# rtc.net
KiCad netlist of a schematic drawn in EAGLE
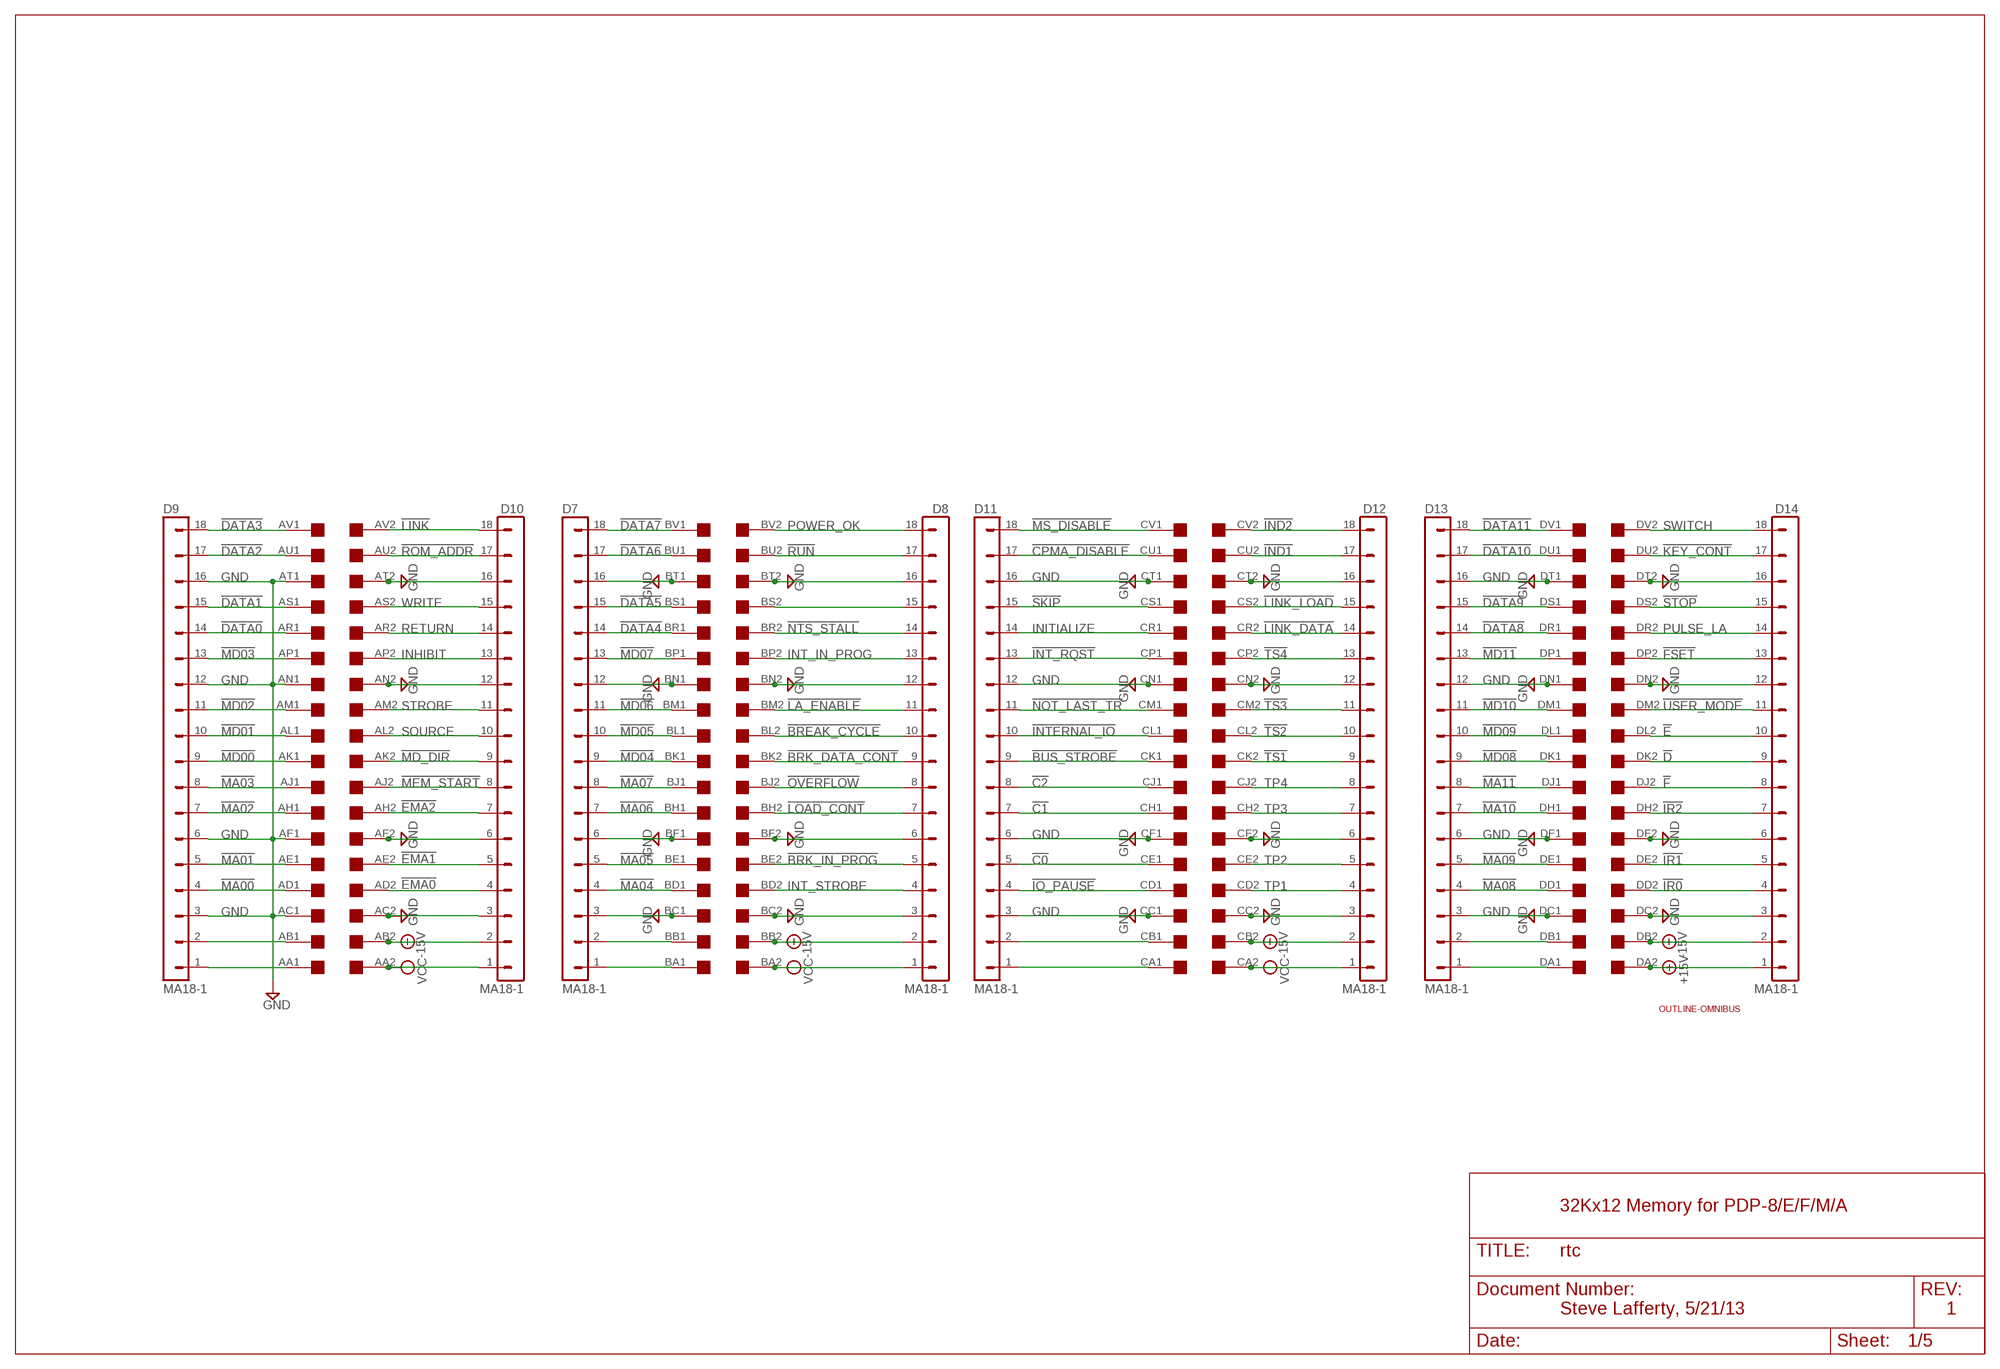
[diagram p0: schematic, sheet 1]
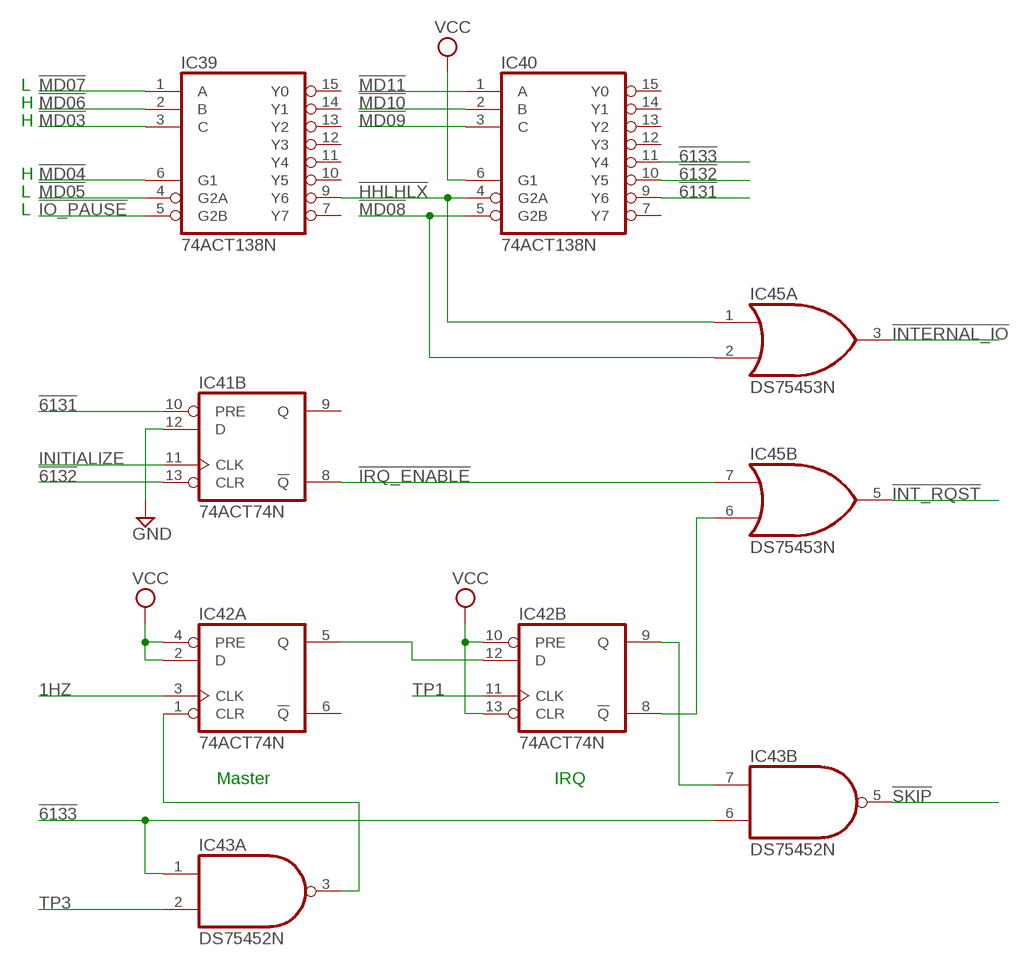
[diagram p1: schematic, sheet 2, part 1 of 2]
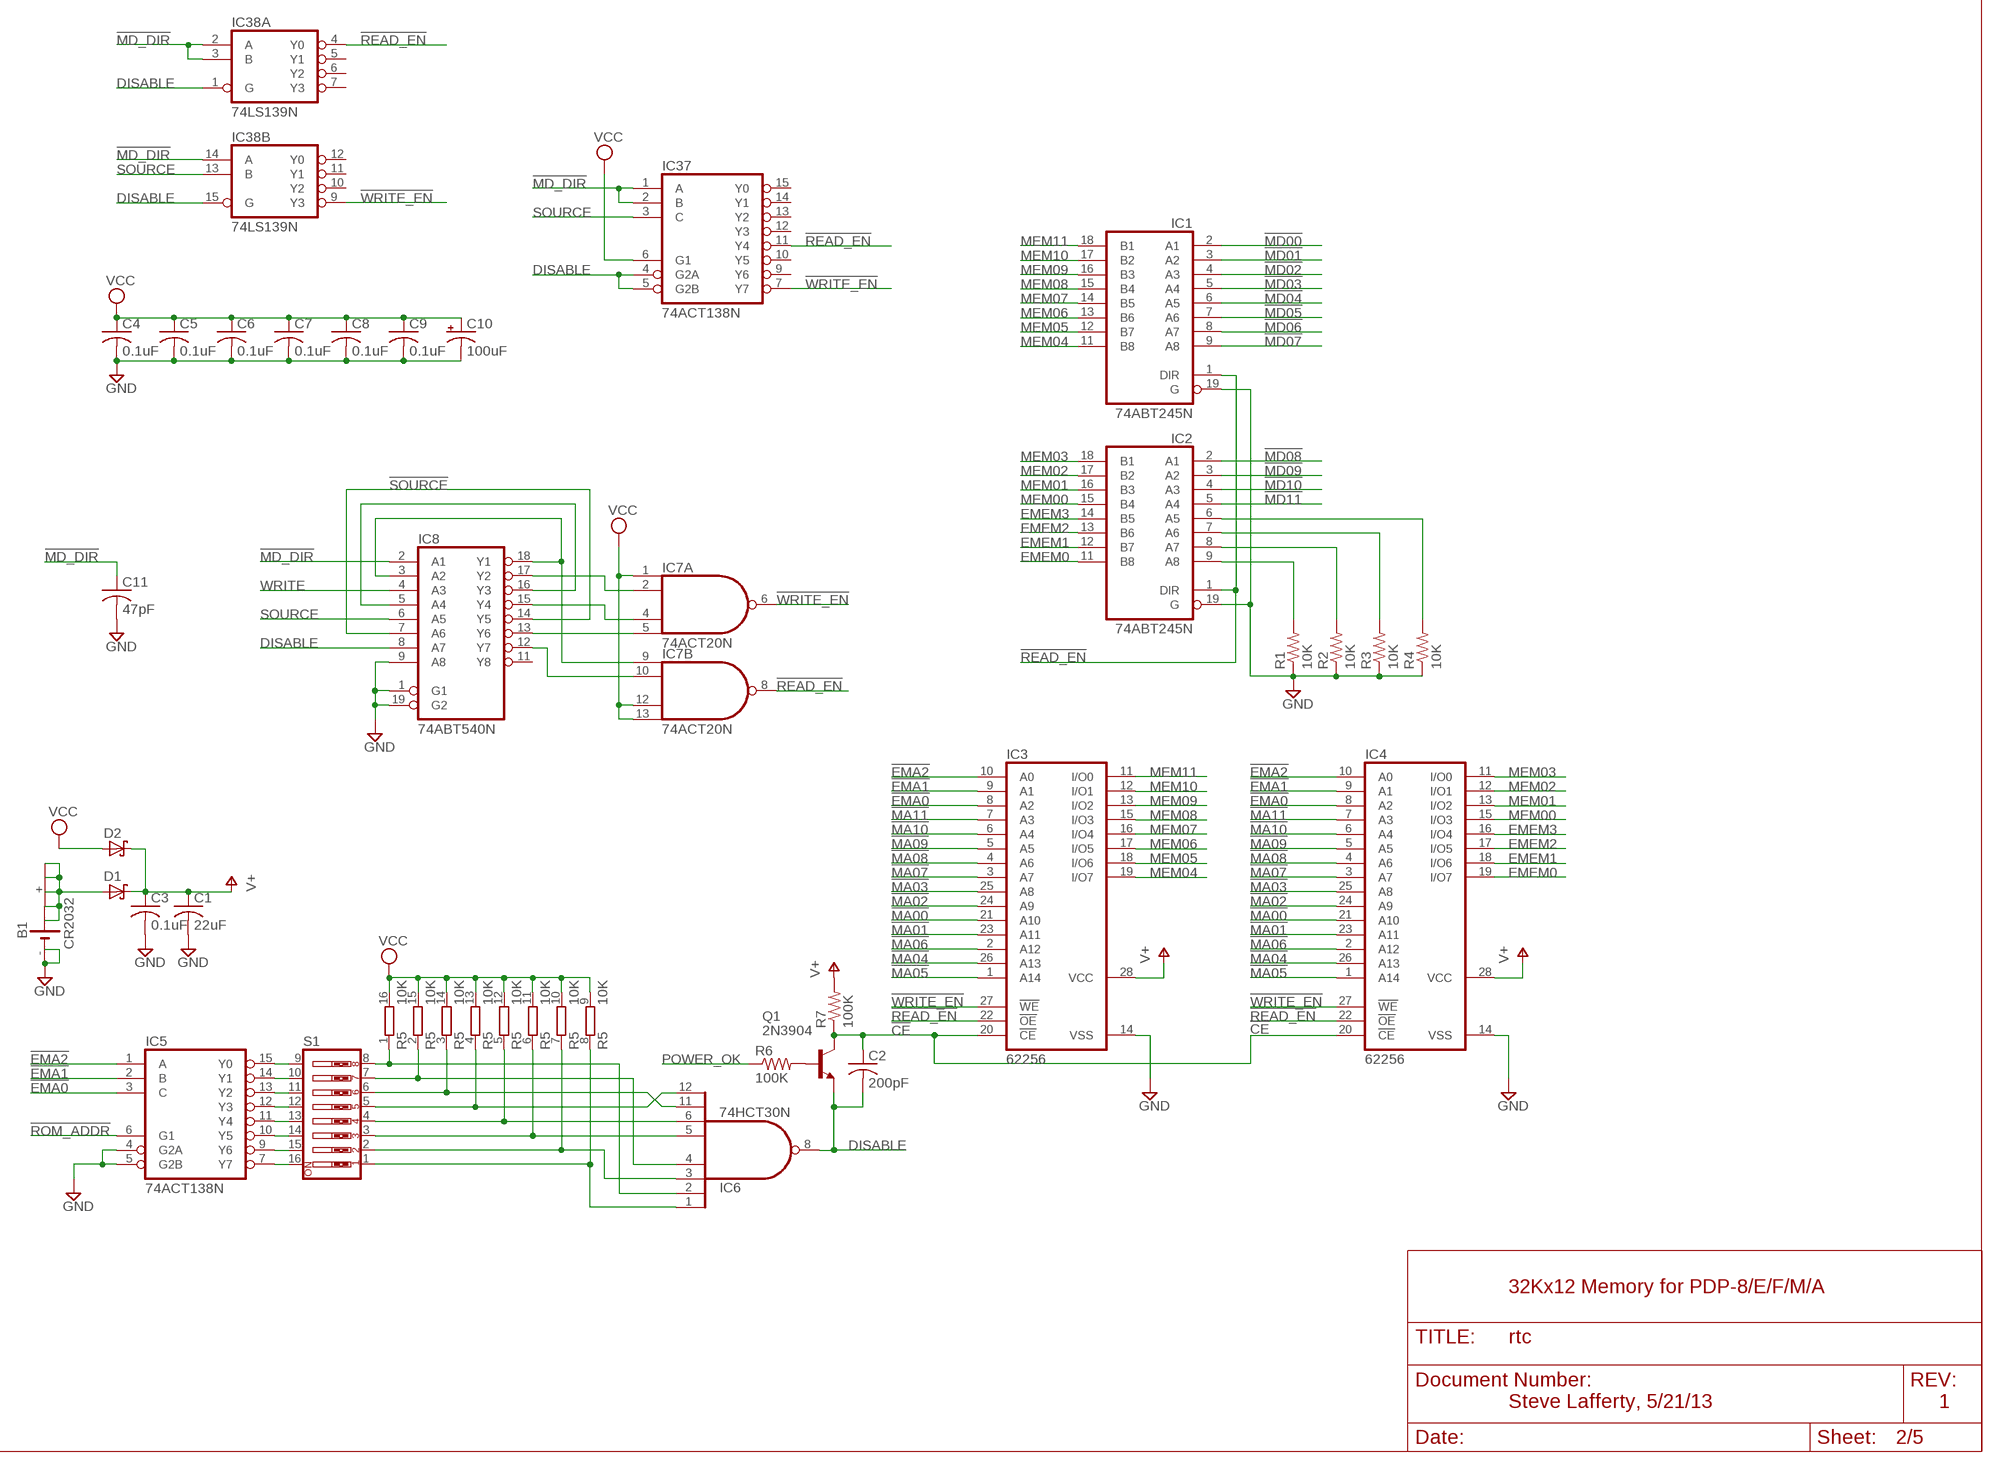
[diagram p2: schematic, sheet 2, part 2 of 2]
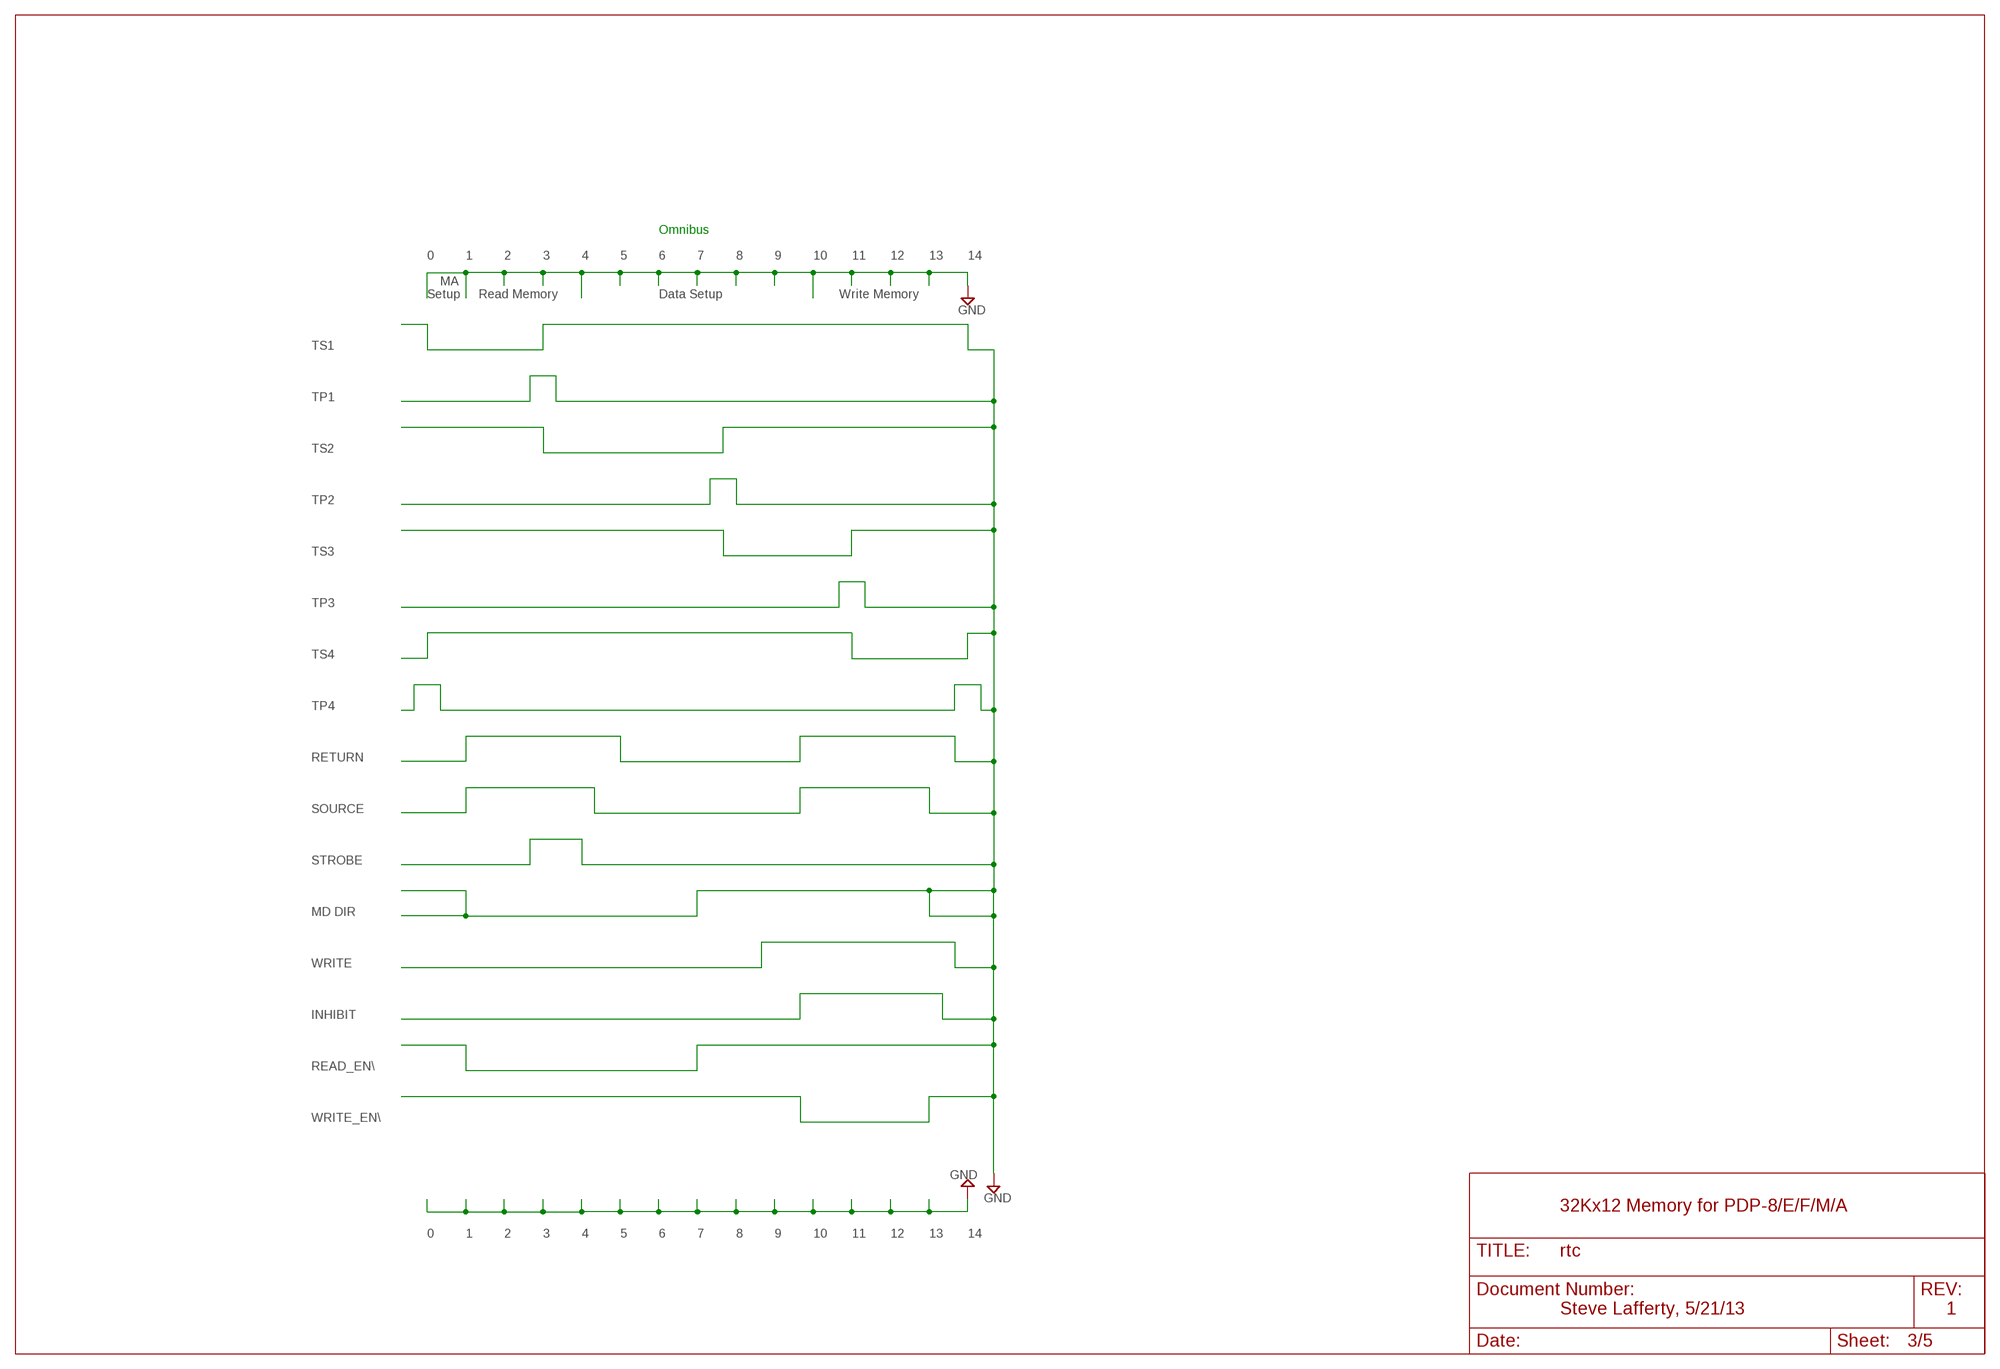
[diagram p3: schematic, sheet 3]
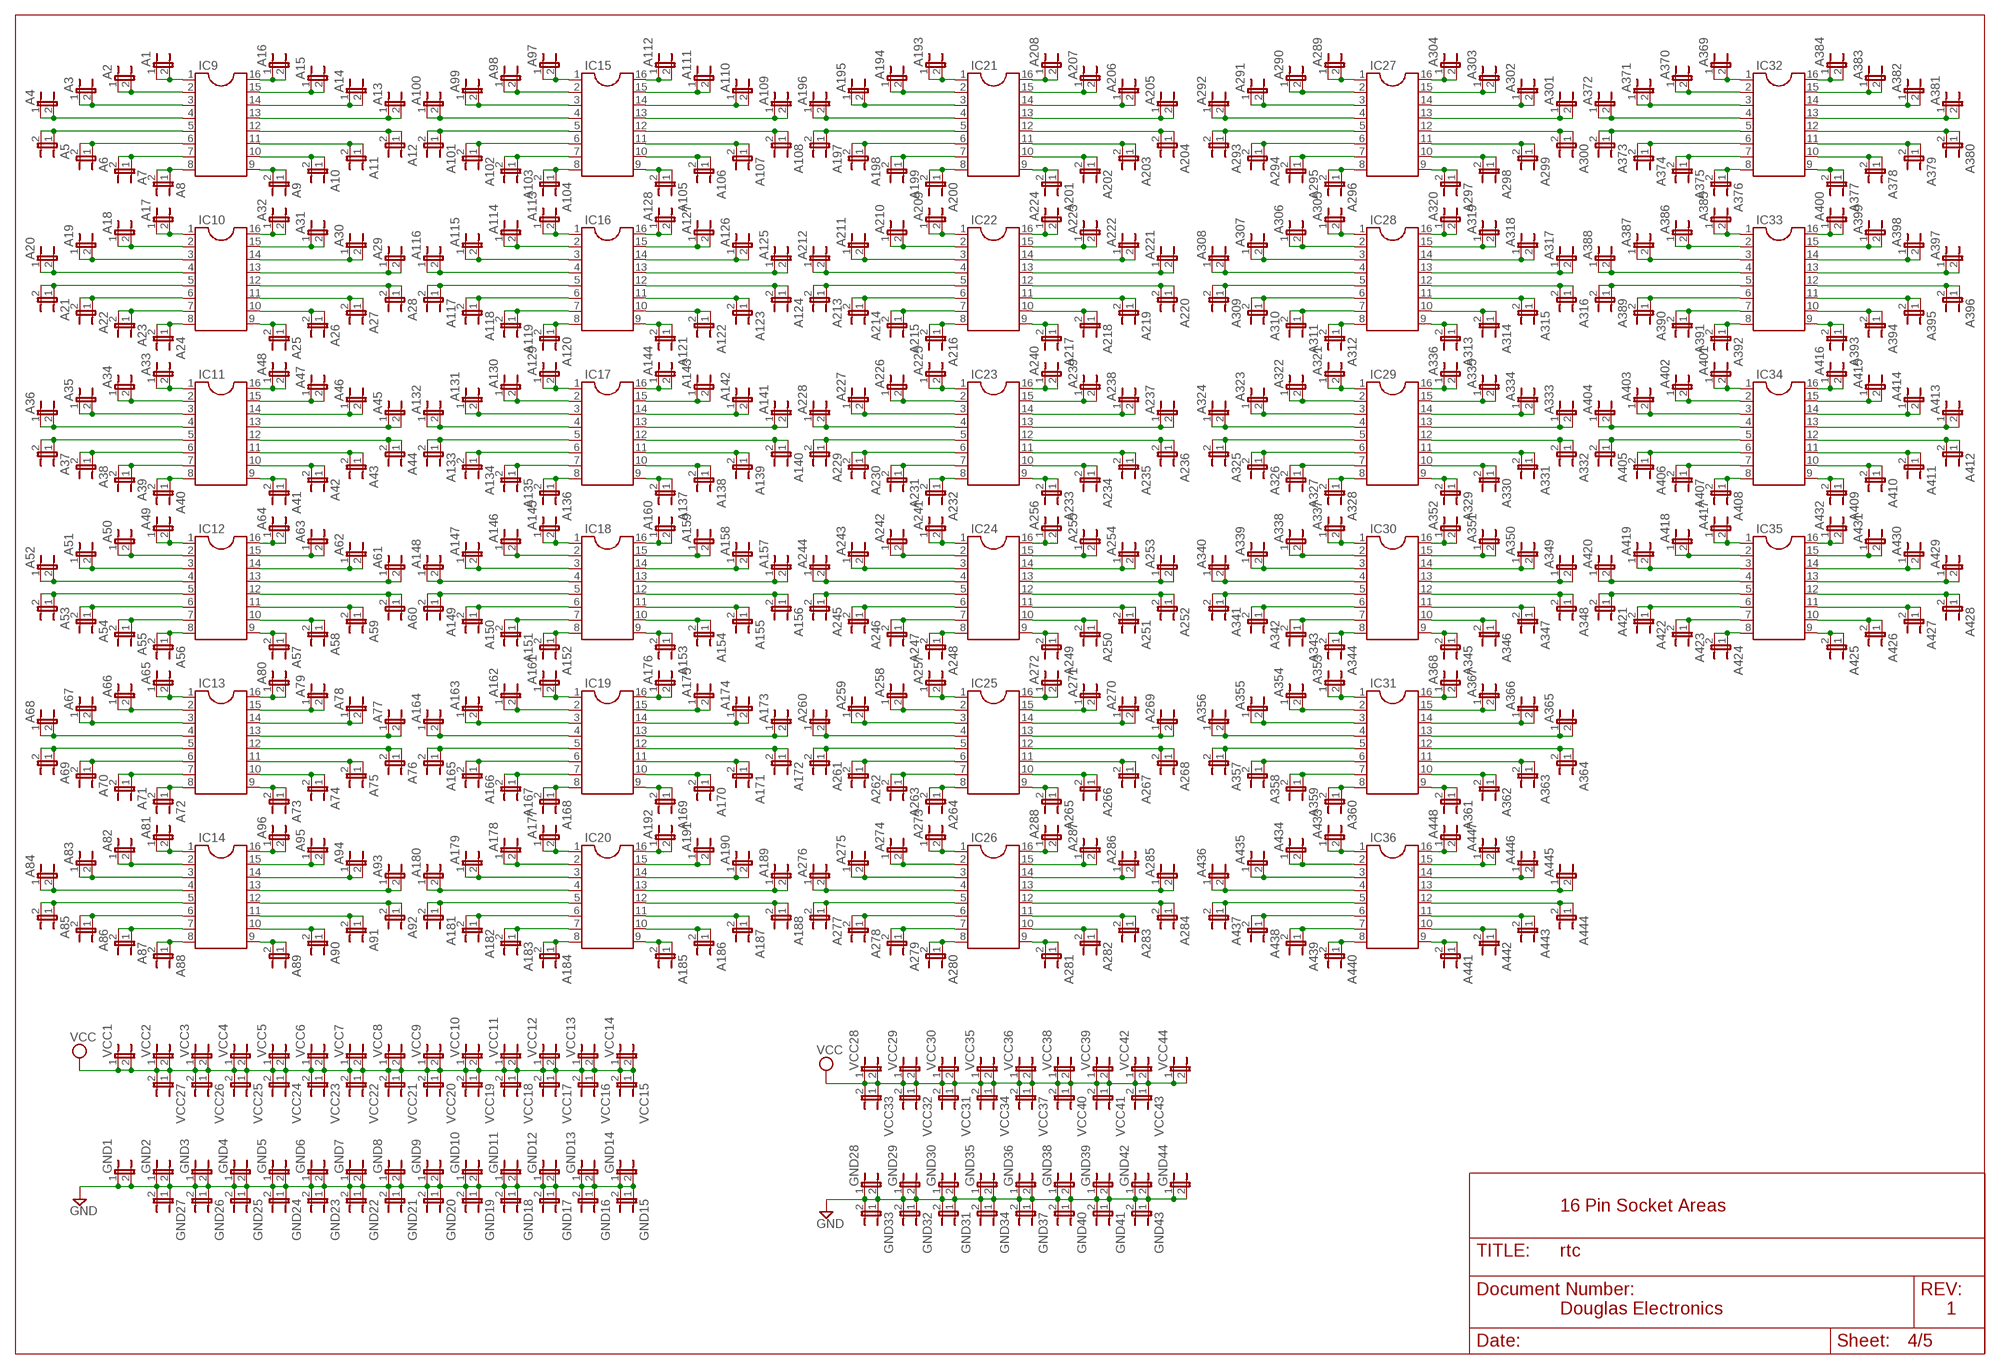
[diagram p4: schematic, sheet 4]
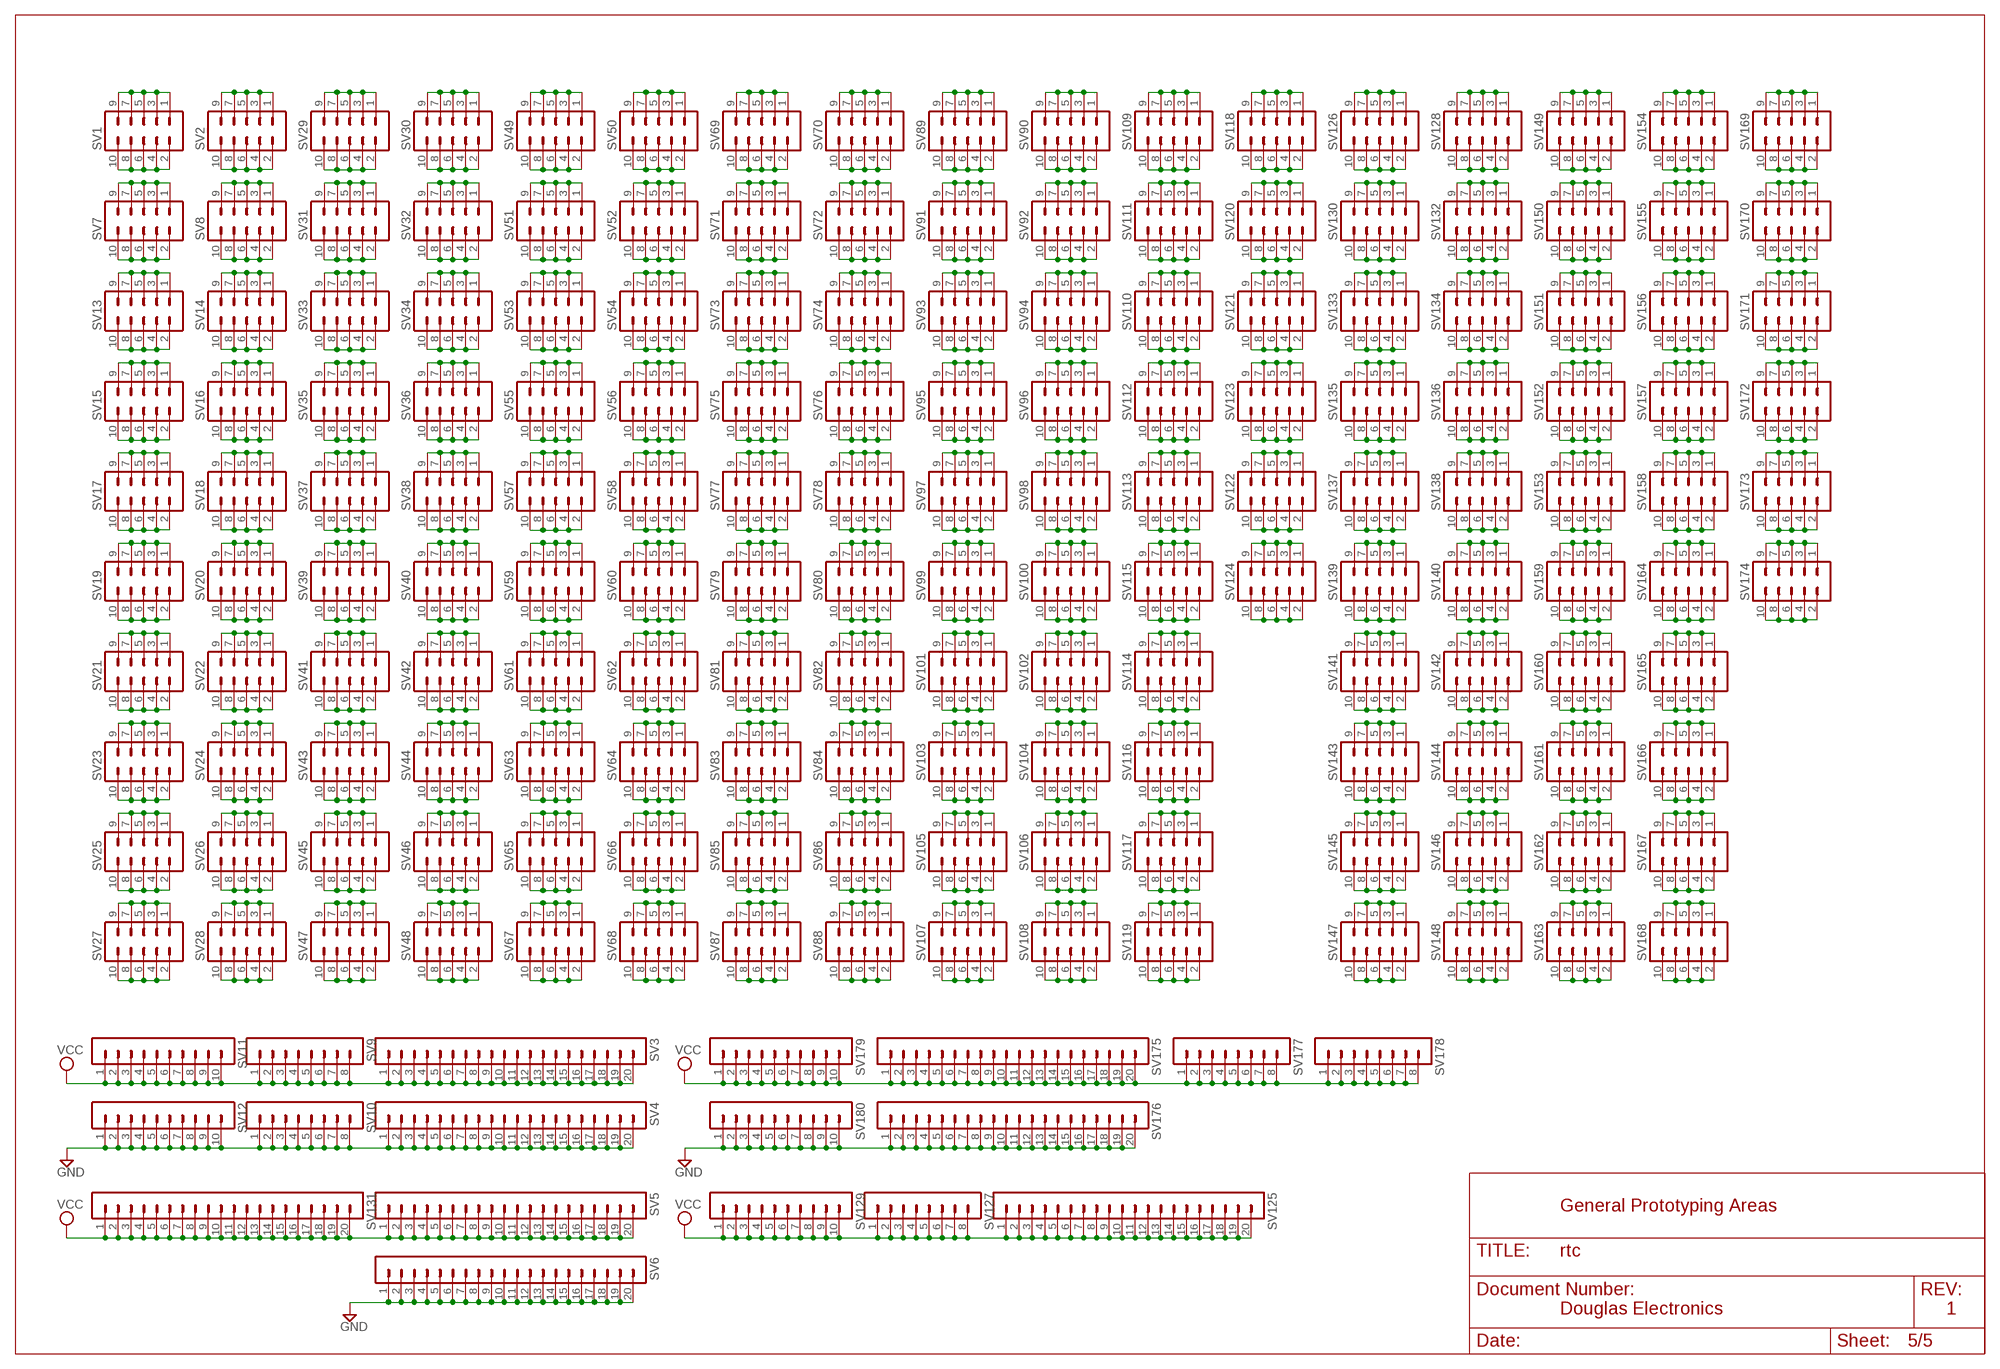
[diagram p5: schematic, sheet 5]

(export (version "E")
  (design (tool "Eeschema 10.0.6"))
  (components
    (comp (ref "D7")
      (value "MA18-1")
      (footprint "eagle-import:MA18-1")
      (libsource (lib "eagle-import") (part "MA18-1"))
    )
    (comp (ref "D8")
      (value "MA18-1")
      (footprint "eagle-import:MA18-1")
      (libsource (lib "eagle-import") (part "MA18-1"))
    )
    (comp (ref "D9")
      (value "MA18-1")
      (footprint "eagle-import:MA18-1")
      (libsource (lib "eagle-import") (part "MA18-1"))
    )
    (comp (ref "D10")
      (value "MA18-1")
      (footprint "eagle-import:MA18-1")
      (libsource (lib "eagle-import") (part "MA18-1"))
    )
    (comp (ref "D11")
      (value "MA18-1")
      (footprint "eagle-import:MA18-1")
      (libsource (lib "eagle-import") (part "MA18-1"))
    )
    (comp (ref "D12")
      (value "MA18-1")
      (footprint "eagle-import:MA18-1")
      (libsource (lib "eagle-import") (part "MA18-1"))
    )
    (comp (ref "D13")
      (value "MA18-1")
      (footprint "eagle-import:MA18-1")
      (libsource (lib "eagle-import") (part "MA18-1"))
    )
    (comp (ref "D14")
      (value "MA18-1")
      (footprint "eagle-import:MA18-1")
      (libsource (lib "eagle-import") (part "MA18-1"))
    )
    (comp (ref "U$1")
      (value "OUTLINE-OMNIBUS")
      (footprint "eagle-import:OMNIBUS")
      (libsource (lib "eagle-import") (part "OUTLINE-OMNIBUS"))
    )
    (comp (ref "U$2")
      (value "QUAD")
      (footprint "eagle-import:EDGE-CON8")
      (libsource (lib "eagle-import") (part "QUAD"))
    )
    (comp (ref "A1")
      (value "JP1E")
      (footprint "eagle-import:JP1")
      (libsource (lib "eagle-import") (part "JP1E"))
    )
    (comp (ref "A2")
      (value "JP1E")
      (footprint "eagle-import:JP1")
      (libsource (lib "eagle-import") (part "JP1E"))
    )
    (comp (ref "A3")
      (value "JP1E")
      (footprint "eagle-import:JP1")
      (libsource (lib "eagle-import") (part "JP1E"))
    )
    (comp (ref "A4")
      (value "JP1E")
      (footprint "eagle-import:JP1")
      (libsource (lib "eagle-import") (part "JP1E"))
    )
    (comp (ref "A5")
      (value "JP1E")
      (footprint "eagle-import:JP1")
      (libsource (lib "eagle-import") (part "JP1E"))
    )
    (comp (ref "A6")
      (value "JP1E")
      (footprint "eagle-import:JP1")
      (libsource (lib "eagle-import") (part "JP1E"))
    )
    (comp (ref "A7")
      (value "JP1E")
      (footprint "eagle-import:JP1")
      (libsource (lib "eagle-import") (part "JP1E"))
    )
    (comp (ref "A8")
      (value "JP1E")
      (footprint "eagle-import:JP1")
      (libsource (lib "eagle-import") (part "JP1E"))
    )
    (comp (ref "A9")
      (value "JP1E")
      (footprint "eagle-import:JP1")
      (libsource (lib "eagle-import") (part "JP1E"))
    )
    (comp (ref "A10")
      (value "JP1E")
      (footprint "eagle-import:JP1")
      (libsource (lib "eagle-import") (part "JP1E"))
    )
    (comp (ref "A11")
      (value "JP1E")
      (footprint "eagle-import:JP1")
      (libsource (lib "eagle-import") (part "JP1E"))
    )
    (comp (ref "A12")
      (value "JP1E")
      (footprint "eagle-import:JP1")
      (libsource (lib "eagle-import") (part "JP1E"))
    )
    (comp (ref "A13")
      (value "JP1E")
      (footprint "eagle-import:JP1")
      (libsource (lib "eagle-import") (part "JP1E"))
    )
    (comp (ref "A14")
      (value "JP1E")
      (footprint "eagle-import:JP1")
      (libsource (lib "eagle-import") (part "JP1E"))
    )
    (comp (ref "A15")
      (value "JP1E")
      (footprint "eagle-import:JP1")
      (libsource (lib "eagle-import") (part "JP1E"))
    )
    (comp (ref "A16")
      (value "JP1E")
      (footprint "eagle-import:JP1")
      (libsource (lib "eagle-import") (part "JP1E"))
    )
    (comp (ref "A17")
      (value "JP1E")
      (footprint "eagle-import:JP1")
      (libsource (lib "eagle-import") (part "JP1E"))
    )
    (comp (ref "A18")
      (value "JP1E")
      (footprint "eagle-import:JP1")
      (libsource (lib "eagle-import") (part "JP1E"))
    )
    (comp (ref "A19")
      (value "JP1E")
      (footprint "eagle-import:JP1")
      (libsource (lib "eagle-import") (part "JP1E"))
    )
    (comp (ref "A20")
      (value "JP1E")
      (footprint "eagle-import:JP1")
      (libsource (lib "eagle-import") (part "JP1E"))
    )
    (comp (ref "A21")
      (value "JP1E")
      (footprint "eagle-import:JP1")
      (libsource (lib "eagle-import") (part "JP1E"))
    )
    (comp (ref "A22")
      (value "JP1E")
      (footprint "eagle-import:JP1")
      (libsource (lib "eagle-import") (part "JP1E"))
    )
    (comp (ref "A23")
      (value "JP1E")
      (footprint "eagle-import:JP1")
      (libsource (lib "eagle-import") (part "JP1E"))
    )
    (comp (ref "A24")
      (value "JP1E")
      (footprint "eagle-import:JP1")
      (libsource (lib "eagle-import") (part "JP1E"))
    )
    (comp (ref "A25")
      (value "JP1E")
      (footprint "eagle-import:JP1")
      (libsource (lib "eagle-import") (part "JP1E"))
    )
    (comp (ref "A26")
      (value "JP1E")
      (footprint "eagle-import:JP1")
      (libsource (lib "eagle-import") (part "JP1E"))
    )
    (comp (ref "A27")
      (value "JP1E")
      (footprint "eagle-import:JP1")
      (libsource (lib "eagle-import") (part "JP1E"))
    )
    (comp (ref "A28")
      (value "JP1E")
      (footprint "eagle-import:JP1")
      (libsource (lib "eagle-import") (part "JP1E"))
    )
    (comp (ref "A29")
      (value "JP1E")
      (footprint "eagle-import:JP1")
      (libsource (lib "eagle-import") (part "JP1E"))
    )
    (comp (ref "A30")
      (value "JP1E")
      (footprint "eagle-import:JP1")
      (libsource (lib "eagle-import") (part "JP1E"))
    )
    (comp (ref "A31")
      (value "JP1E")
      (footprint "eagle-import:JP1")
      (libsource (lib "eagle-import") (part "JP1E"))
    )
    (comp (ref "A32")
      (value "JP1E")
      (footprint "eagle-import:JP1")
      (libsource (lib "eagle-import") (part "JP1E"))
    )
    (comp (ref "A33")
      (value "JP1E")
      (footprint "eagle-import:JP1")
      (libsource (lib "eagle-import") (part "JP1E"))
    )
    (comp (ref "A34")
      (value "JP1E")
      (footprint "eagle-import:JP1")
      (libsource (lib "eagle-import") (part "JP1E"))
    )
    (comp (ref "A35")
      (value "JP1E")
      (footprint "eagle-import:JP1")
      (libsource (lib "eagle-import") (part "JP1E"))
    )
    (comp (ref "A36")
      (value "JP1E")
      (footprint "eagle-import:JP1")
      (libsource (lib "eagle-import") (part "JP1E"))
    )
    (comp (ref "A37")
      (value "JP1E")
      (footprint "eagle-import:JP1")
      (libsource (lib "eagle-import") (part "JP1E"))
    )
    (comp (ref "A38")
      (value "JP1E")
      (footprint "eagle-import:JP1")
      (libsource (lib "eagle-import") (part "JP1E"))
    )
    (comp (ref "A39")
      (value "JP1E")
      (footprint "eagle-import:JP1")
      (libsource (lib "eagle-import") (part "JP1E"))
    )
    (comp (ref "A40")
      (value "JP1E")
      (footprint "eagle-import:JP1")
      (libsource (lib "eagle-import") (part "JP1E"))
    )
    (comp (ref "A41")
      (value "JP1E")
      (footprint "eagle-import:JP1")
      (libsource (lib "eagle-import") (part "JP1E"))
    )
    (comp (ref "A42")
      (value "JP1E")
      (footprint "eagle-import:JP1")
      (libsource (lib "eagle-import") (part "JP1E"))
    )
    (comp (ref "A43")
      (value "JP1E")
      (footprint "eagle-import:JP1")
      (libsource (lib "eagle-import") (part "JP1E"))
    )
    (comp (ref "A44")
      (value "JP1E")
      (footprint "eagle-import:JP1")
      (libsource (lib "eagle-import") (part "JP1E"))
    )
    (comp (ref "A45")
      (value "JP1E")
      (footprint "eagle-import:JP1")
      (libsource (lib "eagle-import") (part "JP1E"))
    )
    (comp (ref "A46")
      (value "JP1E")
      (footprint "eagle-import:JP1")
      (libsource (lib "eagle-import") (part "JP1E"))
    )
    (comp (ref "A47")
      (value "JP1E")
      (footprint "eagle-import:JP1")
      (libsource (lib "eagle-import") (part "JP1E"))
    )
    (comp (ref "A48")
      (value "JP1E")
      (footprint "eagle-import:JP1")
      (libsource (lib "eagle-import") (part "JP1E"))
    )
    (comp (ref "A49")
      (value "JP1E")
      (footprint "eagle-import:JP1")
      (libsource (lib "eagle-import") (part "JP1E"))
    )
    (comp (ref "A50")
      (value "JP1E")
      (footprint "eagle-import:JP1")
      (libsource (lib "eagle-import") (part "JP1E"))
    )
    (comp (ref "A51")
      (value "JP1E")
      (footprint "eagle-import:JP1")
      (libsource (lib "eagle-import") (part "JP1E"))
    )
    (comp (ref "A52")
      (value "JP1E")
      (footprint "eagle-import:JP1")
      (libsource (lib "eagle-import") (part "JP1E"))
    )
    (comp (ref "A53")
      (value "JP1E")
      (footprint "eagle-import:JP1")
      (libsource (lib "eagle-import") (part "JP1E"))
    )
    (comp (ref "A54")
      (value "JP1E")
      (footprint "eagle-import:JP1")
      (libsource (lib "eagle-import") (part "JP1E"))
    )
    (comp (ref "A55")
      (value "JP1E")
      (footprint "eagle-import:JP1")
      (libsource (lib "eagle-import") (part "JP1E"))
    )
    (comp (ref "A56")
      (value "JP1E")
      (footprint "eagle-import:JP1")
      (libsource (lib "eagle-import") (part "JP1E"))
    )
    (comp (ref "A57")
      (value "JP1E")
      (footprint "eagle-import:JP1")
      (libsource (lib "eagle-import") (part "JP1E"))
    )
    (comp (ref "A58")
      (value "JP1E")
      (footprint "eagle-import:JP1")
      (libsource (lib "eagle-import") (part "JP1E"))
    )
    (comp (ref "A59")
      (value "JP1E")
      (footprint "eagle-import:JP1")
      (libsource (lib "eagle-import") (part "JP1E"))
    )
    (comp (ref "A60")
      (value "JP1E")
      (footprint "eagle-import:JP1")
      (libsource (lib "eagle-import") (part "JP1E"))
    )
    (comp (ref "A61")
      (value "JP1E")
      (footprint "eagle-import:JP1")
      (libsource (lib "eagle-import") (part "JP1E"))
    )
    (comp (ref "A62")
      (value "JP1E")
      (footprint "eagle-import:JP1")
      (libsource (lib "eagle-import") (part "JP1E"))
    )
    (comp (ref "A63")
      (value "JP1E")
      (footprint "eagle-import:JP1")
      (libsource (lib "eagle-import") (part "JP1E"))
    )
    (comp (ref "A64")
      (value "JP1E")
      (footprint "eagle-import:JP1")
      (libsource (lib "eagle-import") (part "JP1E"))
    )
    (comp (ref "A65")
      (value "JP1E")
      (footprint "eagle-import:JP1")
      (libsource (lib "eagle-import") (part "JP1E"))
    )
    (comp (ref "A66")
      (value "JP1E")
      (footprint "eagle-import:JP1")
      (libsource (lib "eagle-import") (part "JP1E"))
    )
    (comp (ref "A67")
      (value "JP1E")
      (footprint "eagle-import:JP1")
      (libsource (lib "eagle-import") (part "JP1E"))
    )
    (comp (ref "A68")
      (value "JP1E")
      (footprint "eagle-import:JP1")
      (libsource (lib "eagle-import") (part "JP1E"))
    )
    (comp (ref "A69")
      (value "JP1E")
      (footprint "eagle-import:JP1")
      (libsource (lib "eagle-import") (part "JP1E"))
    )
    (comp (ref "A70")
      (value "JP1E")
      (footprint "eagle-import:JP1")
      (libsource (lib "eagle-import") (part "JP1E"))
    )
    (comp (ref "A71")
      (value "JP1E")
      (footprint "eagle-import:JP1")
      (libsource (lib "eagle-import") (part "JP1E"))
    )
    (comp (ref "A72")
      (value "JP1E")
      (footprint "eagle-import:JP1")
      (libsource (lib "eagle-import") (part "JP1E"))
    )
    (comp (ref "A73")
      (value "JP1E")
      (footprint "eagle-import:JP1")
      (libsource (lib "eagle-import") (part "JP1E"))
    )
    (comp (ref "A74")
      (value "JP1E")
      (footprint "eagle-import:JP1")
      (libsource (lib "eagle-import") (part "JP1E"))
    )
    (comp (ref "A75")
      (value "JP1E")
      (footprint "eagle-import:JP1")
      (libsource (lib "eagle-import") (part "JP1E"))
    )
    (comp (ref "A76")
      (value "JP1E")
      (footprint "eagle-import:JP1")
      (libsource (lib "eagle-import") (part "JP1E"))
    )
    (comp (ref "A77")
      (value "JP1E")
      (footprint "eagle-import:JP1")
      (libsource (lib "eagle-import") (part "JP1E"))
    )
    (comp (ref "A78")
      (value "JP1E")
      (footprint "eagle-import:JP1")
      (libsource (lib "eagle-import") (part "JP1E"))
    )
    (comp (ref "A79")
      (value "JP1E")
      (footprint "eagle-import:JP1")
      (libsource (lib "eagle-import") (part "JP1E"))
    )
    (comp (ref "A80")
      (value "JP1E")
      (footprint "eagle-import:JP1")
      (libsource (lib "eagle-import") (part "JP1E"))
    )
    (comp (ref "A81")
      (value "JP1E")
      (footprint "eagle-import:JP1")
      (libsource (lib "eagle-import") (part "JP1E"))
    )
    (comp (ref "A82")
      (value "JP1E")
      (footprint "eagle-import:JP1")
      (libsource (lib "eagle-import") (part "JP1E"))
    )
    (comp (ref "A83")
      (value "JP1E")
      (footprint "eagle-import:JP1")
      (libsource (lib "eagle-import") (part "JP1E"))
    )
    (comp (ref "A84")
      (value "JP1E")
      (footprint "eagle-import:JP1")
      (libsource (lib "eagle-import") (part "JP1E"))
    )
    (comp (ref "A85")
      (value "JP1E")
      (footprint "eagle-import:JP1")
      (libsource (lib "eagle-import") (part "JP1E"))
    )
    (comp (ref "A86")
      (value "JP1E")
      (footprint "eagle-import:JP1")
      (libsource (lib "eagle-import") (part "JP1E"))
    )
    (comp (ref "A87")
      (value "JP1E")
      (footprint "eagle-import:JP1")
      (libsource (lib "eagle-import") (part "JP1E"))
    )
    (comp (ref "A88")
      (value "JP1E")
      (footprint "eagle-import:JP1")
      (libsource (lib "eagle-import") (part "JP1E"))
    )
    (comp (ref "A89")
      (value "JP1E")
      (footprint "eagle-import:JP1")
      (libsource (lib "eagle-import") (part "JP1E"))
    )
    (comp (ref "A90")
      (value "JP1E")
      (footprint "eagle-import:JP1")
      (libsource (lib "eagle-import") (part "JP1E"))
    )
    (comp (ref "A91")
      (value "JP1E")
      (footprint "eagle-import:JP1")
      (libsource (lib "eagle-import") (part "JP1E"))
    )
    (comp (ref "A92")
      (value "JP1E")
      (footprint "eagle-import:JP1")
      (libsource (lib "eagle-import") (part "JP1E"))
    )
    (comp (ref "A93")
      (value "JP1E")
      (footprint "eagle-import:JP1")
      (libsource (lib "eagle-import") (part "JP1E"))
    )
    (comp (ref "A94")
      (value "JP1E")
      (footprint "eagle-import:JP1")
      (libsource (lib "eagle-import") (part "JP1E"))
    )
    (comp (ref "A95")
      (value "JP1E")
      (footprint "eagle-import:JP1")
      (libsource (lib "eagle-import") (part "JP1E"))
    )
    (comp (ref "A96")
      (value "JP1E")
      (footprint "eagle-import:JP1")
      (libsource (lib "eagle-import") (part "JP1E"))
    )
    (comp (ref "A97")
      (value "JP1E")
      (footprint "eagle-import:JP1")
      (libsource (lib "eagle-import") (part "JP1E"))
    )
    (comp (ref "A98")
      (value "JP1E")
      (footprint "eagle-import:JP1")
      (libsource (lib "eagle-import") (part "JP1E"))
    )
    (comp (ref "A99")
      (value "JP1E")
      (footprint "eagle-import:JP1")
      (libsource (lib "eagle-import") (part "JP1E"))
    )
    (comp (ref "A100")
      (value "JP1E")
      (footprint "eagle-import:JP1")
      (libsource (lib "eagle-import") (part "JP1E"))
    )
    (comp (ref "A101")
      (value "JP1E")
      (footprint "eagle-import:JP1")
      (libsource (lib "eagle-import") (part "JP1E"))
    )
    (comp (ref "A102")
      (value "JP1E")
      (footprint "eagle-import:JP1")
      (libsource (lib "eagle-import") (part "JP1E"))
    )
    (comp (ref "A103")
      (value "JP1E")
      (footprint "eagle-import:JP1")
      (libsource (lib "eagle-import") (part "JP1E"))
    )
    (comp (ref "A104")
      (value "JP1E")
      (footprint "eagle-import:JP1")
      (libsource (lib "eagle-import") (part "JP1E"))
    )
    (comp (ref "A105")
      (value "JP1E")
      (footprint "eagle-import:JP1")
      (libsource (lib "eagle-import") (part "JP1E"))
    )
    (comp (ref "A106")
      (value "JP1E")
      (footprint "eagle-import:JP1")
      (libsource (lib "eagle-import") (part "JP1E"))
    )
    (comp (ref "A107")
      (value "JP1E")
      (footprint "eagle-import:JP1")
      (libsource (lib "eagle-import") (part "JP1E"))
    )
    (comp (ref "A108")
      (value "JP1E")
      (footprint "eagle-import:JP1")
      (libsource (lib "eagle-import") (part "JP1E"))
    )
    (comp (ref "A109")
      (value "JP1E")
      (footprint "eagle-import:JP1")
      (libsource (lib "eagle-import") (part "JP1E"))
    )
    (comp (ref "A110")
      (value "JP1E")
      (footprint "eagle-import:JP1")
      (libsource (lib "eagle-import") (part "JP1E"))
    )
    (comp (ref "A111")
      (value "JP1E")
      (footprint "eagle-import:JP1")
      (libsource (lib "eagle-import") (part "JP1E"))
    )
    (comp (ref "A112")
      (value "JP1E")
      (footprint "eagle-import:JP1")
      (libsource (lib "eagle-import") (part "JP1E"))
    )
    (comp (ref "A113")
      (value "JP1E")
      (footprint "eagle-import:JP1")
      (libsource (lib "eagle-import") (part "JP1E"))
    )
    (comp (ref "A114")
      (value "JP1E")
      (footprint "eagle-import:JP1")
      (libsource (lib "eagle-import") (part "JP1E"))
    )
    (comp (ref "A115")
      (value "JP1E")
      (footprint "eagle-import:JP1")
      (libsource (lib "eagle-import") (part "JP1E"))
    )
    (comp (ref "A116")
      (value "JP1E")
      (footprint "eagle-import:JP1")
      (libsource (lib "eagle-import") (part "JP1E"))
    )
    (comp (ref "A117")
      (value "JP1E")
      (footprint "eagle-import:JP1")
      (libsource (lib "eagle-import") (part "JP1E"))
    )
    (comp (ref "A118")
      (value "JP1E")
      (footprint "eagle-import:JP1")
      (libsource (lib "eagle-import") (part "JP1E"))
    )
    (comp (ref "A119")
      (value "JP1E")
      (footprint "eagle-import:JP1")
      (libsource (lib "eagle-import") (part "JP1E"))
    )
    (comp (ref "A120")
      (value "JP1E")
      (footprint "eagle-import:JP1")
      (libsource (lib "eagle-import") (part "JP1E"))
    )
    (comp (ref "A121")
      (value "JP1E")
      (footprint "eagle-import:JP1")
      (libsource (lib "eagle-import") (part "JP1E"))
    )
    (comp (ref "A122")
      (value "JP1E")
      (footprint "eagle-import:JP1")
      (libsource (lib "eagle-import") (part "JP1E"))
    )
    (comp (ref "A123")
      (value "JP1E")
      (footprint "eagle-import:JP1")
      (libsource (lib "eagle-import") (part "JP1E"))
    )
    (comp (ref "A124")
      (value "JP1E")
      (footprint "eagle-import:JP1")
      (libsource (lib "eagle-import") (part "JP1E"))
    )
    (comp (ref "A125")
      (value "JP1E")
      (footprint "eagle-import:JP1")
      (libsource (lib "eagle-import") (part "JP1E"))
    )
    (comp (ref "A126")
      (value "JP1E")
      (footprint "eagle-import:JP1")
      (libsource (lib "eagle-import") (part "JP1E"))
    )
    (comp (ref "A127")
      (value "JP1E")
      (footprint "eagle-import:JP1")
      (libsource (lib "eagle-import") (part "JP1E"))
    )
    (comp (ref "A128")
      (value "JP1E")
      (footprint "eagle-import:JP1")
      (libsource (lib "eagle-import") (part "JP1E"))
    )
    (comp (ref "A129")
      (value "JP1E")
      (footprint "eagle-import:JP1")
      (libsource (lib "eagle-import") (part "JP1E"))
    )
    (comp (ref "A130")
      (value "JP1E")
      (footprint "eagle-import:JP1")
      (libsource (lib "eagle-import") (part "JP1E"))
    )
    (comp (ref "A131")
      (value "JP1E")
      (footprint "eagle-import:JP1")
      (libsource (lib "eagle-import") (part "JP1E"))
    )
    (comp (ref "A132")
      (value "JP1E")
      (footprint "eagle-import:JP1")
      (libsource (lib "eagle-import") (part "JP1E"))
    )
    (comp (ref "A133")
      (value "JP1E")
      (footprint "eagle-import:JP1")
      (libsource (lib "eagle-import") (part "JP1E"))
    )
    (comp (ref "A134")
      (value "JP1E")
      (footprint "eagle-import:JP1")
      (libsource (lib "eagle-import") (part "JP1E"))
    )
    (comp (ref "A135")
      (value "JP1E")
      (footprint "eagle-import:JP1")
      (libsource (lib "eagle-import") (part "JP1E"))
    )
    (comp (ref "A136")
      (value "JP1E")
      (footprint "eagle-import:JP1")
      (libsource (lib "eagle-import") (part "JP1E"))
    )
    (comp (ref "A137")
      (value "JP1E")
      (footprint "eagle-import:JP1")
      (libsource (lib "eagle-import") (part "JP1E"))
    )
    (comp (ref "A138")
      (value "JP1E")
      (footprint "eagle-import:JP1")
      (libsource (lib "eagle-import") (part "JP1E"))
    )
    (comp (ref "A139")
      (value "JP1E")
      (footprint "eagle-import:JP1")
      (libsource (lib "eagle-import") (part "JP1E"))
    )
    (comp (ref "A140")
      (value "JP1E")
      (footprint "eagle-import:JP1")
      (libsource (lib "eagle-import") (part "JP1E"))
    )
    (comp (ref "A141")
      (value "JP1E")
      (footprint "eagle-import:JP1")
      (libsource (lib "eagle-import") (part "JP1E"))
    )
    (comp (ref "A142")
      (value "JP1E")
      (footprint "eagle-import:JP1")
      (libsource (lib "eagle-import") (part "JP1E"))
    )
    (comp (ref "A143")
      (value "JP1E")
      (footprint "eagle-import:JP1")
      (libsource (lib "eagle-import") (part "JP1E"))
    )
    (comp (ref "A144")
      (value "JP1E")
      (footprint "eagle-import:JP1")
      (libsource (lib "eagle-import") (part "JP1E"))
    )
    (comp (ref "A145")
      (value "JP1E")
      (footprint "eagle-import:JP1")
      (libsource (lib "eagle-import") (part "JP1E"))
    )
    (comp (ref "A146")
      (value "JP1E")
      (footprint "eagle-import:JP1")
      (libsource (lib "eagle-import") (part "JP1E"))
    )
    (comp (ref "A147")
      (value "JP1E")
      (footprint "eagle-import:JP1")
      (libsource (lib "eagle-import") (part "JP1E"))
    )
    (comp (ref "A148")
      (value "JP1E")
      (footprint "eagle-import:JP1")
      (libsource (lib "eagle-import") (part "JP1E"))
    )
    (comp (ref "A149")
      (value "JP1E")
      (footprint "eagle-import:JP1")
      (libsource (lib "eagle-import") (part "JP1E"))
    )
    (comp (ref "A150")
      (value "JP1E")
      (footprint "eagle-import:JP1")
      (libsource (lib "eagle-import") (part "JP1E"))
    )
    (comp (ref "A151")
      (value "JP1E")
      (footprint "eagle-import:JP1")
      (libsource (lib "eagle-import") (part "JP1E"))
    )
    (comp (ref "A152")
      (value "JP1E")
      (footprint "eagle-import:JP1")
      (libsource (lib "eagle-import") (part "JP1E"))
    )
    (comp (ref "A153")
      (value "JP1E")
      (footprint "eagle-import:JP1")
      (libsource (lib "eagle-import") (part "JP1E"))
    )
    (comp (ref "A154")
      (value "JP1E")
      (footprint "eagle-import:JP1")
      (libsource (lib "eagle-import") (part "JP1E"))
    )
    (comp (ref "A155")
      (value "JP1E")
      (footprint "eagle-import:JP1")
      (libsource (lib "eagle-import") (part "JP1E"))
    )
    (comp (ref "A156")
      (value "JP1E")
      (footprint "eagle-import:JP1")
      (libsource (lib "eagle-import") (part "JP1E"))
    )
    (comp (ref "A157")
      (value "JP1E")
      (footprint "eagle-import:JP1")
      (libsource (lib "eagle-import") (part "JP1E"))
    )
    (comp (ref "A158")
      (value "JP1E")
      (footprint "eagle-import:JP1")
      (libsource (lib "eagle-import") (part "JP1E"))
    )
    (comp (ref "A159")
      (value "JP1E")
      (footprint "eagle-import:JP1")
      (libsource (lib "eagle-import") (part "JP1E"))
    )
    (comp (ref "A160")
      (value "JP1E")
      (footprint "eagle-import:JP1")
      (libsource (lib "eagle-import") (part "JP1E"))
    )
    (comp (ref "A161")
      (value "JP1E")
      (footprint "eagle-import:JP1")
      (libsource (lib "eagle-import") (part "JP1E"))
    )
    (comp (ref "A162")
      (value "JP1E")
      (footprint "eagle-import:JP1")
      (libsource (lib "eagle-import") (part "JP1E"))
    )
    (comp (ref "A163")
      (value "JP1E")
      (footprint "eagle-import:JP1")
      (libsource (lib "eagle-import") (part "JP1E"))
    )
    (comp (ref "A164")
      (value "JP1E")
      (footprint "eagle-import:JP1")
      (libsource (lib "eagle-import") (part "JP1E"))
    )
    (comp (ref "A165")
      (value "JP1E")
      (footprint "eagle-import:JP1")
      (libsource (lib "eagle-import") (part "JP1E"))
    )
    (comp (ref "A166")
      (value "JP1E")
      (footprint "eagle-import:JP1")
      (libsource (lib "eagle-import") (part "JP1E"))
    )
    (comp (ref "A167")
      (value "JP1E")
      (footprint "eagle-import:JP1")
      (libsource (lib "eagle-import") (part "JP1E"))
    )
    (comp (ref "A168")
      (value "JP1E")
      (footprint "eagle-import:JP1")
      (libsource (lib "eagle-import") (part "JP1E"))
    )
    (comp (ref "A169")
      (value "JP1E")
      (footprint "eagle-import:JP1")
      (libsource (lib "eagle-import") (part "JP1E"))
    )
    (comp (ref "A170")
      (value "JP1E")
      (footprint "eagle-import:JP1")
      (libsource (lib "eagle-import") (part "JP1E"))
    )
    (comp (ref "A171")
      (value "JP1E")
      (footprint "eagle-import:JP1")
      (libsource (lib "eagle-import") (part "JP1E"))
    )
    (comp (ref "A172")
      (value "JP1E")
      (footprint "eagle-import:JP1")
      (libsource (lib "eagle-import") (part "JP1E"))
    )
    (comp (ref "A173")
      (value "JP1E")
      (footprint "eagle-import:JP1")
      (libsource (lib "eagle-import") (part "JP1E"))
    )
    (comp (ref "A174")
      (value "JP1E")
      (footprint "eagle-import:JP1")
      (libsource (lib "eagle-import") (part "JP1E"))
    )
    (comp (ref "A175")
      (value "JP1E")
      (footprint "eagle-import:JP1")
      (libsource (lib "eagle-import") (part "JP1E"))
    )
    (comp (ref "A176")
      (value "JP1E")
      (footprint "eagle-import:JP1")
      (libsource (lib "eagle-import") (part "JP1E"))
    )
    (comp (ref "A177")
      (value "JP1E")
      (footprint "eagle-import:JP1")
      (libsource (lib "eagle-import") (part "JP1E"))
    )
    (comp (ref "A178")
      (value "JP1E")
      (footprint "eagle-import:JP1")
      (libsource (lib "eagle-import") (part "JP1E"))
    )
    (comp (ref "A179")
      (value "JP1E")
      (footprint "eagle-import:JP1")
      (libsource (lib "eagle-import") (part "JP1E"))
    )
    (comp (ref "A180")
      (value "JP1E")
      (footprint "eagle-import:JP1")
      (libsource (lib "eagle-import") (part "JP1E"))
    )
    (comp (ref "A181")
      (value "JP1E")
      (footprint "eagle-import:JP1")
      (libsource (lib "eagle-import") (part "JP1E"))
    )
    (comp (ref "A182")
      (value "JP1E")
      (footprint "eagle-import:JP1")
      (libsource (lib "eagle-import") (part "JP1E"))
    )
    (comp (ref "A183")
      (value "JP1E")
      (footprint "eagle-import:JP1")
      (libsource (lib "eagle-import") (part "JP1E"))
    )
    (comp (ref "A184")
      (value "JP1E")
      (footprint "eagle-import:JP1")
      (libsource (lib "eagle-import") (part "JP1E"))
    )
    (comp (ref "A185")
      (value "JP1E")
      (footprint "eagle-import:JP1")
      (libsource (lib "eagle-import") (part "JP1E"))
    )
    (comp (ref "A186")
      (value "JP1E")
      (footprint "eagle-import:JP1")
      (libsource (lib "eagle-import") (part "JP1E"))
    )
    (comp (ref "A187")
      (value "JP1E")
      (footprint "eagle-import:JP1")
      (libsource (lib "eagle-import") (part "JP1E"))
    )
    (comp (ref "A188")
      (value "JP1E")
      (footprint "eagle-import:JP1")
      (libsource (lib "eagle-import") (part "JP1E"))
    )
    (comp (ref "A189")
      (value "JP1E")
      (footprint "eagle-import:JP1")
      (libsource (lib "eagle-import") (part "JP1E"))
    )
    (comp (ref "A190")
      (value "JP1E")
      (footprint "eagle-import:JP1")
      (libsource (lib "eagle-import") (part "JP1E"))
    )
    (comp (ref "A191")
      (value "JP1E")
      (footprint "eagle-import:JP1")
      (libsource (lib "eagle-import") (part "JP1E"))
    )
    (comp (ref "A192")
      (value "JP1E")
      (footprint "eagle-import:JP1")
      (libsource (lib "eagle-import") (part "JP1E"))
    )
    (comp (ref "A193")
      (value "JP1E")
      (footprint "eagle-import:JP1")
      (libsource (lib "eagle-import") (part "JP1E"))
    )
    (comp (ref "A194")
      (value "JP1E")
      (footprint "eagle-import:JP1")
      (libsource (lib "eagle-import") (part "JP1E"))
    )
    (comp (ref "A195")
      (value "JP1E")
      (footprint "eagle-import:JP1")
      (libsource (lib "eagle-import") (part "JP1E"))
    )
    (comp (ref "A196")
      (value "JP1E")
      (footprint "eagle-import:JP1")
      (libsource (lib "eagle-import") (part "JP1E"))
    )
    (comp (ref "A197")
      (value "JP1E")
      (footprint "eagle-import:JP1")
      (libsource (lib "eagle-import") (part "JP1E"))
    )
    (comp (ref "A198")
      (value "JP1E")
      (footprint "eagle-import:JP1")
      (libsource (lib "eagle-import") (part "JP1E"))
    )
    (comp (ref "A199")
      (value "JP1E")
      (footprint "eagle-import:JP1")
      (libsource (lib "eagle-import") (part "JP1E"))
    )
    (comp (ref "A200")
      (value "JP1E")
      (footprint "eagle-import:JP1")
      (libsource (lib "eagle-import") (part "JP1E"))
    )
    (comp (ref "A201")
      (value "JP1E")
      (footprint "eagle-import:JP1")
      (libsource (lib "eagle-import") (part "JP1E"))
    )
    (comp (ref "A202")
      (value "JP1E")
      (footprint "eagle-import:JP1")
      (libsource (lib "eagle-import") (part "JP1E"))
    )
    (comp (ref "A203")
      (value "JP1E")
      (footprint "eagle-import:JP1")
      (libsource (lib "eagle-import") (part "JP1E"))
    )
    (comp (ref "A204")
      (value "JP1E")
      (footprint "eagle-import:JP1")
      (libsource (lib "eagle-import") (part "JP1E"))
    )
    (comp (ref "A205")
      (value "JP1E")
      (footprint "eagle-import:JP1")
      (libsource (lib "eagle-import") (part "JP1E"))
    )
    (comp (ref "A206")
      (value "JP1E")
      (footprint "eagle-import:JP1")
      (libsource (lib "eagle-import") (part "JP1E"))
    )
    (comp (ref "A207")
      (value "JP1E")
      (footprint "eagle-import:JP1")
      (libsource (lib "eagle-import") (part "JP1E"))
    )
    (comp (ref "A208")
      (value "JP1E")
      (footprint "eagle-import:JP1")
      (libsource (lib "eagle-import") (part "JP1E"))
    )
    (comp (ref "A209")
      (value "JP1E")
      (footprint "eagle-import:JP1")
      (libsource (lib "eagle-import") (part "JP1E"))
    )
    (comp (ref "A210")
      (value "JP1E")
      (footprint "eagle-import:JP1")
      (libsource (lib "eagle-import") (part "JP1E"))
    )
    (comp (ref "A211")
      (value "JP1E")
      (footprint "eagle-import:JP1")
      (libsource (lib "eagle-import") (part "JP1E"))
    )
    (comp (ref "A212")
      (value "JP1E")
      (footprint "eagle-import:JP1")
      (libsource (lib "eagle-import") (part "JP1E"))
    )
    (comp (ref "A213")
      (value "JP1E")
      (footprint "eagle-import:JP1")
      (libsource (lib "eagle-import") (part "JP1E"))
    )
    (comp (ref "A214")
      (value "JP1E")
      (footprint "eagle-import:JP1")
      (libsource (lib "eagle-import") (part "JP1E"))
    )
    (comp (ref "A215")
      (value "JP1E")
      (footprint "eagle-import:JP1")
      (libsource (lib "eagle-import") (part "JP1E"))
    )
    (comp (ref "A216")
      (value "JP1E")
      (footprint "eagle-import:JP1")
      (libsource (lib "eagle-import") (part "JP1E"))
    )
    (comp (ref "A217")
      (value "JP1E")
      (footprint "eagle-import:JP1")
      (libsource (lib "eagle-import") (part "JP1E"))
    )
    (comp (ref "A218")
      (value "JP1E")
      (footprint "eagle-import:JP1")
      (libsource (lib "eagle-import") (part "JP1E"))
    )
    (comp (ref "A219")
      (value "JP1E")
      (footprint "eagle-import:JP1")
      (libsource (lib "eagle-import") (part "JP1E"))
    )
    (comp (ref "A220")
      (value "JP1E")
      (footprint "eagle-import:JP1")
      (libsource (lib "eagle-import") (part "JP1E"))
    )
    (comp (ref "A221")
      (value "JP1E")
      (footprint "eagle-import:JP1")
      (libsource (lib "eagle-import") (part "JP1E"))
    )
    (comp (ref "A222")
      (value "JP1E")
      (footprint "eagle-import:JP1")
      (libsource (lib "eagle-import") (part "JP1E"))
    )
    (comp (ref "A223")
      (value "JP1E")
      (footprint "eagle-import:JP1")
      (libsource (lib "eagle-import") (part "JP1E"))
    )
    (comp (ref "A224")
      (value "JP1E")
      (footprint "eagle-import:JP1")
      (libsource (lib "eagle-import") (part "JP1E"))
    )
    (comp (ref "A225")
      (value "JP1E")
      (footprint "eagle-import:JP1")
      (libsource (lib "eagle-import") (part "JP1E"))
    )
    (comp (ref "A226")
      (value "JP1E")
      (footprint "eagle-import:JP1")
      (libsource (lib "eagle-import") (part "JP1E"))
    )
    (comp (ref "A227")
      (value "JP1E")
      (footprint "eagle-import:JP1")
      (libsource (lib "eagle-import") (part "JP1E"))
    )
    (comp (ref "A228")
      (value "JP1E")
      (footprint "eagle-import:JP1")
      (libsource (lib "eagle-import") (part "JP1E"))
    )
    (comp (ref "A229")
      (value "JP1E")
      (footprint "eagle-import:JP1")
      (libsource (lib "eagle-import") (part "JP1E"))
    )
    (comp (ref "A230")
      (value "JP1E")
      (footprint "eagle-import:JP1")
      (libsource (lib "eagle-import") (part "JP1E"))
    )
    (comp (ref "A231")
      (value "JP1E")
      (footprint "eagle-import:JP1")
      (libsource (lib "eagle-import") (part "JP1E"))
    )
    (comp (ref "A232")
      (value "JP1E")
      (footprint "eagle-import:JP1")
      (libsource (lib "eagle-import") (part "JP1E"))
    )
    (comp (ref "A233")
      (value "JP1E")
      (footprint "eagle-import:JP1")
      (libsource (lib "eagle-import") (part "JP1E"))
    )
    (comp (ref "A234")
      (value "JP1E")
      (footprint "eagle-import:JP1")
      (libsource (lib "eagle-import") (part "JP1E"))
    )
    (comp (ref "A235")
      (value "JP1E")
      (footprint "eagle-import:JP1")
      (libsource (lib "eagle-import") (part "JP1E"))
    )
    (comp (ref "A236")
      (value "JP1E")
      (footprint "eagle-import:JP1")
      (libsource (lib "eagle-import") (part "JP1E"))
    )
    (comp (ref "A237")
      (value "JP1E")
      (footprint "eagle-import:JP1")
      (libsource (lib "eagle-import") (part "JP1E"))
    )
    (comp (ref "A238")
      (value "JP1E")
      (footprint "eagle-import:JP1")
      (libsource (lib "eagle-import") (part "JP1E"))
    )
    (comp (ref "A239")
      (value "JP1E")
      (footprint "eagle-import:JP1")
      (libsource (lib "eagle-import") (part "JP1E"))
    )
    (comp (ref "A240")
      (value "JP1E")
      (footprint "eagle-import:JP1")
      (libsource (lib "eagle-import") (part "JP1E"))
    )
    (comp (ref "A241")
      (value "JP1E")
      (footprint "eagle-import:JP1")
      (libsource (lib "eagle-import") (part "JP1E"))
    )
    (comp (ref "A242")
      (value "JP1E")
      (footprint "eagle-import:JP1")
      (libsource (lib "eagle-import") (part "JP1E"))
    )
    (comp (ref "A243")
      (value "JP1E")
      (footprint "eagle-import:JP1")
      (libsource (lib "eagle-import") (part "JP1E"))
    )
    (comp (ref "A244")
      (value "JP1E")
      (footprint "eagle-import:JP1")
      (libsource (lib "eagle-import") (part "JP1E"))
    )
    (comp (ref "A245")
      (value "JP1E")
      (footprint "eagle-import:JP1")
      (libsource (lib "eagle-import") (part "JP1E"))
    )
    (comp (ref "A246")
      (value "JP1E")
      (footprint "eagle-import:JP1")
      (libsource (lib "eagle-import") (part "JP1E"))
    )
    (comp (ref "A247")
      (value "JP1E")
      (footprint "eagle-import:JP1")
      (libsource (lib "eagle-import") (part "JP1E"))
    )
    (comp (ref "A248")
      (value "JP1E")
      (footprint "eagle-import:JP1")
      (libsource (lib "eagle-import") (part "JP1E"))
    )
    (comp (ref "A249")
      (value "JP1E")
      (footprint "eagle-import:JP1")
      (libsource (lib "eagle-import") (part "JP1E"))
    )
    (comp (ref "A250")
      (value "JP1E")
      (footprint "eagle-import:JP1")
      (libsource (lib "eagle-import") (part "JP1E"))
    )
    (comp (ref "A251")
      (value "JP1E")
      (footprint "eagle-import:JP1")
      (libsource (lib "eagle-import") (part "JP1E"))
    )
    (comp (ref "A252")
      (value "JP1E")
      (footprint "eagle-import:JP1")
      (libsource (lib "eagle-import") (part "JP1E"))
    )
    (comp (ref "A253")
      (value "JP1E")
      (footprint "eagle-import:JP1")
      (libsource (lib "eagle-import") (part "JP1E"))
    )
    (comp (ref "A254")
      (value "JP1E")
      (footprint "eagle-import:JP1")
      (libsource (lib "eagle-import") (part "JP1E"))
    )
    (comp (ref "A255")
      (value "JP1E")
      (footprint "eagle-import:JP1")
      (libsource (lib "eagle-import") (part "JP1E"))
    )
    (comp (ref "A256")
      (value "JP1E")
      (footprint "eagle-import:JP1")
      (libsource (lib "eagle-import") (part "JP1E"))
    )
    (comp (ref "A257")
      (value "JP1E")
      (footprint "eagle-import:JP1")
      (libsource (lib "eagle-import") (part "JP1E"))
    )
    (comp (ref "A258")
      (value "JP1E")
      (footprint "eagle-import:JP1")
      (libsource (lib "eagle-import") (part "JP1E"))
    )
    (comp (ref "A259")
      (value "JP1E")
      (footprint "eagle-import:JP1")
      (libsource (lib "eagle-import") (part "JP1E"))
    )
    (comp (ref "A260")
      (value "JP1E")
      (footprint "eagle-import:JP1")
      (libsource (lib "eagle-import") (part "JP1E"))
    )
    (comp (ref "A261")
      (value "JP1E")
      (footprint "eagle-import:JP1")
      (libsource (lib "eagle-import") (part "JP1E"))
    )
    (comp (ref "A262")
      (value "JP1E")
      (footprint "eagle-import:JP1")
      (libsource (lib "eagle-import") (part "JP1E"))
    )
    (comp (ref "A263")
      (value "JP1E")
      (footprint "eagle-import:JP1")
      (libsource (lib "eagle-import") (part "JP1E"))
    )
    (comp (ref "A264")
      (value "JP1E")
      (footprint "eagle-import:JP1")
      (libsource (lib "eagle-import") (part "JP1E"))
    )
    (comp (ref "A265")
      (value "JP1E")
      (footprint "eagle-import:JP1")
      (libsource (lib "eagle-import") (part "JP1E"))
    )
    (comp (ref "A266")
      (value "JP1E")
      (footprint "eagle-import:JP1")
      (libsource (lib "eagle-import") (part "JP1E"))
    )
    (comp (ref "A267")
      (value "JP1E")
      (footprint "eagle-import:JP1")
      (libsource (lib "eagle-import") (part "JP1E"))
    )
    (comp (ref "A268")
      (value "JP1E")
      (footprint "eagle-import:JP1")
      (libsource (lib "eagle-import") (part "JP1E"))
    )
    (comp (ref "A269")
      (value "JP1E")
      (footprint "eagle-import:JP1")
      (libsource (lib "eagle-import") (part "JP1E"))
    )
    (comp (ref "A270")
      (value "JP1E")
      (footprint "eagle-import:JP1")
      (libsource (lib "eagle-import") (part "JP1E"))
    )
    (comp (ref "A271")
      (value "JP1E")
      (footprint "eagle-import:JP1")
      (libsource (lib "eagle-import") (part "JP1E"))
    )
    (comp (ref "A272")
      (value "JP1E")
      (footprint "eagle-import:JP1")
      (libsource (lib "eagle-import") (part "JP1E"))
    )
    (comp (ref "A273")
      (value "JP1E")
      (footprint "eagle-import:JP1")
      (libsource (lib "eagle-import") (part "JP1E"))
    )
    (comp (ref "A274")
      (value "JP1E")
      (footprint "eagle-import:JP1")
      (libsource (lib "eagle-import") (part "JP1E"))
    )
    (comp (ref "A275")
      (value "JP1E")
      (footprint "eagle-import:JP1")
      (libsource (lib "eagle-import") (part "JP1E"))
    )
    (comp (ref "A276")
      (value "JP1E")
      (footprint "eagle-import:JP1")
      (libsource (lib "eagle-import") (part "JP1E"))
    )
    (comp (ref "A277")
      (value "JP1E")
      (footprint "eagle-import:JP1")
      (libsource (lib "eagle-import") (part "JP1E"))
    )
    (comp (ref "A278")
      (value "JP1E")
      (footprint "eagle-import:JP1")
      (libsource (lib "eagle-import") (part "JP1E"))
    )
    (comp (ref "A279")
      (value "JP1E")
      (footprint "eagle-import:JP1")
      (libsource (lib "eagle-import") (part "JP1E"))
    )
    (comp (ref "A280")
      (value "JP1E")
      (footprint "eagle-import:JP1")
      (libsource (lib "eagle-import") (part "JP1E"))
    )
    (comp (ref "A281")
      (value "JP1E")
      (footprint "eagle-import:JP1")
      (libsource (lib "eagle-import") (part "JP1E"))
    )
    (comp (ref "A282")
      (value "JP1E")
      (footprint "eagle-import:JP1")
      (libsource (lib "eagle-import") (part "JP1E"))
    )
    (comp (ref "A283")
      (value "JP1E")
      (footprint "eagle-import:JP1")
      (libsource (lib "eagle-import") (part "JP1E"))
    )
    (comp (ref "A284")
      (value "JP1E")
      (footprint "eagle-import:JP1")
      (libsource (lib "eagle-import") (part "JP1E"))
    )
    (comp (ref "A285")
      (value "JP1E")
      (footprint "eagle-import:JP1")
      (libsource (lib "eagle-import") (part "JP1E"))
    )
    (comp (ref "A286")
      (value "JP1E")
      (footprint "eagle-import:JP1")
      (libsource (lib "eagle-import") (part "JP1E"))
    )
    (comp (ref "A287")
      (value "JP1E")
      (footprint "eagle-import:JP1")
      (libsource (lib "eagle-import") (part "JP1E"))
    )
    (comp (ref "A288")
      (value "JP1E")
      (footprint "eagle-import:JP1")
      (libsource (lib "eagle-import") (part "JP1E"))
    )
    (comp (ref "A289")
      (value "JP1E")
      (footprint "eagle-import:JP1")
      (libsource (lib "eagle-import") (part "JP1E"))
    )
    (comp (ref "A290")
      (value "JP1E")
      (footprint "eagle-import:JP1")
      (libsource (lib "eagle-import") (part "JP1E"))
    )
    (comp (ref "A291")
      (value "JP1E")
      (footprint "eagle-import:JP1")
      (libsource (lib "eagle-import") (part "JP1E"))
    )
    (comp (ref "A292")
      (value "JP1E")
      (footprint "eagle-import:JP1")
      (libsource (lib "eagle-import") (part "JP1E"))
    )
    (comp (ref "A293")
      (value "JP1E")
      (footprint "eagle-import:JP1")
      (libsource (lib "eagle-import") (part "JP1E"))
    )
    (comp (ref "A294")
      (value "JP1E")
      (footprint "eagle-import:JP1")
      (libsource (lib "eagle-import") (part "JP1E"))
    )
    (comp (ref "A295")
      (value "JP1E")
      (footprint "eagle-import:JP1")
      (libsource (lib "eagle-import") (part "JP1E"))
    )
    (comp (ref "A296")
      (value "JP1E")
      (footprint "eagle-import:JP1")
      (libsource (lib "eagle-import") (part "JP1E"))
    )
    (comp (ref "A297")
      (value "JP1E")
      (footprint "eagle-import:JP1")
      (libsource (lib "eagle-import") (part "JP1E"))
    )
    (comp (ref "A298")
      (value "JP1E")
      (footprint "eagle-import:JP1")
      (libsource (lib "eagle-import") (part "JP1E"))
    )
    (comp (ref "A299")
      (value "JP1E")
      (footprint "eagle-import:JP1")
      (libsource (lib "eagle-import") (part "JP1E"))
    )
    (comp (ref "A300")
      (value "JP1E")
      (footprint "eagle-import:JP1")
      (libsource (lib "eagle-import") (part "JP1E"))
    )
    (comp (ref "A301")
      (value "JP1E")
      (footprint "eagle-import:JP1")
      (libsource (lib "eagle-import") (part "JP1E"))
    )
    (comp (ref "A302")
      (value "JP1E")
      (footprint "eagle-import:JP1")
      (libsource (lib "eagle-import") (part "JP1E"))
    )
    (comp (ref "A303")
      (value "JP1E")
      (footprint "eagle-import:JP1")
      (libsource (lib "eagle-import") (part "JP1E"))
    )
    (comp (ref "A304")
      (value "JP1E")
      (footprint "eagle-import:JP1")
      (libsource (lib "eagle-import") (part "JP1E"))
    )
    (comp (ref "A305")
      (value "JP1E")
      (footprint "eagle-import:JP1")
      (libsource (lib "eagle-import") (part "JP1E"))
    )
    (comp (ref "A306")
      (value "JP1E")
      (footprint "eagle-import:JP1")
      (libsource (lib "eagle-import") (part "JP1E"))
    )
    (comp (ref "A307")
      (value "JP1E")
      (footprint "eagle-import:JP1")
      (libsource (lib "eagle-import") (part "JP1E"))
    )
    (comp (ref "A308")
      (value "JP1E")
      (footprint "eagle-import:JP1")
      (libsource (lib "eagle-import") (part "JP1E"))
    )
    (comp (ref "A309")
      (value "JP1E")
      (footprint "eagle-import:JP1")
      (libsource (lib "eagle-import") (part "JP1E"))
    )
    (comp (ref "A310")
      (value "JP1E")
      (footprint "eagle-import:JP1")
      (libsource (lib "eagle-import") (part "JP1E"))
    )
    (comp (ref "A311")
      (value "JP1E")
      (footprint "eagle-import:JP1")
      (libsource (lib "eagle-import") (part "JP1E"))
    )
    (comp (ref "A312")
      (value "JP1E")
      (footprint "eagle-import:JP1")
      (libsource (lib "eagle-import") (part "JP1E"))
    )
    (comp (ref "A313")
      (value "JP1E")
      (footprint "eagle-import:JP1")
      (libsource (lib "eagle-import") (part "JP1E"))
    )
    (comp (ref "A314")
      (value "JP1E")
      (footprint "eagle-import:JP1")
      (libsource (lib "eagle-import") (part "JP1E"))
    )
    (comp (ref "A315")
      (value "JP1E")
      (footprint "eagle-import:JP1")
      (libsource (lib "eagle-import") (part "JP1E"))
    )
    (comp (ref "A316")
      (value "JP1E")
      (footprint "eagle-import:JP1")
      (libsource (lib "eagle-import") (part "JP1E"))
    )
    (comp (ref "A317")
      (value "JP1E")
      (footprint "eagle-import:JP1")
      (libsource (lib "eagle-import") (part "JP1E"))
    )
    (comp (ref "A318")
      (value "JP1E")
      (footprint "eagle-import:JP1")
      (libsource (lib "eagle-import") (part "JP1E"))
    )
    (comp (ref "A319")
      (value "JP1E")
      (footprint "eagle-import:JP1")
      (libsource (lib "eagle-import") (part "JP1E"))
    )
    (comp (ref "A320")
      (value "JP1E")
      (footprint "eagle-import:JP1")
      (libsource (lib "eagle-import") (part "JP1E"))
    )
    (comp (ref "A321")
      (value "JP1E")
      (footprint "eagle-import:JP1")
      (libsource (lib "eagle-import") (part "JP1E"))
    )
    (comp (ref "A322")
      (value "JP1E")
      (footprint "eagle-import:JP1")
      (libsource (lib "eagle-import") (part "JP1E"))
    )
    (comp (ref "A323")
      (value "JP1E")
      (footprint "eagle-import:JP1")
      (libsource (lib "eagle-import") (part "JP1E"))
    )
    (comp (ref "A324")
      (value "JP1E")
      (footprint "eagle-import:JP1")
      (libsource (lib "eagle-import") (part "JP1E"))
    )
    (comp (ref "A325")
      (value "JP1E")
      (footprint "eagle-import:JP1")
      (libsource (lib "eagle-import") (part "JP1E"))
    )
    (comp (ref "A326")
      (value "JP1E")
      (footprint "eagle-import:JP1")
      (libsource (lib "eagle-import") (part "JP1E"))
    )
    (comp (ref "A327")
      (value "JP1E")
      (footprint "eagle-import:JP1")
      (libsource (lib "eagle-import") (part "JP1E"))
    )
    (comp (ref "A328")
      (value "JP1E")
      (footprint "eagle-import:JP1")
      (libsource (lib "eagle-import") (part "JP1E"))
    )
    (comp (ref "A329")
      (value "JP1E")
      (footprint "eagle-import:JP1")
      (libsource (lib "eagle-import") (part "JP1E"))
    )
    (comp (ref "A330")
      (value "JP1E")
      (footprint "eagle-import:JP1")
      (libsource (lib "eagle-import") (part "JP1E"))
    )
    (comp (ref "A331")
      (value "JP1E")
      (footprint "eagle-import:JP1")
      (libsource (lib "eagle-import") (part "JP1E"))
    )
    (comp (ref "A332")
      (value "JP1E")
      (footprint "eagle-import:JP1")
      (libsource (lib "eagle-import") (part "JP1E"))
    )
    (comp (ref "A333")
      (value "JP1E")
      (footprint "eagle-import:JP1")
      (libsource (lib "eagle-import") (part "JP1E"))
    )
    (comp (ref "A334")
      (value "JP1E")
      (footprint "eagle-import:JP1")
      (libsource (lib "eagle-import") (part "JP1E"))
    )
    (comp (ref "A335")
      (value "JP1E")
      (footprint "eagle-import:JP1")
      (libsource (lib "eagle-import") (part "JP1E"))
    )
    (comp (ref "A336")
      (value "JP1E")
      (footprint "eagle-import:JP1")
      (libsource (lib "eagle-import") (part "JP1E"))
    )
    (comp (ref "A337")
      (value "JP1E")
      (footprint "eagle-import:JP1")
      (libsource (lib "eagle-import") (part "JP1E"))
    )
    (comp (ref "A338")
      (value "JP1E")
      (footprint "eagle-import:JP1")
      (libsource (lib "eagle-import") (part "JP1E"))
    )
    (comp (ref "A339")
      (value "JP1E")
      (footprint "eagle-import:JP1")
      (libsource (lib "eagle-import") (part "JP1E"))
    )
    (comp (ref "A340")
      (value "JP1E")
      (footprint "eagle-import:JP1")
      (libsource (lib "eagle-import") (part "JP1E"))
    )
    (comp (ref "A341")
      (value "JP1E")
      (footprint "eagle-import:JP1")
      (libsource (lib "eagle-import") (part "JP1E"))
    )
    (comp (ref "A342")
      (value "JP1E")
      (footprint "eagle-import:JP1")
      (libsource (lib "eagle-import") (part "JP1E"))
    )
    (comp (ref "A343")
      (value "JP1E")
      (footprint "eagle-import:JP1")
      (libsource (lib "eagle-import") (part "JP1E"))
    )
    (comp (ref "A344")
      (value "JP1E")
      (footprint "eagle-import:JP1")
      (libsource (lib "eagle-import") (part "JP1E"))
    )
    (comp (ref "A345")
      (value "JP1E")
      (footprint "eagle-import:JP1")
      (libsource (lib "eagle-import") (part "JP1E"))
    )
    (comp (ref "A346")
      (value "JP1E")
      (footprint "eagle-import:JP1")
      (libsource (lib "eagle-import") (part "JP1E"))
    )
    (comp (ref "A347")
      (value "JP1E")
      (footprint "eagle-import:JP1")
      (libsource (lib "eagle-import") (part "JP1E"))
    )
    (comp (ref "A348")
      (value "JP1E")
      (footprint "eagle-import:JP1")
      (libsource (lib "eagle-import") (part "JP1E"))
    )
    (comp (ref "A349")
      (value "JP1E")
      (footprint "eagle-import:JP1")
      (libsource (lib "eagle-import") (part "JP1E"))
    )
    (comp (ref "A350")
      (value "JP1E")
      (footprint "eagle-import:JP1")
      (libsource (lib "eagle-import") (part "JP1E"))
    )
    (comp (ref "A351")
      (value "JP1E")
      (footprint "eagle-import:JP1")
      (libsource (lib "eagle-import") (part "JP1E"))
    )
    (comp (ref "A352")
      (value "JP1E")
      (footprint "eagle-import:JP1")
      (libsource (lib "eagle-import") (part "JP1E"))
    )
    (comp (ref "A353")
      (value "JP1E")
      (footprint "eagle-import:JP1")
      (libsource (lib "eagle-import") (part "JP1E"))
    )
    (comp (ref "A354")
      (value "JP1E")
      (footprint "eagle-import:JP1")
      (libsource (lib "eagle-import") (part "JP1E"))
    )
    (comp (ref "A355")
      (value "JP1E")
      (footprint "eagle-import:JP1")
      (libsource (lib "eagle-import") (part "JP1E"))
    )
    (comp (ref "A356")
      (value "JP1E")
      (footprint "eagle-import:JP1")
      (libsource (lib "eagle-import") (part "JP1E"))
    )
    (comp (ref "A357")
      (value "JP1E")
      (footprint "eagle-import:JP1")
      (libsource (lib "eagle-import") (part "JP1E"))
    )
    (comp (ref "A358")
      (value "JP1E")
      (footprint "eagle-import:JP1")
      (libsource (lib "eagle-import") (part "JP1E"))
    )
    (comp (ref "A359")
      (value "JP1E")
      (footprint "eagle-import:JP1")
      (libsource (lib "eagle-import") (part "JP1E"))
    )
    (comp (ref "A360")
      (value "JP1E")
      (footprint "eagle-import:JP1")
      (libsource (lib "eagle-import") (part "JP1E"))
    )
    (comp (ref "A361")
      (value "JP1E")
      (footprint "eagle-import:JP1")
      (libsource (lib "eagle-import") (part "JP1E"))
    )
    (comp (ref "A362")
      (value "JP1E")
      (footprint "eagle-import:JP1")
      (libsource (lib "eagle-import") (part "JP1E"))
    )
    (comp (ref "A363")
      (value "JP1E")
      (footprint "eagle-import:JP1")
      (libsource (lib "eagle-import") (part "JP1E"))
    )
    (comp (ref "A364")
      (value "JP1E")
      (footprint "eagle-import:JP1")
      (libsource (lib "eagle-import") (part "JP1E"))
    )
    (comp (ref "A365")
      (value "JP1E")
      (footprint "eagle-import:JP1")
      (libsource (lib "eagle-import") (part "JP1E"))
    )
    (comp (ref "A366")
      (value "JP1E")
      (footprint "eagle-import:JP1")
      (libsource (lib "eagle-import") (part "JP1E"))
    )
    (comp (ref "A367")
      (value "JP1E")
      (footprint "eagle-import:JP1")
      (libsource (lib "eagle-import") (part "JP1E"))
    )
    (comp (ref "A368")
      (value "JP1E")
      (footprint "eagle-import:JP1")
      (libsource (lib "eagle-import") (part "JP1E"))
    )
    (comp (ref "A369")
      (value "JP1E")
      (footprint "eagle-import:JP1")
      (libsource (lib "eagle-import") (part "JP1E"))
    )
    (comp (ref "A370")
      (value "JP1E")
      (footprint "eagle-import:JP1")
      (libsource (lib "eagle-import") (part "JP1E"))
    )
    (comp (ref "A371")
      (value "JP1E")
      (footprint "eagle-import:JP1")
      (libsource (lib "eagle-import") (part "JP1E"))
    )
    (comp (ref "A372")
      (value "JP1E")
      (footprint "eagle-import:JP1")
      (libsource (lib "eagle-import") (part "JP1E"))
    )
    (comp (ref "A373")
      (value "JP1E")
      (footprint "eagle-import:JP1")
      (libsource (lib "eagle-import") (part "JP1E"))
    )
    (comp (ref "A374")
      (value "JP1E")
      (footprint "eagle-import:JP1")
      (libsource (lib "eagle-import") (part "JP1E"))
    )
    (comp (ref "A375")
      (value "JP1E")
      (footprint "eagle-import:JP1")
      (libsource (lib "eagle-import") (part "JP1E"))
    )
    (comp (ref "A376")
      (value "JP1E")
      (footprint "eagle-import:JP1")
      (libsource (lib "eagle-import") (part "JP1E"))
    )
    (comp (ref "A377")
      (value "JP1E")
      (footprint "eagle-import:JP1")
      (libsource (lib "eagle-import") (part "JP1E"))
    )
    (comp (ref "A378")
      (value "JP1E")
      (footprint "eagle-import:JP1")
      (libsource (lib "eagle-import") (part "JP1E"))
    )
    (comp (ref "A379")
      (value "JP1E")
      (footprint "eagle-import:JP1")
      (libsource (lib "eagle-import") (part "JP1E"))
    )
    (comp (ref "A380")
      (value "JP1E")
      (footprint "eagle-import:JP1")
      (libsource (lib "eagle-import") (part "JP1E"))
    )
    (comp (ref "A381")
      (value "JP1E")
      (footprint "eagle-import:JP1")
      (libsource (lib "eagle-import") (part "JP1E"))
    )
    (comp (ref "A382")
      (value "JP1E")
      (footprint "eagle-import:JP1")
      (libsource (lib "eagle-import") (part "JP1E"))
    )
    (comp (ref "A383")
      (value "JP1E")
      (footprint "eagle-import:JP1")
      (libsource (lib "eagle-import") (part "JP1E"))
    )
    (comp (ref "A384")
      (value "JP1E")
      (footprint "eagle-import:JP1")
      (libsource (lib "eagle-import") (part "JP1E"))
    )
    (comp (ref "A385")
      (value "JP1E")
      (footprint "eagle-import:JP1")
      (libsource (lib "eagle-import") (part "JP1E"))
    )
    (comp (ref "A386")
      (value "JP1E")
      (footprint "eagle-import:JP1")
      (libsource (lib "eagle-import") (part "JP1E"))
    )
    (comp (ref "A387")
      (value "JP1E")
      (footprint "eagle-import:JP1")
      (libsource (lib "eagle-import") (part "JP1E"))
    )
    (comp (ref "A388")
      (value "JP1E")
      (footprint "eagle-import:JP1")
      (libsource (lib "eagle-import") (part "JP1E"))
    )
    (comp (ref "A389")
      (value "JP1E")
      (footprint "eagle-import:JP1")
      (libsource (lib "eagle-import") (part "JP1E"))
    )
    (comp (ref "A390")
      (value "JP1E")
      (footprint "eagle-import:JP1")
      (libsource (lib "eagle-import") (part "JP1E"))
    )
    (comp (ref "A391")
      (value "JP1E")
      (footprint "eagle-import:JP1")
      (libsource (lib "eagle-import") (part "JP1E"))
    )
    (comp (ref "A392")
      (value "JP1E")
      (footprint "eagle-import:JP1")
      (libsource (lib "eagle-import") (part "JP1E"))
    )
    (comp (ref "A393")
      (value "JP1E")
      (footprint "eagle-import:JP1")
      (libsource (lib "eagle-import") (part "JP1E"))
    )
    (comp (ref "A394")
      (value "JP1E")
      (footprint "eagle-import:JP1")
      (libsource (lib "eagle-import") (part "JP1E"))
    )
    (comp (ref "A395")
      (value "JP1E")
      (footprint "eagle-import:JP1")
      (libsource (lib "eagle-import") (part "JP1E"))
    )
    (comp (ref "A396")
      (value "JP1E")
      (footprint "eagle-import:JP1")
      (libsource (lib "eagle-import") (part "JP1E"))
    )
    (comp (ref "A397")
      (value "JP1E")
      (footprint "eagle-import:JP1")
      (libsource (lib "eagle-import") (part "JP1E"))
    )
    (comp (ref "A398")
      (value "JP1E")
      (footprint "eagle-import:JP1")
      (libsource (lib "eagle-import") (part "JP1E"))
    )
    (comp (ref "A399")
      (value "JP1E")
      (footprint "eagle-import:JP1")
      (libsource (lib "eagle-import") (part "JP1E"))
    )
    (comp (ref "A400")
      (value "JP1E")
      (footprint "eagle-import:JP1")
      (libsource (lib "eagle-import") (part "JP1E"))
    )
    (comp (ref "A401")
      (value "JP1E")
      (footprint "eagle-import:JP1")
      (libsource (lib "eagle-import") (part "JP1E"))
    )
    (comp (ref "A402")
      (value "JP1E")
      (footprint "eagle-import:JP1")
      (libsource (lib "eagle-import") (part "JP1E"))
    )
    (comp (ref "A403")
      (value "JP1E")
      (footprint "eagle-import:JP1")
      (libsource (lib "eagle-import") (part "JP1E"))
    )
    (comp (ref "A404")
      (value "JP1E")
      (footprint "eagle-import:JP1")
      (libsource (lib "eagle-import") (part "JP1E"))
    )
    (comp (ref "A405")
      (value "JP1E")
      (footprint "eagle-import:JP1")
      (libsource (lib "eagle-import") (part "JP1E"))
    )
    (comp (ref "A406")
      (value "JP1E")
      (footprint "eagle-import:JP1")
      (libsource (lib "eagle-import") (part "JP1E"))
    )
    (comp (ref "A407")
      (value "JP1E")
      (footprint "eagle-import:JP1")
      (libsource (lib "eagle-import") (part "JP1E"))
    )
    (comp (ref "A408")
      (value "JP1E")
      (footprint "eagle-import:JP1")
      (libsource (lib "eagle-import") (part "JP1E"))
    )
    (comp (ref "A409")
      (value "JP1E")
      (footprint "eagle-import:JP1")
      (libsource (lib "eagle-import") (part "JP1E"))
    )
    (comp (ref "A410")
      (value "JP1E")
      (footprint "eagle-import:JP1")
      (libsource (lib "eagle-import") (part "JP1E"))
    )
    (comp (ref "A411")
      (value "JP1E")
      (footprint "eagle-import:JP1")
      (libsource (lib "eagle-import") (part "JP1E"))
    )
    (comp (ref "A412")
      (value "JP1E")
      (footprint "eagle-import:JP1")
      (libsource (lib "eagle-import") (part "JP1E"))
    )
    (comp (ref "A413")
      (value "JP1E")
      (footprint "eagle-import:JP1")
      (libsource (lib "eagle-import") (part "JP1E"))
    )
    (comp (ref "A414")
      (value "JP1E")
      (footprint "eagle-import:JP1")
      (libsource (lib "eagle-import") (part "JP1E"))
    )
    (comp (ref "A415")
      (value "JP1E")
      (footprint "eagle-import:JP1")
      (libsource (lib "eagle-import") (part "JP1E"))
    )
    (comp (ref "A416")
      (value "JP1E")
      (footprint "eagle-import:JP1")
      (libsource (lib "eagle-import") (part "JP1E"))
    )
    (comp (ref "A417")
      (value "JP1E")
      (footprint "eagle-import:JP1")
      (libsource (lib "eagle-import") (part "JP1E"))
    )
    (comp (ref "A418")
      (value "JP1E")
      (footprint "eagle-import:JP1")
      (libsource (lib "eagle-import") (part "JP1E"))
    )
    (comp (ref "A419")
      (value "JP1E")
      (footprint "eagle-import:JP1")
      (libsource (lib "eagle-import") (part "JP1E"))
    )
    (comp (ref "A420")
      (value "JP1E")
      (footprint "eagle-import:JP1")
      (libsource (lib "eagle-import") (part "JP1E"))
    )
    (comp (ref "A421")
      (value "JP1E")
      (footprint "eagle-import:JP1")
      (libsource (lib "eagle-import") (part "JP1E"))
    )
    (comp (ref "A422")
      (value "JP1E")
      (footprint "eagle-import:JP1")
      (libsource (lib "eagle-import") (part "JP1E"))
    )
    (comp (ref "A423")
      (value "JP1E")
      (footprint "eagle-import:JP1")
      (libsource (lib "eagle-import") (part "JP1E"))
    )
    (comp (ref "A424")
      (value "JP1E")
      (footprint "eagle-import:JP1")
      (libsource (lib "eagle-import") (part "JP1E"))
    )
    (comp (ref "A425")
      (value "JP1E")
      (footprint "eagle-import:JP1")
      (libsource (lib "eagle-import") (part "JP1E"))
    )
    (comp (ref "A426")
      (value "JP1E")
      (footprint "eagle-import:JP1")
      (libsource (lib "eagle-import") (part "JP1E"))
    )
    (comp (ref "A427")
      (value "JP1E")
      (footprint "eagle-import:JP1")
      (libsource (lib "eagle-import") (part "JP1E"))
    )
    (comp (ref "A428")
      (value "JP1E")
      (footprint "eagle-import:JP1")
      (libsource (lib "eagle-import") (part "JP1E"))
    )
    (comp (ref "A429")
      (value "JP1E")
      (footprint "eagle-import:JP1")
      (libsource (lib "eagle-import") (part "JP1E"))
    )
    (comp (ref "A430")
      (value "JP1E")
      (footprint "eagle-import:JP1")
      (libsource (lib "eagle-import") (part "JP1E"))
    )
    (comp (ref "A431")
      (value "JP1E")
      (footprint "eagle-import:JP1")
      (libsource (lib "eagle-import") (part "JP1E"))
    )
    (comp (ref "A432")
      (value "JP1E")
      (footprint "eagle-import:JP1")
      (libsource (lib "eagle-import") (part "JP1E"))
    )
    (comp (ref "A433")
      (value "JP1E")
      (footprint "eagle-import:JP1")
      (libsource (lib "eagle-import") (part "JP1E"))
    )
    (comp (ref "A434")
      (value "JP1E")
      (footprint "eagle-import:JP1")
      (libsource (lib "eagle-import") (part "JP1E"))
    )
    (comp (ref "A435")
      (value "JP1E")
      (footprint "eagle-import:JP1")
      (libsource (lib "eagle-import") (part "JP1E"))
    )
    (comp (ref "A436")
      (value "JP1E")
      (footprint "eagle-import:JP1")
      (libsource (lib "eagle-import") (part "JP1E"))
    )
    (comp (ref "A437")
      (value "JP1E")
      (footprint "eagle-import:JP1")
      (libsource (lib "eagle-import") (part "JP1E"))
    )
    (comp (ref "A438")
      (value "JP1E")
      (footprint "eagle-import:JP1")
      (libsource (lib "eagle-import") (part "JP1E"))
    )
    (comp (ref "A439")
      (value "JP1E")
      (footprint "eagle-import:JP1")
      (libsource (lib "eagle-import") (part "JP1E"))
    )
    (comp (ref "A440")
      (value "JP1E")
      (footprint "eagle-import:JP1")
      (libsource (lib "eagle-import") (part "JP1E"))
    )
    (comp (ref "A441")
      (value "JP1E")
      (footprint "eagle-import:JP1")
      (libsource (lib "eagle-import") (part "JP1E"))
    )
    (comp (ref "A442")
      (value "JP1E")
      (footprint "eagle-import:JP1")
      (libsource (lib "eagle-import") (part "JP1E"))
    )
    (comp (ref "A443")
      (value "JP1E")
      (footprint "eagle-import:JP1")
      (libsource (lib "eagle-import") (part "JP1E"))
    )
    (comp (ref "A444")
      (value "JP1E")
      (footprint "eagle-import:JP1")
      (libsource (lib "eagle-import") (part "JP1E"))
    )
    (comp (ref "A445")
      (value "JP1E")
      (footprint "eagle-import:JP1")
      (libsource (lib "eagle-import") (part "JP1E"))
    )
    (comp (ref "A446")
      (value "JP1E")
      (footprint "eagle-import:JP1")
      (libsource (lib "eagle-import") (part "JP1E"))
    )
    (comp (ref "A447")
      (value "JP1E")
      (footprint "eagle-import:JP1")
      (libsource (lib "eagle-import") (part "JP1E"))
    )
    (comp (ref "A448")
      (value "JP1E")
      (footprint "eagle-import:JP1")
      (libsource (lib "eagle-import") (part "JP1E"))
    )
    (comp (ref "GND1")
      (value "JP1E")
      (footprint "eagle-import:JP1")
      (libsource (lib "eagle-import") (part "JP1E"))
    )
    (comp (ref "GND2")
      (value "JP1E")
      (footprint "eagle-import:JP1")
      (libsource (lib "eagle-import") (part "JP1E"))
    )
    (comp (ref "GND3")
      (value "JP1E")
      (footprint "eagle-import:JP1")
      (libsource (lib "eagle-import") (part "JP1E"))
    )
    (comp (ref "GND4")
      (value "JP1E")
      (footprint "eagle-import:JP1")
      (libsource (lib "eagle-import") (part "JP1E"))
    )
    (comp (ref "GND5")
      (value "JP1E")
      (footprint "eagle-import:JP1")
      (libsource (lib "eagle-import") (part "JP1E"))
    )
    (comp (ref "GND6")
      (value "JP1E")
      (footprint "eagle-import:JP1")
      (libsource (lib "eagle-import") (part "JP1E"))
    )
    (comp (ref "GND7")
      (value "JP1E")
      (footprint "eagle-import:JP1")
      (libsource (lib "eagle-import") (part "JP1E"))
    )
    (comp (ref "GND8")
      (value "JP1E")
      (footprint "eagle-import:JP1")
      (libsource (lib "eagle-import") (part "JP1E"))
    )
    (comp (ref "GND9")
      (value "JP1E")
      (footprint "eagle-import:JP1")
      (libsource (lib "eagle-import") (part "JP1E"))
    )
    (comp (ref "GND10")
      (value "JP1E")
      (footprint "eagle-import:JP1")
      (libsource (lib "eagle-import") (part "JP1E"))
    )
    (comp (ref "GND11")
      (value "JP1E")
      (footprint "eagle-import:JP1")
      (libsource (lib "eagle-import") (part "JP1E"))
    )
    (comp (ref "GND12")
      (value "JP1E")
      (footprint "eagle-import:JP1")
      (libsource (lib "eagle-import") (part "JP1E"))
    )
    (comp (ref "GND13")
      (value "JP1E")
      (footprint "eagle-import:JP1")
      (libsource (lib "eagle-import") (part "JP1E"))
    )
    (comp (ref "GND14")
      (value "JP1E")
      (footprint "eagle-import:JP1")
      (libsource (lib "eagle-import") (part "JP1E"))
    )
    (comp (ref "GND15")
      (value "JP1E")
      (footprint "eagle-import:JP1")
      (libsource (lib "eagle-import") (part "JP1E"))
    )
    (comp (ref "GND16")
      (value "JP1E")
      (footprint "eagle-import:JP1")
      (libsource (lib "eagle-import") (part "JP1E"))
    )
    (comp (ref "GND17")
      (value "JP1E")
      (footprint "eagle-import:JP1")
      (libsource (lib "eagle-import") (part "JP1E"))
    )
    (comp (ref "GND18")
      (value "JP1E")
      (footprint "eagle-import:JP1")
      (libsource (lib "eagle-import") (part "JP1E"))
    )
    (comp (ref "GND19")
      (value "JP1E")
      (footprint "eagle-import:JP1")
      (libsource (lib "eagle-import") (part "JP1E"))
    )
    (comp (ref "GND20")
      (value "JP1E")
      (footprint "eagle-import:JP1")
      (libsource (lib "eagle-import") (part "JP1E"))
    )
    (comp (ref "GND21")
      (value "JP1E")
      (footprint "eagle-import:JP1")
      (libsource (lib "eagle-import") (part "JP1E"))
    )
    (comp (ref "GND22")
      (value "JP1E")
      (footprint "eagle-import:JP1")
      (libsource (lib "eagle-import") (part "JP1E"))
    )
    (comp (ref "GND23")
      (value "JP1E")
      (footprint "eagle-import:JP1")
      (libsource (lib "eagle-import") (part "JP1E"))
    )
    (comp (ref "GND24")
      (value "JP1E")
      (footprint "eagle-import:JP1")
      (libsource (lib "eagle-import") (part "JP1E"))
    )
    (comp (ref "GND25")
      (value "JP1E")
      (footprint "eagle-import:JP1")
      (libsource (lib "eagle-import") (part "JP1E"))
    )
    (comp (ref "GND26")
      (value "JP1E")
      (footprint "eagle-import:JP1")
      (libsource (lib "eagle-import") (part "JP1E"))
    )
    (comp (ref "GND27")
      (value "JP1E")
      (footprint "eagle-import:JP1")
      (libsource (lib "eagle-import") (part "JP1E"))
    )
    (comp (ref "GND28")
      (value "JP1E")
      (footprint "eagle-import:JP1")
      (libsource (lib "eagle-import") (part "JP1E"))
    )
    (comp (ref "GND29")
      (value "JP1E")
      (footprint "eagle-import:JP1")
      (libsource (lib "eagle-import") (part "JP1E"))
    )
    (comp (ref "GND30")
      (value "JP1E")
      (footprint "eagle-import:JP1")
      (libsource (lib "eagle-import") (part "JP1E"))
    )
    (comp (ref "GND31")
      (value "JP1E")
      (footprint "eagle-import:JP1")
      (libsource (lib "eagle-import") (part "JP1E"))
    )
    (comp (ref "GND32")
      (value "JP1E")
      (footprint "eagle-import:JP1")
      (libsource (lib "eagle-import") (part "JP1E"))
    )
    (comp (ref "GND33")
      (value "JP1E")
      (footprint "eagle-import:JP1")
      (libsource (lib "eagle-import") (part "JP1E"))
    )
    (comp (ref "GND34")
      (value "JP1E")
      (footprint "eagle-import:JP1")
      (libsource (lib "eagle-import") (part "JP1E"))
    )
    (comp (ref "GND35")
      (value "JP1E")
      (footprint "eagle-import:JP1")
      (libsource (lib "eagle-import") (part "JP1E"))
    )
    (comp (ref "GND36")
      (value "JP1E")
      (footprint "eagle-import:JP1")
      (libsource (lib "eagle-import") (part "JP1E"))
    )
    (comp (ref "GND37")
      (value "JP1E")
      (footprint "eagle-import:JP1")
      (libsource (lib "eagle-import") (part "JP1E"))
    )
    (comp (ref "GND38")
      (value "JP1E")
      (footprint "eagle-import:JP1")
      (libsource (lib "eagle-import") (part "JP1E"))
    )
    (comp (ref "GND39")
      (value "JP1E")
      (footprint "eagle-import:JP1")
      (libsource (lib "eagle-import") (part "JP1E"))
    )
    (comp (ref "GND40")
      (value "JP1E")
      (footprint "eagle-import:JP1")
      (libsource (lib "eagle-import") (part "JP1E"))
    )
    (comp (ref "GND41")
      (value "JP1E")
      (footprint "eagle-import:JP1")
      (libsource (lib "eagle-import") (part "JP1E"))
    )
    (comp (ref "GND42")
      (value "JP1E")
      (footprint "eagle-import:JP1")
      (libsource (lib "eagle-import") (part "JP1E"))
    )
    (comp (ref "GND43")
      (value "JP1E")
      (footprint "eagle-import:JP1")
      (libsource (lib "eagle-import") (part "JP1E"))
    )
    (comp (ref "GND44")
      (value "JP1E")
      (footprint "eagle-import:JP1")
      (libsource (lib "eagle-import") (part "JP1E"))
    )
    (comp (ref "IC9")
      (value "DIL16")
      (footprint "eagle-import:DIL16")
      (libsource (lib "eagle-import") (part "DIL16"))
    )
    (comp (ref "IC10")
      (value "DIL16")
      (footprint "eagle-import:DIL16")
      (libsource (lib "eagle-import") (part "DIL16"))
    )
    (comp (ref "IC11")
      (value "DIL16")
      (footprint "eagle-import:DIL16")
      (libsource (lib "eagle-import") (part "DIL16"))
    )
    (comp (ref "IC12")
      (value "DIL16")
      (footprint "eagle-import:DIL16")
      (libsource (lib "eagle-import") (part "DIL16"))
    )
    (comp (ref "IC13")
      (value "DIL16")
      (footprint "eagle-import:DIL16")
      (libsource (lib "eagle-import") (part "DIL16"))
    )
    (comp (ref "IC14")
      (value "DIL16")
      (footprint "eagle-import:DIL16")
      (libsource (lib "eagle-import") (part "DIL16"))
    )
    (comp (ref "IC15")
      (value "DIL16")
      (footprint "eagle-import:DIL16")
      (libsource (lib "eagle-import") (part "DIL16"))
    )
    (comp (ref "IC16")
      (value "DIL16")
      (footprint "eagle-import:DIL16")
      (libsource (lib "eagle-import") (part "DIL16"))
    )
    (comp (ref "IC17")
      (value "DIL16")
      (footprint "eagle-import:DIL16")
      (libsource (lib "eagle-import") (part "DIL16"))
    )
    (comp (ref "IC18")
      (value "DIL16")
      (footprint "eagle-import:DIL16")
      (libsource (lib "eagle-import") (part "DIL16"))
    )
    (comp (ref "IC19")
      (value "DIL16")
      (footprint "eagle-import:DIL16")
      (libsource (lib "eagle-import") (part "DIL16"))
    )
    (comp (ref "IC20")
      (value "DIL16")
      (footprint "eagle-import:DIL16")
      (libsource (lib "eagle-import") (part "DIL16"))
    )
    (comp (ref "IC21")
      (value "DIL16")
      (footprint "eagle-import:DIL16")
      (libsource (lib "eagle-import") (part "DIL16"))
    )
    (comp (ref "IC22")
      (value "DIL16")
      (footprint "eagle-import:DIL16")
      (libsource (lib "eagle-import") (part "DIL16"))
    )
    (comp (ref "IC23")
      (value "DIL16")
      (footprint "eagle-import:DIL16")
      (libsource (lib "eagle-import") (part "DIL16"))
    )
    (comp (ref "IC24")
      (value "DIL16")
      (footprint "eagle-import:DIL16")
      (libsource (lib "eagle-import") (part "DIL16"))
    )
    (comp (ref "IC25")
      (value "DIL16")
      (footprint "eagle-import:DIL16")
      (libsource (lib "eagle-import") (part "DIL16"))
    )
    (comp (ref "IC26")
      (value "DIL16")
      (footprint "eagle-import:DIL16")
      (libsource (lib "eagle-import") (part "DIL16"))
    )
    (comp (ref "IC27")
      (value "DIL16")
      (footprint "eagle-import:DIL16")
      (libsource (lib "eagle-import") (part "DIL16"))
    )
    (comp (ref "IC28")
      (value "DIL16")
      (footprint "eagle-import:DIL16")
      (libsource (lib "eagle-import") (part "DIL16"))
    )
    (comp (ref "IC29")
      (value "DIL16")
      (footprint "eagle-import:DIL16")
      (libsource (lib "eagle-import") (part "DIL16"))
    )
    (comp (ref "IC30")
      (value "DIL16")
      (footprint "eagle-import:DIL16")
      (libsource (lib "eagle-import") (part "DIL16"))
    )
    (comp (ref "IC31")
      (value "DIL16")
      (footprint "eagle-import:DIL16")
      (libsource (lib "eagle-import") (part "DIL16"))
    )
    (comp (ref "IC32")
      (value "DIL16")
      (footprint "eagle-import:DIL16")
      (libsource (lib "eagle-import") (part "DIL16"))
    )
    (comp (ref "IC33")
      (value "DIL16")
      (footprint "eagle-import:DIL16")
      (libsource (lib "eagle-import") (part "DIL16"))
    )
    (comp (ref "IC34")
      (value "DIL16")
      (footprint "eagle-import:DIL16")
      (libsource (lib "eagle-import") (part "DIL16"))
    )
    (comp (ref "IC35")
      (value "DIL16")
      (footprint "eagle-import:DIL16")
      (libsource (lib "eagle-import") (part "DIL16"))
    )
    (comp (ref "IC36")
      (value "DIL16")
      (footprint "eagle-import:DIL16")
      (libsource (lib "eagle-import") (part "DIL16"))
    )
    (comp (ref "VCC1")
      (value "JP1E")
      (footprint "eagle-import:JP1")
      (libsource (lib "eagle-import") (part "JP1E"))
    )
    (comp (ref "VCC2")
      (value "JP1E")
      (footprint "eagle-import:JP1")
      (libsource (lib "eagle-import") (part "JP1E"))
    )
    (comp (ref "VCC3")
      (value "JP1E")
      (footprint "eagle-import:JP1")
      (libsource (lib "eagle-import") (part "JP1E"))
    )
    (comp (ref "VCC4")
      (value "JP1E")
      (footprint "eagle-import:JP1")
      (libsource (lib "eagle-import") (part "JP1E"))
    )
    (comp (ref "VCC5")
      (value "JP1E")
      (footprint "eagle-import:JP1")
      (libsource (lib "eagle-import") (part "JP1E"))
    )
    (comp (ref "VCC6")
      (value "JP1E")
      (footprint "eagle-import:JP1")
      (libsource (lib "eagle-import") (part "JP1E"))
    )
    (comp (ref "VCC7")
      (value "JP1E")
      (footprint "eagle-import:JP1")
      (libsource (lib "eagle-import") (part "JP1E"))
    )
    (comp (ref "VCC8")
      (value "JP1E")
      (footprint "eagle-import:JP1")
      (libsource (lib "eagle-import") (part "JP1E"))
    )
    (comp (ref "VCC9")
      (value "JP1E")
      (footprint "eagle-import:JP1")
      (libsource (lib "eagle-import") (part "JP1E"))
    )
    (comp (ref "VCC10")
      (value "JP1E")
      (footprint "eagle-import:JP1")
      (libsource (lib "eagle-import") (part "JP1E"))
    )
    (comp (ref "VCC11")
      (value "JP1E")
      (footprint "eagle-import:JP1")
      (libsource (lib "eagle-import") (part "JP1E"))
    )
    (comp (ref "VCC12")
      (value "JP1E")
      (footprint "eagle-import:JP1")
      (libsource (lib "eagle-import") (part "JP1E"))
    )
    (comp (ref "VCC13")
      (value "JP1E")
      (footprint "eagle-import:JP1")
      (libsource (lib "eagle-import") (part "JP1E"))
    )
    (comp (ref "VCC14")
      (value "JP1E")
      (footprint "eagle-import:JP1")
      (libsource (lib "eagle-import") (part "JP1E"))
    )
    (comp (ref "VCC15")
      (value "JP1E")
      (footprint "eagle-import:JP1")
      (libsource (lib "eagle-import") (part "JP1E"))
    )
    (comp (ref "VCC16")
      (value "JP1E")
      (footprint "eagle-import:JP1")
      (libsource (lib "eagle-import") (part "JP1E"))
    )
    (comp (ref "VCC17")
      (value "JP1E")
      (footprint "eagle-import:JP1")
      (libsource (lib "eagle-import") (part "JP1E"))
    )
    (comp (ref "VCC18")
      (value "JP1E")
      (footprint "eagle-import:JP1")
      (libsource (lib "eagle-import") (part "JP1E"))
    )
    (comp (ref "VCC19")
      (value "JP1E")
      (footprint "eagle-import:JP1")
      (libsource (lib "eagle-import") (part "JP1E"))
    )
    (comp (ref "VCC20")
      (value "JP1E")
      (footprint "eagle-import:JP1")
      (libsource (lib "eagle-import") (part "JP1E"))
    )
    (comp (ref "VCC21")
      (value "JP1E")
      (footprint "eagle-import:JP1")
      (libsource (lib "eagle-import") (part "JP1E"))
    )
    (comp (ref "VCC22")
      (value "JP1E")
      (footprint "eagle-import:JP1")
      (libsource (lib "eagle-import") (part "JP1E"))
    )
    (comp (ref "VCC23")
      (value "JP1E")
      (footprint "eagle-import:JP1")
      (libsource (lib "eagle-import") (part "JP1E"))
    )
    (comp (ref "VCC24")
      (value "JP1E")
      (footprint "eagle-import:JP1")
      (libsource (lib "eagle-import") (part "JP1E"))
    )
    (comp (ref "VCC25")
      (value "JP1E")
      (footprint "eagle-import:JP1")
      (libsource (lib "eagle-import") (part "JP1E"))
    )
    (comp (ref "VCC26")
      (value "JP1E")
      (footprint "eagle-import:JP1")
      (libsource (lib "eagle-import") (part "JP1E"))
    )
    (comp (ref "VCC27")
      (value "JP1E")
      (footprint "eagle-import:JP1")
      (libsource (lib "eagle-import") (part "JP1E"))
    )
    (comp (ref "VCC28")
      (value "JP1E")
      (footprint "eagle-import:JP1")
      (libsource (lib "eagle-import") (part "JP1E"))
    )
    (comp (ref "VCC29")
      (value "JP1E")
      (footprint "eagle-import:JP1")
      (libsource (lib "eagle-import") (part "JP1E"))
    )
    (comp (ref "VCC30")
      (value "JP1E")
      (footprint "eagle-import:JP1")
      (libsource (lib "eagle-import") (part "JP1E"))
    )
    (comp (ref "VCC31")
      (value "JP1E")
      (footprint "eagle-import:JP1")
      (libsource (lib "eagle-import") (part "JP1E"))
    )
    (comp (ref "VCC32")
      (value "JP1E")
      (footprint "eagle-import:JP1")
      (libsource (lib "eagle-import") (part "JP1E"))
    )
    (comp (ref "VCC33")
      (value "JP1E")
      (footprint "eagle-import:JP1")
      (libsource (lib "eagle-import") (part "JP1E"))
    )
    (comp (ref "VCC34")
      (value "JP1E")
      (footprint "eagle-import:JP1")
      (libsource (lib "eagle-import") (part "JP1E"))
    )
    (comp (ref "VCC35")
      (value "JP1E")
      (footprint "eagle-import:JP1")
      (libsource (lib "eagle-import") (part "JP1E"))
    )
    (comp (ref "VCC36")
      (value "JP1E")
      (footprint "eagle-import:JP1")
      (libsource (lib "eagle-import") (part "JP1E"))
    )
    (comp (ref "VCC37")
      (value "JP1E")
      (footprint "eagle-import:JP1")
      (libsource (lib "eagle-import") (part "JP1E"))
    )
    (comp (ref "VCC38")
      (value "JP1E")
      (footprint "eagle-import:JP1")
      (libsource (lib "eagle-import") (part "JP1E"))
    )
    (comp (ref "VCC39")
      (value "JP1E")
      (footprint "eagle-import:JP1")
      (libsource (lib "eagle-import") (part "JP1E"))
    )
    (comp (ref "VCC40")
      (value "JP1E")
      (footprint "eagle-import:JP1")
      (libsource (lib "eagle-import") (part "JP1E"))
    )
    (comp (ref "VCC41")
      (value "JP1E")
      (footprint "eagle-import:JP1")
      (libsource (lib "eagle-import") (part "JP1E"))
    )
    (comp (ref "VCC42")
      (value "JP1E")
      (footprint "eagle-import:JP1")
      (libsource (lib "eagle-import") (part "JP1E"))
    )
    (comp (ref "VCC43")
      (value "JP1E")
      (footprint "eagle-import:JP1")
      (libsource (lib "eagle-import") (part "JP1E"))
    )
    (comp (ref "VCC44")
      (value "JP1E")
      (footprint "eagle-import:JP1")
      (libsource (lib "eagle-import") (part "JP1E"))
    )
    (comp (ref "SV1")
      (value "MA05-2")
      (footprint "eagle-import:MA05-2")
      (libsource (lib "eagle-import") (part "MA05-2"))
    )
    (comp (ref "SV2")
      (value "MA05-2")
      (footprint "eagle-import:MA05-2")
      (libsource (lib "eagle-import") (part "MA05-2"))
    )
    (comp (ref "SV3")
      (value "MA20-1")
      (footprint "eagle-import:MA20-1")
      (libsource (lib "eagle-import") (part "MA20-1"))
    )
    (comp (ref "SV4")
      (value "MA20-1")
      (footprint "eagle-import:MA20-1")
      (libsource (lib "eagle-import") (part "MA20-1"))
    )
    (comp (ref "SV5")
      (value "MA20-1")
      (footprint "eagle-import:MA20-1")
      (libsource (lib "eagle-import") (part "MA20-1"))
    )
    (comp (ref "SV6")
      (value "MA20-1")
      (footprint "eagle-import:MA20-1")
      (libsource (lib "eagle-import") (part "MA20-1"))
    )
    (comp (ref "SV7")
      (value "MA05-2")
      (footprint "eagle-import:MA05-2")
      (libsource (lib "eagle-import") (part "MA05-2"))
    )
    (comp (ref "SV8")
      (value "MA05-2")
      (footprint "eagle-import:MA05-2")
      (libsource (lib "eagle-import") (part "MA05-2"))
    )
    (comp (ref "SV9")
      (value "MA08-1")
      (footprint "eagle-import:MA08-1")
      (libsource (lib "eagle-import") (part "MA08-1"))
    )
    (comp (ref "SV10")
      (value "MA08-1")
      (footprint "eagle-import:MA08-1")
      (libsource (lib "eagle-import") (part "MA08-1"))
    )
    (comp (ref "SV11")
      (value "MA10-1")
      (footprint "eagle-import:MA10-1")
      (libsource (lib "eagle-import") (part "MA10-1"))
    )
    (comp (ref "SV12")
      (value "MA10-1")
      (footprint "eagle-import:MA10-1")
      (libsource (lib "eagle-import") (part "MA10-1"))
    )
    (comp (ref "SV13")
      (value "MA05-2")
      (footprint "eagle-import:MA05-2")
      (libsource (lib "eagle-import") (part "MA05-2"))
    )
    (comp (ref "SV14")
      (value "MA05-2")
      (footprint "eagle-import:MA05-2")
      (libsource (lib "eagle-import") (part "MA05-2"))
    )
    (comp (ref "SV15")
      (value "MA05-2")
      (footprint "eagle-import:MA05-2")
      (libsource (lib "eagle-import") (part "MA05-2"))
    )
    (comp (ref "SV16")
      (value "MA05-2")
      (footprint "eagle-import:MA05-2")
      (libsource (lib "eagle-import") (part "MA05-2"))
    )
    (comp (ref "SV17")
      (value "MA05-2")
      (footprint "eagle-import:MA05-2")
      (libsource (lib "eagle-import") (part "MA05-2"))
    )
    (comp (ref "SV18")
      (value "MA05-2")
      (footprint "eagle-import:MA05-2")
      (libsource (lib "eagle-import") (part "MA05-2"))
    )
    (comp (ref "SV19")
      (value "MA05-2")
      (footprint "eagle-import:MA05-2")
      (libsource (lib "eagle-import") (part "MA05-2"))
    )
    (comp (ref "SV20")
      (value "MA05-2")
      (footprint "eagle-import:MA05-2")
      (libsource (lib "eagle-import") (part "MA05-2"))
    )
    (comp (ref "SV21")
      (value "MA05-2")
      (footprint "eagle-import:MA05-2")
      (libsource (lib "eagle-import") (part "MA05-2"))
    )
    (comp (ref "SV22")
      (value "MA05-2")
      (footprint "eagle-import:MA05-2")
      (libsource (lib "eagle-import") (part "MA05-2"))
    )
    (comp (ref "SV23")
      (value "MA05-2")
      (footprint "eagle-import:MA05-2")
      (libsource (lib "eagle-import") (part "MA05-2"))
    )
    (comp (ref "SV24")
      (value "MA05-2")
      (footprint "eagle-import:MA05-2")
      (libsource (lib "eagle-import") (part "MA05-2"))
    )
    (comp (ref "SV25")
      (value "MA05-2")
      (footprint "eagle-import:MA05-2")
      (libsource (lib "eagle-import") (part "MA05-2"))
    )
    (comp (ref "SV26")
      (value "MA05-2")
      (footprint "eagle-import:MA05-2")
      (libsource (lib "eagle-import") (part "MA05-2"))
    )
    (comp (ref "SV27")
      (value "MA05-2")
      (footprint "eagle-import:MA05-2")
      (libsource (lib "eagle-import") (part "MA05-2"))
    )
    (comp (ref "SV28")
      (value "MA05-2")
      (footprint "eagle-import:MA05-2")
      (libsource (lib "eagle-import") (part "MA05-2"))
    )
    (comp (ref "SV29")
      (value "MA05-2")
      (footprint "eagle-import:MA05-2")
      (libsource (lib "eagle-import") (part "MA05-2"))
    )
    (comp (ref "SV30")
      (value "MA05-2")
      (footprint "eagle-import:MA05-2")
      (libsource (lib "eagle-import") (part "MA05-2"))
    )
    (comp (ref "SV31")
      (value "MA05-2")
      (footprint "eagle-import:MA05-2")
      (libsource (lib "eagle-import") (part "MA05-2"))
    )
    (comp (ref "SV32")
      (value "MA05-2")
      (footprint "eagle-import:MA05-2")
      (libsource (lib "eagle-import") (part "MA05-2"))
    )
    (comp (ref "SV33")
      (value "MA05-2")
      (footprint "eagle-import:MA05-2")
      (libsource (lib "eagle-import") (part "MA05-2"))
    )
    (comp (ref "SV34")
      (value "MA05-2")
      (footprint "eagle-import:MA05-2")
      (libsource (lib "eagle-import") (part "MA05-2"))
    )
    (comp (ref "SV35")
      (value "MA05-2")
      (footprint "eagle-import:MA05-2")
      (libsource (lib "eagle-import") (part "MA05-2"))
    )
    (comp (ref "SV36")
      (value "MA05-2")
      (footprint "eagle-import:MA05-2")
      (libsource (lib "eagle-import") (part "MA05-2"))
    )
    (comp (ref "SV37")
      (value "MA05-2")
      (footprint "eagle-import:MA05-2")
      (libsource (lib "eagle-import") (part "MA05-2"))
    )
    (comp (ref "SV38")
      (value "MA05-2")
      (footprint "eagle-import:MA05-2")
      (libsource (lib "eagle-import") (part "MA05-2"))
    )
    (comp (ref "SV39")
      (value "MA05-2")
      (footprint "eagle-import:MA05-2")
      (libsource (lib "eagle-import") (part "MA05-2"))
    )
    (comp (ref "SV40")
      (value "MA05-2")
      (footprint "eagle-import:MA05-2")
      (libsource (lib "eagle-import") (part "MA05-2"))
    )
    (comp (ref "SV41")
      (value "MA05-2")
      (footprint "eagle-import:MA05-2")
      (libsource (lib "eagle-import") (part "MA05-2"))
    )
    (comp (ref "SV42")
      (value "MA05-2")
      (footprint "eagle-import:MA05-2")
      (libsource (lib "eagle-import") (part "MA05-2"))
    )
    (comp (ref "SV43")
      (value "MA05-2")
      (footprint "eagle-import:MA05-2")
      (libsource (lib "eagle-import") (part "MA05-2"))
    )
    (comp (ref "SV44")
      (value "MA05-2")
      (footprint "eagle-import:MA05-2")
      (libsource (lib "eagle-import") (part "MA05-2"))
    )
    (comp (ref "SV45")
      (value "MA05-2")
      (footprint "eagle-import:MA05-2")
      (libsource (lib "eagle-import") (part "MA05-2"))
    )
    (comp (ref "SV46")
      (value "MA05-2")
      (footprint "eagle-import:MA05-2")
      (libsource (lib "eagle-import") (part "MA05-2"))
    )
    (comp (ref "SV47")
      (value "MA05-2")
      (footprint "eagle-import:MA05-2")
      (libsource (lib "eagle-import") (part "MA05-2"))
    )
    (comp (ref "SV48")
      (value "MA05-2")
      (footprint "eagle-import:MA05-2")
      (libsource (lib "eagle-import") (part "MA05-2"))
    )
    (comp (ref "SV49")
      (value "MA05-2")
      (footprint "eagle-import:MA05-2")
      (libsource (lib "eagle-import") (part "MA05-2"))
    )
    (comp (ref "SV50")
      (value "MA05-2")
      (footprint "eagle-import:MA05-2")
      (libsource (lib "eagle-import") (part "MA05-2"))
    )
    (comp (ref "SV51")
      (value "MA05-2")
      (footprint "eagle-import:MA05-2")
      (libsource (lib "eagle-import") (part "MA05-2"))
    )
    (comp (ref "SV52")
      (value "MA05-2")
      (footprint "eagle-import:MA05-2")
      (libsource (lib "eagle-import") (part "MA05-2"))
    )
    (comp (ref "SV53")
      (value "MA05-2")
      (footprint "eagle-import:MA05-2")
      (libsource (lib "eagle-import") (part "MA05-2"))
    )
    (comp (ref "SV54")
      (value "MA05-2")
      (footprint "eagle-import:MA05-2")
      (libsource (lib "eagle-import") (part "MA05-2"))
    )
    (comp (ref "SV55")
      (value "MA05-2")
      (footprint "eagle-import:MA05-2")
      (libsource (lib "eagle-import") (part "MA05-2"))
    )
    (comp (ref "SV56")
      (value "MA05-2")
      (footprint "eagle-import:MA05-2")
      (libsource (lib "eagle-import") (part "MA05-2"))
    )
    (comp (ref "SV57")
      (value "MA05-2")
      (footprint "eagle-import:MA05-2")
      (libsource (lib "eagle-import") (part "MA05-2"))
    )
    (comp (ref "SV58")
      (value "MA05-2")
      (footprint "eagle-import:MA05-2")
      (libsource (lib "eagle-import") (part "MA05-2"))
    )
    (comp (ref "SV59")
      (value "MA05-2")
      (footprint "eagle-import:MA05-2")
      (libsource (lib "eagle-import") (part "MA05-2"))
    )
    (comp (ref "SV60")
      (value "MA05-2")
      (footprint "eagle-import:MA05-2")
      (libsource (lib "eagle-import") (part "MA05-2"))
    )
    (comp (ref "SV61")
      (value "MA05-2")
      (footprint "eagle-import:MA05-2")
      (libsource (lib "eagle-import") (part "MA05-2"))
    )
    (comp (ref "SV62")
      (value "MA05-2")
      (footprint "eagle-import:MA05-2")
      (libsource (lib "eagle-import") (part "MA05-2"))
    )
    (comp (ref "SV63")
      (value "MA05-2")
      (footprint "eagle-import:MA05-2")
      (libsource (lib "eagle-import") (part "MA05-2"))
    )
    (comp (ref "SV64")
      (value "MA05-2")
      (footprint "eagle-import:MA05-2")
      (libsource (lib "eagle-import") (part "MA05-2"))
    )
    (comp (ref "SV65")
      (value "MA05-2")
      (footprint "eagle-import:MA05-2")
      (libsource (lib "eagle-import") (part "MA05-2"))
    )
    (comp (ref "SV66")
      (value "MA05-2")
      (footprint "eagle-import:MA05-2")
      (libsource (lib "eagle-import") (part "MA05-2"))
    )
    (comp (ref "SV67")
      (value "MA05-2")
      (footprint "eagle-import:MA05-2")
      (libsource (lib "eagle-import") (part "MA05-2"))
    )
    (comp (ref "SV68")
      (value "MA05-2")
      (footprint "eagle-import:MA05-2")
      (libsource (lib "eagle-import") (part "MA05-2"))
    )
    (comp (ref "SV69")
      (value "MA05-2")
      (footprint "eagle-import:MA05-2")
      (libsource (lib "eagle-import") (part "MA05-2"))
    )
    (comp (ref "SV70")
      (value "MA05-2")
      (footprint "eagle-import:MA05-2")
      (libsource (lib "eagle-import") (part "MA05-2"))
    )
    (comp (ref "SV71")
      (value "MA05-2")
      (footprint "eagle-import:MA05-2")
      (libsource (lib "eagle-import") (part "MA05-2"))
    )
    (comp (ref "SV72")
      (value "MA05-2")
      (footprint "eagle-import:MA05-2")
      (libsource (lib "eagle-import") (part "MA05-2"))
    )
    (comp (ref "SV73")
      (value "MA05-2")
      (footprint "eagle-import:MA05-2")
      (libsource (lib "eagle-import") (part "MA05-2"))
    )
    (comp (ref "SV74")
      (value "MA05-2")
      (footprint "eagle-import:MA05-2")
      (libsource (lib "eagle-import") (part "MA05-2"))
    )
    (comp (ref "SV75")
      (value "MA05-2")
      (footprint "eagle-import:MA05-2")
      (libsource (lib "eagle-import") (part "MA05-2"))
    )
    (comp (ref "SV76")
      (value "MA05-2")
      (footprint "eagle-import:MA05-2")
      (libsource (lib "eagle-import") (part "MA05-2"))
    )
    (comp (ref "SV77")
      (value "MA05-2")
      (footprint "eagle-import:MA05-2")
      (libsource (lib "eagle-import") (part "MA05-2"))
    )
    (comp (ref "SV78")
      (value "MA05-2")
      (footprint "eagle-import:MA05-2")
      (libsource (lib "eagle-import") (part "MA05-2"))
    )
    (comp (ref "SV79")
      (value "MA05-2")
      (footprint "eagle-import:MA05-2")
      (libsource (lib "eagle-import") (part "MA05-2"))
    )
    (comp (ref "SV80")
      (value "MA05-2")
      (footprint "eagle-import:MA05-2")
      (libsource (lib "eagle-import") (part "MA05-2"))
    )
    (comp (ref "SV81")
      (value "MA05-2")
      (footprint "eagle-import:MA05-2")
      (libsource (lib "eagle-import") (part "MA05-2"))
    )
    (comp (ref "SV82")
      (value "MA05-2")
      (footprint "eagle-import:MA05-2")
      (libsource (lib "eagle-import") (part "MA05-2"))
    )
    (comp (ref "SV83")
      (value "MA05-2")
      (footprint "eagle-import:MA05-2")
      (libsource (lib "eagle-import") (part "MA05-2"))
    )
    (comp (ref "SV84")
      (value "MA05-2")
      (footprint "eagle-import:MA05-2")
      (libsource (lib "eagle-import") (part "MA05-2"))
    )
    (comp (ref "SV85")
      (value "MA05-2")
      (footprint "eagle-import:MA05-2")
      (libsource (lib "eagle-import") (part "MA05-2"))
    )
    (comp (ref "SV86")
      (value "MA05-2")
      (footprint "eagle-import:MA05-2")
      (libsource (lib "eagle-import") (part "MA05-2"))
    )
    (comp (ref "SV87")
      (value "MA05-2")
      (footprint "eagle-import:MA05-2")
      (libsource (lib "eagle-import") (part "MA05-2"))
    )
    (comp (ref "SV88")
      (value "MA05-2")
      (footprint "eagle-import:MA05-2")
      (libsource (lib "eagle-import") (part "MA05-2"))
    )
    (comp (ref "SV89")
      (value "MA05-2")
      (footprint "eagle-import:MA05-2")
      (libsource (lib "eagle-import") (part "MA05-2"))
    )
    (comp (ref "SV90")
      (value "MA05-2")
      (footprint "eagle-import:MA05-2")
      (libsource (lib "eagle-import") (part "MA05-2"))
    )
    (comp (ref "SV91")
      (value "MA05-2")
      (footprint "eagle-import:MA05-2")
      (libsource (lib "eagle-import") (part "MA05-2"))
    )
    (comp (ref "SV92")
      (value "MA05-2")
      (footprint "eagle-import:MA05-2")
      (libsource (lib "eagle-import") (part "MA05-2"))
    )
    (comp (ref "SV93")
      (value "MA05-2")
      (footprint "eagle-import:MA05-2")
      (libsource (lib "eagle-import") (part "MA05-2"))
    )
    (comp (ref "SV94")
      (value "MA05-2")
      (footprint "eagle-import:MA05-2")
      (libsource (lib "eagle-import") (part "MA05-2"))
    )
    (comp (ref "SV95")
      (value "MA05-2")
      (footprint "eagle-import:MA05-2")
      (libsource (lib "eagle-import") (part "MA05-2"))
    )
    (comp (ref "SV96")
      (value "MA05-2")
      (footprint "eagle-import:MA05-2")
      (libsource (lib "eagle-import") (part "MA05-2"))
    )
    (comp (ref "SV97")
      (value "MA05-2")
      (footprint "eagle-import:MA05-2")
      (libsource (lib "eagle-import") (part "MA05-2"))
    )
    (comp (ref "SV98")
      (value "MA05-2")
      (footprint "eagle-import:MA05-2")
      (libsource (lib "eagle-import") (part "MA05-2"))
    )
    (comp (ref "SV99")
      (value "MA05-2")
      (footprint "eagle-import:MA05-2")
      (libsource (lib "eagle-import") (part "MA05-2"))
    )
    (comp (ref "SV100")
      (value "MA05-2")
      (footprint "eagle-import:MA05-2")
      (libsource (lib "eagle-import") (part "MA05-2"))
    )
    (comp (ref "SV101")
      (value "MA05-2")
      (footprint "eagle-import:MA05-2")
      (libsource (lib "eagle-import") (part "MA05-2"))
    )
    (comp (ref "SV102")
      (value "MA05-2")
      (footprint "eagle-import:MA05-2")
      (libsource (lib "eagle-import") (part "MA05-2"))
    )
    (comp (ref "SV103")
      (value "MA05-2")
      (footprint "eagle-import:MA05-2")
      (libsource (lib "eagle-import") (part "MA05-2"))
    )
    (comp (ref "SV104")
      (value "MA05-2")
      (footprint "eagle-import:MA05-2")
      (libsource (lib "eagle-import") (part "MA05-2"))
    )
    (comp (ref "SV105")
      (value "MA05-2")
      (footprint "eagle-import:MA05-2")
      (libsource (lib "eagle-import") (part "MA05-2"))
    )
    (comp (ref "SV106")
      (value "MA05-2")
      (footprint "eagle-import:MA05-2")
      (libsource (lib "eagle-import") (part "MA05-2"))
    )
    (comp (ref "SV107")
      (value "MA05-2")
      (footprint "eagle-import:MA05-2")
      (libsource (lib "eagle-import") (part "MA05-2"))
    )
    (comp (ref "SV108")
      (value "MA05-2")
      (footprint "eagle-import:MA05-2")
      (libsource (lib "eagle-import") (part "MA05-2"))
    )
    (comp (ref "SV109")
      (value "MA05-2")
      (footprint "eagle-import:MA05-2")
      (libsource (lib "eagle-import") (part "MA05-2"))
    )
    (comp (ref "SV110")
      (value "MA05-2")
      (footprint "eagle-import:MA05-2")
      (libsource (lib "eagle-import") (part "MA05-2"))
    )
    (comp (ref "SV111")
      (value "MA05-2")
      (footprint "eagle-import:MA05-2")
      (libsource (lib "eagle-import") (part "MA05-2"))
    )
    (comp (ref "SV112")
      (value "MA05-2")
      (footprint "eagle-import:MA05-2")
      (libsource (lib "eagle-import") (part "MA05-2"))
    )
    (comp (ref "SV113")
      (value "MA05-2")
      (footprint "eagle-import:MA05-2")
      (libsource (lib "eagle-import") (part "MA05-2"))
    )
    (comp (ref "SV114")
      (value "MA05-2")
      (footprint "eagle-import:MA05-2")
      (libsource (lib "eagle-import") (part "MA05-2"))
    )
    (comp (ref "SV115")
      (value "MA05-2")
      (footprint "eagle-import:MA05-2")
      (libsource (lib "eagle-import") (part "MA05-2"))
    )
    (comp (ref "SV116")
      (value "MA05-2")
      (footprint "eagle-import:MA05-2")
      (libsource (lib "eagle-import") (part "MA05-2"))
    )
    (comp (ref "SV117")
      (value "MA05-2")
      (footprint "eagle-import:MA05-2")
      (libsource (lib "eagle-import") (part "MA05-2"))
    )
    (comp (ref "SV118")
      (value "MA05-2")
      (footprint "eagle-import:MA05-2")
      (libsource (lib "eagle-import") (part "MA05-2"))
    )
    (comp (ref "SV119")
      (value "MA05-2")
      (footprint "eagle-import:MA05-2")
      (libsource (lib "eagle-import") (part "MA05-2"))
    )
    (comp (ref "SV120")
      (value "MA05-2")
      (footprint "eagle-import:MA05-2")
      (libsource (lib "eagle-import") (part "MA05-2"))
    )
    (comp (ref "SV121")
      (value "MA05-2")
      (footprint "eagle-import:MA05-2")
      (libsource (lib "eagle-import") (part "MA05-2"))
    )
    (comp (ref "SV122")
      (value "MA05-2")
      (footprint "eagle-import:MA05-2")
      (libsource (lib "eagle-import") (part "MA05-2"))
    )
    (comp (ref "SV123")
      (value "MA05-2")
      (footprint "eagle-import:MA05-2")
      (libsource (lib "eagle-import") (part "MA05-2"))
    )
    (comp (ref "SV124")
      (value "MA05-2")
      (footprint "eagle-import:MA05-2")
      (libsource (lib "eagle-import") (part "MA05-2"))
    )
    (comp (ref "SV125")
      (value "MA20-1")
      (footprint "eagle-import:MA20-1")
      (libsource (lib "eagle-import") (part "MA20-1"))
    )
    (comp (ref "SV126")
      (value "MA05-2")
      (footprint "eagle-import:MA05-2")
      (libsource (lib "eagle-import") (part "MA05-2"))
    )
    (comp (ref "SV127")
      (value "MA08-1")
      (footprint "eagle-import:MA08-1")
      (libsource (lib "eagle-import") (part "MA08-1"))
    )
    (comp (ref "SV128")
      (value "MA05-2")
      (footprint "eagle-import:MA05-2")
      (libsource (lib "eagle-import") (part "MA05-2"))
    )
    (comp (ref "SV129")
      (value "MA10-1")
      (footprint "eagle-import:MA10-1")
      (libsource (lib "eagle-import") (part "MA10-1"))
    )
    (comp (ref "SV130")
      (value "MA05-2")
      (footprint "eagle-import:MA05-2")
      (libsource (lib "eagle-import") (part "MA05-2"))
    )
    (comp (ref "SV131")
      (value "MA20-1")
      (footprint "eagle-import:MA20-1")
      (libsource (lib "eagle-import") (part "MA20-1"))
    )
    (comp (ref "SV132")
      (value "MA05-2")
      (footprint "eagle-import:MA05-2")
      (libsource (lib "eagle-import") (part "MA05-2"))
    )
    (comp (ref "SV133")
      (value "MA05-2")
      (footprint "eagle-import:MA05-2")
      (libsource (lib "eagle-import") (part "MA05-2"))
    )
    (comp (ref "SV134")
      (value "MA05-2")
      (footprint "eagle-import:MA05-2")
      (libsource (lib "eagle-import") (part "MA05-2"))
    )
    (comp (ref "SV135")
      (value "MA05-2")
      (footprint "eagle-import:MA05-2")
      (libsource (lib "eagle-import") (part "MA05-2"))
    )
    (comp (ref "SV136")
      (value "MA05-2")
      (footprint "eagle-import:MA05-2")
      (libsource (lib "eagle-import") (part "MA05-2"))
    )
    (comp (ref "SV137")
      (value "MA05-2")
      (footprint "eagle-import:MA05-2")
      (libsource (lib "eagle-import") (part "MA05-2"))
    )
    (comp (ref "SV138")
      (value "MA05-2")
      (footprint "eagle-import:MA05-2")
      (libsource (lib "eagle-import") (part "MA05-2"))
    )
    (comp (ref "SV139")
      (value "MA05-2")
      (footprint "eagle-import:MA05-2")
      (libsource (lib "eagle-import") (part "MA05-2"))
    )
    (comp (ref "SV140")
      (value "MA05-2")
      (footprint "eagle-import:MA05-2")
      (libsource (lib "eagle-import") (part "MA05-2"))
    )
    (comp (ref "SV141")
      (value "MA05-2")
      (footprint "eagle-import:MA05-2")
      (libsource (lib "eagle-import") (part "MA05-2"))
    )
    (comp (ref "SV142")
      (value "MA05-2")
      (footprint "eagle-import:MA05-2")
      (libsource (lib "eagle-import") (part "MA05-2"))
    )
    (comp (ref "SV143")
      (value "MA05-2")
      (footprint "eagle-import:MA05-2")
      (libsource (lib "eagle-import") (part "MA05-2"))
    )
    (comp (ref "SV144")
      (value "MA05-2")
      (footprint "eagle-import:MA05-2")
      (libsource (lib "eagle-import") (part "MA05-2"))
    )
    (comp (ref "SV145")
      (value "MA05-2")
      (footprint "eagle-import:MA05-2")
      (libsource (lib "eagle-import") (part "MA05-2"))
    )
    (comp (ref "SV146")
      (value "MA05-2")
      (footprint "eagle-import:MA05-2")
      (libsource (lib "eagle-import") (part "MA05-2"))
    )
    (comp (ref "SV147")
      (value "MA05-2")
      (footprint "eagle-import:MA05-2")
      (libsource (lib "eagle-import") (part "MA05-2"))
    )
    (comp (ref "SV148")
      (value "MA05-2")
      (footprint "eagle-import:MA05-2")
      (libsource (lib "eagle-import") (part "MA05-2"))
    )
    (comp (ref "SV149")
      (value "MA05-2")
      (footprint "eagle-import:MA05-2")
      (libsource (lib "eagle-import") (part "MA05-2"))
    )
    (comp (ref "SV150")
      (value "MA05-2")
      (footprint "eagle-import:MA05-2")
      (libsource (lib "eagle-import") (part "MA05-2"))
    )
    (comp (ref "SV151")
      (value "MA05-2")
      (footprint "eagle-import:MA05-2")
      (libsource (lib "eagle-import") (part "MA05-2"))
    )
    (comp (ref "SV152")
      (value "MA05-2")
      (footprint "eagle-import:MA05-2")
      (libsource (lib "eagle-import") (part "MA05-2"))
    )
    (comp (ref "SV153")
      (value "MA05-2")
      (footprint "eagle-import:MA05-2")
      (libsource (lib "eagle-import") (part "MA05-2"))
    )
    (comp (ref "SV154")
      (value "MA05-2")
      (footprint "eagle-import:MA05-2")
      (libsource (lib "eagle-import") (part "MA05-2"))
    )
    (comp (ref "SV155")
      (value "MA05-2")
      (footprint "eagle-import:MA05-2")
      (libsource (lib "eagle-import") (part "MA05-2"))
    )
    (comp (ref "SV156")
      (value "MA05-2")
      (footprint "eagle-import:MA05-2")
      (libsource (lib "eagle-import") (part "MA05-2"))
    )
    (comp (ref "SV157")
      (value "MA05-2")
      (footprint "eagle-import:MA05-2")
      (libsource (lib "eagle-import") (part "MA05-2"))
    )
    (comp (ref "SV158")
      (value "MA05-2")
      (footprint "eagle-import:MA05-2")
      (libsource (lib "eagle-import") (part "MA05-2"))
    )
    (comp (ref "SV159")
      (value "MA05-2")
      (footprint "eagle-import:MA05-2")
      (libsource (lib "eagle-import") (part "MA05-2"))
    )
    (comp (ref "SV160")
      (value "MA05-2")
      (footprint "eagle-import:MA05-2")
      (libsource (lib "eagle-import") (part "MA05-2"))
    )
    (comp (ref "SV161")
      (value "MA05-2")
      (footprint "eagle-import:MA05-2")
      (libsource (lib "eagle-import") (part "MA05-2"))
    )
    (comp (ref "SV162")
      (value "MA05-2")
      (footprint "eagle-import:MA05-2")
      (libsource (lib "eagle-import") (part "MA05-2"))
    )
    (comp (ref "SV163")
      (value "MA05-2")
      (footprint "eagle-import:MA05-2")
      (libsource (lib "eagle-import") (part "MA05-2"))
    )
    (comp (ref "SV164")
      (value "MA05-2")
      (footprint "eagle-import:MA05-2")
      (libsource (lib "eagle-import") (part "MA05-2"))
    )
    (comp (ref "SV165")
      (value "MA05-2")
      (footprint "eagle-import:MA05-2")
      (libsource (lib "eagle-import") (part "MA05-2"))
    )
    (comp (ref "SV166")
      (value "MA05-2")
      (footprint "eagle-import:MA05-2")
      (libsource (lib "eagle-import") (part "MA05-2"))
    )
    (comp (ref "SV167")
      (value "MA05-2")
      (footprint "eagle-import:MA05-2")
      (libsource (lib "eagle-import") (part "MA05-2"))
    )
    (comp (ref "SV168")
      (value "MA05-2")
      (footprint "eagle-import:MA05-2")
      (libsource (lib "eagle-import") (part "MA05-2"))
    )
    (comp (ref "SV169")
      (value "MA05-2")
      (footprint "eagle-import:MA05-2")
      (libsource (lib "eagle-import") (part "MA05-2"))
    )
    (comp (ref "SV170")
      (value "MA05-2")
      (footprint "eagle-import:MA05-2")
      (libsource (lib "eagle-import") (part "MA05-2"))
    )
    (comp (ref "SV171")
      (value "MA05-2")
      (footprint "eagle-import:MA05-2")
      (libsource (lib "eagle-import") (part "MA05-2"))
    )
    (comp (ref "SV172")
      (value "MA05-2")
      (footprint "eagle-import:MA05-2")
      (libsource (lib "eagle-import") (part "MA05-2"))
    )
    (comp (ref "SV173")
      (value "MA05-2")
      (footprint "eagle-import:MA05-2")
      (libsource (lib "eagle-import") (part "MA05-2"))
    )
    (comp (ref "SV174")
      (value "MA05-2")
      (footprint "eagle-import:MA05-2")
      (libsource (lib "eagle-import") (part "MA05-2"))
    )
    (comp (ref "SV175")
      (value "MA20-1")
      (footprint "eagle-import:MA20-1")
      (libsource (lib "eagle-import") (part "MA20-1"))
    )
    (comp (ref "SV176")
      (value "MA20-1")
      (footprint "eagle-import:MA20-1")
      (libsource (lib "eagle-import") (part "MA20-1"))
    )
    (comp (ref "SV177")
      (value "MA08-1")
      (footprint "eagle-import:MA08-1")
      (libsource (lib "eagle-import") (part "MA08-1"))
    )
    (comp (ref "SV178")
      (value "MA08-1")
      (footprint "eagle-import:MA08-1")
      (libsource (lib "eagle-import") (part "MA08-1"))
    )
    (comp (ref "SV179")
      (value "MA10-1")
      (footprint "eagle-import:MA10-1")
      (libsource (lib "eagle-import") (part "MA10-1"))
    )
    (comp (ref "SV180")
      (value "MA10-1")
      (footprint "eagle-import:MA10-1")
      (libsource (lib "eagle-import") (part "MA10-1"))
    )
    (comp (ref "B1")
      (value "CR2032")
      (footprint "eagle-import:B2430UNI")
      (libsource (lib "eagle-import") (part "B2430UNI"))
    )
    (comp (ref "C1")
      (value "22uF")
      (footprint "eagle-import:C050-025X075")
      (libsource (lib "eagle-import") (part "C-US050-025X075"))
    )
    (comp (ref "C2")
      (value "200pF")
      (footprint "eagle-import:C050-025X075")
      (libsource (lib "eagle-import") (part "C-US050-025X075"))
    )
    (comp (ref "C3")
      (value "0.1uF")
      (footprint "eagle-import:C050-025X075")
      (libsource (lib "eagle-import") (part "C-US050-025X075"))
    )
    (comp (ref "C4")
      (value "0.1uF")
      (footprint "eagle-import:C050-025X075")
      (libsource (lib "eagle-import") (part "C-US050-025X075"))
    )
    (comp (ref "C5")
      (value "0.1uF")
      (footprint "eagle-import:C050-025X075")
      (libsource (lib "eagle-import") (part "C-US050-025X075"))
    )
    (comp (ref "C6")
      (value "0.1uF")
      (footprint "eagle-import:C050-025X075")
      (libsource (lib "eagle-import") (part "C-US050-025X075"))
    )
    (comp (ref "C7")
      (value "0.1uF")
      (footprint "eagle-import:C050-025X075")
      (libsource (lib "eagle-import") (part "C-US050-025X075"))
    )
    (comp (ref "C8")
      (value "0.1uF")
      (footprint "eagle-import:C050-025X075")
      (libsource (lib "eagle-import") (part "C-US050-025X075"))
    )
    (comp (ref "C9")
      (value "0.1uF")
      (footprint "eagle-import:C050-025X075")
      (libsource (lib "eagle-import") (part "C-US050-025X075"))
    )
    (comp (ref "C10")
      (value "100uF")
      (footprint "eagle-import:E12-8")
      (libsource (lib "eagle-import") (part "CPOL-USE20-8AXIAL"))
    )
    (comp (ref "C11")
      (value "47pF")
      (footprint "eagle-import:C050-025X075")
      (libsource (lib "eagle-import") (part "C-US050-025X075"))
    )
    (comp (ref "D1")
      (value "BAT19")
      (footprint "eagle-import:DO35-10")
      (libsource (lib "eagle-import") (part "BAT19"))
    )
    (comp (ref "D2")
      (value "BAT19")
      (footprint "eagle-import:DO35-10")
      (libsource (lib "eagle-import") (part "BAT19"))
    )
    (comp (ref "IC1")
      (value "74ABT245N")
      (footprint "eagle-import:DIL20")
      (libsource (lib "eagle-import") (part "74245NLS"))
    )
    (comp (ref "IC2")
      (value "74ABT245N")
      (footprint "eagle-import:DIL20")
      (libsource (lib "eagle-import") (part "74245NLS"))
    )
    (comp (ref "IC3")
      (value "62256")
      (footprint "eagle-import:DIL28-6")
      (fields (field (name "MPN") "HN58C256AP85E"))
      (libsource (lib "eagle-import") (part "58C256P"))
    )
    (comp (ref "IC4")
      (value "62256")
      (footprint "eagle-import:DIL28-6")
      (fields (field (name "MPN") "HN58C256AP85E"))
      (libsource (lib "eagle-import") (part "58C256P"))
    )
    (comp (ref "IC5")
      (value "74ACT138N")
      (footprint "eagle-import:DIL16")
      (libsource (lib "eagle-import") (part "74138NLS"))
    )
    (comp (ref "IC6")
      (value "74HCT30N")
      (footprint "eagle-import:DIL14")
      (libsource (lib "eagle-import") (part "7430NLS"))
    )
    (comp (ref "IC7")
      (value "74ACT20N")
      (footprint "eagle-import:DIL14")
      (libsource (lib "eagle-import") (part "7420NLS"))
    )
    (comp (ref "IC8")
      (value "74ABT540N")
      (footprint "eagle-import:DIL20")
      (libsource (lib "eagle-import") (part "74540NLS"))
    )
    (comp (ref "IC37")
      (value "74ACT138N")
      (footprint "eagle-import:DIL16")
      (libsource (lib "eagle-import") (part "74138NLS"))
    )
    (comp (ref "IC38")
      (value "74LS139N")
      (footprint "eagle-import:DIL16")
      (libsource (lib "eagle-import") (part "74139NLS"))
    )
    (comp (ref "IC39")
      (value "74ACT138N")
      (footprint "eagle-import:DIL16")
      (libsource (lib "eagle-import") (part "74138NLS"))
    )
    (comp (ref "IC40")
      (value "74ACT138N")
      (footprint "eagle-import:DIL16")
      (libsource (lib "eagle-import") (part "74138NLS"))
    )
    (comp (ref "IC41")
      (value "74ACT74N")
      (footprint "eagle-import:DIL14")
      (libsource (lib "eagle-import") (part "7474NLS"))
    )
    (comp (ref "IC42")
      (value "74ACT74N")
      (footprint "eagle-import:DIL14")
      (libsource (lib "eagle-import") (part "7474NLS"))
    )
    (comp (ref "IC43")
      (value "DS75452N")
      (footprint "eagle-import:DIL08")
      (libsource (lib "eagle-import") (part "DS75452N"))
    )
    (comp (ref "IC45")
      (value "DS75453N")
      (footprint "eagle-import:DIL08")
      (libsource (lib "eagle-import") (part "DS75453N"))
    )
    (comp (ref "Q1")
      (value "2N3904")
      (footprint "eagle-import:TO92")
      (libsource (lib "eagle-import") (part "2N3904"))
    )
    (comp (ref "R1")
      (value "10K")
      (footprint "eagle-import:0207_10")
      (libsource (lib "eagle-import") (part "R-US_0207/10"))
    )
    (comp (ref "R2")
      (value "10K")
      (footprint "eagle-import:0207_10")
      (libsource (lib "eagle-import") (part "R-US_0207/10"))
    )
    (comp (ref "R3")
      (value "10K")
      (footprint "eagle-import:0207_10")
      (libsource (lib "eagle-import") (part "R-US_0207/10"))
    )
    (comp (ref "R4")
      (value "10K")
      (footprint "eagle-import:0207_10")
      (libsource (lib "eagle-import") (part "R-US_0207/10"))
    )
    (comp (ref "R5")
      (value "10K")
      (footprint "eagle-import:DIL16")
      (libsource (lib "eagle-import") (part "8R-P"))
    )
    (comp (ref "R6")
      (value "100K")
      (footprint "eagle-import:0207_10")
      (libsource (lib "eagle-import") (part "R-US_0207/10"))
    )
    (comp (ref "R7")
      (value "100K")
      (footprint "eagle-import:0207_10")
      (libsource (lib "eagle-import") (part "R-US_0207/10"))
    )
    (comp (ref "S1")
      (value "SW_DIP-8")
      (footprint "eagle-import:EDG-08")
      (libsource (lib "eagle-import") (part "SW_DIP-8"))
    )
  )
  (nets
    (net (code "1") (name "+15V") (class "Default")
      (node (ref "D14") (pin "1") (pinfunction "1_1") (pintype "passive"))
      (node (ref "U$2") (pin "DA2") (pinfunction "1_DA2") (pintype "bidirectional"))
    )
    (net (code "2") (name "-15V") (class "Default")
      (node (ref "D10") (pin "2") (pinfunction "2_2") (pintype "passive"))
      (node (ref "D12") (pin "2") (pinfunction "2_2") (pintype "passive"))
      (node (ref "D14") (pin "2") (pinfunction "2_2") (pintype "passive"))
      (node (ref "D8") (pin "2") (pinfunction "2_2") (pintype "passive"))
      (node (ref "U$2") (pin "AB2") (pinfunction "1_AB2") (pintype "bidirectional"))
      (node (ref "U$2") (pin "BB2") (pinfunction "1_BB2") (pintype "bidirectional"))
      (node (ref "U$2") (pin "CB2") (pinfunction "1_CB2") (pintype "bidirectional"))
      (node (ref "U$2") (pin "DB2") (pinfunction "1_DB2") (pintype "bidirectional"))
    )
    (net (code "3") (name "1HZ") (class "Default")
      (node (ref "IC42") (pin "3") (pinfunction "CLK_3") (pintype "input"))
    )
    (net (code "4") (name "DISABLE") (class "Default")
      (node (ref "C2") (pin "2") (pinfunction "2_2") (pintype "passive"))
      (node (ref "IC37") (pin "4") (pinfunction "G2A_4") (pintype "input"))
      (node (ref "IC37") (pin "5") (pinfunction "G2B_5") (pintype "input"))
      (node (ref "IC38") (pin "1") (pinfunction "G_1") (pintype "input"))
      (node (ref "IC38") (pin "15") (pinfunction "G_15") (pintype "input"))
      (node (ref "IC6") (pin "8") (pinfunction "O_8") (pintype "output"))
      (node (ref "IC8") (pin "8") (pinfunction "A7_8") (pintype "input"))
      (node (ref "Q1") (pin "3") (pinfunction "E_3") (pintype "passive"))
    )
    (net (code "5") (name "EMEM0") (class "Default")
      (node (ref "IC2") (pin "11") (pinfunction "B8_11") (pintype "bidirectional"))
      (node (ref "IC4") (pin "19") (pinfunction "I/O7_19") (pintype "tri_state"))
    )
    (net (code "6") (name "EMEM1") (class "Default")
      (node (ref "IC2") (pin "12") (pinfunction "B7_12") (pintype "bidirectional"))
      (node (ref "IC4") (pin "18") (pinfunction "I/O6_18") (pintype "tri_state"))
    )
    (net (code "7") (name "EMEM2") (class "Default")
      (node (ref "IC2") (pin "13") (pinfunction "B6_13") (pintype "bidirectional"))
      (node (ref "IC4") (pin "17") (pinfunction "I/O5_17") (pintype "tri_state"))
    )
    (net (code "8") (name "EMEM3") (class "Default")
      (node (ref "IC2") (pin "14") (pinfunction "B5_14") (pintype "bidirectional"))
      (node (ref "IC4") (pin "16") (pinfunction "I/O4_16") (pintype "tri_state"))
    )
    (net (code "9") (name "GND") (class "Default")
      (node (ref "B1") (pin "-") (pinfunction "-_-") (pintype "passive"))
      (node (ref "B1") (pin "-@1") (pinfunction "-_-@1") (pintype "passive"))
      (node (ref "C1") (pin "2") (pinfunction "2_2") (pintype "passive"))
      (node (ref "C10") (pin "-") (pinfunction "-_-") (pintype "passive"))
      (node (ref "C11") (pin "2") (pinfunction "2_2") (pintype "passive"))
      (node (ref "C3") (pin "2") (pinfunction "2_2") (pintype "passive"))
      (node (ref "C4") (pin "2") (pinfunction "2_2") (pintype "passive"))
      (node (ref "C5") (pin "2") (pinfunction "2_2") (pintype "passive"))
      (node (ref "C6") (pin "2") (pinfunction "2_2") (pintype "passive"))
      (node (ref "C7") (pin "2") (pinfunction "2_2") (pintype "passive"))
      (node (ref "C8") (pin "2") (pinfunction "2_2") (pintype "passive"))
      (node (ref "C9") (pin "2") (pinfunction "2_2") (pintype "passive"))
      (node (ref "D10") (pin "12") (pinfunction "12_12") (pintype "passive"))
      (node (ref "D10") (pin "16") (pinfunction "16_16") (pintype "passive"))
      (node (ref "D10") (pin "3") (pinfunction "3_3") (pintype "passive"))
      (node (ref "D10") (pin "6") (pinfunction "6_6") (pintype "passive"))
      (node (ref "D11") (pin "12") (pinfunction "12_12") (pintype "passive"))
      (node (ref "D11") (pin "16") (pinfunction "16_16") (pintype "passive"))
      (node (ref "D11") (pin "3") (pinfunction "3_3") (pintype "passive"))
      (node (ref "D11") (pin "6") (pinfunction "6_6") (pintype "passive"))
      (node (ref "D12") (pin "12") (pinfunction "12_12") (pintype "passive"))
      (node (ref "D12") (pin "16") (pinfunction "16_16") (pintype "passive"))
      (node (ref "D12") (pin "3") (pinfunction "3_3") (pintype "passive"))
      (node (ref "D12") (pin "6") (pinfunction "6_6") (pintype "passive"))
      (node (ref "D13") (pin "12") (pinfunction "12_12") (pintype "passive"))
      (node (ref "D13") (pin "16") (pinfunction "16_16") (pintype "passive"))
      (node (ref "D13") (pin "3") (pinfunction "3_3") (pintype "passive"))
      (node (ref "D13") (pin "6") (pinfunction "6_6") (pintype "passive"))
      (node (ref "D14") (pin "12") (pinfunction "12_12") (pintype "passive"))
      (node (ref "D14") (pin "16") (pinfunction "16_16") (pintype "passive"))
      (node (ref "D14") (pin "3") (pinfunction "3_3") (pintype "passive"))
      (node (ref "D14") (pin "6") (pinfunction "6_6") (pintype "passive"))
      (node (ref "D7") (pin "12") (pinfunction "12_12") (pintype "passive"))
      (node (ref "D7") (pin "16") (pinfunction "16_16") (pintype "passive"))
      (node (ref "D7") (pin "3") (pinfunction "3_3") (pintype "passive"))
      (node (ref "D7") (pin "6") (pinfunction "6_6") (pintype "passive"))
      (node (ref "D8") (pin "12") (pinfunction "12_12") (pintype "passive"))
      (node (ref "D8") (pin "16") (pinfunction "16_16") (pintype "passive"))
      (node (ref "D8") (pin "3") (pinfunction "3_3") (pintype "passive"))
      (node (ref "D8") (pin "6") (pinfunction "6_6") (pintype "passive"))
      (node (ref "D9") (pin "12") (pinfunction "12_12") (pintype "passive"))
      (node (ref "D9") (pin "16") (pinfunction "16_16") (pintype "passive"))
      (node (ref "D9") (pin "3") (pinfunction "3_3") (pintype "passive"))
      (node (ref "D9") (pin "6") (pinfunction "6_6") (pintype "passive"))
      (node (ref "GND1") (pin "1") (pinfunction "1_1") (pintype "passive"))
      (node (ref "GND1") (pin "2") (pinfunction "2_2") (pintype "passive"))
      (node (ref "GND10") (pin "1") (pinfunction "1_1") (pintype "passive"))
      (node (ref "GND10") (pin "2") (pinfunction "2_2") (pintype "passive"))
      (node (ref "GND11") (pin "1") (pinfunction "1_1") (pintype "passive"))
      (node (ref "GND11") (pin "2") (pinfunction "2_2") (pintype "passive"))
      (node (ref "GND12") (pin "1") (pinfunction "1_1") (pintype "passive"))
      (node (ref "GND12") (pin "2") (pinfunction "2_2") (pintype "passive"))
      (node (ref "GND13") (pin "1") (pinfunction "1_1") (pintype "passive"))
      (node (ref "GND13") (pin "2") (pinfunction "2_2") (pintype "passive"))
      (node (ref "GND14") (pin "1") (pinfunction "1_1") (pintype "passive"))
      (node (ref "GND14") (pin "2") (pinfunction "2_2") (pintype "passive"))
      (node (ref "GND15") (pin "1") (pinfunction "1_1") (pintype "passive"))
      (node (ref "GND15") (pin "2") (pinfunction "2_2") (pintype "passive"))
      (node (ref "GND16") (pin "1") (pinfunction "1_1") (pintype "passive"))
      (node (ref "GND16") (pin "2") (pinfunction "2_2") (pintype "passive"))
      (node (ref "GND17") (pin "1") (pinfunction "1_1") (pintype "passive"))
      (node (ref "GND17") (pin "2") (pinfunction "2_2") (pintype "passive"))
      (node (ref "GND18") (pin "1") (pinfunction "1_1") (pintype "passive"))
      (node (ref "GND18") (pin "2") (pinfunction "2_2") (pintype "passive"))
      (node (ref "GND19") (pin "1") (pinfunction "1_1") (pintype "passive"))
      (node (ref "GND19") (pin "2") (pinfunction "2_2") (pintype "passive"))
      (node (ref "GND2") (pin "1") (pinfunction "1_1") (pintype "passive"))
      (node (ref "GND2") (pin "2") (pinfunction "2_2") (pintype "passive"))
      (node (ref "GND20") (pin "1") (pinfunction "1_1") (pintype "passive"))
      (node (ref "GND20") (pin "2") (pinfunction "2_2") (pintype "passive"))
      (node (ref "GND21") (pin "1") (pinfunction "1_1") (pintype "passive"))
      (node (ref "GND21") (pin "2") (pinfunction "2_2") (pintype "passive"))
      (node (ref "GND22") (pin "1") (pinfunction "1_1") (pintype "passive"))
      (node (ref "GND22") (pin "2") (pinfunction "2_2") (pintype "passive"))
      (node (ref "GND23") (pin "1") (pinfunction "1_1") (pintype "passive"))
      (node (ref "GND23") (pin "2") (pinfunction "2_2") (pintype "passive"))
      (node (ref "GND24") (pin "1") (pinfunction "1_1") (pintype "passive"))
      (node (ref "GND24") (pin "2") (pinfunction "2_2") (pintype "passive"))
      (node (ref "GND25") (pin "1") (pinfunction "1_1") (pintype "passive"))
      (node (ref "GND25") (pin "2") (pinfunction "2_2") (pintype "passive"))
      (node (ref "GND26") (pin "1") (pinfunction "1_1") (pintype "passive"))
      (node (ref "GND26") (pin "2") (pinfunction "2_2") (pintype "passive"))
      (node (ref "GND27") (pin "1") (pinfunction "1_1") (pintype "passive"))
      (node (ref "GND27") (pin "2") (pinfunction "2_2") (pintype "passive"))
      (node (ref "GND28") (pin "1") (pinfunction "1_1") (pintype "passive"))
      (node (ref "GND28") (pin "2") (pinfunction "2_2") (pintype "passive"))
      (node (ref "GND29") (pin "1") (pinfunction "1_1") (pintype "passive"))
      (node (ref "GND29") (pin "2") (pinfunction "2_2") (pintype "passive"))
      (node (ref "GND3") (pin "1") (pinfunction "1_1") (pintype "passive"))
      (node (ref "GND3") (pin "2") (pinfunction "2_2") (pintype "passive"))
      (node (ref "GND30") (pin "1") (pinfunction "1_1") (pintype "passive"))
      (node (ref "GND30") (pin "2") (pinfunction "2_2") (pintype "passive"))
      (node (ref "GND31") (pin "1") (pinfunction "1_1") (pintype "passive"))
      (node (ref "GND31") (pin "2") (pinfunction "2_2") (pintype "passive"))
      (node (ref "GND32") (pin "1") (pinfunction "1_1") (pintype "passive"))
      (node (ref "GND32") (pin "2") (pinfunction "2_2") (pintype "passive"))
      (node (ref "GND33") (pin "1") (pinfunction "1_1") (pintype "passive"))
      (node (ref "GND33") (pin "2") (pinfunction "2_2") (pintype "passive"))
      (node (ref "GND34") (pin "1") (pinfunction "1_1") (pintype "passive"))
      (node (ref "GND34") (pin "2") (pinfunction "2_2") (pintype "passive"))
      (node (ref "GND35") (pin "1") (pinfunction "1_1") (pintype "passive"))
      (node (ref "GND35") (pin "2") (pinfunction "2_2") (pintype "passive"))
      (node (ref "GND36") (pin "1") (pinfunction "1_1") (pintype "passive"))
      (node (ref "GND36") (pin "2") (pinfunction "2_2") (pintype "passive"))
      (node (ref "GND37") (pin "1") (pinfunction "1_1") (pintype "passive"))
      (node (ref "GND37") (pin "2") (pinfunction "2_2") (pintype "passive"))
      (node (ref "GND38") (pin "1") (pinfunction "1_1") (pintype "passive"))
      (node (ref "GND38") (pin "2") (pinfunction "2_2") (pintype "passive"))
      (node (ref "GND39") (pin "1") (pinfunction "1_1") (pintype "passive"))
      (node (ref "GND39") (pin "2") (pinfunction "2_2") (pintype "passive"))
      (node (ref "GND4") (pin "1") (pinfunction "1_1") (pintype "passive"))
      (node (ref "GND4") (pin "2") (pinfunction "2_2") (pintype "passive"))
      (node (ref "GND40") (pin "1") (pinfunction "1_1") (pintype "passive"))
      (node (ref "GND40") (pin "2") (pinfunction "2_2") (pintype "passive"))
      (node (ref "GND41") (pin "1") (pinfunction "1_1") (pintype "passive"))
      (node (ref "GND41") (pin "2") (pinfunction "2_2") (pintype "passive"))
      (node (ref "GND42") (pin "1") (pinfunction "1_1") (pintype "passive"))
      (node (ref "GND42") (pin "2") (pinfunction "2_2") (pintype "passive"))
      (node (ref "GND43") (pin "1") (pinfunction "1_1") (pintype "passive"))
      (node (ref "GND43") (pin "2") (pinfunction "2_2") (pintype "passive"))
      (node (ref "GND44") (pin "1") (pinfunction "1_1") (pintype "passive"))
      (node (ref "GND44") (pin "2") (pinfunction "2_2") (pintype "passive"))
      (node (ref "GND5") (pin "1") (pinfunction "1_1") (pintype "passive"))
      (node (ref "GND5") (pin "2") (pinfunction "2_2") (pintype "passive"))
      (node (ref "GND6") (pin "1") (pinfunction "1_1") (pintype "passive"))
      (node (ref "GND6") (pin "2") (pinfunction "2_2") (pintype "passive"))
      (node (ref "GND7") (pin "1") (pinfunction "1_1") (pintype "passive"))
      (node (ref "GND7") (pin "2") (pinfunction "2_2") (pintype "passive"))
      (node (ref "GND8") (pin "1") (pinfunction "1_1") (pintype "passive"))
      (node (ref "GND8") (pin "2") (pinfunction "2_2") (pintype "passive"))
      (node (ref "GND9") (pin "1") (pinfunction "1_1") (pintype "passive"))
      (node (ref "GND9") (pin "2") (pinfunction "2_2") (pintype "passive"))
      (node (ref "IC1") (pin "19") (pinfunction "G_19") (pintype "input"))
      (node (ref "IC2") (pin "19") (pinfunction "G_19") (pintype "input"))
      (node (ref "IC3") (pin "14") (pinfunction "VSS_14") (pintype "power_in"))
      (node (ref "IC4") (pin "14") (pinfunction "VSS_14") (pintype "power_in"))
      (node (ref "IC41") (pin "12") (pinfunction "D_12") (pintype "input"))
      (node (ref "IC5") (pin "4") (pinfunction "G2A_4") (pintype "input"))
      (node (ref "IC5") (pin "5") (pinfunction "G2B_5") (pintype "input"))
      (node (ref "IC8") (pin "1") (pinfunction "G1_1") (pintype "input"))
      (node (ref "IC8") (pin "19") (pinfunction "G2_19") (pintype "input"))
      (node (ref "IC8") (pin "9") (pinfunction "A8_9") (pintype "input"))
      (node (ref "R1") (pin "1") (pinfunction "1_1") (pintype "passive"))
      (node (ref "R2") (pin "1") (pinfunction "1_1") (pintype "passive"))
      (node (ref "R3") (pin "1") (pinfunction "1_1") (pintype "passive"))
      (node (ref "R4") (pin "1") (pinfunction "1_1") (pintype "passive"))
      (node (ref "SV10") (pin "1") (pinfunction "1_1") (pintype "passive"))
      (node (ref "SV10") (pin "2") (pinfunction "2_2") (pintype "passive"))
      (node (ref "SV10") (pin "3") (pinfunction "3_3") (pintype "passive"))
      (node (ref "SV10") (pin "4") (pinfunction "4_4") (pintype "passive"))
      (node (ref "SV10") (pin "5") (pinfunction "5_5") (pintype "passive"))
      (node (ref "SV10") (pin "6") (pinfunction "6_6") (pintype "passive"))
      (node (ref "SV10") (pin "7") (pinfunction "7_7") (pintype "passive"))
      (node (ref "SV10") (pin "8") (pinfunction "8_8") (pintype "passive"))
      (node (ref "SV12") (pin "1") (pinfunction "1_1") (pintype "passive"))
      (node (ref "SV12") (pin "10") (pinfunction "10_10") (pintype "passive"))
      (node (ref "SV12") (pin "2") (pinfunction "2_2") (pintype "passive"))
      (node (ref "SV12") (pin "3") (pinfunction "3_3") (pintype "passive"))
      (node (ref "SV12") (pin "4") (pinfunction "4_4") (pintype "passive"))
      (node (ref "SV12") (pin "5") (pinfunction "5_5") (pintype "passive"))
      (node (ref "SV12") (pin "6") (pinfunction "6_6") (pintype "passive"))
      (node (ref "SV12") (pin "7") (pinfunction "7_7") (pintype "passive"))
      (node (ref "SV12") (pin "8") (pinfunction "8_8") (pintype "passive"))
      (node (ref "SV12") (pin "9") (pinfunction "9_9") (pintype "passive"))
      (node (ref "SV176") (pin "1") (pinfunction "1_1") (pintype "passive"))
      (node (ref "SV176") (pin "10") (pinfunction "10_10") (pintype "passive"))
      (node (ref "SV176") (pin "11") (pinfunction "11_11") (pintype "passive"))
      (node (ref "SV176") (pin "12") (pinfunction "12_12") (pintype "passive"))
      (node (ref "SV176") (pin "13") (pinfunction "13_13") (pintype "passive"))
      (node (ref "SV176") (pin "14") (pinfunction "14_14") (pintype "passive"))
      (node (ref "SV176") (pin "15") (pinfunction "15_15") (pintype "passive"))
      (node (ref "SV176") (pin "16") (pinfunction "16_16") (pintype "passive"))
      (node (ref "SV176") (pin "17") (pinfunction "17_17") (pintype "passive"))
      (node (ref "SV176") (pin "18") (pinfunction "18_18") (pintype "passive"))
      (node (ref "SV176") (pin "19") (pinfunction "19_19") (pintype "passive"))
      (node (ref "SV176") (pin "2") (pinfunction "2_2") (pintype "passive"))
      (node (ref "SV176") (pin "20") (pinfunction "20_20") (pintype "passive"))
      (node (ref "SV176") (pin "3") (pinfunction "3_3") (pintype "passive"))
      (node (ref "SV176") (pin "4") (pinfunction "4_4") (pintype "passive"))
      (node (ref "SV176") (pin "5") (pinfunction "5_5") (pintype "passive"))
      (node (ref "SV176") (pin "6") (pinfunction "6_6") (pintype "passive"))
      (node (ref "SV176") (pin "7") (pinfunction "7_7") (pintype "passive"))
      (node (ref "SV176") (pin "8") (pinfunction "8_8") (pintype "passive"))
      (node (ref "SV176") (pin "9") (pinfunction "9_9") (pintype "passive"))
      (node (ref "SV180") (pin "1") (pinfunction "1_1") (pintype "passive"))
      (node (ref "SV180") (pin "10") (pinfunction "10_10") (pintype "passive"))
      (node (ref "SV180") (pin "2") (pinfunction "2_2") (pintype "passive"))
      (node (ref "SV180") (pin "3") (pinfunction "3_3") (pintype "passive"))
      (node (ref "SV180") (pin "4") (pinfunction "4_4") (pintype "passive"))
      (node (ref "SV180") (pin "5") (pinfunction "5_5") (pintype "passive"))
      (node (ref "SV180") (pin "6") (pinfunction "6_6") (pintype "passive"))
      (node (ref "SV180") (pin "7") (pinfunction "7_7") (pintype "passive"))
      (node (ref "SV180") (pin "8") (pinfunction "8_8") (pintype "passive"))
      (node (ref "SV180") (pin "9") (pinfunction "9_9") (pintype "passive"))
      (node (ref "SV4") (pin "1") (pinfunction "1_1") (pintype "passive"))
      (node (ref "SV4") (pin "10") (pinfunction "10_10") (pintype "passive"))
      (node (ref "SV4") (pin "11") (pinfunction "11_11") (pintype "passive"))
      (node (ref "SV4") (pin "12") (pinfunction "12_12") (pintype "passive"))
      (node (ref "SV4") (pin "13") (pinfunction "13_13") (pintype "passive"))
      (node (ref "SV4") (pin "14") (pinfunction "14_14") (pintype "passive"))
      (node (ref "SV4") (pin "15") (pinfunction "15_15") (pintype "passive"))
      (node (ref "SV4") (pin "16") (pinfunction "16_16") (pintype "passive"))
      (node (ref "SV4") (pin "17") (pinfunction "17_17") (pintype "passive"))
      (node (ref "SV4") (pin "18") (pinfunction "18_18") (pintype "passive"))
      (node (ref "SV4") (pin "19") (pinfunction "19_19") (pintype "passive"))
      (node (ref "SV4") (pin "2") (pinfunction "2_2") (pintype "passive"))
      (node (ref "SV4") (pin "20") (pinfunction "20_20") (pintype "passive"))
      (node (ref "SV4") (pin "3") (pinfunction "3_3") (pintype "passive"))
      (node (ref "SV4") (pin "4") (pinfunction "4_4") (pintype "passive"))
      (node (ref "SV4") (pin "5") (pinfunction "5_5") (pintype "passive"))
      (node (ref "SV4") (pin "6") (pinfunction "6_6") (pintype "passive"))
      (node (ref "SV4") (pin "7") (pinfunction "7_7") (pintype "passive"))
      (node (ref "SV4") (pin "8") (pinfunction "8_8") (pintype "passive"))
      (node (ref "SV4") (pin "9") (pinfunction "9_9") (pintype "passive"))
      (node (ref "SV6") (pin "1") (pinfunction "1_1") (pintype "passive"))
      (node (ref "SV6") (pin "10") (pinfunction "10_10") (pintype "passive"))
      (node (ref "SV6") (pin "11") (pinfunction "11_11") (pintype "passive"))
      (node (ref "SV6") (pin "12") (pinfunction "12_12") (pintype "passive"))
      (node (ref "SV6") (pin "13") (pinfunction "13_13") (pintype "passive"))
      (node (ref "SV6") (pin "14") (pinfunction "14_14") (pintype "passive"))
      (node (ref "SV6") (pin "15") (pinfunction "15_15") (pintype "passive"))
      (node (ref "SV6") (pin "16") (pinfunction "16_16") (pintype "passive"))
      (node (ref "SV6") (pin "17") (pinfunction "17_17") (pintype "passive"))
      (node (ref "SV6") (pin "18") (pinfunction "18_18") (pintype "passive"))
      (node (ref "SV6") (pin "19") (pinfunction "19_19") (pintype "passive"))
      (node (ref "SV6") (pin "2") (pinfunction "2_2") (pintype "passive"))
      (node (ref "SV6") (pin "20") (pinfunction "20_20") (pintype "passive"))
      (node (ref "SV6") (pin "3") (pinfunction "3_3") (pintype "passive"))
      (node (ref "SV6") (pin "4") (pinfunction "4_4") (pintype "passive"))
      (node (ref "SV6") (pin "5") (pinfunction "5_5") (pintype "passive"))
      (node (ref "SV6") (pin "6") (pinfunction "6_6") (pintype "passive"))
      (node (ref "SV6") (pin "7") (pinfunction "7_7") (pintype "passive"))
      (node (ref "SV6") (pin "8") (pinfunction "8_8") (pintype "passive"))
      (node (ref "SV6") (pin "9") (pinfunction "9_9") (pintype "passive"))
      (node (ref "U$2") (pin "AC1") (pinfunction "1_AC1") (pintype "bidirectional"))
      (node (ref "U$2") (pin "AC2") (pinfunction "1_AC2") (pintype "bidirectional"))
      (node (ref "U$2") (pin "AF1") (pinfunction "1_AF1") (pintype "bidirectional"))
      (node (ref "U$2") (pin "AF2") (pinfunction "1_AF2") (pintype "bidirectional"))
      (node (ref "U$2") (pin "AN1") (pinfunction "1_AN1") (pintype "bidirectional"))
      (node (ref "U$2") (pin "AN2") (pinfunction "1_AN2") (pintype "bidirectional"))
      (node (ref "U$2") (pin "AT1") (pinfunction "1_AT1") (pintype "bidirectional"))
      (node (ref "U$2") (pin "AT2") (pinfunction "1_AT2") (pintype "bidirectional"))
      (node (ref "U$2") (pin "BC1") (pinfunction "1_BC1") (pintype "bidirectional"))
      (node (ref "U$2") (pin "BC2") (pinfunction "1_BC2") (pintype "bidirectional"))
      (node (ref "U$2") (pin "BF1") (pinfunction "1_BF1") (pintype "bidirectional"))
      (node (ref "U$2") (pin "BF2") (pinfunction "1_BF2") (pintype "bidirectional"))
      (node (ref "U$2") (pin "BN1") (pinfunction "1_BN1") (pintype "bidirectional"))
      (node (ref "U$2") (pin "BN2") (pinfunction "1_BN2") (pintype "bidirectional"))
      (node (ref "U$2") (pin "BT1") (pinfunction "1_BT1") (pintype "bidirectional"))
      (node (ref "U$2") (pin "BT2") (pinfunction "1_BT2") (pintype "bidirectional"))
      (node (ref "U$2") (pin "CC1") (pinfunction "1_CC1") (pintype "bidirectional"))
      (node (ref "U$2") (pin "CC2") (pinfunction "1_CC2") (pintype "bidirectional"))
      (node (ref "U$2") (pin "CF1") (pinfunction "1_CF1") (pintype "bidirectional"))
      (node (ref "U$2") (pin "CF2") (pinfunction "1_CF2") (pintype "bidirectional"))
      (node (ref "U$2") (pin "CN1") (pinfunction "1_CN1") (pintype "bidirectional"))
      (node (ref "U$2") (pin "CN2") (pinfunction "1_CN2") (pintype "bidirectional"))
      (node (ref "U$2") (pin "CT1") (pinfunction "1_CT1") (pintype "bidirectional"))
      (node (ref "U$2") (pin "CT2") (pinfunction "1_CT2") (pintype "bidirectional"))
      (node (ref "U$2") (pin "DC1") (pinfunction "1_DC1") (pintype "bidirectional"))
      (node (ref "U$2") (pin "DC2") (pinfunction "1_DC2") (pintype "bidirectional"))
      (node (ref "U$2") (pin "DF1") (pinfunction "1_DF1") (pintype "bidirectional"))
      (node (ref "U$2") (pin "DF2") (pinfunction "1_DF2") (pintype "bidirectional"))
      (node (ref "U$2") (pin "DN1") (pinfunction "1_DN1") (pintype "bidirectional"))
      (node (ref "U$2") (pin "DN2") (pinfunction "1_DN2") (pintype "bidirectional"))
      (node (ref "U$2") (pin "DT1") (pinfunction "1_DT1") (pintype "bidirectional"))
      (node (ref "U$2") (pin "DT2") (pinfunction "1_DT2") (pintype "bidirectional"))
    )
    (net (code "10") (name "INHIBIT") (class "Default")
      (node (ref "D10") (pin "13") (pinfunction "13_13") (pintype "passive"))
      (node (ref "U$2") (pin "AP2") (pinfunction "1_AP2") (pintype "bidirectional"))
    )
    (net (code "11") (name "INITIALIZE") (class "Default")
      (node (ref "D11") (pin "14") (pinfunction "14_14") (pintype "passive"))
      (node (ref "IC41") (pin "11") (pinfunction "CLK_11") (pintype "input"))
      (node (ref "U$2") (pin "CR1") (pinfunction "1_CR1") (pintype "bidirectional"))
    )
    (net (code "12") (name "INT_IN_PROG") (class "Default")
      (node (ref "D8") (pin "13") (pinfunction "13_13") (pintype "passive"))
      (node (ref "U$2") (pin "BP2") (pinfunction "1_BP2") (pintype "bidirectional"))
    )
    (net (code "13") (name "INT_STROBE") (class "Default")
      (node (ref "D8") (pin "4") (pinfunction "4_4") (pintype "passive"))
      (node (ref "U$2") (pin "BD2") (pinfunction "1_BD2") (pintype "bidirectional"))
    )
    (net (code "14") (name "MEM00") (class "Default")
      (node (ref "IC2") (pin "15") (pinfunction "B4_15") (pintype "bidirectional"))
      (node (ref "IC4") (pin "15") (pinfunction "I/O3_15") (pintype "tri_state"))
    )
    (net (code "15") (name "MEM01") (class "Default")
      (node (ref "IC2") (pin "16") (pinfunction "B3_16") (pintype "bidirectional"))
      (node (ref "IC4") (pin "13") (pinfunction "I/O2_13") (pintype "tri_state"))
    )
    (net (code "16") (name "MEM02") (class "Default")
      (node (ref "IC2") (pin "17") (pinfunction "B2_17") (pintype "bidirectional"))
      (node (ref "IC4") (pin "12") (pinfunction "I/O1_12") (pintype "tri_state"))
    )
    (net (code "17") (name "MEM03") (class "Default")
      (node (ref "IC2") (pin "18") (pinfunction "B1_18") (pintype "bidirectional"))
      (node (ref "IC4") (pin "11") (pinfunction "I/O0_11") (pintype "tri_state"))
    )
    (net (code "18") (name "MEM04") (class "Default")
      (node (ref "IC1") (pin "11") (pinfunction "B8_11") (pintype "bidirectional"))
      (node (ref "IC3") (pin "19") (pinfunction "I/O7_19") (pintype "tri_state"))
    )
    (net (code "19") (name "MEM05") (class "Default")
      (node (ref "IC1") (pin "12") (pinfunction "B7_12") (pintype "bidirectional"))
      (node (ref "IC3") (pin "18") (pinfunction "I/O6_18") (pintype "tri_state"))
    )
    (net (code "20") (name "MEM06") (class "Default")
      (node (ref "IC1") (pin "13") (pinfunction "B6_13") (pintype "bidirectional"))
      (node (ref "IC3") (pin "17") (pinfunction "I/O5_17") (pintype "tri_state"))
    )
    (net (code "21") (name "MEM07") (class "Default")
      (node (ref "IC1") (pin "14") (pinfunction "B5_14") (pintype "bidirectional"))
      (node (ref "IC3") (pin "16") (pinfunction "I/O4_16") (pintype "tri_state"))
    )
    (net (code "22") (name "MEM08") (class "Default")
      (node (ref "IC1") (pin "15") (pinfunction "B4_15") (pintype "bidirectional"))
      (node (ref "IC3") (pin "15") (pinfunction "I/O3_15") (pintype "tri_state"))
    )
    (net (code "23") (name "MEM09") (class "Default")
      (node (ref "IC1") (pin "16") (pinfunction "B3_16") (pintype "bidirectional"))
      (node (ref "IC3") (pin "13") (pinfunction "I/O2_13") (pintype "tri_state"))
    )
    (net (code "24") (name "MEM10") (class "Default")
      (node (ref "IC1") (pin "17") (pinfunction "B2_17") (pintype "bidirectional"))
      (node (ref "IC3") (pin "12") (pinfunction "I/O1_12") (pintype "tri_state"))
    )
    (net (code "25") (name "MEM11") (class "Default")
      (node (ref "IC1") (pin "18") (pinfunction "B1_18") (pintype "bidirectional"))
      (node (ref "IC3") (pin "11") (pinfunction "I/O0_11") (pintype "tri_state"))
    )
    (net (code "26") (name "Net-(A1-Pad1)") (class "Default")
      (node (ref "A1") (pin "1") (pinfunction "1_1") (pintype "passive"))
      (node (ref "A1") (pin "2") (pinfunction "2_2") (pintype "passive"))
      (node (ref "IC9") (pin "1") (pinfunction "1_1") (pintype "passive"))
    )
    (net (code "27") (name "Net-(A2-Pad1)") (class "Default")
      (node (ref "A2") (pin "1") (pinfunction "1_1") (pintype "passive"))
      (node (ref "A2") (pin "2") (pinfunction "2_2") (pintype "passive"))
      (node (ref "IC9") (pin "2") (pinfunction "2_2") (pintype "passive"))
    )
    (net (code "28") (name "Net-(A3-Pad1)") (class "Default")
      (node (ref "A3") (pin "1") (pinfunction "1_1") (pintype "passive"))
      (node (ref "A3") (pin "2") (pinfunction "2_2") (pintype "passive"))
      (node (ref "IC9") (pin "3") (pinfunction "3_3") (pintype "passive"))
    )
    (net (code "29") (name "Net-(A4-Pad1)") (class "Default")
      (node (ref "A4") (pin "1") (pinfunction "1_1") (pintype "passive"))
      (node (ref "A4") (pin "2") (pinfunction "2_2") (pintype "passive"))
      (node (ref "IC9") (pin "4") (pinfunction "4_4") (pintype "passive"))
    )
    (net (code "30") (name "Net-(A5-Pad1)") (class "Default")
      (node (ref "A5") (pin "1") (pinfunction "1_1") (pintype "passive"))
      (node (ref "A5") (pin "2") (pinfunction "2_2") (pintype "passive"))
      (node (ref "IC9") (pin "5") (pinfunction "5_5") (pintype "passive"))
    )
    (net (code "31") (name "Net-(A6-Pad1)") (class "Default")
      (node (ref "A6") (pin "1") (pinfunction "1_1") (pintype "passive"))
      (node (ref "A6") (pin "2") (pinfunction "2_2") (pintype "passive"))
      (node (ref "IC9") (pin "6") (pinfunction "6_6") (pintype "passive"))
    )
    (net (code "32") (name "Net-(A7-Pad1)") (class "Default")
      (node (ref "A7") (pin "1") (pinfunction "1_1") (pintype "passive"))
      (node (ref "A7") (pin "2") (pinfunction "2_2") (pintype "passive"))
      (node (ref "IC9") (pin "7") (pinfunction "7_7") (pintype "passive"))
    )
    (net (code "33") (name "Net-(A8-Pad1)") (class "Default")
      (node (ref "A8") (pin "1") (pinfunction "1_1") (pintype "passive"))
      (node (ref "A8") (pin "2") (pinfunction "2_2") (pintype "passive"))
      (node (ref "IC9") (pin "8") (pinfunction "8_8") (pintype "passive"))
    )
    (net (code "34") (name "Net-(A9-Pad1)") (class "Default")
      (node (ref "A9") (pin "1") (pinfunction "1_1") (pintype "passive"))
      (node (ref "A9") (pin "2") (pinfunction "2_2") (pintype "passive"))
      (node (ref "IC9") (pin "9") (pinfunction "9_9") (pintype "passive"))
    )
    (net (code "35") (name "Net-(A10-Pad1)") (class "Default")
      (node (ref "A10") (pin "1") (pinfunction "1_1") (pintype "passive"))
      (node (ref "A10") (pin "2") (pinfunction "2_2") (pintype "passive"))
      (node (ref "IC9") (pin "10") (pinfunction "10_10") (pintype "passive"))
    )
    (net (code "36") (name "Net-(A11-Pad1)") (class "Default")
      (node (ref "A11") (pin "1") (pinfunction "1_1") (pintype "passive"))
      (node (ref "A11") (pin "2") (pinfunction "2_2") (pintype "passive"))
      (node (ref "IC9") (pin "11") (pinfunction "11_11") (pintype "passive"))
    )
    (net (code "37") (name "Net-(A12-Pad1)") (class "Default")
      (node (ref "A12") (pin "1") (pinfunction "1_1") (pintype "passive"))
      (node (ref "A12") (pin "2") (pinfunction "2_2") (pintype "passive"))
      (node (ref "IC9") (pin "12") (pinfunction "12_12") (pintype "passive"))
    )
    (net (code "38") (name "Net-(A13-Pad1)") (class "Default")
      (node (ref "A13") (pin "1") (pinfunction "1_1") (pintype "passive"))
      (node (ref "A13") (pin "2") (pinfunction "2_2") (pintype "passive"))
      (node (ref "IC9") (pin "13") (pinfunction "13_13") (pintype "passive"))
    )
    (net (code "39") (name "Net-(A14-Pad1)") (class "Default")
      (node (ref "A14") (pin "1") (pinfunction "1_1") (pintype "passive"))
      (node (ref "A14") (pin "2") (pinfunction "2_2") (pintype "passive"))
      (node (ref "IC9") (pin "14") (pinfunction "14_14") (pintype "passive"))
    )
    (net (code "40") (name "Net-(A15-Pad1)") (class "Default")
      (node (ref "A15") (pin "1") (pinfunction "1_1") (pintype "passive"))
      (node (ref "A15") (pin "2") (pinfunction "2_2") (pintype "passive"))
      (node (ref "IC9") (pin "15") (pinfunction "15_15") (pintype "passive"))
    )
    (net (code "41") (name "Net-(A16-Pad1)") (class "Default")
      (node (ref "A16") (pin "1") (pinfunction "1_1") (pintype "passive"))
      (node (ref "A16") (pin "2") (pinfunction "2_2") (pintype "passive"))
      (node (ref "IC9") (pin "16") (pinfunction "16_16") (pintype "passive"))
    )
    (net (code "42") (name "Net-(A17-Pad1)") (class "Default")
      (node (ref "A17") (pin "1") (pinfunction "1_1") (pintype "passive"))
      (node (ref "A17") (pin "2") (pinfunction "2_2") (pintype "passive"))
      (node (ref "IC10") (pin "1") (pinfunction "1_1") (pintype "passive"))
    )
    (net (code "43") (name "Net-(A18-Pad1)") (class "Default")
      (node (ref "A18") (pin "1") (pinfunction "1_1") (pintype "passive"))
      (node (ref "A18") (pin "2") (pinfunction "2_2") (pintype "passive"))
      (node (ref "IC10") (pin "2") (pinfunction "2_2") (pintype "passive"))
    )
    (net (code "44") (name "Net-(A19-Pad1)") (class "Default")
      (node (ref "A19") (pin "1") (pinfunction "1_1") (pintype "passive"))
      (node (ref "A19") (pin "2") (pinfunction "2_2") (pintype "passive"))
      (node (ref "IC10") (pin "3") (pinfunction "3_3") (pintype "passive"))
    )
    (net (code "45") (name "Net-(A20-Pad1)") (class "Default")
      (node (ref "A20") (pin "1") (pinfunction "1_1") (pintype "passive"))
      (node (ref "A20") (pin "2") (pinfunction "2_2") (pintype "passive"))
      (node (ref "IC10") (pin "4") (pinfunction "4_4") (pintype "passive"))
    )
    (net (code "46") (name "Net-(A21-Pad1)") (class "Default")
      (node (ref "A21") (pin "1") (pinfunction "1_1") (pintype "passive"))
      (node (ref "A21") (pin "2") (pinfunction "2_2") (pintype "passive"))
      (node (ref "IC10") (pin "5") (pinfunction "5_5") (pintype "passive"))
    )
    (net (code "47") (name "Net-(A22-Pad1)") (class "Default")
      (node (ref "A22") (pin "1") (pinfunction "1_1") (pintype "passive"))
      (node (ref "A22") (pin "2") (pinfunction "2_2") (pintype "passive"))
      (node (ref "IC10") (pin "6") (pinfunction "6_6") (pintype "passive"))
    )
    (net (code "48") (name "Net-(A23-Pad1)") (class "Default")
      (node (ref "A23") (pin "1") (pinfunction "1_1") (pintype "passive"))
      (node (ref "A23") (pin "2") (pinfunction "2_2") (pintype "passive"))
      (node (ref "IC10") (pin "7") (pinfunction "7_7") (pintype "passive"))
    )
    (net (code "49") (name "Net-(A24-Pad1)") (class "Default")
      (node (ref "A24") (pin "1") (pinfunction "1_1") (pintype "passive"))
      (node (ref "A24") (pin "2") (pinfunction "2_2") (pintype "passive"))
      (node (ref "IC10") (pin "8") (pinfunction "8_8") (pintype "passive"))
    )
    (net (code "50") (name "Net-(A25-Pad1)") (class "Default")
      (node (ref "A25") (pin "1") (pinfunction "1_1") (pintype "passive"))
      (node (ref "A25") (pin "2") (pinfunction "2_2") (pintype "passive"))
      (node (ref "IC10") (pin "9") (pinfunction "9_9") (pintype "passive"))
    )
    (net (code "51") (name "Net-(A26-Pad1)") (class "Default")
      (node (ref "A26") (pin "1") (pinfunction "1_1") (pintype "passive"))
      (node (ref "A26") (pin "2") (pinfunction "2_2") (pintype "passive"))
      (node (ref "IC10") (pin "10") (pinfunction "10_10") (pintype "passive"))
    )
    (net (code "52") (name "Net-(A27-Pad1)") (class "Default")
      (node (ref "A27") (pin "1") (pinfunction "1_1") (pintype "passive"))
      (node (ref "A27") (pin "2") (pinfunction "2_2") (pintype "passive"))
      (node (ref "IC10") (pin "11") (pinfunction "11_11") (pintype "passive"))
    )
    (net (code "53") (name "Net-(A28-Pad1)") (class "Default")
      (node (ref "A28") (pin "1") (pinfunction "1_1") (pintype "passive"))
      (node (ref "A28") (pin "2") (pinfunction "2_2") (pintype "passive"))
      (node (ref "IC10") (pin "12") (pinfunction "12_12") (pintype "passive"))
    )
    (net (code "54") (name "Net-(A29-Pad1)") (class "Default")
      (node (ref "A29") (pin "1") (pinfunction "1_1") (pintype "passive"))
      (node (ref "A29") (pin "2") (pinfunction "2_2") (pintype "passive"))
      (node (ref "IC10") (pin "13") (pinfunction "13_13") (pintype "passive"))
    )
    (net (code "55") (name "Net-(A30-Pad1)") (class "Default")
      (node (ref "A30") (pin "1") (pinfunction "1_1") (pintype "passive"))
      (node (ref "A30") (pin "2") (pinfunction "2_2") (pintype "passive"))
      (node (ref "IC10") (pin "14") (pinfunction "14_14") (pintype "passive"))
    )
    (net (code "56") (name "Net-(A31-Pad1)") (class "Default")
      (node (ref "A31") (pin "1") (pinfunction "1_1") (pintype "passive"))
      (node (ref "A31") (pin "2") (pinfunction "2_2") (pintype "passive"))
      (node (ref "IC10") (pin "15") (pinfunction "15_15") (pintype "passive"))
    )
    (net (code "57") (name "Net-(A32-Pad1)") (class "Default")
      (node (ref "A32") (pin "1") (pinfunction "1_1") (pintype "passive"))
      (node (ref "A32") (pin "2") (pinfunction "2_2") (pintype "passive"))
      (node (ref "IC10") (pin "16") (pinfunction "16_16") (pintype "passive"))
    )
    (net (code "58") (name "Net-(A33-Pad1)") (class "Default")
      (node (ref "A33") (pin "1") (pinfunction "1_1") (pintype "passive"))
      (node (ref "A33") (pin "2") (pinfunction "2_2") (pintype "passive"))
      (node (ref "IC11") (pin "1") (pinfunction "1_1") (pintype "passive"))
    )
    (net (code "59") (name "Net-(A34-Pad1)") (class "Default")
      (node (ref "A34") (pin "1") (pinfunction "1_1") (pintype "passive"))
      (node (ref "A34") (pin "2") (pinfunction "2_2") (pintype "passive"))
      (node (ref "IC11") (pin "2") (pinfunction "2_2") (pintype "passive"))
    )
    (net (code "60") (name "Net-(A35-Pad1)") (class "Default")
      (node (ref "A35") (pin "1") (pinfunction "1_1") (pintype "passive"))
      (node (ref "A35") (pin "2") (pinfunction "2_2") (pintype "passive"))
      (node (ref "IC11") (pin "3") (pinfunction "3_3") (pintype "passive"))
    )
    (net (code "61") (name "Net-(A36-Pad1)") (class "Default")
      (node (ref "A36") (pin "1") (pinfunction "1_1") (pintype "passive"))
      (node (ref "A36") (pin "2") (pinfunction "2_2") (pintype "passive"))
      (node (ref "IC11") (pin "4") (pinfunction "4_4") (pintype "passive"))
    )
    (net (code "62") (name "Net-(A37-Pad1)") (class "Default")
      (node (ref "A37") (pin "1") (pinfunction "1_1") (pintype "passive"))
      (node (ref "A37") (pin "2") (pinfunction "2_2") (pintype "passive"))
      (node (ref "IC11") (pin "5") (pinfunction "5_5") (pintype "passive"))
    )
    (net (code "63") (name "Net-(A38-Pad1)") (class "Default")
      (node (ref "A38") (pin "1") (pinfunction "1_1") (pintype "passive"))
      (node (ref "A38") (pin "2") (pinfunction "2_2") (pintype "passive"))
      (node (ref "IC11") (pin "6") (pinfunction "6_6") (pintype "passive"))
    )
    (net (code "64") (name "Net-(A39-Pad1)") (class "Default")
      (node (ref "A39") (pin "1") (pinfunction "1_1") (pintype "passive"))
      (node (ref "A39") (pin "2") (pinfunction "2_2") (pintype "passive"))
      (node (ref "IC11") (pin "7") (pinfunction "7_7") (pintype "passive"))
    )
    (net (code "65") (name "Net-(A40-Pad1)") (class "Default")
      (node (ref "A40") (pin "1") (pinfunction "1_1") (pintype "passive"))
      (node (ref "A40") (pin "2") (pinfunction "2_2") (pintype "passive"))
      (node (ref "IC11") (pin "8") (pinfunction "8_8") (pintype "passive"))
    )
    (net (code "66") (name "Net-(A41-Pad1)") (class "Default")
      (node (ref "A41") (pin "1") (pinfunction "1_1") (pintype "passive"))
      (node (ref "A41") (pin "2") (pinfunction "2_2") (pintype "passive"))
      (node (ref "IC11") (pin "9") (pinfunction "9_9") (pintype "passive"))
    )
    (net (code "67") (name "Net-(A42-Pad1)") (class "Default")
      (node (ref "A42") (pin "1") (pinfunction "1_1") (pintype "passive"))
      (node (ref "A42") (pin "2") (pinfunction "2_2") (pintype "passive"))
      (node (ref "IC11") (pin "10") (pinfunction "10_10") (pintype "passive"))
    )
    (net (code "68") (name "Net-(A43-Pad1)") (class "Default")
      (node (ref "A43") (pin "1") (pinfunction "1_1") (pintype "passive"))
      (node (ref "A43") (pin "2") (pinfunction "2_2") (pintype "passive"))
      (node (ref "IC11") (pin "11") (pinfunction "11_11") (pintype "passive"))
    )
    (net (code "69") (name "Net-(A44-Pad1)") (class "Default")
      (node (ref "A44") (pin "1") (pinfunction "1_1") (pintype "passive"))
      (node (ref "A44") (pin "2") (pinfunction "2_2") (pintype "passive"))
      (node (ref "IC11") (pin "12") (pinfunction "12_12") (pintype "passive"))
    )
    (net (code "70") (name "Net-(A45-Pad1)") (class "Default")
      (node (ref "A45") (pin "1") (pinfunction "1_1") (pintype "passive"))
      (node (ref "A45") (pin "2") (pinfunction "2_2") (pintype "passive"))
      (node (ref "IC11") (pin "13") (pinfunction "13_13") (pintype "passive"))
    )
    (net (code "71") (name "Net-(A46-Pad1)") (class "Default")
      (node (ref "A46") (pin "1") (pinfunction "1_1") (pintype "passive"))
      (node (ref "A46") (pin "2") (pinfunction "2_2") (pintype "passive"))
      (node (ref "IC11") (pin "14") (pinfunction "14_14") (pintype "passive"))
    )
    (net (code "72") (name "Net-(A47-Pad1)") (class "Default")
      (node (ref "A47") (pin "1") (pinfunction "1_1") (pintype "passive"))
      (node (ref "A47") (pin "2") (pinfunction "2_2") (pintype "passive"))
      (node (ref "IC11") (pin "15") (pinfunction "15_15") (pintype "passive"))
    )
    (net (code "73") (name "Net-(A48-Pad1)") (class "Default")
      (node (ref "A48") (pin "1") (pinfunction "1_1") (pintype "passive"))
      (node (ref "A48") (pin "2") (pinfunction "2_2") (pintype "passive"))
      (node (ref "IC11") (pin "16") (pinfunction "16_16") (pintype "passive"))
    )
    (net (code "74") (name "Net-(A49-Pad1)") (class "Default")
      (node (ref "A49") (pin "1") (pinfunction "1_1") (pintype "passive"))
      (node (ref "A49") (pin "2") (pinfunction "2_2") (pintype "passive"))
      (node (ref "IC12") (pin "1") (pinfunction "1_1") (pintype "passive"))
    )
    (net (code "75") (name "Net-(A50-Pad1)") (class "Default")
      (node (ref "A50") (pin "1") (pinfunction "1_1") (pintype "passive"))
      (node (ref "A50") (pin "2") (pinfunction "2_2") (pintype "passive"))
      (node (ref "IC12") (pin "2") (pinfunction "2_2") (pintype "passive"))
    )
    (net (code "76") (name "Net-(A51-Pad1)") (class "Default")
      (node (ref "A51") (pin "1") (pinfunction "1_1") (pintype "passive"))
      (node (ref "A51") (pin "2") (pinfunction "2_2") (pintype "passive"))
      (node (ref "IC12") (pin "3") (pinfunction "3_3") (pintype "passive"))
    )
    (net (code "77") (name "Net-(A52-Pad1)") (class "Default")
      (node (ref "A52") (pin "1") (pinfunction "1_1") (pintype "passive"))
      (node (ref "A52") (pin "2") (pinfunction "2_2") (pintype "passive"))
      (node (ref "IC12") (pin "4") (pinfunction "4_4") (pintype "passive"))
    )
    (net (code "78") (name "Net-(A53-Pad1)") (class "Default")
      (node (ref "A53") (pin "1") (pinfunction "1_1") (pintype "passive"))
      (node (ref "A53") (pin "2") (pinfunction "2_2") (pintype "passive"))
      (node (ref "IC12") (pin "5") (pinfunction "5_5") (pintype "passive"))
    )
    (net (code "79") (name "Net-(A54-Pad1)") (class "Default")
      (node (ref "A54") (pin "1") (pinfunction "1_1") (pintype "passive"))
      (node (ref "A54") (pin "2") (pinfunction "2_2") (pintype "passive"))
      (node (ref "IC12") (pin "6") (pinfunction "6_6") (pintype "passive"))
    )
    (net (code "80") (name "Net-(A55-Pad1)") (class "Default")
      (node (ref "A55") (pin "1") (pinfunction "1_1") (pintype "passive"))
      (node (ref "A55") (pin "2") (pinfunction "2_2") (pintype "passive"))
      (node (ref "IC12") (pin "7") (pinfunction "7_7") (pintype "passive"))
    )
    (net (code "81") (name "Net-(A56-Pad1)") (class "Default")
      (node (ref "A56") (pin "1") (pinfunction "1_1") (pintype "passive"))
      (node (ref "A56") (pin "2") (pinfunction "2_2") (pintype "passive"))
      (node (ref "IC12") (pin "8") (pinfunction "8_8") (pintype "passive"))
    )
    (net (code "82") (name "Net-(A57-Pad1)") (class "Default")
      (node (ref "A57") (pin "1") (pinfunction "1_1") (pintype "passive"))
      (node (ref "A57") (pin "2") (pinfunction "2_2") (pintype "passive"))
      (node (ref "IC12") (pin "9") (pinfunction "9_9") (pintype "passive"))
    )
    (net (code "83") (name "Net-(A58-Pad1)") (class "Default")
      (node (ref "A58") (pin "1") (pinfunction "1_1") (pintype "passive"))
      (node (ref "A58") (pin "2") (pinfunction "2_2") (pintype "passive"))
      (node (ref "IC12") (pin "10") (pinfunction "10_10") (pintype "passive"))
    )
    (net (code "84") (name "Net-(A59-Pad1)") (class "Default")
      (node (ref "A59") (pin "1") (pinfunction "1_1") (pintype "passive"))
      (node (ref "A59") (pin "2") (pinfunction "2_2") (pintype "passive"))
      (node (ref "IC12") (pin "11") (pinfunction "11_11") (pintype "passive"))
    )
    (net (code "85") (name "Net-(A60-Pad1)") (class "Default")
      (node (ref "A60") (pin "1") (pinfunction "1_1") (pintype "passive"))
      (node (ref "A60") (pin "2") (pinfunction "2_2") (pintype "passive"))
      (node (ref "IC12") (pin "12") (pinfunction "12_12") (pintype "passive"))
    )
    (net (code "86") (name "Net-(A61-Pad1)") (class "Default")
      (node (ref "A61") (pin "1") (pinfunction "1_1") (pintype "passive"))
      (node (ref "A61") (pin "2") (pinfunction "2_2") (pintype "passive"))
      (node (ref "IC12") (pin "13") (pinfunction "13_13") (pintype "passive"))
    )
    (net (code "87") (name "Net-(A62-Pad1)") (class "Default")
      (node (ref "A62") (pin "1") (pinfunction "1_1") (pintype "passive"))
      (node (ref "A62") (pin "2") (pinfunction "2_2") (pintype "passive"))
      (node (ref "IC12") (pin "14") (pinfunction "14_14") (pintype "passive"))
    )
    (net (code "88") (name "Net-(A63-Pad1)") (class "Default")
      (node (ref "A63") (pin "1") (pinfunction "1_1") (pintype "passive"))
      (node (ref "A63") (pin "2") (pinfunction "2_2") (pintype "passive"))
      (node (ref "IC12") (pin "15") (pinfunction "15_15") (pintype "passive"))
    )
    (net (code "89") (name "Net-(A64-Pad1)") (class "Default")
      (node (ref "A64") (pin "1") (pinfunction "1_1") (pintype "passive"))
      (node (ref "A64") (pin "2") (pinfunction "2_2") (pintype "passive"))
      (node (ref "IC12") (pin "16") (pinfunction "16_16") (pintype "passive"))
    )
    (net (code "90") (name "Net-(A65-Pad1)") (class "Default")
      (node (ref "A65") (pin "1") (pinfunction "1_1") (pintype "passive"))
      (node (ref "A65") (pin "2") (pinfunction "2_2") (pintype "passive"))
      (node (ref "IC13") (pin "1") (pinfunction "1_1") (pintype "passive"))
    )
    (net (code "91") (name "Net-(A66-Pad1)") (class "Default")
      (node (ref "A66") (pin "1") (pinfunction "1_1") (pintype "passive"))
      (node (ref "A66") (pin "2") (pinfunction "2_2") (pintype "passive"))
      (node (ref "IC13") (pin "2") (pinfunction "2_2") (pintype "passive"))
    )
    (net (code "92") (name "Net-(A67-Pad1)") (class "Default")
      (node (ref "A67") (pin "1") (pinfunction "1_1") (pintype "passive"))
      (node (ref "A67") (pin "2") (pinfunction "2_2") (pintype "passive"))
      (node (ref "IC13") (pin "3") (pinfunction "3_3") (pintype "passive"))
    )
    (net (code "93") (name "Net-(A68-Pad1)") (class "Default")
      (node (ref "A68") (pin "1") (pinfunction "1_1") (pintype "passive"))
      (node (ref "A68") (pin "2") (pinfunction "2_2") (pintype "passive"))
      (node (ref "IC13") (pin "4") (pinfunction "4_4") (pintype "passive"))
    )
    (net (code "94") (name "Net-(A69-Pad1)") (class "Default")
      (node (ref "A69") (pin "1") (pinfunction "1_1") (pintype "passive"))
      (node (ref "A69") (pin "2") (pinfunction "2_2") (pintype "passive"))
      (node (ref "IC13") (pin "5") (pinfunction "5_5") (pintype "passive"))
    )
    (net (code "95") (name "Net-(A70-Pad1)") (class "Default")
      (node (ref "A70") (pin "1") (pinfunction "1_1") (pintype "passive"))
      (node (ref "A70") (pin "2") (pinfunction "2_2") (pintype "passive"))
      (node (ref "IC13") (pin "6") (pinfunction "6_6") (pintype "passive"))
    )
    (net (code "96") (name "Net-(A71-Pad1)") (class "Default")
      (node (ref "A71") (pin "1") (pinfunction "1_1") (pintype "passive"))
      (node (ref "A71") (pin "2") (pinfunction "2_2") (pintype "passive"))
      (node (ref "IC13") (pin "7") (pinfunction "7_7") (pintype "passive"))
    )
    (net (code "97") (name "Net-(A72-Pad1)") (class "Default")
      (node (ref "A72") (pin "1") (pinfunction "1_1") (pintype "passive"))
      (node (ref "A72") (pin "2") (pinfunction "2_2") (pintype "passive"))
      (node (ref "IC13") (pin "8") (pinfunction "8_8") (pintype "passive"))
    )
    (net (code "98") (name "Net-(A73-Pad1)") (class "Default")
      (node (ref "A73") (pin "1") (pinfunction "1_1") (pintype "passive"))
      (node (ref "A73") (pin "2") (pinfunction "2_2") (pintype "passive"))
      (node (ref "IC13") (pin "9") (pinfunction "9_9") (pintype "passive"))
    )
    (net (code "99") (name "Net-(A74-Pad1)") (class "Default")
      (node (ref "A74") (pin "1") (pinfunction "1_1") (pintype "passive"))
      (node (ref "A74") (pin "2") (pinfunction "2_2") (pintype "passive"))
      (node (ref "IC13") (pin "10") (pinfunction "10_10") (pintype "passive"))
    )
    (net (code "100") (name "Net-(A75-Pad1)") (class "Default")
      (node (ref "A75") (pin "1") (pinfunction "1_1") (pintype "passive"))
      (node (ref "A75") (pin "2") (pinfunction "2_2") (pintype "passive"))
      (node (ref "IC13") (pin "11") (pinfunction "11_11") (pintype "passive"))
    )
    (net (code "101") (name "Net-(A76-Pad1)") (class "Default")
      (node (ref "A76") (pin "1") (pinfunction "1_1") (pintype "passive"))
      (node (ref "A76") (pin "2") (pinfunction "2_2") (pintype "passive"))
      (node (ref "IC13") (pin "12") (pinfunction "12_12") (pintype "passive"))
    )
    (net (code "102") (name "Net-(A77-Pad1)") (class "Default")
      (node (ref "A77") (pin "1") (pinfunction "1_1") (pintype "passive"))
      (node (ref "A77") (pin "2") (pinfunction "2_2") (pintype "passive"))
      (node (ref "IC13") (pin "13") (pinfunction "13_13") (pintype "passive"))
    )
    (net (code "103") (name "Net-(A78-Pad1)") (class "Default")
      (node (ref "A78") (pin "1") (pinfunction "1_1") (pintype "passive"))
      (node (ref "A78") (pin "2") (pinfunction "2_2") (pintype "passive"))
      (node (ref "IC13") (pin "14") (pinfunction "14_14") (pintype "passive"))
    )
    (net (code "104") (name "Net-(A79-Pad1)") (class "Default")
      (node (ref "A79") (pin "1") (pinfunction "1_1") (pintype "passive"))
      (node (ref "A79") (pin "2") (pinfunction "2_2") (pintype "passive"))
      (node (ref "IC13") (pin "15") (pinfunction "15_15") (pintype "passive"))
    )
    (net (code "105") (name "Net-(A80-Pad1)") (class "Default")
      (node (ref "A80") (pin "1") (pinfunction "1_1") (pintype "passive"))
      (node (ref "A80") (pin "2") (pinfunction "2_2") (pintype "passive"))
      (node (ref "IC13") (pin "16") (pinfunction "16_16") (pintype "passive"))
    )
    (net (code "106") (name "Net-(A81-Pad1)") (class "Default")
      (node (ref "A81") (pin "1") (pinfunction "1_1") (pintype "passive"))
      (node (ref "A81") (pin "2") (pinfunction "2_2") (pintype "passive"))
      (node (ref "IC14") (pin "1") (pinfunction "1_1") (pintype "passive"))
    )
    (net (code "107") (name "Net-(A82-Pad1)") (class "Default")
      (node (ref "A82") (pin "1") (pinfunction "1_1") (pintype "passive"))
      (node (ref "A82") (pin "2") (pinfunction "2_2") (pintype "passive"))
      (node (ref "IC14") (pin "2") (pinfunction "2_2") (pintype "passive"))
    )
    (net (code "108") (name "Net-(A83-Pad1)") (class "Default")
      (node (ref "A83") (pin "1") (pinfunction "1_1") (pintype "passive"))
      (node (ref "A83") (pin "2") (pinfunction "2_2") (pintype "passive"))
      (node (ref "IC14") (pin "3") (pinfunction "3_3") (pintype "passive"))
    )
    (net (code "109") (name "Net-(A84-Pad1)") (class "Default")
      (node (ref "A84") (pin "1") (pinfunction "1_1") (pintype "passive"))
      (node (ref "A84") (pin "2") (pinfunction "2_2") (pintype "passive"))
      (node (ref "IC14") (pin "4") (pinfunction "4_4") (pintype "passive"))
    )
    (net (code "110") (name "Net-(A85-Pad1)") (class "Default")
      (node (ref "A85") (pin "1") (pinfunction "1_1") (pintype "passive"))
      (node (ref "A85") (pin "2") (pinfunction "2_2") (pintype "passive"))
      (node (ref "IC14") (pin "5") (pinfunction "5_5") (pintype "passive"))
    )
    (net (code "111") (name "Net-(A86-Pad1)") (class "Default")
      (node (ref "A86") (pin "1") (pinfunction "1_1") (pintype "passive"))
      (node (ref "A86") (pin "2") (pinfunction "2_2") (pintype "passive"))
      (node (ref "IC14") (pin "6") (pinfunction "6_6") (pintype "passive"))
    )
    (net (code "112") (name "Net-(A87-Pad1)") (class "Default")
      (node (ref "A87") (pin "1") (pinfunction "1_1") (pintype "passive"))
      (node (ref "A87") (pin "2") (pinfunction "2_2") (pintype "passive"))
      (node (ref "IC14") (pin "7") (pinfunction "7_7") (pintype "passive"))
    )
    (net (code "113") (name "Net-(A88-Pad1)") (class "Default")
      (node (ref "A88") (pin "1") (pinfunction "1_1") (pintype "passive"))
      (node (ref "A88") (pin "2") (pinfunction "2_2") (pintype "passive"))
      (node (ref "IC14") (pin "8") (pinfunction "8_8") (pintype "passive"))
    )
    (net (code "114") (name "Net-(A89-Pad1)") (class "Default")
      (node (ref "A89") (pin "1") (pinfunction "1_1") (pintype "passive"))
      (node (ref "A89") (pin "2") (pinfunction "2_2") (pintype "passive"))
      (node (ref "IC14") (pin "9") (pinfunction "9_9") (pintype "passive"))
    )
    (net (code "115") (name "Net-(A90-Pad1)") (class "Default")
      (node (ref "A90") (pin "1") (pinfunction "1_1") (pintype "passive"))
      (node (ref "A90") (pin "2") (pinfunction "2_2") (pintype "passive"))
      (node (ref "IC14") (pin "10") (pinfunction "10_10") (pintype "passive"))
    )
    (net (code "116") (name "Net-(A91-Pad1)") (class "Default")
      (node (ref "A91") (pin "1") (pinfunction "1_1") (pintype "passive"))
      (node (ref "A91") (pin "2") (pinfunction "2_2") (pintype "passive"))
      (node (ref "IC14") (pin "11") (pinfunction "11_11") (pintype "passive"))
    )
    (net (code "117") (name "Net-(A92-Pad1)") (class "Default")
      (node (ref "A92") (pin "1") (pinfunction "1_1") (pintype "passive"))
      (node (ref "A92") (pin "2") (pinfunction "2_2") (pintype "passive"))
      (node (ref "IC14") (pin "12") (pinfunction "12_12") (pintype "passive"))
    )
    (net (code "118") (name "Net-(A93-Pad1)") (class "Default")
      (node (ref "A93") (pin "1") (pinfunction "1_1") (pintype "passive"))
      (node (ref "A93") (pin "2") (pinfunction "2_2") (pintype "passive"))
      (node (ref "IC14") (pin "13") (pinfunction "13_13") (pintype "passive"))
    )
    (net (code "119") (name "Net-(A94-Pad1)") (class "Default")
      (node (ref "A94") (pin "1") (pinfunction "1_1") (pintype "passive"))
      (node (ref "A94") (pin "2") (pinfunction "2_2") (pintype "passive"))
      (node (ref "IC14") (pin "14") (pinfunction "14_14") (pintype "passive"))
    )
    (net (code "120") (name "Net-(A95-Pad1)") (class "Default")
      (node (ref "A95") (pin "1") (pinfunction "1_1") (pintype "passive"))
      (node (ref "A95") (pin "2") (pinfunction "2_2") (pintype "passive"))
      (node (ref "IC14") (pin "15") (pinfunction "15_15") (pintype "passive"))
    )
    (net (code "121") (name "Net-(A96-Pad1)") (class "Default")
      (node (ref "A96") (pin "1") (pinfunction "1_1") (pintype "passive"))
      (node (ref "A96") (pin "2") (pinfunction "2_2") (pintype "passive"))
      (node (ref "IC14") (pin "16") (pinfunction "16_16") (pintype "passive"))
    )
    (net (code "122") (name "Net-(A97-Pad1)") (class "Default")
      (node (ref "A97") (pin "1") (pinfunction "1_1") (pintype "passive"))
      (node (ref "A97") (pin "2") (pinfunction "2_2") (pintype "passive"))
      (node (ref "IC15") (pin "1") (pinfunction "1_1") (pintype "passive"))
    )
    (net (code "123") (name "Net-(A98-Pad1)") (class "Default")
      (node (ref "A98") (pin "1") (pinfunction "1_1") (pintype "passive"))
      (node (ref "A98") (pin "2") (pinfunction "2_2") (pintype "passive"))
      (node (ref "IC15") (pin "2") (pinfunction "2_2") (pintype "passive"))
    )
    (net (code "124") (name "Net-(A99-Pad1)") (class "Default")
      (node (ref "A99") (pin "1") (pinfunction "1_1") (pintype "passive"))
      (node (ref "A99") (pin "2") (pinfunction "2_2") (pintype "passive"))
      (node (ref "IC15") (pin "3") (pinfunction "3_3") (pintype "passive"))
    )
    (net (code "125") (name "Net-(A100-Pad1)") (class "Default")
      (node (ref "A100") (pin "1") (pinfunction "1_1") (pintype "passive"))
      (node (ref "A100") (pin "2") (pinfunction "2_2") (pintype "passive"))
      (node (ref "IC15") (pin "4") (pinfunction "4_4") (pintype "passive"))
    )
    (net (code "126") (name "Net-(A101-Pad1)") (class "Default")
      (node (ref "A101") (pin "1") (pinfunction "1_1") (pintype "passive"))
      (node (ref "A101") (pin "2") (pinfunction "2_2") (pintype "passive"))
      (node (ref "IC15") (pin "5") (pinfunction "5_5") (pintype "passive"))
    )
    (net (code "127") (name "Net-(A102-Pad1)") (class "Default")
      (node (ref "A102") (pin "1") (pinfunction "1_1") (pintype "passive"))
      (node (ref "A102") (pin "2") (pinfunction "2_2") (pintype "passive"))
      (node (ref "IC15") (pin "6") (pinfunction "6_6") (pintype "passive"))
    )
    (net (code "128") (name "Net-(A103-Pad1)") (class "Default")
      (node (ref "A103") (pin "1") (pinfunction "1_1") (pintype "passive"))
      (node (ref "A103") (pin "2") (pinfunction "2_2") (pintype "passive"))
      (node (ref "IC15") (pin "7") (pinfunction "7_7") (pintype "passive"))
    )
    (net (code "129") (name "Net-(A104-Pad1)") (class "Default")
      (node (ref "A104") (pin "1") (pinfunction "1_1") (pintype "passive"))
      (node (ref "A104") (pin "2") (pinfunction "2_2") (pintype "passive"))
      (node (ref "IC15") (pin "8") (pinfunction "8_8") (pintype "passive"))
    )
    (net (code "130") (name "Net-(A105-Pad1)") (class "Default")
      (node (ref "A105") (pin "1") (pinfunction "1_1") (pintype "passive"))
      (node (ref "A105") (pin "2") (pinfunction "2_2") (pintype "passive"))
      (node (ref "IC15") (pin "9") (pinfunction "9_9") (pintype "passive"))
    )
    (net (code "131") (name "Net-(A106-Pad1)") (class "Default")
      (node (ref "A106") (pin "1") (pinfunction "1_1") (pintype "passive"))
      (node (ref "A106") (pin "2") (pinfunction "2_2") (pintype "passive"))
      (node (ref "IC15") (pin "10") (pinfunction "10_10") (pintype "passive"))
    )
    (net (code "132") (name "Net-(A107-Pad1)") (class "Default")
      (node (ref "A107") (pin "1") (pinfunction "1_1") (pintype "passive"))
      (node (ref "A107") (pin "2") (pinfunction "2_2") (pintype "passive"))
      (node (ref "IC15") (pin "11") (pinfunction "11_11") (pintype "passive"))
    )
    (net (code "133") (name "Net-(A108-Pad1)") (class "Default")
      (node (ref "A108") (pin "1") (pinfunction "1_1") (pintype "passive"))
      (node (ref "A108") (pin "2") (pinfunction "2_2") (pintype "passive"))
      (node (ref "IC15") (pin "12") (pinfunction "12_12") (pintype "passive"))
    )
    (net (code "134") (name "Net-(A109-Pad1)") (class "Default")
      (node (ref "A109") (pin "1") (pinfunction "1_1") (pintype "passive"))
      (node (ref "A109") (pin "2") (pinfunction "2_2") (pintype "passive"))
      (node (ref "IC15") (pin "13") (pinfunction "13_13") (pintype "passive"))
    )
    (net (code "135") (name "Net-(A110-Pad1)") (class "Default")
      (node (ref "A110") (pin "1") (pinfunction "1_1") (pintype "passive"))
      (node (ref "A110") (pin "2") (pinfunction "2_2") (pintype "passive"))
      (node (ref "IC15") (pin "14") (pinfunction "14_14") (pintype "passive"))
    )
    (net (code "136") (name "Net-(A111-Pad1)") (class "Default")
      (node (ref "A111") (pin "1") (pinfunction "1_1") (pintype "passive"))
      (node (ref "A111") (pin "2") (pinfunction "2_2") (pintype "passive"))
      (node (ref "IC15") (pin "15") (pinfunction "15_15") (pintype "passive"))
    )
    (net (code "137") (name "Net-(A112-Pad1)") (class "Default")
      (node (ref "A112") (pin "1") (pinfunction "1_1") (pintype "passive"))
      (node (ref "A112") (pin "2") (pinfunction "2_2") (pintype "passive"))
      (node (ref "IC15") (pin "16") (pinfunction "16_16") (pintype "passive"))
    )
    (net (code "138") (name "Net-(A113-Pad1)") (class "Default")
      (node (ref "A113") (pin "1") (pinfunction "1_1") (pintype "passive"))
      (node (ref "A113") (pin "2") (pinfunction "2_2") (pintype "passive"))
      (node (ref "IC16") (pin "1") (pinfunction "1_1") (pintype "passive"))
    )
    (net (code "139") (name "Net-(A114-Pad1)") (class "Default")
      (node (ref "A114") (pin "1") (pinfunction "1_1") (pintype "passive"))
      (node (ref "A114") (pin "2") (pinfunction "2_2") (pintype "passive"))
      (node (ref "IC16") (pin "2") (pinfunction "2_2") (pintype "passive"))
    )
    (net (code "140") (name "Net-(A115-Pad1)") (class "Default")
      (node (ref "A115") (pin "1") (pinfunction "1_1") (pintype "passive"))
      (node (ref "A115") (pin "2") (pinfunction "2_2") (pintype "passive"))
      (node (ref "IC16") (pin "3") (pinfunction "3_3") (pintype "passive"))
    )
    (net (code "141") (name "Net-(A116-Pad1)") (class "Default")
      (node (ref "A116") (pin "1") (pinfunction "1_1") (pintype "passive"))
      (node (ref "A116") (pin "2") (pinfunction "2_2") (pintype "passive"))
      (node (ref "IC16") (pin "4") (pinfunction "4_4") (pintype "passive"))
    )
    (net (code "142") (name "Net-(A117-Pad1)") (class "Default")
      (node (ref "A117") (pin "1") (pinfunction "1_1") (pintype "passive"))
      (node (ref "A117") (pin "2") (pinfunction "2_2") (pintype "passive"))
      (node (ref "IC16") (pin "5") (pinfunction "5_5") (pintype "passive"))
    )
    (net (code "143") (name "Net-(A118-Pad1)") (class "Default")
      (node (ref "A118") (pin "1") (pinfunction "1_1") (pintype "passive"))
      (node (ref "A118") (pin "2") (pinfunction "2_2") (pintype "passive"))
      (node (ref "IC16") (pin "6") (pinfunction "6_6") (pintype "passive"))
    )
    (net (code "144") (name "Net-(A119-Pad1)") (class "Default")
      (node (ref "A119") (pin "1") (pinfunction "1_1") (pintype "passive"))
      (node (ref "A119") (pin "2") (pinfunction "2_2") (pintype "passive"))
      (node (ref "IC16") (pin "7") (pinfunction "7_7") (pintype "passive"))
    )
    (net (code "145") (name "Net-(A120-Pad1)") (class "Default")
      (node (ref "A120") (pin "1") (pinfunction "1_1") (pintype "passive"))
      (node (ref "A120") (pin "2") (pinfunction "2_2") (pintype "passive"))
      (node (ref "IC16") (pin "8") (pinfunction "8_8") (pintype "passive"))
    )
    (net (code "146") (name "Net-(A121-Pad1)") (class "Default")
      (node (ref "A121") (pin "1") (pinfunction "1_1") (pintype "passive"))
      (node (ref "A121") (pin "2") (pinfunction "2_2") (pintype "passive"))
      (node (ref "IC16") (pin "9") (pinfunction "9_9") (pintype "passive"))
    )
    (net (code "147") (name "Net-(A122-Pad1)") (class "Default")
      (node (ref "A122") (pin "1") (pinfunction "1_1") (pintype "passive"))
      (node (ref "A122") (pin "2") (pinfunction "2_2") (pintype "passive"))
      (node (ref "IC16") (pin "10") (pinfunction "10_10") (pintype "passive"))
    )
    (net (code "148") (name "Net-(A123-Pad1)") (class "Default")
      (node (ref "A123") (pin "1") (pinfunction "1_1") (pintype "passive"))
      (node (ref "A123") (pin "2") (pinfunction "2_2") (pintype "passive"))
      (node (ref "IC16") (pin "11") (pinfunction "11_11") (pintype "passive"))
    )
    (net (code "149") (name "Net-(A124-Pad1)") (class "Default")
      (node (ref "A124") (pin "1") (pinfunction "1_1") (pintype "passive"))
      (node (ref "A124") (pin "2") (pinfunction "2_2") (pintype "passive"))
      (node (ref "IC16") (pin "12") (pinfunction "12_12") (pintype "passive"))
    )
    (net (code "150") (name "Net-(A125-Pad1)") (class "Default")
      (node (ref "A125") (pin "1") (pinfunction "1_1") (pintype "passive"))
      (node (ref "A125") (pin "2") (pinfunction "2_2") (pintype "passive"))
      (node (ref "IC16") (pin "13") (pinfunction "13_13") (pintype "passive"))
    )
    (net (code "151") (name "Net-(A126-Pad1)") (class "Default")
      (node (ref "A126") (pin "1") (pinfunction "1_1") (pintype "passive"))
      (node (ref "A126") (pin "2") (pinfunction "2_2") (pintype "passive"))
      (node (ref "IC16") (pin "14") (pinfunction "14_14") (pintype "passive"))
    )
    (net (code "152") (name "Net-(A127-Pad1)") (class "Default")
      (node (ref "A127") (pin "1") (pinfunction "1_1") (pintype "passive"))
      (node (ref "A127") (pin "2") (pinfunction "2_2") (pintype "passive"))
      (node (ref "IC16") (pin "15") (pinfunction "15_15") (pintype "passive"))
    )
    (net (code "153") (name "Net-(A128-Pad1)") (class "Default")
      (node (ref "A128") (pin "1") (pinfunction "1_1") (pintype "passive"))
      (node (ref "A128") (pin "2") (pinfunction "2_2") (pintype "passive"))
      (node (ref "IC16") (pin "16") (pinfunction "16_16") (pintype "passive"))
    )
    (net (code "154") (name "Net-(A129-Pad1)") (class "Default")
      (node (ref "A129") (pin "1") (pinfunction "1_1") (pintype "passive"))
      (node (ref "A129") (pin "2") (pinfunction "2_2") (pintype "passive"))
      (node (ref "IC17") (pin "1") (pinfunction "1_1") (pintype "passive"))
    )
    (net (code "155") (name "Net-(A130-Pad1)") (class "Default")
      (node (ref "A130") (pin "1") (pinfunction "1_1") (pintype "passive"))
      (node (ref "A130") (pin "2") (pinfunction "2_2") (pintype "passive"))
      (node (ref "IC17") (pin "2") (pinfunction "2_2") (pintype "passive"))
    )
    (net (code "156") (name "Net-(A131-Pad1)") (class "Default")
      (node (ref "A131") (pin "1") (pinfunction "1_1") (pintype "passive"))
      (node (ref "A131") (pin "2") (pinfunction "2_2") (pintype "passive"))
      (node (ref "IC17") (pin "3") (pinfunction "3_3") (pintype "passive"))
    )
    (net (code "157") (name "Net-(A132-Pad1)") (class "Default")
      (node (ref "A132") (pin "1") (pinfunction "1_1") (pintype "passive"))
      (node (ref "A132") (pin "2") (pinfunction "2_2") (pintype "passive"))
      (node (ref "IC17") (pin "4") (pinfunction "4_4") (pintype "passive"))
    )
    (net (code "158") (name "Net-(A133-Pad1)") (class "Default")
      (node (ref "A133") (pin "1") (pinfunction "1_1") (pintype "passive"))
      (node (ref "A133") (pin "2") (pinfunction "2_2") (pintype "passive"))
      (node (ref "IC17") (pin "5") (pinfunction "5_5") (pintype "passive"))
    )
    (net (code "159") (name "Net-(A134-Pad1)") (class "Default")
      (node (ref "A134") (pin "1") (pinfunction "1_1") (pintype "passive"))
      (node (ref "A134") (pin "2") (pinfunction "2_2") (pintype "passive"))
      (node (ref "IC17") (pin "6") (pinfunction "6_6") (pintype "passive"))
    )
    (net (code "160") (name "Net-(A135-Pad1)") (class "Default")
      (node (ref "A135") (pin "1") (pinfunction "1_1") (pintype "passive"))
      (node (ref "A135") (pin "2") (pinfunction "2_2") (pintype "passive"))
      (node (ref "IC17") (pin "7") (pinfunction "7_7") (pintype "passive"))
    )
    (net (code "161") (name "Net-(A136-Pad1)") (class "Default")
      (node (ref "A136") (pin "1") (pinfunction "1_1") (pintype "passive"))
      (node (ref "A136") (pin "2") (pinfunction "2_2") (pintype "passive"))
      (node (ref "IC17") (pin "8") (pinfunction "8_8") (pintype "passive"))
    )
    (net (code "162") (name "Net-(A137-Pad1)") (class "Default")
      (node (ref "A137") (pin "1") (pinfunction "1_1") (pintype "passive"))
      (node (ref "A137") (pin "2") (pinfunction "2_2") (pintype "passive"))
      (node (ref "IC17") (pin "9") (pinfunction "9_9") (pintype "passive"))
    )
    (net (code "163") (name "Net-(A138-Pad1)") (class "Default")
      (node (ref "A138") (pin "1") (pinfunction "1_1") (pintype "passive"))
      (node (ref "A138") (pin "2") (pinfunction "2_2") (pintype "passive"))
      (node (ref "IC17") (pin "10") (pinfunction "10_10") (pintype "passive"))
    )
    (net (code "164") (name "Net-(A139-Pad1)") (class "Default")
      (node (ref "A139") (pin "1") (pinfunction "1_1") (pintype "passive"))
      (node (ref "A139") (pin "2") (pinfunction "2_2") (pintype "passive"))
      (node (ref "IC17") (pin "11") (pinfunction "11_11") (pintype "passive"))
    )
    (net (code "165") (name "Net-(A140-Pad1)") (class "Default")
      (node (ref "A140") (pin "1") (pinfunction "1_1") (pintype "passive"))
      (node (ref "A140") (pin "2") (pinfunction "2_2") (pintype "passive"))
      (node (ref "IC17") (pin "12") (pinfunction "12_12") (pintype "passive"))
    )
    (net (code "166") (name "Net-(A141-Pad1)") (class "Default")
      (node (ref "A141") (pin "1") (pinfunction "1_1") (pintype "passive"))
      (node (ref "A141") (pin "2") (pinfunction "2_2") (pintype "passive"))
      (node (ref "IC17") (pin "13") (pinfunction "13_13") (pintype "passive"))
    )
    (net (code "167") (name "Net-(A142-Pad1)") (class "Default")
      (node (ref "A142") (pin "1") (pinfunction "1_1") (pintype "passive"))
      (node (ref "A142") (pin "2") (pinfunction "2_2") (pintype "passive"))
      (node (ref "IC17") (pin "14") (pinfunction "14_14") (pintype "passive"))
    )
    (net (code "168") (name "Net-(A143-Pad1)") (class "Default")
      (node (ref "A143") (pin "1") (pinfunction "1_1") (pintype "passive"))
      (node (ref "A143") (pin "2") (pinfunction "2_2") (pintype "passive"))
      (node (ref "IC17") (pin "15") (pinfunction "15_15") (pintype "passive"))
    )
    (net (code "169") (name "Net-(A144-Pad1)") (class "Default")
      (node (ref "A144") (pin "1") (pinfunction "1_1") (pintype "passive"))
      (node (ref "A144") (pin "2") (pinfunction "2_2") (pintype "passive"))
      (node (ref "IC17") (pin "16") (pinfunction "16_16") (pintype "passive"))
    )
    (net (code "170") (name "Net-(A145-Pad1)") (class "Default")
      (node (ref "A145") (pin "1") (pinfunction "1_1") (pintype "passive"))
      (node (ref "A145") (pin "2") (pinfunction "2_2") (pintype "passive"))
      (node (ref "IC18") (pin "1") (pinfunction "1_1") (pintype "passive"))
    )
    (net (code "171") (name "Net-(A146-Pad1)") (class "Default")
      (node (ref "A146") (pin "1") (pinfunction "1_1") (pintype "passive"))
      (node (ref "A146") (pin "2") (pinfunction "2_2") (pintype "passive"))
      (node (ref "IC18") (pin "2") (pinfunction "2_2") (pintype "passive"))
    )
    (net (code "172") (name "Net-(A147-Pad1)") (class "Default")
      (node (ref "A147") (pin "1") (pinfunction "1_1") (pintype "passive"))
      (node (ref "A147") (pin "2") (pinfunction "2_2") (pintype "passive"))
      (node (ref "IC18") (pin "3") (pinfunction "3_3") (pintype "passive"))
    )
    (net (code "173") (name "Net-(A148-Pad1)") (class "Default")
      (node (ref "A148") (pin "1") (pinfunction "1_1") (pintype "passive"))
      (node (ref "A148") (pin "2") (pinfunction "2_2") (pintype "passive"))
      (node (ref "IC18") (pin "4") (pinfunction "4_4") (pintype "passive"))
    )
    (net (code "174") (name "Net-(A149-Pad1)") (class "Default")
      (node (ref "A149") (pin "1") (pinfunction "1_1") (pintype "passive"))
      (node (ref "A149") (pin "2") (pinfunction "2_2") (pintype "passive"))
      (node (ref "IC18") (pin "5") (pinfunction "5_5") (pintype "passive"))
    )
    (net (code "175") (name "Net-(A150-Pad1)") (class "Default")
      (node (ref "A150") (pin "1") (pinfunction "1_1") (pintype "passive"))
      (node (ref "A150") (pin "2") (pinfunction "2_2") (pintype "passive"))
      (node (ref "IC18") (pin "6") (pinfunction "6_6") (pintype "passive"))
    )
    (net (code "176") (name "Net-(A151-Pad1)") (class "Default")
      (node (ref "A151") (pin "1") (pinfunction "1_1") (pintype "passive"))
      (node (ref "A151") (pin "2") (pinfunction "2_2") (pintype "passive"))
      (node (ref "IC18") (pin "7") (pinfunction "7_7") (pintype "passive"))
    )
    (net (code "177") (name "Net-(A152-Pad1)") (class "Default")
      (node (ref "A152") (pin "1") (pinfunction "1_1") (pintype "passive"))
      (node (ref "A152") (pin "2") (pinfunction "2_2") (pintype "passive"))
      (node (ref "IC18") (pin "8") (pinfunction "8_8") (pintype "passive"))
    )
    (net (code "178") (name "Net-(A153-Pad1)") (class "Default")
      (node (ref "A153") (pin "1") (pinfunction "1_1") (pintype "passive"))
      (node (ref "A153") (pin "2") (pinfunction "2_2") (pintype "passive"))
      (node (ref "IC18") (pin "9") (pinfunction "9_9") (pintype "passive"))
    )
    (net (code "179") (name "Net-(A154-Pad1)") (class "Default")
      (node (ref "A154") (pin "1") (pinfunction "1_1") (pintype "passive"))
      (node (ref "A154") (pin "2") (pinfunction "2_2") (pintype "passive"))
      (node (ref "IC18") (pin "10") (pinfunction "10_10") (pintype "passive"))
    )
    (net (code "180") (name "Net-(A155-Pad1)") (class "Default")
      (node (ref "A155") (pin "1") (pinfunction "1_1") (pintype "passive"))
      (node (ref "A155") (pin "2") (pinfunction "2_2") (pintype "passive"))
      (node (ref "IC18") (pin "11") (pinfunction "11_11") (pintype "passive"))
    )
    (net (code "181") (name "Net-(A156-Pad1)") (class "Default")
      (node (ref "A156") (pin "1") (pinfunction "1_1") (pintype "passive"))
      (node (ref "A156") (pin "2") (pinfunction "2_2") (pintype "passive"))
      (node (ref "IC18") (pin "12") (pinfunction "12_12") (pintype "passive"))
    )
    (net (code "182") (name "Net-(A157-Pad1)") (class "Default")
      (node (ref "A157") (pin "1") (pinfunction "1_1") (pintype "passive"))
      (node (ref "A157") (pin "2") (pinfunction "2_2") (pintype "passive"))
      (node (ref "IC18") (pin "13") (pinfunction "13_13") (pintype "passive"))
    )
    (net (code "183") (name "Net-(A158-Pad1)") (class "Default")
      (node (ref "A158") (pin "1") (pinfunction "1_1") (pintype "passive"))
      (node (ref "A158") (pin "2") (pinfunction "2_2") (pintype "passive"))
      (node (ref "IC18") (pin "14") (pinfunction "14_14") (pintype "passive"))
    )
    (net (code "184") (name "Net-(A159-Pad1)") (class "Default")
      (node (ref "A159") (pin "1") (pinfunction "1_1") (pintype "passive"))
      (node (ref "A159") (pin "2") (pinfunction "2_2") (pintype "passive"))
      (node (ref "IC18") (pin "15") (pinfunction "15_15") (pintype "passive"))
    )
    (net (code "185") (name "Net-(A160-Pad1)") (class "Default")
      (node (ref "A160") (pin "1") (pinfunction "1_1") (pintype "passive"))
      (node (ref "A160") (pin "2") (pinfunction "2_2") (pintype "passive"))
      (node (ref "IC18") (pin "16") (pinfunction "16_16") (pintype "passive"))
    )
    (net (code "186") (name "Net-(A161-Pad1)") (class "Default")
      (node (ref "A161") (pin "1") (pinfunction "1_1") (pintype "passive"))
      (node (ref "A161") (pin "2") (pinfunction "2_2") (pintype "passive"))
      (node (ref "IC19") (pin "1") (pinfunction "1_1") (pintype "passive"))
    )
    (net (code "187") (name "Net-(A162-Pad1)") (class "Default")
      (node (ref "A162") (pin "1") (pinfunction "1_1") (pintype "passive"))
      (node (ref "A162") (pin "2") (pinfunction "2_2") (pintype "passive"))
      (node (ref "IC19") (pin "2") (pinfunction "2_2") (pintype "passive"))
    )
    (net (code "188") (name "Net-(A163-Pad1)") (class "Default")
      (node (ref "A163") (pin "1") (pinfunction "1_1") (pintype "passive"))
      (node (ref "A163") (pin "2") (pinfunction "2_2") (pintype "passive"))
      (node (ref "IC19") (pin "3") (pinfunction "3_3") (pintype "passive"))
    )
    (net (code "189") (name "Net-(A164-Pad1)") (class "Default")
      (node (ref "A164") (pin "1") (pinfunction "1_1") (pintype "passive"))
      (node (ref "A164") (pin "2") (pinfunction "2_2") (pintype "passive"))
      (node (ref "IC19") (pin "4") (pinfunction "4_4") (pintype "passive"))
    )
    (net (code "190") (name "Net-(A165-Pad1)") (class "Default")
      (node (ref "A165") (pin "1") (pinfunction "1_1") (pintype "passive"))
      (node (ref "A165") (pin "2") (pinfunction "2_2") (pintype "passive"))
      (node (ref "IC19") (pin "5") (pinfunction "5_5") (pintype "passive"))
    )
    (net (code "191") (name "Net-(A166-Pad1)") (class "Default")
      (node (ref "A166") (pin "1") (pinfunction "1_1") (pintype "passive"))
      (node (ref "A166") (pin "2") (pinfunction "2_2") (pintype "passive"))
      (node (ref "IC19") (pin "6") (pinfunction "6_6") (pintype "passive"))
    )
    (net (code "192") (name "Net-(A167-Pad1)") (class "Default")
      (node (ref "A167") (pin "1") (pinfunction "1_1") (pintype "passive"))
      (node (ref "A167") (pin "2") (pinfunction "2_2") (pintype "passive"))
      (node (ref "IC19") (pin "7") (pinfunction "7_7") (pintype "passive"))
    )
    (net (code "193") (name "Net-(A168-Pad1)") (class "Default")
      (node (ref "A168") (pin "1") (pinfunction "1_1") (pintype "passive"))
      (node (ref "A168") (pin "2") (pinfunction "2_2") (pintype "passive"))
      (node (ref "IC19") (pin "8") (pinfunction "8_8") (pintype "passive"))
    )
    (net (code "194") (name "Net-(A169-Pad1)") (class "Default")
      (node (ref "A169") (pin "1") (pinfunction "1_1") (pintype "passive"))
      (node (ref "A169") (pin "2") (pinfunction "2_2") (pintype "passive"))
      (node (ref "IC19") (pin "9") (pinfunction "9_9") (pintype "passive"))
    )
    (net (code "195") (name "Net-(A170-Pad1)") (class "Default")
      (node (ref "A170") (pin "1") (pinfunction "1_1") (pintype "passive"))
      (node (ref "A170") (pin "2") (pinfunction "2_2") (pintype "passive"))
      (node (ref "IC19") (pin "10") (pinfunction "10_10") (pintype "passive"))
    )
    (net (code "196") (name "Net-(A171-Pad1)") (class "Default")
      (node (ref "A171") (pin "1") (pinfunction "1_1") (pintype "passive"))
      (node (ref "A171") (pin "2") (pinfunction "2_2") (pintype "passive"))
      (node (ref "IC19") (pin "11") (pinfunction "11_11") (pintype "passive"))
    )
    (net (code "197") (name "Net-(A172-Pad1)") (class "Default")
      (node (ref "A172") (pin "1") (pinfunction "1_1") (pintype "passive"))
      (node (ref "A172") (pin "2") (pinfunction "2_2") (pintype "passive"))
      (node (ref "IC19") (pin "12") (pinfunction "12_12") (pintype "passive"))
    )
    (net (code "198") (name "Net-(A173-Pad1)") (class "Default")
      (node (ref "A173") (pin "1") (pinfunction "1_1") (pintype "passive"))
      (node (ref "A173") (pin "2") (pinfunction "2_2") (pintype "passive"))
      (node (ref "IC19") (pin "13") (pinfunction "13_13") (pintype "passive"))
    )
    (net (code "199") (name "Net-(A174-Pad1)") (class "Default")
      (node (ref "A174") (pin "1") (pinfunction "1_1") (pintype "passive"))
      (node (ref "A174") (pin "2") (pinfunction "2_2") (pintype "passive"))
      (node (ref "IC19") (pin "14") (pinfunction "14_14") (pintype "passive"))
    )
    (net (code "200") (name "Net-(A175-Pad1)") (class "Default")
      (node (ref "A175") (pin "1") (pinfunction "1_1") (pintype "passive"))
      (node (ref "A175") (pin "2") (pinfunction "2_2") (pintype "passive"))
      (node (ref "IC19") (pin "15") (pinfunction "15_15") (pintype "passive"))
    )
    (net (code "201") (name "Net-(A176-Pad1)") (class "Default")
      (node (ref "A176") (pin "1") (pinfunction "1_1") (pintype "passive"))
      (node (ref "A176") (pin "2") (pinfunction "2_2") (pintype "passive"))
      (node (ref "IC19") (pin "16") (pinfunction "16_16") (pintype "passive"))
    )
    (net (code "202") (name "Net-(A177-Pad1)") (class "Default")
      (node (ref "A177") (pin "1") (pinfunction "1_1") (pintype "passive"))
      (node (ref "A177") (pin "2") (pinfunction "2_2") (pintype "passive"))
      (node (ref "IC20") (pin "1") (pinfunction "1_1") (pintype "passive"))
    )
    (net (code "203") (name "Net-(A178-Pad1)") (class "Default")
      (node (ref "A178") (pin "1") (pinfunction "1_1") (pintype "passive"))
      (node (ref "A178") (pin "2") (pinfunction "2_2") (pintype "passive"))
      (node (ref "IC20") (pin "2") (pinfunction "2_2") (pintype "passive"))
    )
    (net (code "204") (name "Net-(A179-Pad1)") (class "Default")
      (node (ref "A179") (pin "1") (pinfunction "1_1") (pintype "passive"))
      (node (ref "A179") (pin "2") (pinfunction "2_2") (pintype "passive"))
      (node (ref "IC20") (pin "3") (pinfunction "3_3") (pintype "passive"))
    )
    (net (code "205") (name "Net-(A180-Pad1)") (class "Default")
      (node (ref "A180") (pin "1") (pinfunction "1_1") (pintype "passive"))
      (node (ref "A180") (pin "2") (pinfunction "2_2") (pintype "passive"))
      (node (ref "IC20") (pin "4") (pinfunction "4_4") (pintype "passive"))
    )
    (net (code "206") (name "Net-(A181-Pad1)") (class "Default")
      (node (ref "A181") (pin "1") (pinfunction "1_1") (pintype "passive"))
      (node (ref "A181") (pin "2") (pinfunction "2_2") (pintype "passive"))
      (node (ref "IC20") (pin "5") (pinfunction "5_5") (pintype "passive"))
    )
    (net (code "207") (name "Net-(A182-Pad1)") (class "Default")
      (node (ref "A182") (pin "1") (pinfunction "1_1") (pintype "passive"))
      (node (ref "A182") (pin "2") (pinfunction "2_2") (pintype "passive"))
      (node (ref "IC20") (pin "6") (pinfunction "6_6") (pintype "passive"))
    )
    (net (code "208") (name "Net-(A183-Pad1)") (class "Default")
      (node (ref "A183") (pin "1") (pinfunction "1_1") (pintype "passive"))
      (node (ref "A183") (pin "2") (pinfunction "2_2") (pintype "passive"))
      (node (ref "IC20") (pin "7") (pinfunction "7_7") (pintype "passive"))
    )
    (net (code "209") (name "Net-(A184-Pad1)") (class "Default")
      (node (ref "A184") (pin "1") (pinfunction "1_1") (pintype "passive"))
      (node (ref "A184") (pin "2") (pinfunction "2_2") (pintype "passive"))
      (node (ref "IC20") (pin "8") (pinfunction "8_8") (pintype "passive"))
    )
    (net (code "210") (name "Net-(A185-Pad1)") (class "Default")
      (node (ref "A185") (pin "1") (pinfunction "1_1") (pintype "passive"))
      (node (ref "A185") (pin "2") (pinfunction "2_2") (pintype "passive"))
      (node (ref "IC20") (pin "9") (pinfunction "9_9") (pintype "passive"))
    )
    (net (code "211") (name "Net-(A186-Pad1)") (class "Default")
      (node (ref "A186") (pin "1") (pinfunction "1_1") (pintype "passive"))
      (node (ref "A186") (pin "2") (pinfunction "2_2") (pintype "passive"))
      (node (ref "IC20") (pin "10") (pinfunction "10_10") (pintype "passive"))
    )
    (net (code "212") (name "Net-(A187-Pad1)") (class "Default")
      (node (ref "A187") (pin "1") (pinfunction "1_1") (pintype "passive"))
      (node (ref "A187") (pin "2") (pinfunction "2_2") (pintype "passive"))
      (node (ref "IC20") (pin "11") (pinfunction "11_11") (pintype "passive"))
    )
    (net (code "213") (name "Net-(A188-Pad1)") (class "Default")
      (node (ref "A188") (pin "1") (pinfunction "1_1") (pintype "passive"))
      (node (ref "A188") (pin "2") (pinfunction "2_2") (pintype "passive"))
      (node (ref "IC20") (pin "12") (pinfunction "12_12") (pintype "passive"))
    )
    (net (code "214") (name "Net-(A189-Pad1)") (class "Default")
      (node (ref "A189") (pin "1") (pinfunction "1_1") (pintype "passive"))
      (node (ref "A189") (pin "2") (pinfunction "2_2") (pintype "passive"))
      (node (ref "IC20") (pin "13") (pinfunction "13_13") (pintype "passive"))
    )
    (net (code "215") (name "Net-(A190-Pad1)") (class "Default")
      (node (ref "A190") (pin "1") (pinfunction "1_1") (pintype "passive"))
      (node (ref "A190") (pin "2") (pinfunction "2_2") (pintype "passive"))
      (node (ref "IC20") (pin "14") (pinfunction "14_14") (pintype "passive"))
    )
    (net (code "216") (name "Net-(A191-Pad1)") (class "Default")
      (node (ref "A191") (pin "1") (pinfunction "1_1") (pintype "passive"))
      (node (ref "A191") (pin "2") (pinfunction "2_2") (pintype "passive"))
      (node (ref "IC20") (pin "15") (pinfunction "15_15") (pintype "passive"))
    )
    (net (code "217") (name "Net-(A192-Pad1)") (class "Default")
      (node (ref "A192") (pin "1") (pinfunction "1_1") (pintype "passive"))
      (node (ref "A192") (pin "2") (pinfunction "2_2") (pintype "passive"))
      (node (ref "IC20") (pin "16") (pinfunction "16_16") (pintype "passive"))
    )
    (net (code "218") (name "Net-(A193-Pad1)") (class "Default")
      (node (ref "A193") (pin "1") (pinfunction "1_1") (pintype "passive"))
      (node (ref "A193") (pin "2") (pinfunction "2_2") (pintype "passive"))
      (node (ref "IC21") (pin "1") (pinfunction "1_1") (pintype "passive"))
    )
    (net (code "219") (name "Net-(A194-Pad1)") (class "Default")
      (node (ref "A194") (pin "1") (pinfunction "1_1") (pintype "passive"))
      (node (ref "A194") (pin "2") (pinfunction "2_2") (pintype "passive"))
      (node (ref "IC21") (pin "2") (pinfunction "2_2") (pintype "passive"))
    )
    (net (code "220") (name "Net-(A195-Pad1)") (class "Default")
      (node (ref "A195") (pin "1") (pinfunction "1_1") (pintype "passive"))
      (node (ref "A195") (pin "2") (pinfunction "2_2") (pintype "passive"))
      (node (ref "IC21") (pin "3") (pinfunction "3_3") (pintype "passive"))
    )
    (net (code "221") (name "Net-(A196-Pad1)") (class "Default")
      (node (ref "A196") (pin "1") (pinfunction "1_1") (pintype "passive"))
      (node (ref "A196") (pin "2") (pinfunction "2_2") (pintype "passive"))
      (node (ref "IC21") (pin "4") (pinfunction "4_4") (pintype "passive"))
    )
    (net (code "222") (name "Net-(A197-Pad1)") (class "Default")
      (node (ref "A197") (pin "1") (pinfunction "1_1") (pintype "passive"))
      (node (ref "A197") (pin "2") (pinfunction "2_2") (pintype "passive"))
      (node (ref "IC21") (pin "5") (pinfunction "5_5") (pintype "passive"))
    )
    (net (code "223") (name "Net-(A198-Pad1)") (class "Default")
      (node (ref "A198") (pin "1") (pinfunction "1_1") (pintype "passive"))
      (node (ref "A198") (pin "2") (pinfunction "2_2") (pintype "passive"))
      (node (ref "IC21") (pin "6") (pinfunction "6_6") (pintype "passive"))
    )
    (net (code "224") (name "Net-(A199-Pad1)") (class "Default")
      (node (ref "A199") (pin "1") (pinfunction "1_1") (pintype "passive"))
      (node (ref "A199") (pin "2") (pinfunction "2_2") (pintype "passive"))
      (node (ref "IC21") (pin "7") (pinfunction "7_7") (pintype "passive"))
    )
    (net (code "225") (name "Net-(A200-Pad1)") (class "Default")
      (node (ref "A200") (pin "1") (pinfunction "1_1") (pintype "passive"))
      (node (ref "A200") (pin "2") (pinfunction "2_2") (pintype "passive"))
      (node (ref "IC21") (pin "8") (pinfunction "8_8") (pintype "passive"))
    )
    (net (code "226") (name "Net-(A201-Pad1)") (class "Default")
      (node (ref "A201") (pin "1") (pinfunction "1_1") (pintype "passive"))
      (node (ref "A201") (pin "2") (pinfunction "2_2") (pintype "passive"))
      (node (ref "IC21") (pin "9") (pinfunction "9_9") (pintype "passive"))
    )
    (net (code "227") (name "Net-(A202-Pad1)") (class "Default")
      (node (ref "A202") (pin "1") (pinfunction "1_1") (pintype "passive"))
      (node (ref "A202") (pin "2") (pinfunction "2_2") (pintype "passive"))
      (node (ref "IC21") (pin "10") (pinfunction "10_10") (pintype "passive"))
    )
    (net (code "228") (name "Net-(A203-Pad1)") (class "Default")
      (node (ref "A203") (pin "1") (pinfunction "1_1") (pintype "passive"))
      (node (ref "A203") (pin "2") (pinfunction "2_2") (pintype "passive"))
      (node (ref "IC21") (pin "11") (pinfunction "11_11") (pintype "passive"))
    )
    (net (code "229") (name "Net-(A204-Pad1)") (class "Default")
      (node (ref "A204") (pin "1") (pinfunction "1_1") (pintype "passive"))
      (node (ref "A204") (pin "2") (pinfunction "2_2") (pintype "passive"))
      (node (ref "IC21") (pin "12") (pinfunction "12_12") (pintype "passive"))
    )
    (net (code "230") (name "Net-(A205-Pad1)") (class "Default")
      (node (ref "A205") (pin "1") (pinfunction "1_1") (pintype "passive"))
      (node (ref "A205") (pin "2") (pinfunction "2_2") (pintype "passive"))
      (node (ref "IC21") (pin "13") (pinfunction "13_13") (pintype "passive"))
    )
    (net (code "231") (name "Net-(A206-Pad1)") (class "Default")
      (node (ref "A206") (pin "1") (pinfunction "1_1") (pintype "passive"))
      (node (ref "A206") (pin "2") (pinfunction "2_2") (pintype "passive"))
      (node (ref "IC21") (pin "14") (pinfunction "14_14") (pintype "passive"))
    )
    (net (code "232") (name "Net-(A207-Pad1)") (class "Default")
      (node (ref "A207") (pin "1") (pinfunction "1_1") (pintype "passive"))
      (node (ref "A207") (pin "2") (pinfunction "2_2") (pintype "passive"))
      (node (ref "IC21") (pin "15") (pinfunction "15_15") (pintype "passive"))
    )
    (net (code "233") (name "Net-(A208-Pad1)") (class "Default")
      (node (ref "A208") (pin "1") (pinfunction "1_1") (pintype "passive"))
      (node (ref "A208") (pin "2") (pinfunction "2_2") (pintype "passive"))
      (node (ref "IC21") (pin "16") (pinfunction "16_16") (pintype "passive"))
    )
    (net (code "234") (name "Net-(A209-Pad1)") (class "Default")
      (node (ref "A209") (pin "1") (pinfunction "1_1") (pintype "passive"))
      (node (ref "A209") (pin "2") (pinfunction "2_2") (pintype "passive"))
      (node (ref "IC22") (pin "1") (pinfunction "1_1") (pintype "passive"))
    )
    (net (code "235") (name "Net-(A210-Pad1)") (class "Default")
      (node (ref "A210") (pin "1") (pinfunction "1_1") (pintype "passive"))
      (node (ref "A210") (pin "2") (pinfunction "2_2") (pintype "passive"))
      (node (ref "IC22") (pin "2") (pinfunction "2_2") (pintype "passive"))
    )
    (net (code "236") (name "Net-(A211-Pad1)") (class "Default")
      (node (ref "A211") (pin "1") (pinfunction "1_1") (pintype "passive"))
      (node (ref "A211") (pin "2") (pinfunction "2_2") (pintype "passive"))
      (node (ref "IC22") (pin "3") (pinfunction "3_3") (pintype "passive"))
    )
    (net (code "237") (name "Net-(A212-Pad1)") (class "Default")
      (node (ref "A212") (pin "1") (pinfunction "1_1") (pintype "passive"))
      (node (ref "A212") (pin "2") (pinfunction "2_2") (pintype "passive"))
      (node (ref "IC22") (pin "4") (pinfunction "4_4") (pintype "passive"))
    )
    (net (code "238") (name "Net-(A213-Pad1)") (class "Default")
      (node (ref "A213") (pin "1") (pinfunction "1_1") (pintype "passive"))
      (node (ref "A213") (pin "2") (pinfunction "2_2") (pintype "passive"))
      (node (ref "IC22") (pin "5") (pinfunction "5_5") (pintype "passive"))
    )
    (net (code "239") (name "Net-(A214-Pad1)") (class "Default")
      (node (ref "A214") (pin "1") (pinfunction "1_1") (pintype "passive"))
      (node (ref "A214") (pin "2") (pinfunction "2_2") (pintype "passive"))
      (node (ref "IC22") (pin "6") (pinfunction "6_6") (pintype "passive"))
    )
    (net (code "240") (name "Net-(A215-Pad1)") (class "Default")
      (node (ref "A215") (pin "1") (pinfunction "1_1") (pintype "passive"))
      (node (ref "A215") (pin "2") (pinfunction "2_2") (pintype "passive"))
      (node (ref "IC22") (pin "7") (pinfunction "7_7") (pintype "passive"))
    )
    (net (code "241") (name "Net-(A216-Pad1)") (class "Default")
      (node (ref "A216") (pin "1") (pinfunction "1_1") (pintype "passive"))
      (node (ref "A216") (pin "2") (pinfunction "2_2") (pintype "passive"))
      (node (ref "IC22") (pin "8") (pinfunction "8_8") (pintype "passive"))
    )
    (net (code "242") (name "Net-(A217-Pad1)") (class "Default")
      (node (ref "A217") (pin "1") (pinfunction "1_1") (pintype "passive"))
      (node (ref "A217") (pin "2") (pinfunction "2_2") (pintype "passive"))
      (node (ref "IC22") (pin "9") (pinfunction "9_9") (pintype "passive"))
    )
    (net (code "243") (name "Net-(A218-Pad1)") (class "Default")
      (node (ref "A218") (pin "1") (pinfunction "1_1") (pintype "passive"))
      (node (ref "A218") (pin "2") (pinfunction "2_2") (pintype "passive"))
      (node (ref "IC22") (pin "10") (pinfunction "10_10") (pintype "passive"))
    )
    (net (code "244") (name "Net-(A219-Pad1)") (class "Default")
      (node (ref "A219") (pin "1") (pinfunction "1_1") (pintype "passive"))
      (node (ref "A219") (pin "2") (pinfunction "2_2") (pintype "passive"))
      (node (ref "IC22") (pin "11") (pinfunction "11_11") (pintype "passive"))
    )
    (net (code "245") (name "Net-(A220-Pad1)") (class "Default")
      (node (ref "A220") (pin "1") (pinfunction "1_1") (pintype "passive"))
      (node (ref "A220") (pin "2") (pinfunction "2_2") (pintype "passive"))
      (node (ref "IC22") (pin "12") (pinfunction "12_12") (pintype "passive"))
    )
    (net (code "246") (name "Net-(A221-Pad1)") (class "Default")
      (node (ref "A221") (pin "1") (pinfunction "1_1") (pintype "passive"))
      (node (ref "A221") (pin "2") (pinfunction "2_2") (pintype "passive"))
      (node (ref "IC22") (pin "13") (pinfunction "13_13") (pintype "passive"))
    )
    (net (code "247") (name "Net-(A222-Pad1)") (class "Default")
      (node (ref "A222") (pin "1") (pinfunction "1_1") (pintype "passive"))
      (node (ref "A222") (pin "2") (pinfunction "2_2") (pintype "passive"))
      (node (ref "IC22") (pin "14") (pinfunction "14_14") (pintype "passive"))
    )
    (net (code "248") (name "Net-(A223-Pad1)") (class "Default")
      (node (ref "A223") (pin "1") (pinfunction "1_1") (pintype "passive"))
      (node (ref "A223") (pin "2") (pinfunction "2_2") (pintype "passive"))
      (node (ref "IC22") (pin "15") (pinfunction "15_15") (pintype "passive"))
    )
    (net (code "249") (name "Net-(A224-Pad1)") (class "Default")
      (node (ref "A224") (pin "1") (pinfunction "1_1") (pintype "passive"))
      (node (ref "A224") (pin "2") (pinfunction "2_2") (pintype "passive"))
      (node (ref "IC22") (pin "16") (pinfunction "16_16") (pintype "passive"))
    )
    (net (code "250") (name "Net-(A225-Pad1)") (class "Default")
      (node (ref "A225") (pin "1") (pinfunction "1_1") (pintype "passive"))
      (node (ref "A225") (pin "2") (pinfunction "2_2") (pintype "passive"))
      (node (ref "IC23") (pin "1") (pinfunction "1_1") (pintype "passive"))
    )
    (net (code "251") (name "Net-(A226-Pad1)") (class "Default")
      (node (ref "A226") (pin "1") (pinfunction "1_1") (pintype "passive"))
      (node (ref "A226") (pin "2") (pinfunction "2_2") (pintype "passive"))
      (node (ref "IC23") (pin "2") (pinfunction "2_2") (pintype "passive"))
    )
    (net (code "252") (name "Net-(A227-Pad1)") (class "Default")
      (node (ref "A227") (pin "1") (pinfunction "1_1") (pintype "passive"))
      (node (ref "A227") (pin "2") (pinfunction "2_2") (pintype "passive"))
      (node (ref "IC23") (pin "3") (pinfunction "3_3") (pintype "passive"))
    )
    (net (code "253") (name "Net-(A228-Pad1)") (class "Default")
      (node (ref "A228") (pin "1") (pinfunction "1_1") (pintype "passive"))
      (node (ref "A228") (pin "2") (pinfunction "2_2") (pintype "passive"))
      (node (ref "IC23") (pin "4") (pinfunction "4_4") (pintype "passive"))
    )
    (net (code "254") (name "Net-(A229-Pad1)") (class "Default")
      (node (ref "A229") (pin "1") (pinfunction "1_1") (pintype "passive"))
      (node (ref "A229") (pin "2") (pinfunction "2_2") (pintype "passive"))
      (node (ref "IC23") (pin "5") (pinfunction "5_5") (pintype "passive"))
    )
    (net (code "255") (name "Net-(A230-Pad1)") (class "Default")
      (node (ref "A230") (pin "1") (pinfunction "1_1") (pintype "passive"))
      (node (ref "A230") (pin "2") (pinfunction "2_2") (pintype "passive"))
      (node (ref "IC23") (pin "6") (pinfunction "6_6") (pintype "passive"))
    )
    (net (code "256") (name "Net-(A231-Pad1)") (class "Default")
      (node (ref "A231") (pin "1") (pinfunction "1_1") (pintype "passive"))
      (node (ref "A231") (pin "2") (pinfunction "2_2") (pintype "passive"))
      (node (ref "IC23") (pin "7") (pinfunction "7_7") (pintype "passive"))
    )
    (net (code "257") (name "Net-(A232-Pad1)") (class "Default")
      (node (ref "A232") (pin "1") (pinfunction "1_1") (pintype "passive"))
      (node (ref "A232") (pin "2") (pinfunction "2_2") (pintype "passive"))
      (node (ref "IC23") (pin "8") (pinfunction "8_8") (pintype "passive"))
    )
    (net (code "258") (name "Net-(A233-Pad1)") (class "Default")
      (node (ref "A233") (pin "1") (pinfunction "1_1") (pintype "passive"))
      (node (ref "A233") (pin "2") (pinfunction "2_2") (pintype "passive"))
      (node (ref "IC23") (pin "9") (pinfunction "9_9") (pintype "passive"))
    )
    (net (code "259") (name "Net-(A234-Pad1)") (class "Default")
      (node (ref "A234") (pin "1") (pinfunction "1_1") (pintype "passive"))
      (node (ref "A234") (pin "2") (pinfunction "2_2") (pintype "passive"))
      (node (ref "IC23") (pin "10") (pinfunction "10_10") (pintype "passive"))
    )
    (net (code "260") (name "Net-(A235-Pad1)") (class "Default")
      (node (ref "A235") (pin "1") (pinfunction "1_1") (pintype "passive"))
      (node (ref "A235") (pin "2") (pinfunction "2_2") (pintype "passive"))
      (node (ref "IC23") (pin "11") (pinfunction "11_11") (pintype "passive"))
    )
    (net (code "261") (name "Net-(A236-Pad1)") (class "Default")
      (node (ref "A236") (pin "1") (pinfunction "1_1") (pintype "passive"))
      (node (ref "A236") (pin "2") (pinfunction "2_2") (pintype "passive"))
      (node (ref "IC23") (pin "12") (pinfunction "12_12") (pintype "passive"))
    )
    (net (code "262") (name "Net-(A237-Pad1)") (class "Default")
      (node (ref "A237") (pin "1") (pinfunction "1_1") (pintype "passive"))
      (node (ref "A237") (pin "2") (pinfunction "2_2") (pintype "passive"))
      (node (ref "IC23") (pin "13") (pinfunction "13_13") (pintype "passive"))
    )
    (net (code "263") (name "Net-(A238-Pad1)") (class "Default")
      (node (ref "A238") (pin "1") (pinfunction "1_1") (pintype "passive"))
      (node (ref "A238") (pin "2") (pinfunction "2_2") (pintype "passive"))
      (node (ref "IC23") (pin "14") (pinfunction "14_14") (pintype "passive"))
    )
    (net (code "264") (name "Net-(A239-Pad1)") (class "Default")
      (node (ref "A239") (pin "1") (pinfunction "1_1") (pintype "passive"))
      (node (ref "A239") (pin "2") (pinfunction "2_2") (pintype "passive"))
      (node (ref "IC23") (pin "15") (pinfunction "15_15") (pintype "passive"))
    )
    (net (code "265") (name "Net-(A240-Pad1)") (class "Default")
      (node (ref "A240") (pin "1") (pinfunction "1_1") (pintype "passive"))
      (node (ref "A240") (pin "2") (pinfunction "2_2") (pintype "passive"))
      (node (ref "IC23") (pin "16") (pinfunction "16_16") (pintype "passive"))
    )
    (net (code "266") (name "Net-(A241-Pad1)") (class "Default")
      (node (ref "A241") (pin "1") (pinfunction "1_1") (pintype "passive"))
      (node (ref "A241") (pin "2") (pinfunction "2_2") (pintype "passive"))
      (node (ref "IC24") (pin "1") (pinfunction "1_1") (pintype "passive"))
    )
    (net (code "267") (name "Net-(A242-Pad1)") (class "Default")
      (node (ref "A242") (pin "1") (pinfunction "1_1") (pintype "passive"))
      (node (ref "A242") (pin "2") (pinfunction "2_2") (pintype "passive"))
      (node (ref "IC24") (pin "2") (pinfunction "2_2") (pintype "passive"))
    )
    (net (code "268") (name "Net-(A243-Pad1)") (class "Default")
      (node (ref "A243") (pin "1") (pinfunction "1_1") (pintype "passive"))
      (node (ref "A243") (pin "2") (pinfunction "2_2") (pintype "passive"))
      (node (ref "IC24") (pin "3") (pinfunction "3_3") (pintype "passive"))
    )
    (net (code "269") (name "Net-(A244-Pad1)") (class "Default")
      (node (ref "A244") (pin "1") (pinfunction "1_1") (pintype "passive"))
      (node (ref "A244") (pin "2") (pinfunction "2_2") (pintype "passive"))
      (node (ref "IC24") (pin "4") (pinfunction "4_4") (pintype "passive"))
    )
    (net (code "270") (name "Net-(A245-Pad1)") (class "Default")
      (node (ref "A245") (pin "1") (pinfunction "1_1") (pintype "passive"))
      (node (ref "A245") (pin "2") (pinfunction "2_2") (pintype "passive"))
      (node (ref "IC24") (pin "5") (pinfunction "5_5") (pintype "passive"))
    )
    (net (code "271") (name "Net-(A246-Pad1)") (class "Default")
      (node (ref "A246") (pin "1") (pinfunction "1_1") (pintype "passive"))
      (node (ref "A246") (pin "2") (pinfunction "2_2") (pintype "passive"))
      (node (ref "IC24") (pin "6") (pinfunction "6_6") (pintype "passive"))
    )
    (net (code "272") (name "Net-(A247-Pad1)") (class "Default")
      (node (ref "A247") (pin "1") (pinfunction "1_1") (pintype "passive"))
      (node (ref "A247") (pin "2") (pinfunction "2_2") (pintype "passive"))
      (node (ref "IC24") (pin "7") (pinfunction "7_7") (pintype "passive"))
    )
    (net (code "273") (name "Net-(A248-Pad1)") (class "Default")
      (node (ref "A248") (pin "1") (pinfunction "1_1") (pintype "passive"))
      (node (ref "A248") (pin "2") (pinfunction "2_2") (pintype "passive"))
      (node (ref "IC24") (pin "8") (pinfunction "8_8") (pintype "passive"))
    )
    (net (code "274") (name "Net-(A249-Pad1)") (class "Default")
      (node (ref "A249") (pin "1") (pinfunction "1_1") (pintype "passive"))
      (node (ref "A249") (pin "2") (pinfunction "2_2") (pintype "passive"))
      (node (ref "IC24") (pin "9") (pinfunction "9_9") (pintype "passive"))
    )
    (net (code "275") (name "Net-(A250-Pad1)") (class "Default")
      (node (ref "A250") (pin "1") (pinfunction "1_1") (pintype "passive"))
      (node (ref "A250") (pin "2") (pinfunction "2_2") (pintype "passive"))
      (node (ref "IC24") (pin "10") (pinfunction "10_10") (pintype "passive"))
    )
    (net (code "276") (name "Net-(A251-Pad1)") (class "Default")
      (node (ref "A251") (pin "1") (pinfunction "1_1") (pintype "passive"))
      (node (ref "A251") (pin "2") (pinfunction "2_2") (pintype "passive"))
      (node (ref "IC24") (pin "11") (pinfunction "11_11") (pintype "passive"))
    )
    (net (code "277") (name "Net-(A252-Pad1)") (class "Default")
      (node (ref "A252") (pin "1") (pinfunction "1_1") (pintype "passive"))
      (node (ref "A252") (pin "2") (pinfunction "2_2") (pintype "passive"))
      (node (ref "IC24") (pin "12") (pinfunction "12_12") (pintype "passive"))
    )
    (net (code "278") (name "Net-(A253-Pad1)") (class "Default")
      (node (ref "A253") (pin "1") (pinfunction "1_1") (pintype "passive"))
      (node (ref "A253") (pin "2") (pinfunction "2_2") (pintype "passive"))
      (node (ref "IC24") (pin "13") (pinfunction "13_13") (pintype "passive"))
    )
    (net (code "279") (name "Net-(A254-Pad1)") (class "Default")
      (node (ref "A254") (pin "1") (pinfunction "1_1") (pintype "passive"))
      (node (ref "A254") (pin "2") (pinfunction "2_2") (pintype "passive"))
      (node (ref "IC24") (pin "14") (pinfunction "14_14") (pintype "passive"))
    )
    (net (code "280") (name "Net-(A255-Pad1)") (class "Default")
      (node (ref "A255") (pin "1") (pinfunction "1_1") (pintype "passive"))
      (node (ref "A255") (pin "2") (pinfunction "2_2") (pintype "passive"))
      (node (ref "IC24") (pin "15") (pinfunction "15_15") (pintype "passive"))
    )
    (net (code "281") (name "Net-(A256-Pad1)") (class "Default")
      (node (ref "A256") (pin "1") (pinfunction "1_1") (pintype "passive"))
      (node (ref "A256") (pin "2") (pinfunction "2_2") (pintype "passive"))
      (node (ref "IC24") (pin "16") (pinfunction "16_16") (pintype "passive"))
    )
    (net (code "282") (name "Net-(A257-Pad1)") (class "Default")
      (node (ref "A257") (pin "1") (pinfunction "1_1") (pintype "passive"))
      (node (ref "A257") (pin "2") (pinfunction "2_2") (pintype "passive"))
      (node (ref "IC25") (pin "1") (pinfunction "1_1") (pintype "passive"))
    )
    (net (code "283") (name "Net-(A258-Pad1)") (class "Default")
      (node (ref "A258") (pin "1") (pinfunction "1_1") (pintype "passive"))
      (node (ref "A258") (pin "2") (pinfunction "2_2") (pintype "passive"))
      (node (ref "IC25") (pin "2") (pinfunction "2_2") (pintype "passive"))
    )
    (net (code "284") (name "Net-(A259-Pad1)") (class "Default")
      (node (ref "A259") (pin "1") (pinfunction "1_1") (pintype "passive"))
      (node (ref "A259") (pin "2") (pinfunction "2_2") (pintype "passive"))
      (node (ref "IC25") (pin "3") (pinfunction "3_3") (pintype "passive"))
    )
    (net (code "285") (name "Net-(A260-Pad1)") (class "Default")
      (node (ref "A260") (pin "1") (pinfunction "1_1") (pintype "passive"))
      (node (ref "A260") (pin "2") (pinfunction "2_2") (pintype "passive"))
      (node (ref "IC25") (pin "4") (pinfunction "4_4") (pintype "passive"))
    )
    (net (code "286") (name "Net-(A261-Pad1)") (class "Default")
      (node (ref "A261") (pin "1") (pinfunction "1_1") (pintype "passive"))
      (node (ref "A261") (pin "2") (pinfunction "2_2") (pintype "passive"))
      (node (ref "IC25") (pin "5") (pinfunction "5_5") (pintype "passive"))
    )
    (net (code "287") (name "Net-(A262-Pad1)") (class "Default")
      (node (ref "A262") (pin "1") (pinfunction "1_1") (pintype "passive"))
      (node (ref "A262") (pin "2") (pinfunction "2_2") (pintype "passive"))
      (node (ref "IC25") (pin "6") (pinfunction "6_6") (pintype "passive"))
    )
    (net (code "288") (name "Net-(A263-Pad1)") (class "Default")
      (node (ref "A263") (pin "1") (pinfunction "1_1") (pintype "passive"))
      (node (ref "A263") (pin "2") (pinfunction "2_2") (pintype "passive"))
      (node (ref "IC25") (pin "7") (pinfunction "7_7") (pintype "passive"))
    )
    (net (code "289") (name "Net-(A264-Pad1)") (class "Default")
      (node (ref "A264") (pin "1") (pinfunction "1_1") (pintype "passive"))
      (node (ref "A264") (pin "2") (pinfunction "2_2") (pintype "passive"))
      (node (ref "IC25") (pin "8") (pinfunction "8_8") (pintype "passive"))
    )
    (net (code "290") (name "Net-(A265-Pad1)") (class "Default")
      (node (ref "A265") (pin "1") (pinfunction "1_1") (pintype "passive"))
      (node (ref "A265") (pin "2") (pinfunction "2_2") (pintype "passive"))
      (node (ref "IC25") (pin "9") (pinfunction "9_9") (pintype "passive"))
    )
    (net (code "291") (name "Net-(A266-Pad1)") (class "Default")
      (node (ref "A266") (pin "1") (pinfunction "1_1") (pintype "passive"))
      (node (ref "A266") (pin "2") (pinfunction "2_2") (pintype "passive"))
      (node (ref "IC25") (pin "10") (pinfunction "10_10") (pintype "passive"))
    )
    (net (code "292") (name "Net-(A267-Pad1)") (class "Default")
      (node (ref "A267") (pin "1") (pinfunction "1_1") (pintype "passive"))
      (node (ref "A267") (pin "2") (pinfunction "2_2") (pintype "passive"))
      (node (ref "IC25") (pin "11") (pinfunction "11_11") (pintype "passive"))
    )
    (net (code "293") (name "Net-(A268-Pad1)") (class "Default")
      (node (ref "A268") (pin "1") (pinfunction "1_1") (pintype "passive"))
      (node (ref "A268") (pin "2") (pinfunction "2_2") (pintype "passive"))
      (node (ref "IC25") (pin "12") (pinfunction "12_12") (pintype "passive"))
    )
    (net (code "294") (name "Net-(A269-Pad1)") (class "Default")
      (node (ref "A269") (pin "1") (pinfunction "1_1") (pintype "passive"))
      (node (ref "A269") (pin "2") (pinfunction "2_2") (pintype "passive"))
      (node (ref "IC25") (pin "13") (pinfunction "13_13") (pintype "passive"))
    )
    (net (code "295") (name "Net-(A270-Pad1)") (class "Default")
      (node (ref "A270") (pin "1") (pinfunction "1_1") (pintype "passive"))
      (node (ref "A270") (pin "2") (pinfunction "2_2") (pintype "passive"))
      (node (ref "IC25") (pin "14") (pinfunction "14_14") (pintype "passive"))
    )
    (net (code "296") (name "Net-(A271-Pad1)") (class "Default")
      (node (ref "A271") (pin "1") (pinfunction "1_1") (pintype "passive"))
      (node (ref "A271") (pin "2") (pinfunction "2_2") (pintype "passive"))
      (node (ref "IC25") (pin "15") (pinfunction "15_15") (pintype "passive"))
    )
    (net (code "297") (name "Net-(A272-Pad1)") (class "Default")
      (node (ref "A272") (pin "1") (pinfunction "1_1") (pintype "passive"))
      (node (ref "A272") (pin "2") (pinfunction "2_2") (pintype "passive"))
      (node (ref "IC25") (pin "16") (pinfunction "16_16") (pintype "passive"))
    )
    (net (code "298") (name "Net-(A273-Pad1)") (class "Default")
      (node (ref "A273") (pin "1") (pinfunction "1_1") (pintype "passive"))
      (node (ref "A273") (pin "2") (pinfunction "2_2") (pintype "passive"))
      (node (ref "IC26") (pin "1") (pinfunction "1_1") (pintype "passive"))
    )
    (net (code "299") (name "Net-(A274-Pad1)") (class "Default")
      (node (ref "A274") (pin "1") (pinfunction "1_1") (pintype "passive"))
      (node (ref "A274") (pin "2") (pinfunction "2_2") (pintype "passive"))
      (node (ref "IC26") (pin "2") (pinfunction "2_2") (pintype "passive"))
    )
    (net (code "300") (name "Net-(A275-Pad1)") (class "Default")
      (node (ref "A275") (pin "1") (pinfunction "1_1") (pintype "passive"))
      (node (ref "A275") (pin "2") (pinfunction "2_2") (pintype "passive"))
      (node (ref "IC26") (pin "3") (pinfunction "3_3") (pintype "passive"))
    )
    (net (code "301") (name "Net-(A276-Pad1)") (class "Default")
      (node (ref "A276") (pin "1") (pinfunction "1_1") (pintype "passive"))
      (node (ref "A276") (pin "2") (pinfunction "2_2") (pintype "passive"))
      (node (ref "IC26") (pin "4") (pinfunction "4_4") (pintype "passive"))
    )
    (net (code "302") (name "Net-(A277-Pad1)") (class "Default")
      (node (ref "A277") (pin "1") (pinfunction "1_1") (pintype "passive"))
      (node (ref "A277") (pin "2") (pinfunction "2_2") (pintype "passive"))
      (node (ref "IC26") (pin "5") (pinfunction "5_5") (pintype "passive"))
    )
    (net (code "303") (name "Net-(A278-Pad1)") (class "Default")
      (node (ref "A278") (pin "1") (pinfunction "1_1") (pintype "passive"))
      (node (ref "A278") (pin "2") (pinfunction "2_2") (pintype "passive"))
      (node (ref "IC26") (pin "6") (pinfunction "6_6") (pintype "passive"))
    )
    (net (code "304") (name "Net-(A279-Pad1)") (class "Default")
      (node (ref "A279") (pin "1") (pinfunction "1_1") (pintype "passive"))
      (node (ref "A279") (pin "2") (pinfunction "2_2") (pintype "passive"))
      (node (ref "IC26") (pin "7") (pinfunction "7_7") (pintype "passive"))
    )
    (net (code "305") (name "Net-(A280-Pad1)") (class "Default")
      (node (ref "A280") (pin "1") (pinfunction "1_1") (pintype "passive"))
      (node (ref "A280") (pin "2") (pinfunction "2_2") (pintype "passive"))
      (node (ref "IC26") (pin "8") (pinfunction "8_8") (pintype "passive"))
    )
    (net (code "306") (name "Net-(A281-Pad1)") (class "Default")
      (node (ref "A281") (pin "1") (pinfunction "1_1") (pintype "passive"))
      (node (ref "A281") (pin "2") (pinfunction "2_2") (pintype "passive"))
      (node (ref "IC26") (pin "9") (pinfunction "9_9") (pintype "passive"))
    )
    (net (code "307") (name "Net-(A282-Pad1)") (class "Default")
      (node (ref "A282") (pin "1") (pinfunction "1_1") (pintype "passive"))
      (node (ref "A282") (pin "2") (pinfunction "2_2") (pintype "passive"))
      (node (ref "IC26") (pin "10") (pinfunction "10_10") (pintype "passive"))
    )
    (net (code "308") (name "Net-(A283-Pad1)") (class "Default")
      (node (ref "A283") (pin "1") (pinfunction "1_1") (pintype "passive"))
      (node (ref "A283") (pin "2") (pinfunction "2_2") (pintype "passive"))
      (node (ref "IC26") (pin "11") (pinfunction "11_11") (pintype "passive"))
    )
    (net (code "309") (name "Net-(A284-Pad1)") (class "Default")
      (node (ref "A284") (pin "1") (pinfunction "1_1") (pintype "passive"))
      (node (ref "A284") (pin "2") (pinfunction "2_2") (pintype "passive"))
      (node (ref "IC26") (pin "12") (pinfunction "12_12") (pintype "passive"))
    )
    (net (code "310") (name "Net-(A285-Pad1)") (class "Default")
      (node (ref "A285") (pin "1") (pinfunction "1_1") (pintype "passive"))
      (node (ref "A285") (pin "2") (pinfunction "2_2") (pintype "passive"))
      (node (ref "IC26") (pin "13") (pinfunction "13_13") (pintype "passive"))
    )
    (net (code "311") (name "Net-(A286-Pad1)") (class "Default")
      (node (ref "A286") (pin "1") (pinfunction "1_1") (pintype "passive"))
      (node (ref "A286") (pin "2") (pinfunction "2_2") (pintype "passive"))
      (node (ref "IC26") (pin "14") (pinfunction "14_14") (pintype "passive"))
    )
    (net (code "312") (name "Net-(A287-Pad1)") (class "Default")
      (node (ref "A287") (pin "1") (pinfunction "1_1") (pintype "passive"))
      (node (ref "A287") (pin "2") (pinfunction "2_2") (pintype "passive"))
      (node (ref "IC26") (pin "15") (pinfunction "15_15") (pintype "passive"))
    )
    (net (code "313") (name "Net-(A288-Pad1)") (class "Default")
      (node (ref "A288") (pin "1") (pinfunction "1_1") (pintype "passive"))
      (node (ref "A288") (pin "2") (pinfunction "2_2") (pintype "passive"))
      (node (ref "IC26") (pin "16") (pinfunction "16_16") (pintype "passive"))
    )
    (net (code "314") (name "Net-(A289-Pad1)") (class "Default")
      (node (ref "A289") (pin "1") (pinfunction "1_1") (pintype "passive"))
      (node (ref "A289") (pin "2") (pinfunction "2_2") (pintype "passive"))
      (node (ref "IC27") (pin "1") (pinfunction "1_1") (pintype "passive"))
    )
    (net (code "315") (name "Net-(A290-Pad1)") (class "Default")
      (node (ref "A290") (pin "1") (pinfunction "1_1") (pintype "passive"))
      (node (ref "A290") (pin "2") (pinfunction "2_2") (pintype "passive"))
      (node (ref "IC27") (pin "2") (pinfunction "2_2") (pintype "passive"))
    )
    (net (code "316") (name "Net-(A291-Pad1)") (class "Default")
      (node (ref "A291") (pin "1") (pinfunction "1_1") (pintype "passive"))
      (node (ref "A291") (pin "2") (pinfunction "2_2") (pintype "passive"))
      (node (ref "IC27") (pin "3") (pinfunction "3_3") (pintype "passive"))
    )
    (net (code "317") (name "Net-(A292-Pad1)") (class "Default")
      (node (ref "A292") (pin "1") (pinfunction "1_1") (pintype "passive"))
      (node (ref "A292") (pin "2") (pinfunction "2_2") (pintype "passive"))
      (node (ref "IC27") (pin "4") (pinfunction "4_4") (pintype "passive"))
    )
    (net (code "318") (name "Net-(A293-Pad1)") (class "Default")
      (node (ref "A293") (pin "1") (pinfunction "1_1") (pintype "passive"))
      (node (ref "A293") (pin "2") (pinfunction "2_2") (pintype "passive"))
      (node (ref "IC27") (pin "5") (pinfunction "5_5") (pintype "passive"))
    )
    (net (code "319") (name "Net-(A294-Pad1)") (class "Default")
      (node (ref "A294") (pin "1") (pinfunction "1_1") (pintype "passive"))
      (node (ref "A294") (pin "2") (pinfunction "2_2") (pintype "passive"))
      (node (ref "IC27") (pin "6") (pinfunction "6_6") (pintype "passive"))
    )
    (net (code "320") (name "Net-(A295-Pad1)") (class "Default")
      (node (ref "A295") (pin "1") (pinfunction "1_1") (pintype "passive"))
      (node (ref "A295") (pin "2") (pinfunction "2_2") (pintype "passive"))
      (node (ref "IC27") (pin "7") (pinfunction "7_7") (pintype "passive"))
    )
    (net (code "321") (name "Net-(A296-Pad1)") (class "Default")
      (node (ref "A296") (pin "1") (pinfunction "1_1") (pintype "passive"))
      (node (ref "A296") (pin "2") (pinfunction "2_2") (pintype "passive"))
      (node (ref "IC27") (pin "8") (pinfunction "8_8") (pintype "passive"))
    )
    (net (code "322") (name "Net-(A297-Pad1)") (class "Default")
      (node (ref "A297") (pin "1") (pinfunction "1_1") (pintype "passive"))
      (node (ref "A297") (pin "2") (pinfunction "2_2") (pintype "passive"))
      (node (ref "IC27") (pin "9") (pinfunction "9_9") (pintype "passive"))
    )
    (net (code "323") (name "Net-(A298-Pad1)") (class "Default")
      (node (ref "A298") (pin "1") (pinfunction "1_1") (pintype "passive"))
      (node (ref "A298") (pin "2") (pinfunction "2_2") (pintype "passive"))
      (node (ref "IC27") (pin "10") (pinfunction "10_10") (pintype "passive"))
    )
    (net (code "324") (name "Net-(A299-Pad1)") (class "Default")
      (node (ref "A299") (pin "1") (pinfunction "1_1") (pintype "passive"))
      (node (ref "A299") (pin "2") (pinfunction "2_2") (pintype "passive"))
      (node (ref "IC27") (pin "11") (pinfunction "11_11") (pintype "passive"))
    )
    (net (code "325") (name "Net-(A300-Pad1)") (class "Default")
      (node (ref "A300") (pin "1") (pinfunction "1_1") (pintype "passive"))
      (node (ref "A300") (pin "2") (pinfunction "2_2") (pintype "passive"))
      (node (ref "IC27") (pin "12") (pinfunction "12_12") (pintype "passive"))
    )
    (net (code "326") (name "Net-(A301-Pad1)") (class "Default")
      (node (ref "A301") (pin "1") (pinfunction "1_1") (pintype "passive"))
      (node (ref "A301") (pin "2") (pinfunction "2_2") (pintype "passive"))
      (node (ref "IC27") (pin "13") (pinfunction "13_13") (pintype "passive"))
    )
    (net (code "327") (name "Net-(A302-Pad1)") (class "Default")
      (node (ref "A302") (pin "1") (pinfunction "1_1") (pintype "passive"))
      (node (ref "A302") (pin "2") (pinfunction "2_2") (pintype "passive"))
      (node (ref "IC27") (pin "14") (pinfunction "14_14") (pintype "passive"))
    )
    (net (code "328") (name "Net-(A303-Pad1)") (class "Default")
      (node (ref "A303") (pin "1") (pinfunction "1_1") (pintype "passive"))
      (node (ref "A303") (pin "2") (pinfunction "2_2") (pintype "passive"))
      (node (ref "IC27") (pin "15") (pinfunction "15_15") (pintype "passive"))
    )
    (net (code "329") (name "Net-(A304-Pad1)") (class "Default")
      (node (ref "A304") (pin "1") (pinfunction "1_1") (pintype "passive"))
      (node (ref "A304") (pin "2") (pinfunction "2_2") (pintype "passive"))
      (node (ref "IC27") (pin "16") (pinfunction "16_16") (pintype "passive"))
    )
    (net (code "330") (name "Net-(A305-Pad1)") (class "Default")
      (node (ref "A305") (pin "1") (pinfunction "1_1") (pintype "passive"))
      (node (ref "A305") (pin "2") (pinfunction "2_2") (pintype "passive"))
      (node (ref "IC28") (pin "1") (pinfunction "1_1") (pintype "passive"))
    )
    (net (code "331") (name "Net-(A306-Pad1)") (class "Default")
      (node (ref "A306") (pin "1") (pinfunction "1_1") (pintype "passive"))
      (node (ref "A306") (pin "2") (pinfunction "2_2") (pintype "passive"))
      (node (ref "IC28") (pin "2") (pinfunction "2_2") (pintype "passive"))
    )
    (net (code "332") (name "Net-(A307-Pad1)") (class "Default")
      (node (ref "A307") (pin "1") (pinfunction "1_1") (pintype "passive"))
      (node (ref "A307") (pin "2") (pinfunction "2_2") (pintype "passive"))
      (node (ref "IC28") (pin "3") (pinfunction "3_3") (pintype "passive"))
    )
    (net (code "333") (name "Net-(A308-Pad1)") (class "Default")
      (node (ref "A308") (pin "1") (pinfunction "1_1") (pintype "passive"))
      (node (ref "A308") (pin "2") (pinfunction "2_2") (pintype "passive"))
      (node (ref "IC28") (pin "4") (pinfunction "4_4") (pintype "passive"))
    )
    (net (code "334") (name "Net-(A309-Pad1)") (class "Default")
      (node (ref "A309") (pin "1") (pinfunction "1_1") (pintype "passive"))
      (node (ref "A309") (pin "2") (pinfunction "2_2") (pintype "passive"))
      (node (ref "IC28") (pin "5") (pinfunction "5_5") (pintype "passive"))
    )
    (net (code "335") (name "Net-(A310-Pad1)") (class "Default")
      (node (ref "A310") (pin "1") (pinfunction "1_1") (pintype "passive"))
      (node (ref "A310") (pin "2") (pinfunction "2_2") (pintype "passive"))
      (node (ref "IC28") (pin "6") (pinfunction "6_6") (pintype "passive"))
    )
    (net (code "336") (name "Net-(A311-Pad1)") (class "Default")
      (node (ref "A311") (pin "1") (pinfunction "1_1") (pintype "passive"))
      (node (ref "A311") (pin "2") (pinfunction "2_2") (pintype "passive"))
      (node (ref "IC28") (pin "7") (pinfunction "7_7") (pintype "passive"))
    )
    (net (code "337") (name "Net-(A312-Pad1)") (class "Default")
      (node (ref "A312") (pin "1") (pinfunction "1_1") (pintype "passive"))
      (node (ref "A312") (pin "2") (pinfunction "2_2") (pintype "passive"))
      (node (ref "IC28") (pin "8") (pinfunction "8_8") (pintype "passive"))
    )
    (net (code "338") (name "Net-(A313-Pad1)") (class "Default")
      (node (ref "A313") (pin "1") (pinfunction "1_1") (pintype "passive"))
      (node (ref "A313") (pin "2") (pinfunction "2_2") (pintype "passive"))
      (node (ref "IC28") (pin "9") (pinfunction "9_9") (pintype "passive"))
    )
    (net (code "339") (name "Net-(A314-Pad1)") (class "Default")
      (node (ref "A314") (pin "1") (pinfunction "1_1") (pintype "passive"))
      (node (ref "A314") (pin "2") (pinfunction "2_2") (pintype "passive"))
      (node (ref "IC28") (pin "10") (pinfunction "10_10") (pintype "passive"))
    )
    (net (code "340") (name "Net-(A315-Pad1)") (class "Default")
      (node (ref "A315") (pin "1") (pinfunction "1_1") (pintype "passive"))
      (node (ref "A315") (pin "2") (pinfunction "2_2") (pintype "passive"))
      (node (ref "IC28") (pin "11") (pinfunction "11_11") (pintype "passive"))
    )
    (net (code "341") (name "Net-(A316-Pad1)") (class "Default")
      (node (ref "A316") (pin "1") (pinfunction "1_1") (pintype "passive"))
      (node (ref "A316") (pin "2") (pinfunction "2_2") (pintype "passive"))
      (node (ref "IC28") (pin "12") (pinfunction "12_12") (pintype "passive"))
    )
    (net (code "342") (name "Net-(A317-Pad1)") (class "Default")
      (node (ref "A317") (pin "1") (pinfunction "1_1") (pintype "passive"))
      (node (ref "A317") (pin "2") (pinfunction "2_2") (pintype "passive"))
      (node (ref "IC28") (pin "13") (pinfunction "13_13") (pintype "passive"))
    )
    (net (code "343") (name "Net-(A318-Pad1)") (class "Default")
      (node (ref "A318") (pin "1") (pinfunction "1_1") (pintype "passive"))
      (node (ref "A318") (pin "2") (pinfunction "2_2") (pintype "passive"))
      (node (ref "IC28") (pin "14") (pinfunction "14_14") (pintype "passive"))
    )
    (net (code "344") (name "Net-(A319-Pad1)") (class "Default")
      (node (ref "A319") (pin "1") (pinfunction "1_1") (pintype "passive"))
      (node (ref "A319") (pin "2") (pinfunction "2_2") (pintype "passive"))
      (node (ref "IC28") (pin "15") (pinfunction "15_15") (pintype "passive"))
    )
    (net (code "345") (name "Net-(A320-Pad1)") (class "Default")
      (node (ref "A320") (pin "1") (pinfunction "1_1") (pintype "passive"))
      (node (ref "A320") (pin "2") (pinfunction "2_2") (pintype "passive"))
      (node (ref "IC28") (pin "16") (pinfunction "16_16") (pintype "passive"))
    )
    (net (code "346") (name "Net-(A321-Pad1)") (class "Default")
      (node (ref "A321") (pin "1") (pinfunction "1_1") (pintype "passive"))
      (node (ref "A321") (pin "2") (pinfunction "2_2") (pintype "passive"))
      (node (ref "IC29") (pin "1") (pinfunction "1_1") (pintype "passive"))
    )
    (net (code "347") (name "Net-(A322-Pad1)") (class "Default")
      (node (ref "A322") (pin "1") (pinfunction "1_1") (pintype "passive"))
      (node (ref "A322") (pin "2") (pinfunction "2_2") (pintype "passive"))
      (node (ref "IC29") (pin "2") (pinfunction "2_2") (pintype "passive"))
    )
    (net (code "348") (name "Net-(A323-Pad1)") (class "Default")
      (node (ref "A323") (pin "1") (pinfunction "1_1") (pintype "passive"))
      (node (ref "A323") (pin "2") (pinfunction "2_2") (pintype "passive"))
      (node (ref "IC29") (pin "3") (pinfunction "3_3") (pintype "passive"))
    )
    (net (code "349") (name "Net-(A324-Pad1)") (class "Default")
      (node (ref "A324") (pin "1") (pinfunction "1_1") (pintype "passive"))
      (node (ref "A324") (pin "2") (pinfunction "2_2") (pintype "passive"))
      (node (ref "IC29") (pin "4") (pinfunction "4_4") (pintype "passive"))
    )
    (net (code "350") (name "Net-(A325-Pad1)") (class "Default")
      (node (ref "A325") (pin "1") (pinfunction "1_1") (pintype "passive"))
      (node (ref "A325") (pin "2") (pinfunction "2_2") (pintype "passive"))
      (node (ref "IC29") (pin "5") (pinfunction "5_5") (pintype "passive"))
    )
    (net (code "351") (name "Net-(A326-Pad1)") (class "Default")
      (node (ref "A326") (pin "1") (pinfunction "1_1") (pintype "passive"))
      (node (ref "A326") (pin "2") (pinfunction "2_2") (pintype "passive"))
      (node (ref "IC29") (pin "6") (pinfunction "6_6") (pintype "passive"))
    )
    (net (code "352") (name "Net-(A327-Pad1)") (class "Default")
      (node (ref "A327") (pin "1") (pinfunction "1_1") (pintype "passive"))
      (node (ref "A327") (pin "2") (pinfunction "2_2") (pintype "passive"))
      (node (ref "IC29") (pin "7") (pinfunction "7_7") (pintype "passive"))
    )
    (net (code "353") (name "Net-(A328-Pad1)") (class "Default")
      (node (ref "A328") (pin "1") (pinfunction "1_1") (pintype "passive"))
      (node (ref "A328") (pin "2") (pinfunction "2_2") (pintype "passive"))
      (node (ref "IC29") (pin "8") (pinfunction "8_8") (pintype "passive"))
    )
    (net (code "354") (name "Net-(A329-Pad1)") (class "Default")
      (node (ref "A329") (pin "1") (pinfunction "1_1") (pintype "passive"))
      (node (ref "A329") (pin "2") (pinfunction "2_2") (pintype "passive"))
      (node (ref "IC29") (pin "9") (pinfunction "9_9") (pintype "passive"))
    )
    (net (code "355") (name "Net-(A330-Pad1)") (class "Default")
      (node (ref "A330") (pin "1") (pinfunction "1_1") (pintype "passive"))
      (node (ref "A330") (pin "2") (pinfunction "2_2") (pintype "passive"))
      (node (ref "IC29") (pin "10") (pinfunction "10_10") (pintype "passive"))
    )
    (net (code "356") (name "Net-(A331-Pad1)") (class "Default")
      (node (ref "A331") (pin "1") (pinfunction "1_1") (pintype "passive"))
      (node (ref "A331") (pin "2") (pinfunction "2_2") (pintype "passive"))
      (node (ref "IC29") (pin "11") (pinfunction "11_11") (pintype "passive"))
    )
    (net (code "357") (name "Net-(A332-Pad1)") (class "Default")
      (node (ref "A332") (pin "1") (pinfunction "1_1") (pintype "passive"))
      (node (ref "A332") (pin "2") (pinfunction "2_2") (pintype "passive"))
      (node (ref "IC29") (pin "12") (pinfunction "12_12") (pintype "passive"))
    )
    (net (code "358") (name "Net-(A333-Pad1)") (class "Default")
      (node (ref "A333") (pin "1") (pinfunction "1_1") (pintype "passive"))
      (node (ref "A333") (pin "2") (pinfunction "2_2") (pintype "passive"))
      (node (ref "IC29") (pin "13") (pinfunction "13_13") (pintype "passive"))
    )
    (net (code "359") (name "Net-(A334-Pad1)") (class "Default")
      (node (ref "A334") (pin "1") (pinfunction "1_1") (pintype "passive"))
      (node (ref "A334") (pin "2") (pinfunction "2_2") (pintype "passive"))
      (node (ref "IC29") (pin "14") (pinfunction "14_14") (pintype "passive"))
    )
    (net (code "360") (name "Net-(A335-Pad1)") (class "Default")
      (node (ref "A335") (pin "1") (pinfunction "1_1") (pintype "passive"))
      (node (ref "A335") (pin "2") (pinfunction "2_2") (pintype "passive"))
      (node (ref "IC29") (pin "15") (pinfunction "15_15") (pintype "passive"))
    )
    (net (code "361") (name "Net-(A336-Pad1)") (class "Default")
      (node (ref "A336") (pin "1") (pinfunction "1_1") (pintype "passive"))
      (node (ref "A336") (pin "2") (pinfunction "2_2") (pintype "passive"))
      (node (ref "IC29") (pin "16") (pinfunction "16_16") (pintype "passive"))
    )
    (net (code "362") (name "Net-(A337-Pad1)") (class "Default")
      (node (ref "A337") (pin "1") (pinfunction "1_1") (pintype "passive"))
      (node (ref "A337") (pin "2") (pinfunction "2_2") (pintype "passive"))
      (node (ref "IC30") (pin "1") (pinfunction "1_1") (pintype "passive"))
    )
    (net (code "363") (name "Net-(A338-Pad1)") (class "Default")
      (node (ref "A338") (pin "1") (pinfunction "1_1") (pintype "passive"))
      (node (ref "A338") (pin "2") (pinfunction "2_2") (pintype "passive"))
      (node (ref "IC30") (pin "2") (pinfunction "2_2") (pintype "passive"))
    )
    (net (code "364") (name "Net-(A339-Pad1)") (class "Default")
      (node (ref "A339") (pin "1") (pinfunction "1_1") (pintype "passive"))
      (node (ref "A339") (pin "2") (pinfunction "2_2") (pintype "passive"))
      (node (ref "IC30") (pin "3") (pinfunction "3_3") (pintype "passive"))
    )
    (net (code "365") (name "Net-(A340-Pad1)") (class "Default")
      (node (ref "A340") (pin "1") (pinfunction "1_1") (pintype "passive"))
      (node (ref "A340") (pin "2") (pinfunction "2_2") (pintype "passive"))
      (node (ref "IC30") (pin "4") (pinfunction "4_4") (pintype "passive"))
    )
    (net (code "366") (name "Net-(A341-Pad1)") (class "Default")
      (node (ref "A341") (pin "1") (pinfunction "1_1") (pintype "passive"))
      (node (ref "A341") (pin "2") (pinfunction "2_2") (pintype "passive"))
      (node (ref "IC30") (pin "5") (pinfunction "5_5") (pintype "passive"))
    )
    (net (code "367") (name "Net-(A342-Pad1)") (class "Default")
      (node (ref "A342") (pin "1") (pinfunction "1_1") (pintype "passive"))
      (node (ref "A342") (pin "2") (pinfunction "2_2") (pintype "passive"))
      (node (ref "IC30") (pin "6") (pinfunction "6_6") (pintype "passive"))
    )
    (net (code "368") (name "Net-(A343-Pad1)") (class "Default")
      (node (ref "A343") (pin "1") (pinfunction "1_1") (pintype "passive"))
      (node (ref "A343") (pin "2") (pinfunction "2_2") (pintype "passive"))
      (node (ref "IC30") (pin "7") (pinfunction "7_7") (pintype "passive"))
    )
    (net (code "369") (name "Net-(A344-Pad1)") (class "Default")
      (node (ref "A344") (pin "1") (pinfunction "1_1") (pintype "passive"))
      (node (ref "A344") (pin "2") (pinfunction "2_2") (pintype "passive"))
      (node (ref "IC30") (pin "8") (pinfunction "8_8") (pintype "passive"))
    )
    (net (code "370") (name "Net-(A345-Pad1)") (class "Default")
      (node (ref "A345") (pin "1") (pinfunction "1_1") (pintype "passive"))
      (node (ref "A345") (pin "2") (pinfunction "2_2") (pintype "passive"))
      (node (ref "IC30") (pin "9") (pinfunction "9_9") (pintype "passive"))
    )
    (net (code "371") (name "Net-(A346-Pad1)") (class "Default")
      (node (ref "A346") (pin "1") (pinfunction "1_1") (pintype "passive"))
      (node (ref "A346") (pin "2") (pinfunction "2_2") (pintype "passive"))
      (node (ref "IC30") (pin "10") (pinfunction "10_10") (pintype "passive"))
    )
    (net (code "372") (name "Net-(A347-Pad1)") (class "Default")
      (node (ref "A347") (pin "1") (pinfunction "1_1") (pintype "passive"))
      (node (ref "A347") (pin "2") (pinfunction "2_2") (pintype "passive"))
      (node (ref "IC30") (pin "11") (pinfunction "11_11") (pintype "passive"))
    )
    (net (code "373") (name "Net-(A348-Pad1)") (class "Default")
      (node (ref "A348") (pin "1") (pinfunction "1_1") (pintype "passive"))
      (node (ref "A348") (pin "2") (pinfunction "2_2") (pintype "passive"))
      (node (ref "IC30") (pin "12") (pinfunction "12_12") (pintype "passive"))
    )
    (net (code "374") (name "Net-(A349-Pad1)") (class "Default")
      (node (ref "A349") (pin "1") (pinfunction "1_1") (pintype "passive"))
      (node (ref "A349") (pin "2") (pinfunction "2_2") (pintype "passive"))
      (node (ref "IC30") (pin "13") (pinfunction "13_13") (pintype "passive"))
    )
    (net (code "375") (name "Net-(A350-Pad1)") (class "Default")
      (node (ref "A350") (pin "1") (pinfunction "1_1") (pintype "passive"))
      (node (ref "A350") (pin "2") (pinfunction "2_2") (pintype "passive"))
      (node (ref "IC30") (pin "14") (pinfunction "14_14") (pintype "passive"))
    )
    (net (code "376") (name "Net-(A351-Pad1)") (class "Default")
      (node (ref "A351") (pin "1") (pinfunction "1_1") (pintype "passive"))
      (node (ref "A351") (pin "2") (pinfunction "2_2") (pintype "passive"))
      (node (ref "IC30") (pin "15") (pinfunction "15_15") (pintype "passive"))
    )
    (net (code "377") (name "Net-(A352-Pad1)") (class "Default")
      (node (ref "A352") (pin "1") (pinfunction "1_1") (pintype "passive"))
      (node (ref "A352") (pin "2") (pinfunction "2_2") (pintype "passive"))
      (node (ref "IC30") (pin "16") (pinfunction "16_16") (pintype "passive"))
    )
    (net (code "378") (name "Net-(A353-Pad1)") (class "Default")
      (node (ref "A353") (pin "1") (pinfunction "1_1") (pintype "passive"))
      (node (ref "A353") (pin "2") (pinfunction "2_2") (pintype "passive"))
      (node (ref "IC31") (pin "1") (pinfunction "1_1") (pintype "passive"))
    )
    (net (code "379") (name "Net-(A354-Pad1)") (class "Default")
      (node (ref "A354") (pin "1") (pinfunction "1_1") (pintype "passive"))
      (node (ref "A354") (pin "2") (pinfunction "2_2") (pintype "passive"))
      (node (ref "IC31") (pin "2") (pinfunction "2_2") (pintype "passive"))
    )
    (net (code "380") (name "Net-(A355-Pad1)") (class "Default")
      (node (ref "A355") (pin "1") (pinfunction "1_1") (pintype "passive"))
      (node (ref "A355") (pin "2") (pinfunction "2_2") (pintype "passive"))
      (node (ref "IC31") (pin "3") (pinfunction "3_3") (pintype "passive"))
    )
    (net (code "381") (name "Net-(A356-Pad1)") (class "Default")
      (node (ref "A356") (pin "1") (pinfunction "1_1") (pintype "passive"))
      (node (ref "A356") (pin "2") (pinfunction "2_2") (pintype "passive"))
      (node (ref "IC31") (pin "4") (pinfunction "4_4") (pintype "passive"))
    )
    (net (code "382") (name "Net-(A357-Pad1)") (class "Default")
      (node (ref "A357") (pin "1") (pinfunction "1_1") (pintype "passive"))
      (node (ref "A357") (pin "2") (pinfunction "2_2") (pintype "passive"))
      (node (ref "IC31") (pin "5") (pinfunction "5_5") (pintype "passive"))
    )
    (net (code "383") (name "Net-(A358-Pad1)") (class "Default")
      (node (ref "A358") (pin "1") (pinfunction "1_1") (pintype "passive"))
      (node (ref "A358") (pin "2") (pinfunction "2_2") (pintype "passive"))
      (node (ref "IC31") (pin "6") (pinfunction "6_6") (pintype "passive"))
    )
    (net (code "384") (name "Net-(A359-Pad1)") (class "Default")
      (node (ref "A359") (pin "1") (pinfunction "1_1") (pintype "passive"))
      (node (ref "A359") (pin "2") (pinfunction "2_2") (pintype "passive"))
      (node (ref "IC31") (pin "7") (pinfunction "7_7") (pintype "passive"))
    )
    (net (code "385") (name "Net-(A360-Pad1)") (class "Default")
      (node (ref "A360") (pin "1") (pinfunction "1_1") (pintype "passive"))
      (node (ref "A360") (pin "2") (pinfunction "2_2") (pintype "passive"))
      (node (ref "IC31") (pin "8") (pinfunction "8_8") (pintype "passive"))
    )
    (net (code "386") (name "Net-(A361-Pad1)") (class "Default")
      (node (ref "A361") (pin "1") (pinfunction "1_1") (pintype "passive"))
      (node (ref "A361") (pin "2") (pinfunction "2_2") (pintype "passive"))
      (node (ref "IC31") (pin "9") (pinfunction "9_9") (pintype "passive"))
    )
    (net (code "387") (name "Net-(A362-Pad1)") (class "Default")
      (node (ref "A362") (pin "1") (pinfunction "1_1") (pintype "passive"))
      (node (ref "A362") (pin "2") (pinfunction "2_2") (pintype "passive"))
      (node (ref "IC31") (pin "10") (pinfunction "10_10") (pintype "passive"))
    )
    (net (code "388") (name "Net-(A363-Pad1)") (class "Default")
      (node (ref "A363") (pin "1") (pinfunction "1_1") (pintype "passive"))
      (node (ref "A363") (pin "2") (pinfunction "2_2") (pintype "passive"))
      (node (ref "IC31") (pin "11") (pinfunction "11_11") (pintype "passive"))
    )
    (net (code "389") (name "Net-(A364-Pad1)") (class "Default")
      (node (ref "A364") (pin "1") (pinfunction "1_1") (pintype "passive"))
      (node (ref "A364") (pin "2") (pinfunction "2_2") (pintype "passive"))
      (node (ref "IC31") (pin "12") (pinfunction "12_12") (pintype "passive"))
    )
    (net (code "390") (name "Net-(A365-Pad1)") (class "Default")
      (node (ref "A365") (pin "1") (pinfunction "1_1") (pintype "passive"))
      (node (ref "A365") (pin "2") (pinfunction "2_2") (pintype "passive"))
      (node (ref "IC31") (pin "13") (pinfunction "13_13") (pintype "passive"))
    )
    (net (code "391") (name "Net-(A366-Pad1)") (class "Default")
      (node (ref "A366") (pin "1") (pinfunction "1_1") (pintype "passive"))
      (node (ref "A366") (pin "2") (pinfunction "2_2") (pintype "passive"))
      (node (ref "IC31") (pin "14") (pinfunction "14_14") (pintype "passive"))
    )
    (net (code "392") (name "Net-(A367-Pad1)") (class "Default")
      (node (ref "A367") (pin "1") (pinfunction "1_1") (pintype "passive"))
      (node (ref "A367") (pin "2") (pinfunction "2_2") (pintype "passive"))
      (node (ref "IC31") (pin "15") (pinfunction "15_15") (pintype "passive"))
    )
    (net (code "393") (name "Net-(A368-Pad1)") (class "Default")
      (node (ref "A368") (pin "1") (pinfunction "1_1") (pintype "passive"))
      (node (ref "A368") (pin "2") (pinfunction "2_2") (pintype "passive"))
      (node (ref "IC31") (pin "16") (pinfunction "16_16") (pintype "passive"))
    )
    (net (code "394") (name "Net-(A369-Pad1)") (class "Default")
      (node (ref "A369") (pin "1") (pinfunction "1_1") (pintype "passive"))
      (node (ref "A369") (pin "2") (pinfunction "2_2") (pintype "passive"))
      (node (ref "IC32") (pin "1") (pinfunction "1_1") (pintype "passive"))
    )
    (net (code "395") (name "Net-(A370-Pad1)") (class "Default")
      (node (ref "A370") (pin "1") (pinfunction "1_1") (pintype "passive"))
      (node (ref "A370") (pin "2") (pinfunction "2_2") (pintype "passive"))
      (node (ref "IC32") (pin "2") (pinfunction "2_2") (pintype "passive"))
    )
    (net (code "396") (name "Net-(A371-Pad1)") (class "Default")
      (node (ref "A371") (pin "1") (pinfunction "1_1") (pintype "passive"))
      (node (ref "A371") (pin "2") (pinfunction "2_2") (pintype "passive"))
      (node (ref "IC32") (pin "3") (pinfunction "3_3") (pintype "passive"))
    )
    (net (code "397") (name "Net-(A372-Pad1)") (class "Default")
      (node (ref "A372") (pin "1") (pinfunction "1_1") (pintype "passive"))
      (node (ref "A372") (pin "2") (pinfunction "2_2") (pintype "passive"))
      (node (ref "IC32") (pin "4") (pinfunction "4_4") (pintype "passive"))
    )
    (net (code "398") (name "Net-(A373-Pad1)") (class "Default")
      (node (ref "A373") (pin "1") (pinfunction "1_1") (pintype "passive"))
      (node (ref "A373") (pin "2") (pinfunction "2_2") (pintype "passive"))
      (node (ref "IC32") (pin "5") (pinfunction "5_5") (pintype "passive"))
    )
    (net (code "399") (name "Net-(A374-Pad1)") (class "Default")
      (node (ref "A374") (pin "1") (pinfunction "1_1") (pintype "passive"))
      (node (ref "A374") (pin "2") (pinfunction "2_2") (pintype "passive"))
      (node (ref "IC32") (pin "6") (pinfunction "6_6") (pintype "passive"))
    )
    (net (code "400") (name "Net-(A375-Pad1)") (class "Default")
      (node (ref "A375") (pin "1") (pinfunction "1_1") (pintype "passive"))
      (node (ref "A375") (pin "2") (pinfunction "2_2") (pintype "passive"))
      (node (ref "IC32") (pin "7") (pinfunction "7_7") (pintype "passive"))
    )
    (net (code "401") (name "Net-(A376-Pad1)") (class "Default")
      (node (ref "A376") (pin "1") (pinfunction "1_1") (pintype "passive"))
      (node (ref "A376") (pin "2") (pinfunction "2_2") (pintype "passive"))
      (node (ref "IC32") (pin "8") (pinfunction "8_8") (pintype "passive"))
    )
    (net (code "402") (name "Net-(A377-Pad1)") (class "Default")
      (node (ref "A377") (pin "1") (pinfunction "1_1") (pintype "passive"))
      (node (ref "A377") (pin "2") (pinfunction "2_2") (pintype "passive"))
      (node (ref "IC32") (pin "9") (pinfunction "9_9") (pintype "passive"))
    )
    (net (code "403") (name "Net-(A378-Pad1)") (class "Default")
      (node (ref "A378") (pin "1") (pinfunction "1_1") (pintype "passive"))
      (node (ref "A378") (pin "2") (pinfunction "2_2") (pintype "passive"))
      (node (ref "IC32") (pin "10") (pinfunction "10_10") (pintype "passive"))
    )
    (net (code "404") (name "Net-(A379-Pad1)") (class "Default")
      (node (ref "A379") (pin "1") (pinfunction "1_1") (pintype "passive"))
      (node (ref "A379") (pin "2") (pinfunction "2_2") (pintype "passive"))
      (node (ref "IC32") (pin "11") (pinfunction "11_11") (pintype "passive"))
    )
    (net (code "405") (name "Net-(A380-Pad1)") (class "Default")
      (node (ref "A380") (pin "1") (pinfunction "1_1") (pintype "passive"))
      (node (ref "A380") (pin "2") (pinfunction "2_2") (pintype "passive"))
      (node (ref "IC32") (pin "12") (pinfunction "12_12") (pintype "passive"))
    )
    (net (code "406") (name "Net-(A381-Pad1)") (class "Default")
      (node (ref "A381") (pin "1") (pinfunction "1_1") (pintype "passive"))
      (node (ref "A381") (pin "2") (pinfunction "2_2") (pintype "passive"))
      (node (ref "IC32") (pin "13") (pinfunction "13_13") (pintype "passive"))
    )
    (net (code "407") (name "Net-(A382-Pad1)") (class "Default")
      (node (ref "A382") (pin "1") (pinfunction "1_1") (pintype "passive"))
      (node (ref "A382") (pin "2") (pinfunction "2_2") (pintype "passive"))
      (node (ref "IC32") (pin "14") (pinfunction "14_14") (pintype "passive"))
    )
    (net (code "408") (name "Net-(A383-Pad1)") (class "Default")
      (node (ref "A383") (pin "1") (pinfunction "1_1") (pintype "passive"))
      (node (ref "A383") (pin "2") (pinfunction "2_2") (pintype "passive"))
      (node (ref "IC32") (pin "15") (pinfunction "15_15") (pintype "passive"))
    )
    (net (code "409") (name "Net-(A384-Pad1)") (class "Default")
      (node (ref "A384") (pin "1") (pinfunction "1_1") (pintype "passive"))
      (node (ref "A384") (pin "2") (pinfunction "2_2") (pintype "passive"))
      (node (ref "IC32") (pin "16") (pinfunction "16_16") (pintype "passive"))
    )
    (net (code "410") (name "Net-(A385-Pad1)") (class "Default")
      (node (ref "A385") (pin "1") (pinfunction "1_1") (pintype "passive"))
      (node (ref "A385") (pin "2") (pinfunction "2_2") (pintype "passive"))
      (node (ref "IC33") (pin "1") (pinfunction "1_1") (pintype "passive"))
    )
    (net (code "411") (name "Net-(A386-Pad1)") (class "Default")
      (node (ref "A386") (pin "1") (pinfunction "1_1") (pintype "passive"))
      (node (ref "A386") (pin "2") (pinfunction "2_2") (pintype "passive"))
      (node (ref "IC33") (pin "2") (pinfunction "2_2") (pintype "passive"))
    )
    (net (code "412") (name "Net-(A387-Pad1)") (class "Default")
      (node (ref "A387") (pin "1") (pinfunction "1_1") (pintype "passive"))
      (node (ref "A387") (pin "2") (pinfunction "2_2") (pintype "passive"))
      (node (ref "IC33") (pin "3") (pinfunction "3_3") (pintype "passive"))
    )
    (net (code "413") (name "Net-(A388-Pad1)") (class "Default")
      (node (ref "A388") (pin "1") (pinfunction "1_1") (pintype "passive"))
      (node (ref "A388") (pin "2") (pinfunction "2_2") (pintype "passive"))
      (node (ref "IC33") (pin "4") (pinfunction "4_4") (pintype "passive"))
    )
    (net (code "414") (name "Net-(A389-Pad1)") (class "Default")
      (node (ref "A389") (pin "1") (pinfunction "1_1") (pintype "passive"))
      (node (ref "A389") (pin "2") (pinfunction "2_2") (pintype "passive"))
      (node (ref "IC33") (pin "5") (pinfunction "5_5") (pintype "passive"))
    )
    (net (code "415") (name "Net-(A390-Pad1)") (class "Default")
      (node (ref "A390") (pin "1") (pinfunction "1_1") (pintype "passive"))
      (node (ref "A390") (pin "2") (pinfunction "2_2") (pintype "passive"))
      (node (ref "IC33") (pin "6") (pinfunction "6_6") (pintype "passive"))
    )
    (net (code "416") (name "Net-(A391-Pad1)") (class "Default")
      (node (ref "A391") (pin "1") (pinfunction "1_1") (pintype "passive"))
      (node (ref "A391") (pin "2") (pinfunction "2_2") (pintype "passive"))
      (node (ref "IC33") (pin "7") (pinfunction "7_7") (pintype "passive"))
    )
    (net (code "417") (name "Net-(A392-Pad1)") (class "Default")
      (node (ref "A392") (pin "1") (pinfunction "1_1") (pintype "passive"))
      (node (ref "A392") (pin "2") (pinfunction "2_2") (pintype "passive"))
      (node (ref "IC33") (pin "8") (pinfunction "8_8") (pintype "passive"))
    )
    (net (code "418") (name "Net-(A393-Pad1)") (class "Default")
      (node (ref "A393") (pin "1") (pinfunction "1_1") (pintype "passive"))
      (node (ref "A393") (pin "2") (pinfunction "2_2") (pintype "passive"))
      (node (ref "IC33") (pin "9") (pinfunction "9_9") (pintype "passive"))
    )
    (net (code "419") (name "Net-(A394-Pad1)") (class "Default")
      (node (ref "A394") (pin "1") (pinfunction "1_1") (pintype "passive"))
      (node (ref "A394") (pin "2") (pinfunction "2_2") (pintype "passive"))
      (node (ref "IC33") (pin "10") (pinfunction "10_10") (pintype "passive"))
    )
    (net (code "420") (name "Net-(A395-Pad1)") (class "Default")
      (node (ref "A395") (pin "1") (pinfunction "1_1") (pintype "passive"))
      (node (ref "A395") (pin "2") (pinfunction "2_2") (pintype "passive"))
      (node (ref "IC33") (pin "11") (pinfunction "11_11") (pintype "passive"))
    )
    (net (code "421") (name "Net-(A396-Pad1)") (class "Default")
      (node (ref "A396") (pin "1") (pinfunction "1_1") (pintype "passive"))
      (node (ref "A396") (pin "2") (pinfunction "2_2") (pintype "passive"))
      (node (ref "IC33") (pin "12") (pinfunction "12_12") (pintype "passive"))
    )
    (net (code "422") (name "Net-(A397-Pad1)") (class "Default")
      (node (ref "A397") (pin "1") (pinfunction "1_1") (pintype "passive"))
      (node (ref "A397") (pin "2") (pinfunction "2_2") (pintype "passive"))
      (node (ref "IC33") (pin "13") (pinfunction "13_13") (pintype "passive"))
    )
    (net (code "423") (name "Net-(A398-Pad1)") (class "Default")
      (node (ref "A398") (pin "1") (pinfunction "1_1") (pintype "passive"))
      (node (ref "A398") (pin "2") (pinfunction "2_2") (pintype "passive"))
      (node (ref "IC33") (pin "14") (pinfunction "14_14") (pintype "passive"))
    )
    (net (code "424") (name "Net-(A399-Pad1)") (class "Default")
      (node (ref "A399") (pin "1") (pinfunction "1_1") (pintype "passive"))
      (node (ref "A399") (pin "2") (pinfunction "2_2") (pintype "passive"))
      (node (ref "IC33") (pin "15") (pinfunction "15_15") (pintype "passive"))
    )
    (net (code "425") (name "Net-(A400-Pad1)") (class "Default")
      (node (ref "A400") (pin "1") (pinfunction "1_1") (pintype "passive"))
      (node (ref "A400") (pin "2") (pinfunction "2_2") (pintype "passive"))
      (node (ref "IC33") (pin "16") (pinfunction "16_16") (pintype "passive"))
    )
    (net (code "426") (name "Net-(A401-Pad1)") (class "Default")
      (node (ref "A401") (pin "1") (pinfunction "1_1") (pintype "passive"))
      (node (ref "A401") (pin "2") (pinfunction "2_2") (pintype "passive"))
      (node (ref "IC34") (pin "1") (pinfunction "1_1") (pintype "passive"))
    )
    (net (code "427") (name "Net-(A402-Pad1)") (class "Default")
      (node (ref "A402") (pin "1") (pinfunction "1_1") (pintype "passive"))
      (node (ref "A402") (pin "2") (pinfunction "2_2") (pintype "passive"))
      (node (ref "IC34") (pin "2") (pinfunction "2_2") (pintype "passive"))
    )
    (net (code "428") (name "Net-(A403-Pad1)") (class "Default")
      (node (ref "A403") (pin "1") (pinfunction "1_1") (pintype "passive"))
      (node (ref "A403") (pin "2") (pinfunction "2_2") (pintype "passive"))
      (node (ref "IC34") (pin "3") (pinfunction "3_3") (pintype "passive"))
    )
    (net (code "429") (name "Net-(A404-Pad1)") (class "Default")
      (node (ref "A404") (pin "1") (pinfunction "1_1") (pintype "passive"))
      (node (ref "A404") (pin "2") (pinfunction "2_2") (pintype "passive"))
      (node (ref "IC34") (pin "4") (pinfunction "4_4") (pintype "passive"))
    )
    (net (code "430") (name "Net-(A405-Pad1)") (class "Default")
      (node (ref "A405") (pin "1") (pinfunction "1_1") (pintype "passive"))
      (node (ref "A405") (pin "2") (pinfunction "2_2") (pintype "passive"))
      (node (ref "IC34") (pin "5") (pinfunction "5_5") (pintype "passive"))
    )
    (net (code "431") (name "Net-(A406-Pad1)") (class "Default")
      (node (ref "A406") (pin "1") (pinfunction "1_1") (pintype "passive"))
      (node (ref "A406") (pin "2") (pinfunction "2_2") (pintype "passive"))
      (node (ref "IC34") (pin "6") (pinfunction "6_6") (pintype "passive"))
    )
    (net (code "432") (name "Net-(A407-Pad1)") (class "Default")
      (node (ref "A407") (pin "1") (pinfunction "1_1") (pintype "passive"))
      (node (ref "A407") (pin "2") (pinfunction "2_2") (pintype "passive"))
      (node (ref "IC34") (pin "7") (pinfunction "7_7") (pintype "passive"))
    )
    (net (code "433") (name "Net-(A408-Pad1)") (class "Default")
      (node (ref "A408") (pin "1") (pinfunction "1_1") (pintype "passive"))
      (node (ref "A408") (pin "2") (pinfunction "2_2") (pintype "passive"))
      (node (ref "IC34") (pin "8") (pinfunction "8_8") (pintype "passive"))
    )
    (net (code "434") (name "Net-(A409-Pad1)") (class "Default")
      (node (ref "A409") (pin "1") (pinfunction "1_1") (pintype "passive"))
      (node (ref "A409") (pin "2") (pinfunction "2_2") (pintype "passive"))
      (node (ref "IC34") (pin "9") (pinfunction "9_9") (pintype "passive"))
    )
    (net (code "435") (name "Net-(A410-Pad1)") (class "Default")
      (node (ref "A410") (pin "1") (pinfunction "1_1") (pintype "passive"))
      (node (ref "A410") (pin "2") (pinfunction "2_2") (pintype "passive"))
      (node (ref "IC34") (pin "10") (pinfunction "10_10") (pintype "passive"))
    )
    (net (code "436") (name "Net-(A411-Pad1)") (class "Default")
      (node (ref "A411") (pin "1") (pinfunction "1_1") (pintype "passive"))
      (node (ref "A411") (pin "2") (pinfunction "2_2") (pintype "passive"))
      (node (ref "IC34") (pin "11") (pinfunction "11_11") (pintype "passive"))
    )
    (net (code "437") (name "Net-(A412-Pad1)") (class "Default")
      (node (ref "A412") (pin "1") (pinfunction "1_1") (pintype "passive"))
      (node (ref "A412") (pin "2") (pinfunction "2_2") (pintype "passive"))
      (node (ref "IC34") (pin "12") (pinfunction "12_12") (pintype "passive"))
    )
    (net (code "438") (name "Net-(A413-Pad1)") (class "Default")
      (node (ref "A413") (pin "1") (pinfunction "1_1") (pintype "passive"))
      (node (ref "A413") (pin "2") (pinfunction "2_2") (pintype "passive"))
      (node (ref "IC34") (pin "13") (pinfunction "13_13") (pintype "passive"))
    )
    (net (code "439") (name "Net-(A414-Pad1)") (class "Default")
      (node (ref "A414") (pin "1") (pinfunction "1_1") (pintype "passive"))
      (node (ref "A414") (pin "2") (pinfunction "2_2") (pintype "passive"))
      (node (ref "IC34") (pin "14") (pinfunction "14_14") (pintype "passive"))
    )
    (net (code "440") (name "Net-(A415-Pad1)") (class "Default")
      (node (ref "A415") (pin "1") (pinfunction "1_1") (pintype "passive"))
      (node (ref "A415") (pin "2") (pinfunction "2_2") (pintype "passive"))
      (node (ref "IC34") (pin "15") (pinfunction "15_15") (pintype "passive"))
    )
    (net (code "441") (name "Net-(A416-Pad1)") (class "Default")
      (node (ref "A416") (pin "1") (pinfunction "1_1") (pintype "passive"))
      (node (ref "A416") (pin "2") (pinfunction "2_2") (pintype "passive"))
      (node (ref "IC34") (pin "16") (pinfunction "16_16") (pintype "passive"))
    )
    (net (code "442") (name "Net-(A417-Pad1)") (class "Default")
      (node (ref "A417") (pin "1") (pinfunction "1_1") (pintype "passive"))
      (node (ref "A417") (pin "2") (pinfunction "2_2") (pintype "passive"))
      (node (ref "IC35") (pin "1") (pinfunction "1_1") (pintype "passive"))
    )
    (net (code "443") (name "Net-(A418-Pad1)") (class "Default")
      (node (ref "A418") (pin "1") (pinfunction "1_1") (pintype "passive"))
      (node (ref "A418") (pin "2") (pinfunction "2_2") (pintype "passive"))
      (node (ref "IC35") (pin "2") (pinfunction "2_2") (pintype "passive"))
    )
    (net (code "444") (name "Net-(A419-Pad1)") (class "Default")
      (node (ref "A419") (pin "1") (pinfunction "1_1") (pintype "passive"))
      (node (ref "A419") (pin "2") (pinfunction "2_2") (pintype "passive"))
      (node (ref "IC35") (pin "3") (pinfunction "3_3") (pintype "passive"))
    )
    (net (code "445") (name "Net-(A420-Pad1)") (class "Default")
      (node (ref "A420") (pin "1") (pinfunction "1_1") (pintype "passive"))
      (node (ref "A420") (pin "2") (pinfunction "2_2") (pintype "passive"))
      (node (ref "IC35") (pin "4") (pinfunction "4_4") (pintype "passive"))
    )
    (net (code "446") (name "Net-(A421-Pad1)") (class "Default")
      (node (ref "A421") (pin "1") (pinfunction "1_1") (pintype "passive"))
      (node (ref "A421") (pin "2") (pinfunction "2_2") (pintype "passive"))
      (node (ref "IC35") (pin "5") (pinfunction "5_5") (pintype "passive"))
    )
    (net (code "447") (name "Net-(A422-Pad1)") (class "Default")
      (node (ref "A422") (pin "1") (pinfunction "1_1") (pintype "passive"))
      (node (ref "A422") (pin "2") (pinfunction "2_2") (pintype "passive"))
      (node (ref "IC35") (pin "6") (pinfunction "6_6") (pintype "passive"))
    )
    (net (code "448") (name "Net-(A423-Pad1)") (class "Default")
      (node (ref "A423") (pin "1") (pinfunction "1_1") (pintype "passive"))
      (node (ref "A423") (pin "2") (pinfunction "2_2") (pintype "passive"))
      (node (ref "IC35") (pin "7") (pinfunction "7_7") (pintype "passive"))
    )
    (net (code "449") (name "Net-(A424-Pad1)") (class "Default")
      (node (ref "A424") (pin "1") (pinfunction "1_1") (pintype "passive"))
      (node (ref "A424") (pin "2") (pinfunction "2_2") (pintype "passive"))
      (node (ref "IC35") (pin "8") (pinfunction "8_8") (pintype "passive"))
    )
    (net (code "450") (name "Net-(A425-Pad1)") (class "Default")
      (node (ref "A425") (pin "1") (pinfunction "1_1") (pintype "passive"))
      (node (ref "A425") (pin "2") (pinfunction "2_2") (pintype "passive"))
      (node (ref "IC35") (pin "9") (pinfunction "9_9") (pintype "passive"))
    )
    (net (code "451") (name "Net-(A426-Pad1)") (class "Default")
      (node (ref "A426") (pin "1") (pinfunction "1_1") (pintype "passive"))
      (node (ref "A426") (pin "2") (pinfunction "2_2") (pintype "passive"))
      (node (ref "IC35") (pin "10") (pinfunction "10_10") (pintype "passive"))
    )
    (net (code "452") (name "Net-(A427-Pad1)") (class "Default")
      (node (ref "A427") (pin "1") (pinfunction "1_1") (pintype "passive"))
      (node (ref "A427") (pin "2") (pinfunction "2_2") (pintype "passive"))
      (node (ref "IC35") (pin "11") (pinfunction "11_11") (pintype "passive"))
    )
    (net (code "453") (name "Net-(A428-Pad1)") (class "Default")
      (node (ref "A428") (pin "1") (pinfunction "1_1") (pintype "passive"))
      (node (ref "A428") (pin "2") (pinfunction "2_2") (pintype "passive"))
      (node (ref "IC35") (pin "12") (pinfunction "12_12") (pintype "passive"))
    )
    (net (code "454") (name "Net-(A429-Pad1)") (class "Default")
      (node (ref "A429") (pin "1") (pinfunction "1_1") (pintype "passive"))
      (node (ref "A429") (pin "2") (pinfunction "2_2") (pintype "passive"))
      (node (ref "IC35") (pin "13") (pinfunction "13_13") (pintype "passive"))
    )
    (net (code "455") (name "Net-(A430-Pad1)") (class "Default")
      (node (ref "A430") (pin "1") (pinfunction "1_1") (pintype "passive"))
      (node (ref "A430") (pin "2") (pinfunction "2_2") (pintype "passive"))
      (node (ref "IC35") (pin "14") (pinfunction "14_14") (pintype "passive"))
    )
    (net (code "456") (name "Net-(A431-Pad1)") (class "Default")
      (node (ref "A431") (pin "1") (pinfunction "1_1") (pintype "passive"))
      (node (ref "A431") (pin "2") (pinfunction "2_2") (pintype "passive"))
      (node (ref "IC35") (pin "15") (pinfunction "15_15") (pintype "passive"))
    )
    (net (code "457") (name "Net-(A432-Pad1)") (class "Default")
      (node (ref "A432") (pin "1") (pinfunction "1_1") (pintype "passive"))
      (node (ref "A432") (pin "2") (pinfunction "2_2") (pintype "passive"))
      (node (ref "IC35") (pin "16") (pinfunction "16_16") (pintype "passive"))
    )
    (net (code "458") (name "Net-(A433-Pad1)") (class "Default")
      (node (ref "A433") (pin "1") (pinfunction "1_1") (pintype "passive"))
      (node (ref "A433") (pin "2") (pinfunction "2_2") (pintype "passive"))
      (node (ref "IC36") (pin "1") (pinfunction "1_1") (pintype "passive"))
    )
    (net (code "459") (name "Net-(A434-Pad1)") (class "Default")
      (node (ref "A434") (pin "1") (pinfunction "1_1") (pintype "passive"))
      (node (ref "A434") (pin "2") (pinfunction "2_2") (pintype "passive"))
      (node (ref "IC36") (pin "2") (pinfunction "2_2") (pintype "passive"))
    )
    (net (code "460") (name "Net-(A435-Pad1)") (class "Default")
      (node (ref "A435") (pin "1") (pinfunction "1_1") (pintype "passive"))
      (node (ref "A435") (pin "2") (pinfunction "2_2") (pintype "passive"))
      (node (ref "IC36") (pin "3") (pinfunction "3_3") (pintype "passive"))
    )
    (net (code "461") (name "Net-(A436-Pad1)") (class "Default")
      (node (ref "A436") (pin "1") (pinfunction "1_1") (pintype "passive"))
      (node (ref "A436") (pin "2") (pinfunction "2_2") (pintype "passive"))
      (node (ref "IC36") (pin "4") (pinfunction "4_4") (pintype "passive"))
    )
    (net (code "462") (name "Net-(A437-Pad1)") (class "Default")
      (node (ref "A437") (pin "1") (pinfunction "1_1") (pintype "passive"))
      (node (ref "A437") (pin "2") (pinfunction "2_2") (pintype "passive"))
      (node (ref "IC36") (pin "5") (pinfunction "5_5") (pintype "passive"))
    )
    (net (code "463") (name "Net-(A438-Pad1)") (class "Default")
      (node (ref "A438") (pin "1") (pinfunction "1_1") (pintype "passive"))
      (node (ref "A438") (pin "2") (pinfunction "2_2") (pintype "passive"))
      (node (ref "IC36") (pin "6") (pinfunction "6_6") (pintype "passive"))
    )
    (net (code "464") (name "Net-(A439-Pad1)") (class "Default")
      (node (ref "A439") (pin "1") (pinfunction "1_1") (pintype "passive"))
      (node (ref "A439") (pin "2") (pinfunction "2_2") (pintype "passive"))
      (node (ref "IC36") (pin "7") (pinfunction "7_7") (pintype "passive"))
    )
    (net (code "465") (name "Net-(A440-Pad1)") (class "Default")
      (node (ref "A440") (pin "1") (pinfunction "1_1") (pintype "passive"))
      (node (ref "A440") (pin "2") (pinfunction "2_2") (pintype "passive"))
      (node (ref "IC36") (pin "8") (pinfunction "8_8") (pintype "passive"))
    )
    (net (code "466") (name "Net-(A441-Pad1)") (class "Default")
      (node (ref "A441") (pin "1") (pinfunction "1_1") (pintype "passive"))
      (node (ref "A441") (pin "2") (pinfunction "2_2") (pintype "passive"))
      (node (ref "IC36") (pin "9") (pinfunction "9_9") (pintype "passive"))
    )
    (net (code "467") (name "Net-(A442-Pad1)") (class "Default")
      (node (ref "A442") (pin "1") (pinfunction "1_1") (pintype "passive"))
      (node (ref "A442") (pin "2") (pinfunction "2_2") (pintype "passive"))
      (node (ref "IC36") (pin "10") (pinfunction "10_10") (pintype "passive"))
    )
    (net (code "468") (name "Net-(A443-Pad1)") (class "Default")
      (node (ref "A443") (pin "1") (pinfunction "1_1") (pintype "passive"))
      (node (ref "A443") (pin "2") (pinfunction "2_2") (pintype "passive"))
      (node (ref "IC36") (pin "11") (pinfunction "11_11") (pintype "passive"))
    )
    (net (code "469") (name "Net-(A444-Pad1)") (class "Default")
      (node (ref "A444") (pin "1") (pinfunction "1_1") (pintype "passive"))
      (node (ref "A444") (pin "2") (pinfunction "2_2") (pintype "passive"))
      (node (ref "IC36") (pin "12") (pinfunction "12_12") (pintype "passive"))
    )
    (net (code "470") (name "Net-(A445-Pad1)") (class "Default")
      (node (ref "A445") (pin "1") (pinfunction "1_1") (pintype "passive"))
      (node (ref "A445") (pin "2") (pinfunction "2_2") (pintype "passive"))
      (node (ref "IC36") (pin "13") (pinfunction "13_13") (pintype "passive"))
    )
    (net (code "471") (name "Net-(A446-Pad1)") (class "Default")
      (node (ref "A446") (pin "1") (pinfunction "1_1") (pintype "passive"))
      (node (ref "A446") (pin "2") (pinfunction "2_2") (pintype "passive"))
      (node (ref "IC36") (pin "14") (pinfunction "14_14") (pintype "passive"))
    )
    (net (code "472") (name "Net-(A447-Pad1)") (class "Default")
      (node (ref "A447") (pin "1") (pinfunction "1_1") (pintype "passive"))
      (node (ref "A447") (pin "2") (pinfunction "2_2") (pintype "passive"))
      (node (ref "IC36") (pin "15") (pinfunction "15_15") (pintype "passive"))
    )
    (net (code "473") (name "Net-(A448-Pad1)") (class "Default")
      (node (ref "A448") (pin "1") (pinfunction "1_1") (pintype "passive"))
      (node (ref "A448") (pin "2") (pinfunction "2_2") (pintype "passive"))
      (node (ref "IC36") (pin "16") (pinfunction "16_16") (pintype "passive"))
    )
    (net (code "474") (name "Net-(B1-+-Pad+@1)") (class "Default")
      (node (ref "B1") (pin "+") (pinfunction "+_+") (pintype "passive"))
      (node (ref "B1") (pin "+@1") (pinfunction "+_+@1") (pintype "passive"))
      (node (ref "B1") (pin "+@2") (pinfunction "+_+@2") (pintype "passive"))
      (node (ref "B1") (pin "+@3") (pinfunction "+_+@3") (pintype "passive"))
      (node (ref "B1") (pin "+@4") (pinfunction "+_+@4") (pintype "passive"))
      (node (ref "D1") (pin "A") (pinfunction "A_A") (pintype "passive"))
    )
    (net (code "475") (name "Net-(IC2A-A5)") (class "Default")
      (node (ref "IC2") (pin "6") (pinfunction "A5_6") (pintype "bidirectional"))
      (node (ref "R4") (pin "2") (pinfunction "2_2") (pintype "passive"))
    )
    (net (code "476") (name "Net-(IC2A-A6)") (class "Default")
      (node (ref "IC2") (pin "7") (pinfunction "A6_7") (pintype "bidirectional"))
      (node (ref "R3") (pin "2") (pinfunction "2_2") (pintype "passive"))
    )
    (net (code "477") (name "Net-(IC2A-A7)") (class "Default")
      (node (ref "IC2") (pin "8") (pinfunction "A7_8") (pintype "bidirectional"))
      (node (ref "R2") (pin "2") (pinfunction "2_2") (pintype "passive"))
    )
    (net (code "478") (name "Net-(IC2A-A8)") (class "Default")
      (node (ref "IC2") (pin "9") (pinfunction "A8_9") (pintype "bidirectional"))
      (node (ref "R1") (pin "2") (pinfunction "2_2") (pintype "passive"))
    )
    (net (code "479") (name "Net-(IC5A-Y0)") (class "Default")
      (node (ref "IC5") (pin "15") (pinfunction "Y0_15") (pintype "output"))
      (node (ref "S1") (pin "9") (pinfunction "9_9") (pintype "passive"))
    )
    (net (code "480") (name "Net-(IC5A-Y1)") (class "Default")
      (node (ref "IC5") (pin "14") (pinfunction "Y1_14") (pintype "output"))
      (node (ref "S1") (pin "10") (pinfunction "10_10") (pintype "passive"))
    )
    (net (code "481") (name "Net-(IC5A-Y2)") (class "Default")
      (node (ref "IC5") (pin "13") (pinfunction "Y2_13") (pintype "output"))
      (node (ref "S1") (pin "11") (pinfunction "11_11") (pintype "passive"))
    )
    (net (code "482") (name "Net-(IC5A-Y3)") (class "Default")
      (node (ref "IC5") (pin "12") (pinfunction "Y3_12") (pintype "output"))
      (node (ref "S1") (pin "12") (pinfunction "12_12") (pintype "passive"))
    )
    (net (code "483") (name "Net-(IC5A-Y4)") (class "Default")
      (node (ref "IC5") (pin "11") (pinfunction "Y4_11") (pintype "output"))
      (node (ref "S1") (pin "13") (pinfunction "13_13") (pintype "passive"))
    )
    (net (code "484") (name "Net-(IC5A-Y5)") (class "Default")
      (node (ref "IC5") (pin "10") (pinfunction "Y5_10") (pintype "output"))
      (node (ref "S1") (pin "14") (pinfunction "14_14") (pintype "passive"))
    )
    (net (code "485") (name "Net-(IC5A-Y6)") (class "Default")
      (node (ref "IC5") (pin "9") (pinfunction "Y6_9") (pintype "output"))
      (node (ref "S1") (pin "15") (pinfunction "15_15") (pintype "passive"))
    )
    (net (code "486") (name "Net-(IC5A-Y7)") (class "Default")
      (node (ref "IC5") (pin "7") (pinfunction "Y7_7") (pintype "output"))
      (node (ref "S1") (pin "16") (pinfunction "16_16") (pintype "passive"))
    )
    (net (code "487") (name "Net-(IC6A-I0)") (class "Default")
      (node (ref "IC6") (pin "1") (pinfunction "I0_1") (pintype "input"))
      (node (ref "R5") (pin "8") (pinfunction "1_8") (pintype "passive"))
      (node (ref "S1") (pin "1") (pinfunction "1_1") (pintype "passive"))
    )
    (net (code "488") (name "Net-(IC6A-I1)") (class "Default")
      (node (ref "IC6") (pin "2") (pinfunction "I1_2") (pintype "input"))
      (node (ref "R5") (pin "1") (pinfunction "1_1") (pintype "passive"))
      (node (ref "S1") (pin "8") (pinfunction "8_8") (pintype "passive"))
    )
    (net (code "489") (name "Net-(IC6A-I2)") (class "Default")
      (node (ref "IC6") (pin "3") (pinfunction "I2_3") (pintype "input"))
      (node (ref "R5") (pin "7") (pinfunction "1_7") (pintype "passive"))
      (node (ref "S1") (pin "2") (pinfunction "2_2") (pintype "passive"))
    )
    (net (code "490") (name "Net-(IC6A-I3)") (class "Default")
      (node (ref "IC6") (pin "4") (pinfunction "I3_4") (pintype "input"))
      (node (ref "R5") (pin "2") (pinfunction "1_2") (pintype "passive"))
      (node (ref "S1") (pin "7") (pinfunction "7_7") (pintype "passive"))
    )
    (net (code "491") (name "Net-(IC6A-I4)") (class "Default")
      (node (ref "IC6") (pin "5") (pinfunction "I4_5") (pintype "input"))
      (node (ref "R5") (pin "6") (pinfunction "1_6") (pintype "passive"))
      (node (ref "S1") (pin "3") (pinfunction "3_3") (pintype "passive"))
    )
    (net (code "492") (name "Net-(IC6A-I5)") (class "Default")
      (node (ref "IC6") (pin "6") (pinfunction "I5_6") (pintype "input"))
      (node (ref "R5") (pin "5") (pinfunction "1_5") (pintype "passive"))
      (node (ref "S1") (pin "4") (pinfunction "4_4") (pintype "passive"))
    )
    (net (code "493") (name "Net-(IC6A-I6)") (class "Default")
      (node (ref "IC6") (pin "11") (pinfunction "I6_11") (pintype "input"))
      (node (ref "R5") (pin "3") (pinfunction "1_3") (pintype "passive"))
      (node (ref "S1") (pin "6") (pinfunction "6_6") (pintype "passive"))
    )
    (net (code "494") (name "Net-(IC6A-I7)") (class "Default")
      (node (ref "IC6") (pin "12") (pinfunction "I7_12") (pintype "input"))
      (node (ref "R5") (pin "4") (pinfunction "1_4") (pintype "passive"))
      (node (ref "S1") (pin "5") (pinfunction "5_5") (pintype "passive"))
    )
    (net (code "495") (name "Net-(IC7A-I1)") (class "Default")
      (node (ref "IC7") (pin "2") (pinfunction "I1_2") (pintype "input"))
      (node (ref "IC8") (pin "17") (pinfunction "Y2_17") (pintype "tri_state"))
    )
    (net (code "496") (name "Net-(IC7A-I2)") (class "Default")
      (node (ref "IC7") (pin "4") (pinfunction "I2_4") (pintype "input"))
      (node (ref "IC8") (pin "15") (pinfunction "Y4_15") (pintype "tri_state"))
    )
    (net (code "497") (name "Net-(IC7A-I3)") (class "Default")
      (node (ref "IC7") (pin "5") (pinfunction "I3_5") (pintype "input"))
      (node (ref "IC8") (pin "13") (pinfunction "Y6_13") (pintype "tri_state"))
    )
    (net (code "498") (name "Net-(IC7B-I0)") (class "Default")
      (node (ref "IC7") (pin "9") (pinfunction "I0_9") (pintype "input"))
      (node (ref "IC8") (pin "18") (pinfunction "Y1_18") (pintype "tri_state"))
      (node (ref "IC8") (pin "3") (pinfunction "A2_3") (pintype "input"))
    )
    (net (code "499") (name "Net-(IC7B-I1)") (class "Default")
      (node (ref "IC7") (pin "10") (pinfunction "I1_10") (pintype "input"))
      (node (ref "IC8") (pin "12") (pinfunction "Y7_12") (pintype "tri_state"))
    )
    (net (code "500") (name "Net-(IC8A-A4)") (class "Default")
      (node (ref "IC8") (pin "16") (pinfunction "Y3_16") (pintype "tri_state"))
      (node (ref "IC8") (pin "5") (pinfunction "A4_5") (pintype "input"))
    )
    (net (code "501") (name "Net-(IC42A-CLR)") (class "Default")
      (node (ref "IC42") (pin "1") (pinfunction "CLR_1") (pintype "input"))
      (node (ref "IC43") (pin "3") (pinfunction "O_3") (pintype "output"))
    )
    (net (code "502") (name "Net-(IC42A-Q)") (class "Default")
      (node (ref "IC42") (pin "12") (pinfunction "D_12") (pintype "input"))
      (node (ref "IC42") (pin "5") (pinfunction "Q_5") (pintype "output"))
    )
    (net (code "503") (name "Net-(IC42B-Q)") (class "Default")
      (node (ref "IC42") (pin "9") (pinfunction "Q_9") (pintype "output"))
      (node (ref "IC43") (pin "7") (pinfunction "I0_7") (pintype "input"))
    )
    (net (code "504") (name "Net-(IC42B-~{Q})") (class "Default")
      (node (ref "IC42") (pin "8") (pinfunction "~{Q}_8") (pintype "output"))
      (node (ref "IC45") (pin "6") (pinfunction "I1_6") (pintype "input"))
    )
    (net (code "505") (name "Net-(Q1-B)") (class "Default")
      (node (ref "Q1") (pin "2") (pinfunction "B_2") (pintype "passive"))
      (node (ref "R6") (pin "2") (pinfunction "2_2") (pintype "passive"))
    )
    (net (code "506") (name "Net-(SV1-Pad1)") (class "Default")
      (node (ref "SV1") (pin "1") (pinfunction "1_1") (pintype "passive"))
      (node (ref "SV1") (pin "3") (pinfunction "3_3") (pintype "passive"))
      (node (ref "SV1") (pin "5") (pinfunction "5_5") (pintype "passive"))
      (node (ref "SV1") (pin "7") (pinfunction "7_7") (pintype "passive"))
      (node (ref "SV1") (pin "9") (pinfunction "9_9") (pintype "passive"))
    )
    (net (code "507") (name "Net-(SV1-Pad10)") (class "Default")
      (node (ref "SV1") (pin "10") (pinfunction "10_10") (pintype "passive"))
      (node (ref "SV1") (pin "2") (pinfunction "2_2") (pintype "passive"))
      (node (ref "SV1") (pin "4") (pinfunction "4_4") (pintype "passive"))
      (node (ref "SV1") (pin "6") (pinfunction "6_6") (pintype "passive"))
      (node (ref "SV1") (pin "8") (pinfunction "8_8") (pintype "passive"))
    )
    (net (code "508") (name "Net-(SV2-Pad1)") (class "Default")
      (node (ref "SV2") (pin "1") (pinfunction "1_1") (pintype "passive"))
      (node (ref "SV2") (pin "3") (pinfunction "3_3") (pintype "passive"))
      (node (ref "SV2") (pin "5") (pinfunction "5_5") (pintype "passive"))
      (node (ref "SV2") (pin "7") (pinfunction "7_7") (pintype "passive"))
      (node (ref "SV2") (pin "9") (pinfunction "9_9") (pintype "passive"))
    )
    (net (code "509") (name "Net-(SV2-Pad10)") (class "Default")
      (node (ref "SV2") (pin "10") (pinfunction "10_10") (pintype "passive"))
      (node (ref "SV2") (pin "2") (pinfunction "2_2") (pintype "passive"))
      (node (ref "SV2") (pin "4") (pinfunction "4_4") (pintype "passive"))
      (node (ref "SV2") (pin "6") (pinfunction "6_6") (pintype "passive"))
      (node (ref "SV2") (pin "8") (pinfunction "8_8") (pintype "passive"))
    )
    (net (code "510") (name "Net-(SV7-Pad1)") (class "Default")
      (node (ref "SV7") (pin "1") (pinfunction "1_1") (pintype "passive"))
      (node (ref "SV7") (pin "3") (pinfunction "3_3") (pintype "passive"))
      (node (ref "SV7") (pin "5") (pinfunction "5_5") (pintype "passive"))
      (node (ref "SV7") (pin "7") (pinfunction "7_7") (pintype "passive"))
      (node (ref "SV7") (pin "9") (pinfunction "9_9") (pintype "passive"))
    )
    (net (code "511") (name "Net-(SV7-Pad10)") (class "Default")
      (node (ref "SV7") (pin "10") (pinfunction "10_10") (pintype "passive"))
      (node (ref "SV7") (pin "2") (pinfunction "2_2") (pintype "passive"))
      (node (ref "SV7") (pin "4") (pinfunction "4_4") (pintype "passive"))
      (node (ref "SV7") (pin "6") (pinfunction "6_6") (pintype "passive"))
      (node (ref "SV7") (pin "8") (pinfunction "8_8") (pintype "passive"))
    )
    (net (code "512") (name "Net-(SV8-Pad1)") (class "Default")
      (node (ref "SV8") (pin "1") (pinfunction "1_1") (pintype "passive"))
      (node (ref "SV8") (pin "3") (pinfunction "3_3") (pintype "passive"))
      (node (ref "SV8") (pin "5") (pinfunction "5_5") (pintype "passive"))
      (node (ref "SV8") (pin "7") (pinfunction "7_7") (pintype "passive"))
      (node (ref "SV8") (pin "9") (pinfunction "9_9") (pintype "passive"))
    )
    (net (code "513") (name "Net-(SV8-Pad10)") (class "Default")
      (node (ref "SV8") (pin "10") (pinfunction "10_10") (pintype "passive"))
      (node (ref "SV8") (pin "2") (pinfunction "2_2") (pintype "passive"))
      (node (ref "SV8") (pin "4") (pinfunction "4_4") (pintype "passive"))
      (node (ref "SV8") (pin "6") (pinfunction "6_6") (pintype "passive"))
      (node (ref "SV8") (pin "8") (pinfunction "8_8") (pintype "passive"))
    )
    (net (code "514") (name "Net-(SV13-Pad1)") (class "Default")
      (node (ref "SV13") (pin "1") (pinfunction "1_1") (pintype "passive"))
      (node (ref "SV13") (pin "3") (pinfunction "3_3") (pintype "passive"))
      (node (ref "SV13") (pin "5") (pinfunction "5_5") (pintype "passive"))
      (node (ref "SV13") (pin "7") (pinfunction "7_7") (pintype "passive"))
      (node (ref "SV13") (pin "9") (pinfunction "9_9") (pintype "passive"))
    )
    (net (code "515") (name "Net-(SV13-Pad10)") (class "Default")
      (node (ref "SV13") (pin "10") (pinfunction "10_10") (pintype "passive"))
      (node (ref "SV13") (pin "2") (pinfunction "2_2") (pintype "passive"))
      (node (ref "SV13") (pin "4") (pinfunction "4_4") (pintype "passive"))
      (node (ref "SV13") (pin "6") (pinfunction "6_6") (pintype "passive"))
      (node (ref "SV13") (pin "8") (pinfunction "8_8") (pintype "passive"))
    )
    (net (code "516") (name "Net-(SV14-Pad1)") (class "Default")
      (node (ref "SV14") (pin "1") (pinfunction "1_1") (pintype "passive"))
      (node (ref "SV14") (pin "3") (pinfunction "3_3") (pintype "passive"))
      (node (ref "SV14") (pin "5") (pinfunction "5_5") (pintype "passive"))
      (node (ref "SV14") (pin "7") (pinfunction "7_7") (pintype "passive"))
      (node (ref "SV14") (pin "9") (pinfunction "9_9") (pintype "passive"))
    )
    (net (code "517") (name "Net-(SV14-Pad10)") (class "Default")
      (node (ref "SV14") (pin "10") (pinfunction "10_10") (pintype "passive"))
      (node (ref "SV14") (pin "2") (pinfunction "2_2") (pintype "passive"))
      (node (ref "SV14") (pin "4") (pinfunction "4_4") (pintype "passive"))
      (node (ref "SV14") (pin "6") (pinfunction "6_6") (pintype "passive"))
      (node (ref "SV14") (pin "8") (pinfunction "8_8") (pintype "passive"))
    )
    (net (code "518") (name "Net-(SV15-Pad1)") (class "Default")
      (node (ref "SV15") (pin "1") (pinfunction "1_1") (pintype "passive"))
      (node (ref "SV15") (pin "3") (pinfunction "3_3") (pintype "passive"))
      (node (ref "SV15") (pin "5") (pinfunction "5_5") (pintype "passive"))
      (node (ref "SV15") (pin "7") (pinfunction "7_7") (pintype "passive"))
      (node (ref "SV15") (pin "9") (pinfunction "9_9") (pintype "passive"))
    )
    (net (code "519") (name "Net-(SV15-Pad10)") (class "Default")
      (node (ref "SV15") (pin "10") (pinfunction "10_10") (pintype "passive"))
      (node (ref "SV15") (pin "2") (pinfunction "2_2") (pintype "passive"))
      (node (ref "SV15") (pin "4") (pinfunction "4_4") (pintype "passive"))
      (node (ref "SV15") (pin "6") (pinfunction "6_6") (pintype "passive"))
      (node (ref "SV15") (pin "8") (pinfunction "8_8") (pintype "passive"))
    )
    (net (code "520") (name "Net-(SV16-Pad1)") (class "Default")
      (node (ref "SV16") (pin "1") (pinfunction "1_1") (pintype "passive"))
      (node (ref "SV16") (pin "3") (pinfunction "3_3") (pintype "passive"))
      (node (ref "SV16") (pin "5") (pinfunction "5_5") (pintype "passive"))
      (node (ref "SV16") (pin "7") (pinfunction "7_7") (pintype "passive"))
      (node (ref "SV16") (pin "9") (pinfunction "9_9") (pintype "passive"))
    )
    (net (code "521") (name "Net-(SV16-Pad10)") (class "Default")
      (node (ref "SV16") (pin "10") (pinfunction "10_10") (pintype "passive"))
      (node (ref "SV16") (pin "2") (pinfunction "2_2") (pintype "passive"))
      (node (ref "SV16") (pin "4") (pinfunction "4_4") (pintype "passive"))
      (node (ref "SV16") (pin "6") (pinfunction "6_6") (pintype "passive"))
      (node (ref "SV16") (pin "8") (pinfunction "8_8") (pintype "passive"))
    )
    (net (code "522") (name "Net-(SV17-Pad1)") (class "Default")
      (node (ref "SV17") (pin "1") (pinfunction "1_1") (pintype "passive"))
      (node (ref "SV17") (pin "3") (pinfunction "3_3") (pintype "passive"))
      (node (ref "SV17") (pin "5") (pinfunction "5_5") (pintype "passive"))
      (node (ref "SV17") (pin "7") (pinfunction "7_7") (pintype "passive"))
      (node (ref "SV17") (pin "9") (pinfunction "9_9") (pintype "passive"))
    )
    (net (code "523") (name "Net-(SV17-Pad10)") (class "Default")
      (node (ref "SV17") (pin "10") (pinfunction "10_10") (pintype "passive"))
      (node (ref "SV17") (pin "2") (pinfunction "2_2") (pintype "passive"))
      (node (ref "SV17") (pin "4") (pinfunction "4_4") (pintype "passive"))
      (node (ref "SV17") (pin "6") (pinfunction "6_6") (pintype "passive"))
      (node (ref "SV17") (pin "8") (pinfunction "8_8") (pintype "passive"))
    )
    (net (code "524") (name "Net-(SV18-Pad1)") (class "Default")
      (node (ref "SV18") (pin "1") (pinfunction "1_1") (pintype "passive"))
      (node (ref "SV18") (pin "3") (pinfunction "3_3") (pintype "passive"))
      (node (ref "SV18") (pin "5") (pinfunction "5_5") (pintype "passive"))
      (node (ref "SV18") (pin "7") (pinfunction "7_7") (pintype "passive"))
      (node (ref "SV18") (pin "9") (pinfunction "9_9") (pintype "passive"))
    )
    (net (code "525") (name "Net-(SV18-Pad10)") (class "Default")
      (node (ref "SV18") (pin "10") (pinfunction "10_10") (pintype "passive"))
      (node (ref "SV18") (pin "2") (pinfunction "2_2") (pintype "passive"))
      (node (ref "SV18") (pin "4") (pinfunction "4_4") (pintype "passive"))
      (node (ref "SV18") (pin "6") (pinfunction "6_6") (pintype "passive"))
      (node (ref "SV18") (pin "8") (pinfunction "8_8") (pintype "passive"))
    )
    (net (code "526") (name "Net-(SV19-Pad1)") (class "Default")
      (node (ref "SV19") (pin "1") (pinfunction "1_1") (pintype "passive"))
      (node (ref "SV19") (pin "3") (pinfunction "3_3") (pintype "passive"))
      (node (ref "SV19") (pin "5") (pinfunction "5_5") (pintype "passive"))
      (node (ref "SV19") (pin "7") (pinfunction "7_7") (pintype "passive"))
      (node (ref "SV19") (pin "9") (pinfunction "9_9") (pintype "passive"))
    )
    (net (code "527") (name "Net-(SV19-Pad10)") (class "Default")
      (node (ref "SV19") (pin "10") (pinfunction "10_10") (pintype "passive"))
      (node (ref "SV19") (pin "2") (pinfunction "2_2") (pintype "passive"))
      (node (ref "SV19") (pin "4") (pinfunction "4_4") (pintype "passive"))
      (node (ref "SV19") (pin "6") (pinfunction "6_6") (pintype "passive"))
      (node (ref "SV19") (pin "8") (pinfunction "8_8") (pintype "passive"))
    )
    (net (code "528") (name "Net-(SV20-Pad1)") (class "Default")
      (node (ref "SV20") (pin "1") (pinfunction "1_1") (pintype "passive"))
      (node (ref "SV20") (pin "3") (pinfunction "3_3") (pintype "passive"))
      (node (ref "SV20") (pin "5") (pinfunction "5_5") (pintype "passive"))
      (node (ref "SV20") (pin "7") (pinfunction "7_7") (pintype "passive"))
      (node (ref "SV20") (pin "9") (pinfunction "9_9") (pintype "passive"))
    )
    (net (code "529") (name "Net-(SV20-Pad10)") (class "Default")
      (node (ref "SV20") (pin "10") (pinfunction "10_10") (pintype "passive"))
      (node (ref "SV20") (pin "2") (pinfunction "2_2") (pintype "passive"))
      (node (ref "SV20") (pin "4") (pinfunction "4_4") (pintype "passive"))
      (node (ref "SV20") (pin "6") (pinfunction "6_6") (pintype "passive"))
      (node (ref "SV20") (pin "8") (pinfunction "8_8") (pintype "passive"))
    )
    (net (code "530") (name "Net-(SV21-Pad1)") (class "Default")
      (node (ref "SV21") (pin "1") (pinfunction "1_1") (pintype "passive"))
      (node (ref "SV21") (pin "3") (pinfunction "3_3") (pintype "passive"))
      (node (ref "SV21") (pin "5") (pinfunction "5_5") (pintype "passive"))
      (node (ref "SV21") (pin "7") (pinfunction "7_7") (pintype "passive"))
      (node (ref "SV21") (pin "9") (pinfunction "9_9") (pintype "passive"))
    )
    (net (code "531") (name "Net-(SV21-Pad10)") (class "Default")
      (node (ref "SV21") (pin "10") (pinfunction "10_10") (pintype "passive"))
      (node (ref "SV21") (pin "2") (pinfunction "2_2") (pintype "passive"))
      (node (ref "SV21") (pin "4") (pinfunction "4_4") (pintype "passive"))
      (node (ref "SV21") (pin "6") (pinfunction "6_6") (pintype "passive"))
      (node (ref "SV21") (pin "8") (pinfunction "8_8") (pintype "passive"))
    )
    (net (code "532") (name "Net-(SV22-Pad1)") (class "Default")
      (node (ref "SV22") (pin "1") (pinfunction "1_1") (pintype "passive"))
      (node (ref "SV22") (pin "3") (pinfunction "3_3") (pintype "passive"))
      (node (ref "SV22") (pin "5") (pinfunction "5_5") (pintype "passive"))
      (node (ref "SV22") (pin "7") (pinfunction "7_7") (pintype "passive"))
      (node (ref "SV22") (pin "9") (pinfunction "9_9") (pintype "passive"))
    )
    (net (code "533") (name "Net-(SV22-Pad10)") (class "Default")
      (node (ref "SV22") (pin "10") (pinfunction "10_10") (pintype "passive"))
      (node (ref "SV22") (pin "2") (pinfunction "2_2") (pintype "passive"))
      (node (ref "SV22") (pin "4") (pinfunction "4_4") (pintype "passive"))
      (node (ref "SV22") (pin "6") (pinfunction "6_6") (pintype "passive"))
      (node (ref "SV22") (pin "8") (pinfunction "8_8") (pintype "passive"))
    )
    (net (code "534") (name "Net-(SV23-Pad1)") (class "Default")
      (node (ref "SV23") (pin "1") (pinfunction "1_1") (pintype "passive"))
      (node (ref "SV23") (pin "3") (pinfunction "3_3") (pintype "passive"))
      (node (ref "SV23") (pin "5") (pinfunction "5_5") (pintype "passive"))
      (node (ref "SV23") (pin "7") (pinfunction "7_7") (pintype "passive"))
      (node (ref "SV23") (pin "9") (pinfunction "9_9") (pintype "passive"))
    )
    (net (code "535") (name "Net-(SV23-Pad10)") (class "Default")
      (node (ref "SV23") (pin "10") (pinfunction "10_10") (pintype "passive"))
      (node (ref "SV23") (pin "2") (pinfunction "2_2") (pintype "passive"))
      (node (ref "SV23") (pin "4") (pinfunction "4_4") (pintype "passive"))
      (node (ref "SV23") (pin "6") (pinfunction "6_6") (pintype "passive"))
      (node (ref "SV23") (pin "8") (pinfunction "8_8") (pintype "passive"))
    )
    (net (code "536") (name "Net-(SV24-Pad1)") (class "Default")
      (node (ref "SV24") (pin "1") (pinfunction "1_1") (pintype "passive"))
      (node (ref "SV24") (pin "3") (pinfunction "3_3") (pintype "passive"))
      (node (ref "SV24") (pin "5") (pinfunction "5_5") (pintype "passive"))
      (node (ref "SV24") (pin "7") (pinfunction "7_7") (pintype "passive"))
      (node (ref "SV24") (pin "9") (pinfunction "9_9") (pintype "passive"))
    )
    (net (code "537") (name "Net-(SV24-Pad10)") (class "Default")
      (node (ref "SV24") (pin "10") (pinfunction "10_10") (pintype "passive"))
      (node (ref "SV24") (pin "2") (pinfunction "2_2") (pintype "passive"))
      (node (ref "SV24") (pin "4") (pinfunction "4_4") (pintype "passive"))
      (node (ref "SV24") (pin "6") (pinfunction "6_6") (pintype "passive"))
      (node (ref "SV24") (pin "8") (pinfunction "8_8") (pintype "passive"))
    )
    (net (code "538") (name "Net-(SV25-Pad1)") (class "Default")
      (node (ref "SV25") (pin "1") (pinfunction "1_1") (pintype "passive"))
      (node (ref "SV25") (pin "3") (pinfunction "3_3") (pintype "passive"))
      (node (ref "SV25") (pin "5") (pinfunction "5_5") (pintype "passive"))
      (node (ref "SV25") (pin "7") (pinfunction "7_7") (pintype "passive"))
      (node (ref "SV25") (pin "9") (pinfunction "9_9") (pintype "passive"))
    )
    (net (code "539") (name "Net-(SV25-Pad10)") (class "Default")
      (node (ref "SV25") (pin "10") (pinfunction "10_10") (pintype "passive"))
      (node (ref "SV25") (pin "2") (pinfunction "2_2") (pintype "passive"))
      (node (ref "SV25") (pin "4") (pinfunction "4_4") (pintype "passive"))
      (node (ref "SV25") (pin "6") (pinfunction "6_6") (pintype "passive"))
      (node (ref "SV25") (pin "8") (pinfunction "8_8") (pintype "passive"))
    )
    (net (code "540") (name "Net-(SV26-Pad1)") (class "Default")
      (node (ref "SV26") (pin "1") (pinfunction "1_1") (pintype "passive"))
      (node (ref "SV26") (pin "3") (pinfunction "3_3") (pintype "passive"))
      (node (ref "SV26") (pin "5") (pinfunction "5_5") (pintype "passive"))
      (node (ref "SV26") (pin "7") (pinfunction "7_7") (pintype "passive"))
      (node (ref "SV26") (pin "9") (pinfunction "9_9") (pintype "passive"))
    )
    (net (code "541") (name "Net-(SV26-Pad10)") (class "Default")
      (node (ref "SV26") (pin "10") (pinfunction "10_10") (pintype "passive"))
      (node (ref "SV26") (pin "2") (pinfunction "2_2") (pintype "passive"))
      (node (ref "SV26") (pin "4") (pinfunction "4_4") (pintype "passive"))
      (node (ref "SV26") (pin "6") (pinfunction "6_6") (pintype "passive"))
      (node (ref "SV26") (pin "8") (pinfunction "8_8") (pintype "passive"))
    )
    (net (code "542") (name "Net-(SV27-Pad1)") (class "Default")
      (node (ref "SV27") (pin "1") (pinfunction "1_1") (pintype "passive"))
      (node (ref "SV27") (pin "3") (pinfunction "3_3") (pintype "passive"))
      (node (ref "SV27") (pin "5") (pinfunction "5_5") (pintype "passive"))
      (node (ref "SV27") (pin "7") (pinfunction "7_7") (pintype "passive"))
      (node (ref "SV27") (pin "9") (pinfunction "9_9") (pintype "passive"))
    )
    (net (code "543") (name "Net-(SV27-Pad10)") (class "Default")
      (node (ref "SV27") (pin "10") (pinfunction "10_10") (pintype "passive"))
      (node (ref "SV27") (pin "2") (pinfunction "2_2") (pintype "passive"))
      (node (ref "SV27") (pin "4") (pinfunction "4_4") (pintype "passive"))
      (node (ref "SV27") (pin "6") (pinfunction "6_6") (pintype "passive"))
      (node (ref "SV27") (pin "8") (pinfunction "8_8") (pintype "passive"))
    )
    (net (code "544") (name "Net-(SV28-Pad1)") (class "Default")
      (node (ref "SV28") (pin "1") (pinfunction "1_1") (pintype "passive"))
      (node (ref "SV28") (pin "3") (pinfunction "3_3") (pintype "passive"))
      (node (ref "SV28") (pin "5") (pinfunction "5_5") (pintype "passive"))
      (node (ref "SV28") (pin "7") (pinfunction "7_7") (pintype "passive"))
      (node (ref "SV28") (pin "9") (pinfunction "9_9") (pintype "passive"))
    )
    (net (code "545") (name "Net-(SV28-Pad10)") (class "Default")
      (node (ref "SV28") (pin "10") (pinfunction "10_10") (pintype "passive"))
      (node (ref "SV28") (pin "2") (pinfunction "2_2") (pintype "passive"))
      (node (ref "SV28") (pin "4") (pinfunction "4_4") (pintype "passive"))
      (node (ref "SV28") (pin "6") (pinfunction "6_6") (pintype "passive"))
      (node (ref "SV28") (pin "8") (pinfunction "8_8") (pintype "passive"))
    )
    (net (code "546") (name "Net-(SV29-Pad1)") (class "Default")
      (node (ref "SV29") (pin "1") (pinfunction "1_1") (pintype "passive"))
      (node (ref "SV29") (pin "3") (pinfunction "3_3") (pintype "passive"))
      (node (ref "SV29") (pin "5") (pinfunction "5_5") (pintype "passive"))
      (node (ref "SV29") (pin "7") (pinfunction "7_7") (pintype "passive"))
      (node (ref "SV29") (pin "9") (pinfunction "9_9") (pintype "passive"))
    )
    (net (code "547") (name "Net-(SV29-Pad10)") (class "Default")
      (node (ref "SV29") (pin "10") (pinfunction "10_10") (pintype "passive"))
      (node (ref "SV29") (pin "2") (pinfunction "2_2") (pintype "passive"))
      (node (ref "SV29") (pin "4") (pinfunction "4_4") (pintype "passive"))
      (node (ref "SV29") (pin "6") (pinfunction "6_6") (pintype "passive"))
      (node (ref "SV29") (pin "8") (pinfunction "8_8") (pintype "passive"))
    )
    (net (code "548") (name "Net-(SV30-Pad1)") (class "Default")
      (node (ref "SV30") (pin "1") (pinfunction "1_1") (pintype "passive"))
      (node (ref "SV30") (pin "3") (pinfunction "3_3") (pintype "passive"))
      (node (ref "SV30") (pin "5") (pinfunction "5_5") (pintype "passive"))
      (node (ref "SV30") (pin "7") (pinfunction "7_7") (pintype "passive"))
      (node (ref "SV30") (pin "9") (pinfunction "9_9") (pintype "passive"))
    )
    (net (code "549") (name "Net-(SV30-Pad10)") (class "Default")
      (node (ref "SV30") (pin "10") (pinfunction "10_10") (pintype "passive"))
      (node (ref "SV30") (pin "2") (pinfunction "2_2") (pintype "passive"))
      (node (ref "SV30") (pin "4") (pinfunction "4_4") (pintype "passive"))
      (node (ref "SV30") (pin "6") (pinfunction "6_6") (pintype "passive"))
      (node (ref "SV30") (pin "8") (pinfunction "8_8") (pintype "passive"))
    )
    (net (code "550") (name "Net-(SV31-Pad1)") (class "Default")
      (node (ref "SV31") (pin "1") (pinfunction "1_1") (pintype "passive"))
      (node (ref "SV31") (pin "3") (pinfunction "3_3") (pintype "passive"))
      (node (ref "SV31") (pin "5") (pinfunction "5_5") (pintype "passive"))
      (node (ref "SV31") (pin "7") (pinfunction "7_7") (pintype "passive"))
      (node (ref "SV31") (pin "9") (pinfunction "9_9") (pintype "passive"))
    )
    (net (code "551") (name "Net-(SV31-Pad10)") (class "Default")
      (node (ref "SV31") (pin "10") (pinfunction "10_10") (pintype "passive"))
      (node (ref "SV31") (pin "2") (pinfunction "2_2") (pintype "passive"))
      (node (ref "SV31") (pin "4") (pinfunction "4_4") (pintype "passive"))
      (node (ref "SV31") (pin "6") (pinfunction "6_6") (pintype "passive"))
      (node (ref "SV31") (pin "8") (pinfunction "8_8") (pintype "passive"))
    )
    (net (code "552") (name "Net-(SV32-Pad1)") (class "Default")
      (node (ref "SV32") (pin "1") (pinfunction "1_1") (pintype "passive"))
      (node (ref "SV32") (pin "3") (pinfunction "3_3") (pintype "passive"))
      (node (ref "SV32") (pin "5") (pinfunction "5_5") (pintype "passive"))
      (node (ref "SV32") (pin "7") (pinfunction "7_7") (pintype "passive"))
      (node (ref "SV32") (pin "9") (pinfunction "9_9") (pintype "passive"))
    )
    (net (code "553") (name "Net-(SV32-Pad10)") (class "Default")
      (node (ref "SV32") (pin "10") (pinfunction "10_10") (pintype "passive"))
      (node (ref "SV32") (pin "2") (pinfunction "2_2") (pintype "passive"))
      (node (ref "SV32") (pin "4") (pinfunction "4_4") (pintype "passive"))
      (node (ref "SV32") (pin "6") (pinfunction "6_6") (pintype "passive"))
      (node (ref "SV32") (pin "8") (pinfunction "8_8") (pintype "passive"))
    )
    (net (code "554") (name "Net-(SV33-Pad1)") (class "Default")
      (node (ref "SV33") (pin "1") (pinfunction "1_1") (pintype "passive"))
      (node (ref "SV33") (pin "3") (pinfunction "3_3") (pintype "passive"))
      (node (ref "SV33") (pin "5") (pinfunction "5_5") (pintype "passive"))
      (node (ref "SV33") (pin "7") (pinfunction "7_7") (pintype "passive"))
      (node (ref "SV33") (pin "9") (pinfunction "9_9") (pintype "passive"))
    )
    (net (code "555") (name "Net-(SV33-Pad10)") (class "Default")
      (node (ref "SV33") (pin "10") (pinfunction "10_10") (pintype "passive"))
      (node (ref "SV33") (pin "2") (pinfunction "2_2") (pintype "passive"))
      (node (ref "SV33") (pin "4") (pinfunction "4_4") (pintype "passive"))
      (node (ref "SV33") (pin "6") (pinfunction "6_6") (pintype "passive"))
      (node (ref "SV33") (pin "8") (pinfunction "8_8") (pintype "passive"))
    )
    (net (code "556") (name "Net-(SV34-Pad1)") (class "Default")
      (node (ref "SV34") (pin "1") (pinfunction "1_1") (pintype "passive"))
      (node (ref "SV34") (pin "3") (pinfunction "3_3") (pintype "passive"))
      (node (ref "SV34") (pin "5") (pinfunction "5_5") (pintype "passive"))
      (node (ref "SV34") (pin "7") (pinfunction "7_7") (pintype "passive"))
      (node (ref "SV34") (pin "9") (pinfunction "9_9") (pintype "passive"))
    )
    (net (code "557") (name "Net-(SV34-Pad10)") (class "Default")
      (node (ref "SV34") (pin "10") (pinfunction "10_10") (pintype "passive"))
      (node (ref "SV34") (pin "2") (pinfunction "2_2") (pintype "passive"))
      (node (ref "SV34") (pin "4") (pinfunction "4_4") (pintype "passive"))
      (node (ref "SV34") (pin "6") (pinfunction "6_6") (pintype "passive"))
      (node (ref "SV34") (pin "8") (pinfunction "8_8") (pintype "passive"))
    )
    (net (code "558") (name "Net-(SV35-Pad1)") (class "Default")
      (node (ref "SV35") (pin "1") (pinfunction "1_1") (pintype "passive"))
      (node (ref "SV35") (pin "3") (pinfunction "3_3") (pintype "passive"))
      (node (ref "SV35") (pin "5") (pinfunction "5_5") (pintype "passive"))
      (node (ref "SV35") (pin "7") (pinfunction "7_7") (pintype "passive"))
      (node (ref "SV35") (pin "9") (pinfunction "9_9") (pintype "passive"))
    )
    (net (code "559") (name "Net-(SV35-Pad10)") (class "Default")
      (node (ref "SV35") (pin "10") (pinfunction "10_10") (pintype "passive"))
      (node (ref "SV35") (pin "2") (pinfunction "2_2") (pintype "passive"))
      (node (ref "SV35") (pin "4") (pinfunction "4_4") (pintype "passive"))
      (node (ref "SV35") (pin "6") (pinfunction "6_6") (pintype "passive"))
      (node (ref "SV35") (pin "8") (pinfunction "8_8") (pintype "passive"))
    )
    (net (code "560") (name "Net-(SV36-Pad1)") (class "Default")
      (node (ref "SV36") (pin "1") (pinfunction "1_1") (pintype "passive"))
      (node (ref "SV36") (pin "3") (pinfunction "3_3") (pintype "passive"))
      (node (ref "SV36") (pin "5") (pinfunction "5_5") (pintype "passive"))
      (node (ref "SV36") (pin "7") (pinfunction "7_7") (pintype "passive"))
      (node (ref "SV36") (pin "9") (pinfunction "9_9") (pintype "passive"))
    )
    (net (code "561") (name "Net-(SV36-Pad10)") (class "Default")
      (node (ref "SV36") (pin "10") (pinfunction "10_10") (pintype "passive"))
      (node (ref "SV36") (pin "2") (pinfunction "2_2") (pintype "passive"))
      (node (ref "SV36") (pin "4") (pinfunction "4_4") (pintype "passive"))
      (node (ref "SV36") (pin "6") (pinfunction "6_6") (pintype "passive"))
      (node (ref "SV36") (pin "8") (pinfunction "8_8") (pintype "passive"))
    )
    (net (code "562") (name "Net-(SV37-Pad1)") (class "Default")
      (node (ref "SV37") (pin "1") (pinfunction "1_1") (pintype "passive"))
      (node (ref "SV37") (pin "3") (pinfunction "3_3") (pintype "passive"))
      (node (ref "SV37") (pin "5") (pinfunction "5_5") (pintype "passive"))
      (node (ref "SV37") (pin "7") (pinfunction "7_7") (pintype "passive"))
      (node (ref "SV37") (pin "9") (pinfunction "9_9") (pintype "passive"))
    )
    (net (code "563") (name "Net-(SV37-Pad10)") (class "Default")
      (node (ref "SV37") (pin "10") (pinfunction "10_10") (pintype "passive"))
      (node (ref "SV37") (pin "2") (pinfunction "2_2") (pintype "passive"))
      (node (ref "SV37") (pin "4") (pinfunction "4_4") (pintype "passive"))
      (node (ref "SV37") (pin "6") (pinfunction "6_6") (pintype "passive"))
      (node (ref "SV37") (pin "8") (pinfunction "8_8") (pintype "passive"))
    )
    (net (code "564") (name "Net-(SV38-Pad1)") (class "Default")
      (node (ref "SV38") (pin "1") (pinfunction "1_1") (pintype "passive"))
      (node (ref "SV38") (pin "3") (pinfunction "3_3") (pintype "passive"))
      (node (ref "SV38") (pin "5") (pinfunction "5_5") (pintype "passive"))
      (node (ref "SV38") (pin "7") (pinfunction "7_7") (pintype "passive"))
      (node (ref "SV38") (pin "9") (pinfunction "9_9") (pintype "passive"))
    )
    (net (code "565") (name "Net-(SV38-Pad10)") (class "Default")
      (node (ref "SV38") (pin "10") (pinfunction "10_10") (pintype "passive"))
      (node (ref "SV38") (pin "2") (pinfunction "2_2") (pintype "passive"))
      (node (ref "SV38") (pin "4") (pinfunction "4_4") (pintype "passive"))
      (node (ref "SV38") (pin "6") (pinfunction "6_6") (pintype "passive"))
      (node (ref "SV38") (pin "8") (pinfunction "8_8") (pintype "passive"))
    )
    (net (code "566") (name "Net-(SV39-Pad1)") (class "Default")
      (node (ref "SV39") (pin "1") (pinfunction "1_1") (pintype "passive"))
      (node (ref "SV39") (pin "3") (pinfunction "3_3") (pintype "passive"))
      (node (ref "SV39") (pin "5") (pinfunction "5_5") (pintype "passive"))
      (node (ref "SV39") (pin "7") (pinfunction "7_7") (pintype "passive"))
      (node (ref "SV39") (pin "9") (pinfunction "9_9") (pintype "passive"))
    )
    (net (code "567") (name "Net-(SV39-Pad10)") (class "Default")
      (node (ref "SV39") (pin "10") (pinfunction "10_10") (pintype "passive"))
      (node (ref "SV39") (pin "2") (pinfunction "2_2") (pintype "passive"))
      (node (ref "SV39") (pin "4") (pinfunction "4_4") (pintype "passive"))
      (node (ref "SV39") (pin "6") (pinfunction "6_6") (pintype "passive"))
      (node (ref "SV39") (pin "8") (pinfunction "8_8") (pintype "passive"))
    )
    (net (code "568") (name "Net-(SV40-Pad1)") (class "Default")
      (node (ref "SV40") (pin "1") (pinfunction "1_1") (pintype "passive"))
      (node (ref "SV40") (pin "3") (pinfunction "3_3") (pintype "passive"))
      (node (ref "SV40") (pin "5") (pinfunction "5_5") (pintype "passive"))
      (node (ref "SV40") (pin "7") (pinfunction "7_7") (pintype "passive"))
      (node (ref "SV40") (pin "9") (pinfunction "9_9") (pintype "passive"))
    )
    (net (code "569") (name "Net-(SV40-Pad10)") (class "Default")
      (node (ref "SV40") (pin "10") (pinfunction "10_10") (pintype "passive"))
      (node (ref "SV40") (pin "2") (pinfunction "2_2") (pintype "passive"))
      (node (ref "SV40") (pin "4") (pinfunction "4_4") (pintype "passive"))
      (node (ref "SV40") (pin "6") (pinfunction "6_6") (pintype "passive"))
      (node (ref "SV40") (pin "8") (pinfunction "8_8") (pintype "passive"))
    )
    (net (code "570") (name "Net-(SV41-Pad1)") (class "Default")
      (node (ref "SV41") (pin "1") (pinfunction "1_1") (pintype "passive"))
      (node (ref "SV41") (pin "3") (pinfunction "3_3") (pintype "passive"))
      (node (ref "SV41") (pin "5") (pinfunction "5_5") (pintype "passive"))
      (node (ref "SV41") (pin "7") (pinfunction "7_7") (pintype "passive"))
      (node (ref "SV41") (pin "9") (pinfunction "9_9") (pintype "passive"))
    )
    (net (code "571") (name "Net-(SV41-Pad10)") (class "Default")
      (node (ref "SV41") (pin "10") (pinfunction "10_10") (pintype "passive"))
      (node (ref "SV41") (pin "2") (pinfunction "2_2") (pintype "passive"))
      (node (ref "SV41") (pin "4") (pinfunction "4_4") (pintype "passive"))
      (node (ref "SV41") (pin "6") (pinfunction "6_6") (pintype "passive"))
      (node (ref "SV41") (pin "8") (pinfunction "8_8") (pintype "passive"))
    )
    (net (code "572") (name "Net-(SV42-Pad1)") (class "Default")
      (node (ref "SV42") (pin "1") (pinfunction "1_1") (pintype "passive"))
      (node (ref "SV42") (pin "3") (pinfunction "3_3") (pintype "passive"))
      (node (ref "SV42") (pin "5") (pinfunction "5_5") (pintype "passive"))
      (node (ref "SV42") (pin "7") (pinfunction "7_7") (pintype "passive"))
      (node (ref "SV42") (pin "9") (pinfunction "9_9") (pintype "passive"))
    )
    (net (code "573") (name "Net-(SV42-Pad10)") (class "Default")
      (node (ref "SV42") (pin "10") (pinfunction "10_10") (pintype "passive"))
      (node (ref "SV42") (pin "2") (pinfunction "2_2") (pintype "passive"))
      (node (ref "SV42") (pin "4") (pinfunction "4_4") (pintype "passive"))
      (node (ref "SV42") (pin "6") (pinfunction "6_6") (pintype "passive"))
      (node (ref "SV42") (pin "8") (pinfunction "8_8") (pintype "passive"))
    )
    (net (code "574") (name "Net-(SV43-Pad1)") (class "Default")
      (node (ref "SV43") (pin "1") (pinfunction "1_1") (pintype "passive"))
      (node (ref "SV43") (pin "3") (pinfunction "3_3") (pintype "passive"))
      (node (ref "SV43") (pin "5") (pinfunction "5_5") (pintype "passive"))
      (node (ref "SV43") (pin "7") (pinfunction "7_7") (pintype "passive"))
      (node (ref "SV43") (pin "9") (pinfunction "9_9") (pintype "passive"))
    )
    (net (code "575") (name "Net-(SV43-Pad10)") (class "Default")
      (node (ref "SV43") (pin "10") (pinfunction "10_10") (pintype "passive"))
      (node (ref "SV43") (pin "2") (pinfunction "2_2") (pintype "passive"))
      (node (ref "SV43") (pin "4") (pinfunction "4_4") (pintype "passive"))
      (node (ref "SV43") (pin "6") (pinfunction "6_6") (pintype "passive"))
      (node (ref "SV43") (pin "8") (pinfunction "8_8") (pintype "passive"))
    )
    (net (code "576") (name "Net-(SV44-Pad1)") (class "Default")
      (node (ref "SV44") (pin "1") (pinfunction "1_1") (pintype "passive"))
      (node (ref "SV44") (pin "3") (pinfunction "3_3") (pintype "passive"))
      (node (ref "SV44") (pin "5") (pinfunction "5_5") (pintype "passive"))
      (node (ref "SV44") (pin "7") (pinfunction "7_7") (pintype "passive"))
      (node (ref "SV44") (pin "9") (pinfunction "9_9") (pintype "passive"))
    )
    (net (code "577") (name "Net-(SV44-Pad10)") (class "Default")
      (node (ref "SV44") (pin "10") (pinfunction "10_10") (pintype "passive"))
      (node (ref "SV44") (pin "2") (pinfunction "2_2") (pintype "passive"))
      (node (ref "SV44") (pin "4") (pinfunction "4_4") (pintype "passive"))
      (node (ref "SV44") (pin "6") (pinfunction "6_6") (pintype "passive"))
      (node (ref "SV44") (pin "8") (pinfunction "8_8") (pintype "passive"))
    )
    (net (code "578") (name "Net-(SV45-Pad1)") (class "Default")
      (node (ref "SV45") (pin "1") (pinfunction "1_1") (pintype "passive"))
      (node (ref "SV45") (pin "3") (pinfunction "3_3") (pintype "passive"))
      (node (ref "SV45") (pin "5") (pinfunction "5_5") (pintype "passive"))
      (node (ref "SV45") (pin "7") (pinfunction "7_7") (pintype "passive"))
      (node (ref "SV45") (pin "9") (pinfunction "9_9") (pintype "passive"))
    )
    (net (code "579") (name "Net-(SV45-Pad10)") (class "Default")
      (node (ref "SV45") (pin "10") (pinfunction "10_10") (pintype "passive"))
      (node (ref "SV45") (pin "2") (pinfunction "2_2") (pintype "passive"))
      (node (ref "SV45") (pin "4") (pinfunction "4_4") (pintype "passive"))
      (node (ref "SV45") (pin "6") (pinfunction "6_6") (pintype "passive"))
      (node (ref "SV45") (pin "8") (pinfunction "8_8") (pintype "passive"))
    )
    (net (code "580") (name "Net-(SV46-Pad1)") (class "Default")
      (node (ref "SV46") (pin "1") (pinfunction "1_1") (pintype "passive"))
      (node (ref "SV46") (pin "3") (pinfunction "3_3") (pintype "passive"))
      (node (ref "SV46") (pin "5") (pinfunction "5_5") (pintype "passive"))
      (node (ref "SV46") (pin "7") (pinfunction "7_7") (pintype "passive"))
      (node (ref "SV46") (pin "9") (pinfunction "9_9") (pintype "passive"))
    )
    (net (code "581") (name "Net-(SV46-Pad10)") (class "Default")
      (node (ref "SV46") (pin "10") (pinfunction "10_10") (pintype "passive"))
      (node (ref "SV46") (pin "2") (pinfunction "2_2") (pintype "passive"))
      (node (ref "SV46") (pin "4") (pinfunction "4_4") (pintype "passive"))
      (node (ref "SV46") (pin "6") (pinfunction "6_6") (pintype "passive"))
      (node (ref "SV46") (pin "8") (pinfunction "8_8") (pintype "passive"))
    )
    (net (code "582") (name "Net-(SV47-Pad1)") (class "Default")
      (node (ref "SV47") (pin "1") (pinfunction "1_1") (pintype "passive"))
      (node (ref "SV47") (pin "3") (pinfunction "3_3") (pintype "passive"))
      (node (ref "SV47") (pin "5") (pinfunction "5_5") (pintype "passive"))
      (node (ref "SV47") (pin "7") (pinfunction "7_7") (pintype "passive"))
      (node (ref "SV47") (pin "9") (pinfunction "9_9") (pintype "passive"))
    )
    (net (code "583") (name "Net-(SV47-Pad10)") (class "Default")
      (node (ref "SV47") (pin "10") (pinfunction "10_10") (pintype "passive"))
      (node (ref "SV47") (pin "2") (pinfunction "2_2") (pintype "passive"))
      (node (ref "SV47") (pin "4") (pinfunction "4_4") (pintype "passive"))
      (node (ref "SV47") (pin "6") (pinfunction "6_6") (pintype "passive"))
      (node (ref "SV47") (pin "8") (pinfunction "8_8") (pintype "passive"))
    )
    (net (code "584") (name "Net-(SV48-Pad1)") (class "Default")
      (node (ref "SV48") (pin "1") (pinfunction "1_1") (pintype "passive"))
      (node (ref "SV48") (pin "3") (pinfunction "3_3") (pintype "passive"))
      (node (ref "SV48") (pin "5") (pinfunction "5_5") (pintype "passive"))
      (node (ref "SV48") (pin "7") (pinfunction "7_7") (pintype "passive"))
      (node (ref "SV48") (pin "9") (pinfunction "9_9") (pintype "passive"))
    )
    (net (code "585") (name "Net-(SV48-Pad10)") (class "Default")
      (node (ref "SV48") (pin "10") (pinfunction "10_10") (pintype "passive"))
      (node (ref "SV48") (pin "2") (pinfunction "2_2") (pintype "passive"))
      (node (ref "SV48") (pin "4") (pinfunction "4_4") (pintype "passive"))
      (node (ref "SV48") (pin "6") (pinfunction "6_6") (pintype "passive"))
      (node (ref "SV48") (pin "8") (pinfunction "8_8") (pintype "passive"))
    )
    (net (code "586") (name "Net-(SV49-Pad1)") (class "Default")
      (node (ref "SV49") (pin "1") (pinfunction "1_1") (pintype "passive"))
      (node (ref "SV49") (pin "3") (pinfunction "3_3") (pintype "passive"))
      (node (ref "SV49") (pin "5") (pinfunction "5_5") (pintype "passive"))
      (node (ref "SV49") (pin "7") (pinfunction "7_7") (pintype "passive"))
      (node (ref "SV49") (pin "9") (pinfunction "9_9") (pintype "passive"))
    )
    (net (code "587") (name "Net-(SV49-Pad10)") (class "Default")
      (node (ref "SV49") (pin "10") (pinfunction "10_10") (pintype "passive"))
      (node (ref "SV49") (pin "2") (pinfunction "2_2") (pintype "passive"))
      (node (ref "SV49") (pin "4") (pinfunction "4_4") (pintype "passive"))
      (node (ref "SV49") (pin "6") (pinfunction "6_6") (pintype "passive"))
      (node (ref "SV49") (pin "8") (pinfunction "8_8") (pintype "passive"))
    )
    (net (code "588") (name "Net-(SV50-Pad1)") (class "Default")
      (node (ref "SV50") (pin "1") (pinfunction "1_1") (pintype "passive"))
      (node (ref "SV50") (pin "3") (pinfunction "3_3") (pintype "passive"))
      (node (ref "SV50") (pin "5") (pinfunction "5_5") (pintype "passive"))
      (node (ref "SV50") (pin "7") (pinfunction "7_7") (pintype "passive"))
      (node (ref "SV50") (pin "9") (pinfunction "9_9") (pintype "passive"))
    )
    (net (code "589") (name "Net-(SV50-Pad10)") (class "Default")
      (node (ref "SV50") (pin "10") (pinfunction "10_10") (pintype "passive"))
      (node (ref "SV50") (pin "2") (pinfunction "2_2") (pintype "passive"))
      (node (ref "SV50") (pin "4") (pinfunction "4_4") (pintype "passive"))
      (node (ref "SV50") (pin "6") (pinfunction "6_6") (pintype "passive"))
      (node (ref "SV50") (pin "8") (pinfunction "8_8") (pintype "passive"))
    )
    (net (code "590") (name "Net-(SV51-Pad1)") (class "Default")
      (node (ref "SV51") (pin "1") (pinfunction "1_1") (pintype "passive"))
      (node (ref "SV51") (pin "3") (pinfunction "3_3") (pintype "passive"))
      (node (ref "SV51") (pin "5") (pinfunction "5_5") (pintype "passive"))
      (node (ref "SV51") (pin "7") (pinfunction "7_7") (pintype "passive"))
      (node (ref "SV51") (pin "9") (pinfunction "9_9") (pintype "passive"))
    )
    (net (code "591") (name "Net-(SV51-Pad10)") (class "Default")
      (node (ref "SV51") (pin "10") (pinfunction "10_10") (pintype "passive"))
      (node (ref "SV51") (pin "2") (pinfunction "2_2") (pintype "passive"))
      (node (ref "SV51") (pin "4") (pinfunction "4_4") (pintype "passive"))
      (node (ref "SV51") (pin "6") (pinfunction "6_6") (pintype "passive"))
      (node (ref "SV51") (pin "8") (pinfunction "8_8") (pintype "passive"))
    )
    (net (code "592") (name "Net-(SV52-Pad1)") (class "Default")
      (node (ref "SV52") (pin "1") (pinfunction "1_1") (pintype "passive"))
      (node (ref "SV52") (pin "3") (pinfunction "3_3") (pintype "passive"))
      (node (ref "SV52") (pin "5") (pinfunction "5_5") (pintype "passive"))
      (node (ref "SV52") (pin "7") (pinfunction "7_7") (pintype "passive"))
      (node (ref "SV52") (pin "9") (pinfunction "9_9") (pintype "passive"))
    )
    (net (code "593") (name "Net-(SV52-Pad10)") (class "Default")
      (node (ref "SV52") (pin "10") (pinfunction "10_10") (pintype "passive"))
      (node (ref "SV52") (pin "2") (pinfunction "2_2") (pintype "passive"))
      (node (ref "SV52") (pin "4") (pinfunction "4_4") (pintype "passive"))
      (node (ref "SV52") (pin "6") (pinfunction "6_6") (pintype "passive"))
      (node (ref "SV52") (pin "8") (pinfunction "8_8") (pintype "passive"))
    )
    (net (code "594") (name "Net-(SV53-Pad1)") (class "Default")
      (node (ref "SV53") (pin "1") (pinfunction "1_1") (pintype "passive"))
      (node (ref "SV53") (pin "3") (pinfunction "3_3") (pintype "passive"))
      (node (ref "SV53") (pin "5") (pinfunction "5_5") (pintype "passive"))
      (node (ref "SV53") (pin "7") (pinfunction "7_7") (pintype "passive"))
      (node (ref "SV53") (pin "9") (pinfunction "9_9") (pintype "passive"))
    )
    (net (code "595") (name "Net-(SV53-Pad10)") (class "Default")
      (node (ref "SV53") (pin "10") (pinfunction "10_10") (pintype "passive"))
      (node (ref "SV53") (pin "2") (pinfunction "2_2") (pintype "passive"))
      (node (ref "SV53") (pin "4") (pinfunction "4_4") (pintype "passive"))
      (node (ref "SV53") (pin "6") (pinfunction "6_6") (pintype "passive"))
      (node (ref "SV53") (pin "8") (pinfunction "8_8") (pintype "passive"))
    )
    (net (code "596") (name "Net-(SV54-Pad1)") (class "Default")
      (node (ref "SV54") (pin "1") (pinfunction "1_1") (pintype "passive"))
      (node (ref "SV54") (pin "3") (pinfunction "3_3") (pintype "passive"))
      (node (ref "SV54") (pin "5") (pinfunction "5_5") (pintype "passive"))
      (node (ref "SV54") (pin "7") (pinfunction "7_7") (pintype "passive"))
      (node (ref "SV54") (pin "9") (pinfunction "9_9") (pintype "passive"))
    )
    (net (code "597") (name "Net-(SV54-Pad10)") (class "Default")
      (node (ref "SV54") (pin "10") (pinfunction "10_10") (pintype "passive"))
      (node (ref "SV54") (pin "2") (pinfunction "2_2") (pintype "passive"))
      (node (ref "SV54") (pin "4") (pinfunction "4_4") (pintype "passive"))
      (node (ref "SV54") (pin "6") (pinfunction "6_6") (pintype "passive"))
      (node (ref "SV54") (pin "8") (pinfunction "8_8") (pintype "passive"))
    )
    (net (code "598") (name "Net-(SV55-Pad1)") (class "Default")
      (node (ref "SV55") (pin "1") (pinfunction "1_1") (pintype "passive"))
      (node (ref "SV55") (pin "3") (pinfunction "3_3") (pintype "passive"))
      (node (ref "SV55") (pin "5") (pinfunction "5_5") (pintype "passive"))
      (node (ref "SV55") (pin "7") (pinfunction "7_7") (pintype "passive"))
      (node (ref "SV55") (pin "9") (pinfunction "9_9") (pintype "passive"))
    )
    (net (code "599") (name "Net-(SV55-Pad10)") (class "Default")
      (node (ref "SV55") (pin "10") (pinfunction "10_10") (pintype "passive"))
      (node (ref "SV55") (pin "2") (pinfunction "2_2") (pintype "passive"))
      (node (ref "SV55") (pin "4") (pinfunction "4_4") (pintype "passive"))
      (node (ref "SV55") (pin "6") (pinfunction "6_6") (pintype "passive"))
      (node (ref "SV55") (pin "8") (pinfunction "8_8") (pintype "passive"))
    )
    (net (code "600") (name "Net-(SV56-Pad1)") (class "Default")
      (node (ref "SV56") (pin "1") (pinfunction "1_1") (pintype "passive"))
      (node (ref "SV56") (pin "3") (pinfunction "3_3") (pintype "passive"))
      (node (ref "SV56") (pin "5") (pinfunction "5_5") (pintype "passive"))
      (node (ref "SV56") (pin "7") (pinfunction "7_7") (pintype "passive"))
      (node (ref "SV56") (pin "9") (pinfunction "9_9") (pintype "passive"))
    )
    (net (code "601") (name "Net-(SV56-Pad10)") (class "Default")
      (node (ref "SV56") (pin "10") (pinfunction "10_10") (pintype "passive"))
      (node (ref "SV56") (pin "2") (pinfunction "2_2") (pintype "passive"))
      (node (ref "SV56") (pin "4") (pinfunction "4_4") (pintype "passive"))
      (node (ref "SV56") (pin "6") (pinfunction "6_6") (pintype "passive"))
      (node (ref "SV56") (pin "8") (pinfunction "8_8") (pintype "passive"))
    )
    (net (code "602") (name "Net-(SV57-Pad1)") (class "Default")
      (node (ref "SV57") (pin "1") (pinfunction "1_1") (pintype "passive"))
      (node (ref "SV57") (pin "3") (pinfunction "3_3") (pintype "passive"))
      (node (ref "SV57") (pin "5") (pinfunction "5_5") (pintype "passive"))
      (node (ref "SV57") (pin "7") (pinfunction "7_7") (pintype "passive"))
      (node (ref "SV57") (pin "9") (pinfunction "9_9") (pintype "passive"))
    )
    (net (code "603") (name "Net-(SV57-Pad10)") (class "Default")
      (node (ref "SV57") (pin "10") (pinfunction "10_10") (pintype "passive"))
      (node (ref "SV57") (pin "2") (pinfunction "2_2") (pintype "passive"))
      (node (ref "SV57") (pin "4") (pinfunction "4_4") (pintype "passive"))
      (node (ref "SV57") (pin "6") (pinfunction "6_6") (pintype "passive"))
      (node (ref "SV57") (pin "8") (pinfunction "8_8") (pintype "passive"))
    )
    (net (code "604") (name "Net-(SV58-Pad1)") (class "Default")
      (node (ref "SV58") (pin "1") (pinfunction "1_1") (pintype "passive"))
      (node (ref "SV58") (pin "3") (pinfunction "3_3") (pintype "passive"))
      (node (ref "SV58") (pin "5") (pinfunction "5_5") (pintype "passive"))
      (node (ref "SV58") (pin "7") (pinfunction "7_7") (pintype "passive"))
      (node (ref "SV58") (pin "9") (pinfunction "9_9") (pintype "passive"))
    )
    (net (code "605") (name "Net-(SV58-Pad10)") (class "Default")
      (node (ref "SV58") (pin "10") (pinfunction "10_10") (pintype "passive"))
      (node (ref "SV58") (pin "2") (pinfunction "2_2") (pintype "passive"))
      (node (ref "SV58") (pin "4") (pinfunction "4_4") (pintype "passive"))
      (node (ref "SV58") (pin "6") (pinfunction "6_6") (pintype "passive"))
      (node (ref "SV58") (pin "8") (pinfunction "8_8") (pintype "passive"))
    )
    (net (code "606") (name "Net-(SV59-Pad1)") (class "Default")
      (node (ref "SV59") (pin "1") (pinfunction "1_1") (pintype "passive"))
      (node (ref "SV59") (pin "3") (pinfunction "3_3") (pintype "passive"))
      (node (ref "SV59") (pin "5") (pinfunction "5_5") (pintype "passive"))
      (node (ref "SV59") (pin "7") (pinfunction "7_7") (pintype "passive"))
      (node (ref "SV59") (pin "9") (pinfunction "9_9") (pintype "passive"))
    )
    (net (code "607") (name "Net-(SV59-Pad10)") (class "Default")
      (node (ref "SV59") (pin "10") (pinfunction "10_10") (pintype "passive"))
      (node (ref "SV59") (pin "2") (pinfunction "2_2") (pintype "passive"))
      (node (ref "SV59") (pin "4") (pinfunction "4_4") (pintype "passive"))
      (node (ref "SV59") (pin "6") (pinfunction "6_6") (pintype "passive"))
      (node (ref "SV59") (pin "8") (pinfunction "8_8") (pintype "passive"))
    )
    (net (code "608") (name "Net-(SV60-Pad1)") (class "Default")
      (node (ref "SV60") (pin "1") (pinfunction "1_1") (pintype "passive"))
      (node (ref "SV60") (pin "3") (pinfunction "3_3") (pintype "passive"))
      (node (ref "SV60") (pin "5") (pinfunction "5_5") (pintype "passive"))
      (node (ref "SV60") (pin "7") (pinfunction "7_7") (pintype "passive"))
      (node (ref "SV60") (pin "9") (pinfunction "9_9") (pintype "passive"))
    )
    (net (code "609") (name "Net-(SV60-Pad10)") (class "Default")
      (node (ref "SV60") (pin "10") (pinfunction "10_10") (pintype "passive"))
      (node (ref "SV60") (pin "2") (pinfunction "2_2") (pintype "passive"))
      (node (ref "SV60") (pin "4") (pinfunction "4_4") (pintype "passive"))
      (node (ref "SV60") (pin "6") (pinfunction "6_6") (pintype "passive"))
      (node (ref "SV60") (pin "8") (pinfunction "8_8") (pintype "passive"))
    )
    (net (code "610") (name "Net-(SV61-Pad1)") (class "Default")
      (node (ref "SV61") (pin "1") (pinfunction "1_1") (pintype "passive"))
      (node (ref "SV61") (pin "3") (pinfunction "3_3") (pintype "passive"))
      (node (ref "SV61") (pin "5") (pinfunction "5_5") (pintype "passive"))
      (node (ref "SV61") (pin "7") (pinfunction "7_7") (pintype "passive"))
      (node (ref "SV61") (pin "9") (pinfunction "9_9") (pintype "passive"))
    )
    (net (code "611") (name "Net-(SV61-Pad10)") (class "Default")
      (node (ref "SV61") (pin "10") (pinfunction "10_10") (pintype "passive"))
      (node (ref "SV61") (pin "2") (pinfunction "2_2") (pintype "passive"))
      (node (ref "SV61") (pin "4") (pinfunction "4_4") (pintype "passive"))
      (node (ref "SV61") (pin "6") (pinfunction "6_6") (pintype "passive"))
      (node (ref "SV61") (pin "8") (pinfunction "8_8") (pintype "passive"))
    )
    (net (code "612") (name "Net-(SV62-Pad1)") (class "Default")
      (node (ref "SV62") (pin "1") (pinfunction "1_1") (pintype "passive"))
      (node (ref "SV62") (pin "3") (pinfunction "3_3") (pintype "passive"))
      (node (ref "SV62") (pin "5") (pinfunction "5_5") (pintype "passive"))
      (node (ref "SV62") (pin "7") (pinfunction "7_7") (pintype "passive"))
      (node (ref "SV62") (pin "9") (pinfunction "9_9") (pintype "passive"))
    )
    (net (code "613") (name "Net-(SV62-Pad10)") (class "Default")
      (node (ref "SV62") (pin "10") (pinfunction "10_10") (pintype "passive"))
      (node (ref "SV62") (pin "2") (pinfunction "2_2") (pintype "passive"))
      (node (ref "SV62") (pin "4") (pinfunction "4_4") (pintype "passive"))
      (node (ref "SV62") (pin "6") (pinfunction "6_6") (pintype "passive"))
      (node (ref "SV62") (pin "8") (pinfunction "8_8") (pintype "passive"))
    )
    (net (code "614") (name "Net-(SV63-Pad1)") (class "Default")
      (node (ref "SV63") (pin "1") (pinfunction "1_1") (pintype "passive"))
      (node (ref "SV63") (pin "3") (pinfunction "3_3") (pintype "passive"))
      (node (ref "SV63") (pin "5") (pinfunction "5_5") (pintype "passive"))
      (node (ref "SV63") (pin "7") (pinfunction "7_7") (pintype "passive"))
      (node (ref "SV63") (pin "9") (pinfunction "9_9") (pintype "passive"))
    )
    (net (code "615") (name "Net-(SV63-Pad10)") (class "Default")
      (node (ref "SV63") (pin "10") (pinfunction "10_10") (pintype "passive"))
      (node (ref "SV63") (pin "2") (pinfunction "2_2") (pintype "passive"))
      (node (ref "SV63") (pin "4") (pinfunction "4_4") (pintype "passive"))
      (node (ref "SV63") (pin "6") (pinfunction "6_6") (pintype "passive"))
      (node (ref "SV63") (pin "8") (pinfunction "8_8") (pintype "passive"))
    )
    (net (code "616") (name "Net-(SV64-Pad1)") (class "Default")
      (node (ref "SV64") (pin "1") (pinfunction "1_1") (pintype "passive"))
      (node (ref "SV64") (pin "3") (pinfunction "3_3") (pintype "passive"))
      (node (ref "SV64") (pin "5") (pinfunction "5_5") (pintype "passive"))
      (node (ref "SV64") (pin "7") (pinfunction "7_7") (pintype "passive"))
      (node (ref "SV64") (pin "9") (pinfunction "9_9") (pintype "passive"))
    )
    (net (code "617") (name "Net-(SV64-Pad10)") (class "Default")
      (node (ref "SV64") (pin "10") (pinfunction "10_10") (pintype "passive"))
      (node (ref "SV64") (pin "2") (pinfunction "2_2") (pintype "passive"))
      (node (ref "SV64") (pin "4") (pinfunction "4_4") (pintype "passive"))
      (node (ref "SV64") (pin "6") (pinfunction "6_6") (pintype "passive"))
      (node (ref "SV64") (pin "8") (pinfunction "8_8") (pintype "passive"))
    )
    (net (code "618") (name "Net-(SV65-Pad1)") (class "Default")
      (node (ref "SV65") (pin "1") (pinfunction "1_1") (pintype "passive"))
      (node (ref "SV65") (pin "3") (pinfunction "3_3") (pintype "passive"))
      (node (ref "SV65") (pin "5") (pinfunction "5_5") (pintype "passive"))
      (node (ref "SV65") (pin "7") (pinfunction "7_7") (pintype "passive"))
      (node (ref "SV65") (pin "9") (pinfunction "9_9") (pintype "passive"))
    )
    (net (code "619") (name "Net-(SV65-Pad10)") (class "Default")
      (node (ref "SV65") (pin "10") (pinfunction "10_10") (pintype "passive"))
      (node (ref "SV65") (pin "2") (pinfunction "2_2") (pintype "passive"))
      (node (ref "SV65") (pin "4") (pinfunction "4_4") (pintype "passive"))
      (node (ref "SV65") (pin "6") (pinfunction "6_6") (pintype "passive"))
      (node (ref "SV65") (pin "8") (pinfunction "8_8") (pintype "passive"))
    )
    (net (code "620") (name "Net-(SV66-Pad1)") (class "Default")
      (node (ref "SV66") (pin "1") (pinfunction "1_1") (pintype "passive"))
      (node (ref "SV66") (pin "3") (pinfunction "3_3") (pintype "passive"))
      (node (ref "SV66") (pin "5") (pinfunction "5_5") (pintype "passive"))
      (node (ref "SV66") (pin "7") (pinfunction "7_7") (pintype "passive"))
      (node (ref "SV66") (pin "9") (pinfunction "9_9") (pintype "passive"))
    )
    (net (code "621") (name "Net-(SV66-Pad10)") (class "Default")
      (node (ref "SV66") (pin "10") (pinfunction "10_10") (pintype "passive"))
      (node (ref "SV66") (pin "2") (pinfunction "2_2") (pintype "passive"))
      (node (ref "SV66") (pin "4") (pinfunction "4_4") (pintype "passive"))
      (node (ref "SV66") (pin "6") (pinfunction "6_6") (pintype "passive"))
      (node (ref "SV66") (pin "8") (pinfunction "8_8") (pintype "passive"))
    )
    (net (code "622") (name "Net-(SV67-Pad1)") (class "Default")
      (node (ref "SV67") (pin "1") (pinfunction "1_1") (pintype "passive"))
      (node (ref "SV67") (pin "3") (pinfunction "3_3") (pintype "passive"))
      (node (ref "SV67") (pin "5") (pinfunction "5_5") (pintype "passive"))
      (node (ref "SV67") (pin "7") (pinfunction "7_7") (pintype "passive"))
      (node (ref "SV67") (pin "9") (pinfunction "9_9") (pintype "passive"))
    )
    (net (code "623") (name "Net-(SV67-Pad10)") (class "Default")
      (node (ref "SV67") (pin "10") (pinfunction "10_10") (pintype "passive"))
      (node (ref "SV67") (pin "2") (pinfunction "2_2") (pintype "passive"))
      (node (ref "SV67") (pin "4") (pinfunction "4_4") (pintype "passive"))
      (node (ref "SV67") (pin "6") (pinfunction "6_6") (pintype "passive"))
      (node (ref "SV67") (pin "8") (pinfunction "8_8") (pintype "passive"))
    )
    (net (code "624") (name "Net-(SV68-Pad1)") (class "Default")
      (node (ref "SV68") (pin "1") (pinfunction "1_1") (pintype "passive"))
      (node (ref "SV68") (pin "3") (pinfunction "3_3") (pintype "passive"))
      (node (ref "SV68") (pin "5") (pinfunction "5_5") (pintype "passive"))
      (node (ref "SV68") (pin "7") (pinfunction "7_7") (pintype "passive"))
      (node (ref "SV68") (pin "9") (pinfunction "9_9") (pintype "passive"))
    )
    (net (code "625") (name "Net-(SV68-Pad10)") (class "Default")
      (node (ref "SV68") (pin "10") (pinfunction "10_10") (pintype "passive"))
      (node (ref "SV68") (pin "2") (pinfunction "2_2") (pintype "passive"))
      (node (ref "SV68") (pin "4") (pinfunction "4_4") (pintype "passive"))
      (node (ref "SV68") (pin "6") (pinfunction "6_6") (pintype "passive"))
      (node (ref "SV68") (pin "8") (pinfunction "8_8") (pintype "passive"))
    )
    (net (code "626") (name "Net-(SV69-Pad1)") (class "Default")
      (node (ref "SV69") (pin "1") (pinfunction "1_1") (pintype "passive"))
      (node (ref "SV69") (pin "3") (pinfunction "3_3") (pintype "passive"))
      (node (ref "SV69") (pin "5") (pinfunction "5_5") (pintype "passive"))
      (node (ref "SV69") (pin "7") (pinfunction "7_7") (pintype "passive"))
      (node (ref "SV69") (pin "9") (pinfunction "9_9") (pintype "passive"))
    )
    (net (code "627") (name "Net-(SV69-Pad10)") (class "Default")
      (node (ref "SV69") (pin "10") (pinfunction "10_10") (pintype "passive"))
      (node (ref "SV69") (pin "2") (pinfunction "2_2") (pintype "passive"))
      (node (ref "SV69") (pin "4") (pinfunction "4_4") (pintype "passive"))
      (node (ref "SV69") (pin "6") (pinfunction "6_6") (pintype "passive"))
      (node (ref "SV69") (pin "8") (pinfunction "8_8") (pintype "passive"))
    )
    (net (code "628") (name "Net-(SV70-Pad1)") (class "Default")
      (node (ref "SV70") (pin "1") (pinfunction "1_1") (pintype "passive"))
      (node (ref "SV70") (pin "3") (pinfunction "3_3") (pintype "passive"))
      (node (ref "SV70") (pin "5") (pinfunction "5_5") (pintype "passive"))
      (node (ref "SV70") (pin "7") (pinfunction "7_7") (pintype "passive"))
      (node (ref "SV70") (pin "9") (pinfunction "9_9") (pintype "passive"))
    )
    (net (code "629") (name "Net-(SV70-Pad10)") (class "Default")
      (node (ref "SV70") (pin "10") (pinfunction "10_10") (pintype "passive"))
      (node (ref "SV70") (pin "2") (pinfunction "2_2") (pintype "passive"))
      (node (ref "SV70") (pin "4") (pinfunction "4_4") (pintype "passive"))
      (node (ref "SV70") (pin "6") (pinfunction "6_6") (pintype "passive"))
      (node (ref "SV70") (pin "8") (pinfunction "8_8") (pintype "passive"))
    )
    (net (code "630") (name "Net-(SV71-Pad1)") (class "Default")
      (node (ref "SV71") (pin "1") (pinfunction "1_1") (pintype "passive"))
      (node (ref "SV71") (pin "3") (pinfunction "3_3") (pintype "passive"))
      (node (ref "SV71") (pin "5") (pinfunction "5_5") (pintype "passive"))
      (node (ref "SV71") (pin "7") (pinfunction "7_7") (pintype "passive"))
      (node (ref "SV71") (pin "9") (pinfunction "9_9") (pintype "passive"))
    )
    (net (code "631") (name "Net-(SV71-Pad10)") (class "Default")
      (node (ref "SV71") (pin "10") (pinfunction "10_10") (pintype "passive"))
      (node (ref "SV71") (pin "2") (pinfunction "2_2") (pintype "passive"))
      (node (ref "SV71") (pin "4") (pinfunction "4_4") (pintype "passive"))
      (node (ref "SV71") (pin "6") (pinfunction "6_6") (pintype "passive"))
      (node (ref "SV71") (pin "8") (pinfunction "8_8") (pintype "passive"))
    )
    (net (code "632") (name "Net-(SV72-Pad1)") (class "Default")
      (node (ref "SV72") (pin "1") (pinfunction "1_1") (pintype "passive"))
      (node (ref "SV72") (pin "3") (pinfunction "3_3") (pintype "passive"))
      (node (ref "SV72") (pin "5") (pinfunction "5_5") (pintype "passive"))
      (node (ref "SV72") (pin "7") (pinfunction "7_7") (pintype "passive"))
      (node (ref "SV72") (pin "9") (pinfunction "9_9") (pintype "passive"))
    )
    (net (code "633") (name "Net-(SV72-Pad10)") (class "Default")
      (node (ref "SV72") (pin "10") (pinfunction "10_10") (pintype "passive"))
      (node (ref "SV72") (pin "2") (pinfunction "2_2") (pintype "passive"))
      (node (ref "SV72") (pin "4") (pinfunction "4_4") (pintype "passive"))
      (node (ref "SV72") (pin "6") (pinfunction "6_6") (pintype "passive"))
      (node (ref "SV72") (pin "8") (pinfunction "8_8") (pintype "passive"))
    )
    (net (code "634") (name "Net-(SV73-Pad1)") (class "Default")
      (node (ref "SV73") (pin "1") (pinfunction "1_1") (pintype "passive"))
      (node (ref "SV73") (pin "3") (pinfunction "3_3") (pintype "passive"))
      (node (ref "SV73") (pin "5") (pinfunction "5_5") (pintype "passive"))
      (node (ref "SV73") (pin "7") (pinfunction "7_7") (pintype "passive"))
      (node (ref "SV73") (pin "9") (pinfunction "9_9") (pintype "passive"))
    )
    (net (code "635") (name "Net-(SV73-Pad10)") (class "Default")
      (node (ref "SV73") (pin "10") (pinfunction "10_10") (pintype "passive"))
      (node (ref "SV73") (pin "2") (pinfunction "2_2") (pintype "passive"))
      (node (ref "SV73") (pin "4") (pinfunction "4_4") (pintype "passive"))
      (node (ref "SV73") (pin "6") (pinfunction "6_6") (pintype "passive"))
      (node (ref "SV73") (pin "8") (pinfunction "8_8") (pintype "passive"))
    )
    (net (code "636") (name "Net-(SV74-Pad1)") (class "Default")
      (node (ref "SV74") (pin "1") (pinfunction "1_1") (pintype "passive"))
      (node (ref "SV74") (pin "3") (pinfunction "3_3") (pintype "passive"))
      (node (ref "SV74") (pin "5") (pinfunction "5_5") (pintype "passive"))
      (node (ref "SV74") (pin "7") (pinfunction "7_7") (pintype "passive"))
      (node (ref "SV74") (pin "9") (pinfunction "9_9") (pintype "passive"))
    )
    (net (code "637") (name "Net-(SV74-Pad10)") (class "Default")
      (node (ref "SV74") (pin "10") (pinfunction "10_10") (pintype "passive"))
      (node (ref "SV74") (pin "2") (pinfunction "2_2") (pintype "passive"))
      (node (ref "SV74") (pin "4") (pinfunction "4_4") (pintype "passive"))
      (node (ref "SV74") (pin "6") (pinfunction "6_6") (pintype "passive"))
      (node (ref "SV74") (pin "8") (pinfunction "8_8") (pintype "passive"))
    )
    (net (code "638") (name "Net-(SV75-Pad1)") (class "Default")
      (node (ref "SV75") (pin "1") (pinfunction "1_1") (pintype "passive"))
      (node (ref "SV75") (pin "3") (pinfunction "3_3") (pintype "passive"))
      (node (ref "SV75") (pin "5") (pinfunction "5_5") (pintype "passive"))
      (node (ref "SV75") (pin "7") (pinfunction "7_7") (pintype "passive"))
      (node (ref "SV75") (pin "9") (pinfunction "9_9") (pintype "passive"))
    )
    (net (code "639") (name "Net-(SV75-Pad10)") (class "Default")
      (node (ref "SV75") (pin "10") (pinfunction "10_10") (pintype "passive"))
      (node (ref "SV75") (pin "2") (pinfunction "2_2") (pintype "passive"))
      (node (ref "SV75") (pin "4") (pinfunction "4_4") (pintype "passive"))
      (node (ref "SV75") (pin "6") (pinfunction "6_6") (pintype "passive"))
      (node (ref "SV75") (pin "8") (pinfunction "8_8") (pintype "passive"))
    )
    (net (code "640") (name "Net-(SV76-Pad1)") (class "Default")
      (node (ref "SV76") (pin "1") (pinfunction "1_1") (pintype "passive"))
      (node (ref "SV76") (pin "3") (pinfunction "3_3") (pintype "passive"))
      (node (ref "SV76") (pin "5") (pinfunction "5_5") (pintype "passive"))
      (node (ref "SV76") (pin "7") (pinfunction "7_7") (pintype "passive"))
      (node (ref "SV76") (pin "9") (pinfunction "9_9") (pintype "passive"))
    )
    (net (code "641") (name "Net-(SV76-Pad10)") (class "Default")
      (node (ref "SV76") (pin "10") (pinfunction "10_10") (pintype "passive"))
      (node (ref "SV76") (pin "2") (pinfunction "2_2") (pintype "passive"))
      (node (ref "SV76") (pin "4") (pinfunction "4_4") (pintype "passive"))
      (node (ref "SV76") (pin "6") (pinfunction "6_6") (pintype "passive"))
      (node (ref "SV76") (pin "8") (pinfunction "8_8") (pintype "passive"))
    )
    (net (code "642") (name "Net-(SV77-Pad1)") (class "Default")
      (node (ref "SV77") (pin "1") (pinfunction "1_1") (pintype "passive"))
      (node (ref "SV77") (pin "3") (pinfunction "3_3") (pintype "passive"))
      (node (ref "SV77") (pin "5") (pinfunction "5_5") (pintype "passive"))
      (node (ref "SV77") (pin "7") (pinfunction "7_7") (pintype "passive"))
      (node (ref "SV77") (pin "9") (pinfunction "9_9") (pintype "passive"))
    )
    (net (code "643") (name "Net-(SV77-Pad10)") (class "Default")
      (node (ref "SV77") (pin "10") (pinfunction "10_10") (pintype "passive"))
      (node (ref "SV77") (pin "2") (pinfunction "2_2") (pintype "passive"))
      (node (ref "SV77") (pin "4") (pinfunction "4_4") (pintype "passive"))
      (node (ref "SV77") (pin "6") (pinfunction "6_6") (pintype "passive"))
      (node (ref "SV77") (pin "8") (pinfunction "8_8") (pintype "passive"))
    )
    (net (code "644") (name "Net-(SV78-Pad1)") (class "Default")
      (node (ref "SV78") (pin "1") (pinfunction "1_1") (pintype "passive"))
      (node (ref "SV78") (pin "3") (pinfunction "3_3") (pintype "passive"))
      (node (ref "SV78") (pin "5") (pinfunction "5_5") (pintype "passive"))
      (node (ref "SV78") (pin "7") (pinfunction "7_7") (pintype "passive"))
      (node (ref "SV78") (pin "9") (pinfunction "9_9") (pintype "passive"))
    )
    (net (code "645") (name "Net-(SV78-Pad10)") (class "Default")
      (node (ref "SV78") (pin "10") (pinfunction "10_10") (pintype "passive"))
      (node (ref "SV78") (pin "2") (pinfunction "2_2") (pintype "passive"))
      (node (ref "SV78") (pin "4") (pinfunction "4_4") (pintype "passive"))
      (node (ref "SV78") (pin "6") (pinfunction "6_6") (pintype "passive"))
      (node (ref "SV78") (pin "8") (pinfunction "8_8") (pintype "passive"))
    )
    (net (code "646") (name "Net-(SV79-Pad1)") (class "Default")
      (node (ref "SV79") (pin "1") (pinfunction "1_1") (pintype "passive"))
      (node (ref "SV79") (pin "3") (pinfunction "3_3") (pintype "passive"))
      (node (ref "SV79") (pin "5") (pinfunction "5_5") (pintype "passive"))
      (node (ref "SV79") (pin "7") (pinfunction "7_7") (pintype "passive"))
      (node (ref "SV79") (pin "9") (pinfunction "9_9") (pintype "passive"))
    )
    (net (code "647") (name "Net-(SV79-Pad10)") (class "Default")
      (node (ref "SV79") (pin "10") (pinfunction "10_10") (pintype "passive"))
      (node (ref "SV79") (pin "2") (pinfunction "2_2") (pintype "passive"))
      (node (ref "SV79") (pin "4") (pinfunction "4_4") (pintype "passive"))
      (node (ref "SV79") (pin "6") (pinfunction "6_6") (pintype "passive"))
      (node (ref "SV79") (pin "8") (pinfunction "8_8") (pintype "passive"))
    )
    (net (code "648") (name "Net-(SV80-Pad1)") (class "Default")
      (node (ref "SV80") (pin "1") (pinfunction "1_1") (pintype "passive"))
      (node (ref "SV80") (pin "3") (pinfunction "3_3") (pintype "passive"))
      (node (ref "SV80") (pin "5") (pinfunction "5_5") (pintype "passive"))
      (node (ref "SV80") (pin "7") (pinfunction "7_7") (pintype "passive"))
      (node (ref "SV80") (pin "9") (pinfunction "9_9") (pintype "passive"))
    )
    (net (code "649") (name "Net-(SV80-Pad10)") (class "Default")
      (node (ref "SV80") (pin "10") (pinfunction "10_10") (pintype "passive"))
      (node (ref "SV80") (pin "2") (pinfunction "2_2") (pintype "passive"))
      (node (ref "SV80") (pin "4") (pinfunction "4_4") (pintype "passive"))
      (node (ref "SV80") (pin "6") (pinfunction "6_6") (pintype "passive"))
      (node (ref "SV80") (pin "8") (pinfunction "8_8") (pintype "passive"))
    )
    (net (code "650") (name "Net-(SV81-Pad1)") (class "Default")
      (node (ref "SV81") (pin "1") (pinfunction "1_1") (pintype "passive"))
      (node (ref "SV81") (pin "3") (pinfunction "3_3") (pintype "passive"))
      (node (ref "SV81") (pin "5") (pinfunction "5_5") (pintype "passive"))
      (node (ref "SV81") (pin "7") (pinfunction "7_7") (pintype "passive"))
      (node (ref "SV81") (pin "9") (pinfunction "9_9") (pintype "passive"))
    )
    (net (code "651") (name "Net-(SV81-Pad10)") (class "Default")
      (node (ref "SV81") (pin "10") (pinfunction "10_10") (pintype "passive"))
      (node (ref "SV81") (pin "2") (pinfunction "2_2") (pintype "passive"))
      (node (ref "SV81") (pin "4") (pinfunction "4_4") (pintype "passive"))
      (node (ref "SV81") (pin "6") (pinfunction "6_6") (pintype "passive"))
      (node (ref "SV81") (pin "8") (pinfunction "8_8") (pintype "passive"))
    )
    (net (code "652") (name "Net-(SV82-Pad1)") (class "Default")
      (node (ref "SV82") (pin "1") (pinfunction "1_1") (pintype "passive"))
      (node (ref "SV82") (pin "3") (pinfunction "3_3") (pintype "passive"))
      (node (ref "SV82") (pin "5") (pinfunction "5_5") (pintype "passive"))
      (node (ref "SV82") (pin "7") (pinfunction "7_7") (pintype "passive"))
      (node (ref "SV82") (pin "9") (pinfunction "9_9") (pintype "passive"))
    )
    (net (code "653") (name "Net-(SV82-Pad10)") (class "Default")
      (node (ref "SV82") (pin "10") (pinfunction "10_10") (pintype "passive"))
      (node (ref "SV82") (pin "2") (pinfunction "2_2") (pintype "passive"))
      (node (ref "SV82") (pin "4") (pinfunction "4_4") (pintype "passive"))
      (node (ref "SV82") (pin "6") (pinfunction "6_6") (pintype "passive"))
      (node (ref "SV82") (pin "8") (pinfunction "8_8") (pintype "passive"))
    )
    (net (code "654") (name "Net-(SV83-Pad1)") (class "Default")
      (node (ref "SV83") (pin "1") (pinfunction "1_1") (pintype "passive"))
      (node (ref "SV83") (pin "3") (pinfunction "3_3") (pintype "passive"))
      (node (ref "SV83") (pin "5") (pinfunction "5_5") (pintype "passive"))
      (node (ref "SV83") (pin "7") (pinfunction "7_7") (pintype "passive"))
      (node (ref "SV83") (pin "9") (pinfunction "9_9") (pintype "passive"))
    )
    (net (code "655") (name "Net-(SV83-Pad10)") (class "Default")
      (node (ref "SV83") (pin "10") (pinfunction "10_10") (pintype "passive"))
      (node (ref "SV83") (pin "2") (pinfunction "2_2") (pintype "passive"))
      (node (ref "SV83") (pin "4") (pinfunction "4_4") (pintype "passive"))
      (node (ref "SV83") (pin "6") (pinfunction "6_6") (pintype "passive"))
      (node (ref "SV83") (pin "8") (pinfunction "8_8") (pintype "passive"))
    )
    (net (code "656") (name "Net-(SV84-Pad1)") (class "Default")
      (node (ref "SV84") (pin "1") (pinfunction "1_1") (pintype "passive"))
      (node (ref "SV84") (pin "3") (pinfunction "3_3") (pintype "passive"))
      (node (ref "SV84") (pin "5") (pinfunction "5_5") (pintype "passive"))
      (node (ref "SV84") (pin "7") (pinfunction "7_7") (pintype "passive"))
      (node (ref "SV84") (pin "9") (pinfunction "9_9") (pintype "passive"))
    )
    (net (code "657") (name "Net-(SV84-Pad10)") (class "Default")
      (node (ref "SV84") (pin "10") (pinfunction "10_10") (pintype "passive"))
      (node (ref "SV84") (pin "2") (pinfunction "2_2") (pintype "passive"))
      (node (ref "SV84") (pin "4") (pinfunction "4_4") (pintype "passive"))
      (node (ref "SV84") (pin "6") (pinfunction "6_6") (pintype "passive"))
      (node (ref "SV84") (pin "8") (pinfunction "8_8") (pintype "passive"))
    )
    (net (code "658") (name "Net-(SV85-Pad1)") (class "Default")
      (node (ref "SV85") (pin "1") (pinfunction "1_1") (pintype "passive"))
      (node (ref "SV85") (pin "3") (pinfunction "3_3") (pintype "passive"))
      (node (ref "SV85") (pin "5") (pinfunction "5_5") (pintype "passive"))
      (node (ref "SV85") (pin "7") (pinfunction "7_7") (pintype "passive"))
      (node (ref "SV85") (pin "9") (pinfunction "9_9") (pintype "passive"))
    )
    (net (code "659") (name "Net-(SV85-Pad10)") (class "Default")
      (node (ref "SV85") (pin "10") (pinfunction "10_10") (pintype "passive"))
      (node (ref "SV85") (pin "2") (pinfunction "2_2") (pintype "passive"))
      (node (ref "SV85") (pin "4") (pinfunction "4_4") (pintype "passive"))
      (node (ref "SV85") (pin "6") (pinfunction "6_6") (pintype "passive"))
      (node (ref "SV85") (pin "8") (pinfunction "8_8") (pintype "passive"))
    )
    (net (code "660") (name "Net-(SV86-Pad1)") (class "Default")
      (node (ref "SV86") (pin "1") (pinfunction "1_1") (pintype "passive"))
      (node (ref "SV86") (pin "3") (pinfunction "3_3") (pintype "passive"))
      (node (ref "SV86") (pin "5") (pinfunction "5_5") (pintype "passive"))
      (node (ref "SV86") (pin "7") (pinfunction "7_7") (pintype "passive"))
      (node (ref "SV86") (pin "9") (pinfunction "9_9") (pintype "passive"))
    )
    (net (code "661") (name "Net-(SV86-Pad10)") (class "Default")
      (node (ref "SV86") (pin "10") (pinfunction "10_10") (pintype "passive"))
      (node (ref "SV86") (pin "2") (pinfunction "2_2") (pintype "passive"))
      (node (ref "SV86") (pin "4") (pinfunction "4_4") (pintype "passive"))
      (node (ref "SV86") (pin "6") (pinfunction "6_6") (pintype "passive"))
      (node (ref "SV86") (pin "8") (pinfunction "8_8") (pintype "passive"))
    )
    (net (code "662") (name "Net-(SV87-Pad1)") (class "Default")
      (node (ref "SV87") (pin "1") (pinfunction "1_1") (pintype "passive"))
      (node (ref "SV87") (pin "3") (pinfunction "3_3") (pintype "passive"))
      (node (ref "SV87") (pin "5") (pinfunction "5_5") (pintype "passive"))
      (node (ref "SV87") (pin "7") (pinfunction "7_7") (pintype "passive"))
      (node (ref "SV87") (pin "9") (pinfunction "9_9") (pintype "passive"))
    )
    (net (code "663") (name "Net-(SV87-Pad10)") (class "Default")
      (node (ref "SV87") (pin "10") (pinfunction "10_10") (pintype "passive"))
      (node (ref "SV87") (pin "2") (pinfunction "2_2") (pintype "passive"))
      (node (ref "SV87") (pin "4") (pinfunction "4_4") (pintype "passive"))
      (node (ref "SV87") (pin "6") (pinfunction "6_6") (pintype "passive"))
      (node (ref "SV87") (pin "8") (pinfunction "8_8") (pintype "passive"))
    )
    (net (code "664") (name "Net-(SV88-Pad1)") (class "Default")
      (node (ref "SV88") (pin "1") (pinfunction "1_1") (pintype "passive"))
      (node (ref "SV88") (pin "3") (pinfunction "3_3") (pintype "passive"))
      (node (ref "SV88") (pin "5") (pinfunction "5_5") (pintype "passive"))
      (node (ref "SV88") (pin "7") (pinfunction "7_7") (pintype "passive"))
      (node (ref "SV88") (pin "9") (pinfunction "9_9") (pintype "passive"))
    )
    (net (code "665") (name "Net-(SV88-Pad10)") (class "Default")
      (node (ref "SV88") (pin "10") (pinfunction "10_10") (pintype "passive"))
      (node (ref "SV88") (pin "2") (pinfunction "2_2") (pintype "passive"))
      (node (ref "SV88") (pin "4") (pinfunction "4_4") (pintype "passive"))
      (node (ref "SV88") (pin "6") (pinfunction "6_6") (pintype "passive"))
      (node (ref "SV88") (pin "8") (pinfunction "8_8") (pintype "passive"))
    )
    (net (code "666") (name "Net-(SV89-Pad1)") (class "Default")
      (node (ref "SV89") (pin "1") (pinfunction "1_1") (pintype "passive"))
      (node (ref "SV89") (pin "3") (pinfunction "3_3") (pintype "passive"))
      (node (ref "SV89") (pin "5") (pinfunction "5_5") (pintype "passive"))
      (node (ref "SV89") (pin "7") (pinfunction "7_7") (pintype "passive"))
      (node (ref "SV89") (pin "9") (pinfunction "9_9") (pintype "passive"))
    )
    (net (code "667") (name "Net-(SV89-Pad10)") (class "Default")
      (node (ref "SV89") (pin "10") (pinfunction "10_10") (pintype "passive"))
      (node (ref "SV89") (pin "2") (pinfunction "2_2") (pintype "passive"))
      (node (ref "SV89") (pin "4") (pinfunction "4_4") (pintype "passive"))
      (node (ref "SV89") (pin "6") (pinfunction "6_6") (pintype "passive"))
      (node (ref "SV89") (pin "8") (pinfunction "8_8") (pintype "passive"))
    )
    (net (code "668") (name "Net-(SV90-Pad1)") (class "Default")
      (node (ref "SV90") (pin "1") (pinfunction "1_1") (pintype "passive"))
      (node (ref "SV90") (pin "3") (pinfunction "3_3") (pintype "passive"))
      (node (ref "SV90") (pin "5") (pinfunction "5_5") (pintype "passive"))
      (node (ref "SV90") (pin "7") (pinfunction "7_7") (pintype "passive"))
      (node (ref "SV90") (pin "9") (pinfunction "9_9") (pintype "passive"))
    )
    (net (code "669") (name "Net-(SV90-Pad10)") (class "Default")
      (node (ref "SV90") (pin "10") (pinfunction "10_10") (pintype "passive"))
      (node (ref "SV90") (pin "2") (pinfunction "2_2") (pintype "passive"))
      (node (ref "SV90") (pin "4") (pinfunction "4_4") (pintype "passive"))
      (node (ref "SV90") (pin "6") (pinfunction "6_6") (pintype "passive"))
      (node (ref "SV90") (pin "8") (pinfunction "8_8") (pintype "passive"))
    )
    (net (code "670") (name "Net-(SV91-Pad1)") (class "Default")
      (node (ref "SV91") (pin "1") (pinfunction "1_1") (pintype "passive"))
      (node (ref "SV91") (pin "3") (pinfunction "3_3") (pintype "passive"))
      (node (ref "SV91") (pin "5") (pinfunction "5_5") (pintype "passive"))
      (node (ref "SV91") (pin "7") (pinfunction "7_7") (pintype "passive"))
      (node (ref "SV91") (pin "9") (pinfunction "9_9") (pintype "passive"))
    )
    (net (code "671") (name "Net-(SV91-Pad10)") (class "Default")
      (node (ref "SV91") (pin "10") (pinfunction "10_10") (pintype "passive"))
      (node (ref "SV91") (pin "2") (pinfunction "2_2") (pintype "passive"))
      (node (ref "SV91") (pin "4") (pinfunction "4_4") (pintype "passive"))
      (node (ref "SV91") (pin "6") (pinfunction "6_6") (pintype "passive"))
      (node (ref "SV91") (pin "8") (pinfunction "8_8") (pintype "passive"))
    )
    (net (code "672") (name "Net-(SV92-Pad1)") (class "Default")
      (node (ref "SV92") (pin "1") (pinfunction "1_1") (pintype "passive"))
      (node (ref "SV92") (pin "3") (pinfunction "3_3") (pintype "passive"))
      (node (ref "SV92") (pin "5") (pinfunction "5_5") (pintype "passive"))
      (node (ref "SV92") (pin "7") (pinfunction "7_7") (pintype "passive"))
      (node (ref "SV92") (pin "9") (pinfunction "9_9") (pintype "passive"))
    )
    (net (code "673") (name "Net-(SV92-Pad10)") (class "Default")
      (node (ref "SV92") (pin "10") (pinfunction "10_10") (pintype "passive"))
      (node (ref "SV92") (pin "2") (pinfunction "2_2") (pintype "passive"))
      (node (ref "SV92") (pin "4") (pinfunction "4_4") (pintype "passive"))
      (node (ref "SV92") (pin "6") (pinfunction "6_6") (pintype "passive"))
      (node (ref "SV92") (pin "8") (pinfunction "8_8") (pintype "passive"))
    )
    (net (code "674") (name "Net-(SV93-Pad1)") (class "Default")
      (node (ref "SV93") (pin "1") (pinfunction "1_1") (pintype "passive"))
      (node (ref "SV93") (pin "3") (pinfunction "3_3") (pintype "passive"))
      (node (ref "SV93") (pin "5") (pinfunction "5_5") (pintype "passive"))
      (node (ref "SV93") (pin "7") (pinfunction "7_7") (pintype "passive"))
      (node (ref "SV93") (pin "9") (pinfunction "9_9") (pintype "passive"))
    )
    (net (code "675") (name "Net-(SV93-Pad10)") (class "Default")
      (node (ref "SV93") (pin "10") (pinfunction "10_10") (pintype "passive"))
      (node (ref "SV93") (pin "2") (pinfunction "2_2") (pintype "passive"))
      (node (ref "SV93") (pin "4") (pinfunction "4_4") (pintype "passive"))
      (node (ref "SV93") (pin "6") (pinfunction "6_6") (pintype "passive"))
      (node (ref "SV93") (pin "8") (pinfunction "8_8") (pintype "passive"))
    )
    (net (code "676") (name "Net-(SV94-Pad1)") (class "Default")
      (node (ref "SV94") (pin "1") (pinfunction "1_1") (pintype "passive"))
      (node (ref "SV94") (pin "3") (pinfunction "3_3") (pintype "passive"))
      (node (ref "SV94") (pin "5") (pinfunction "5_5") (pintype "passive"))
      (node (ref "SV94") (pin "7") (pinfunction "7_7") (pintype "passive"))
      (node (ref "SV94") (pin "9") (pinfunction "9_9") (pintype "passive"))
    )
    (net (code "677") (name "Net-(SV94-Pad10)") (class "Default")
      (node (ref "SV94") (pin "10") (pinfunction "10_10") (pintype "passive"))
      (node (ref "SV94") (pin "2") (pinfunction "2_2") (pintype "passive"))
      (node (ref "SV94") (pin "4") (pinfunction "4_4") (pintype "passive"))
      (node (ref "SV94") (pin "6") (pinfunction "6_6") (pintype "passive"))
      (node (ref "SV94") (pin "8") (pinfunction "8_8") (pintype "passive"))
    )
    (net (code "678") (name "Net-(SV95-Pad1)") (class "Default")
      (node (ref "SV95") (pin "1") (pinfunction "1_1") (pintype "passive"))
      (node (ref "SV95") (pin "3") (pinfunction "3_3") (pintype "passive"))
      (node (ref "SV95") (pin "5") (pinfunction "5_5") (pintype "passive"))
      (node (ref "SV95") (pin "7") (pinfunction "7_7") (pintype "passive"))
      (node (ref "SV95") (pin "9") (pinfunction "9_9") (pintype "passive"))
    )
    (net (code "679") (name "Net-(SV95-Pad10)") (class "Default")
      (node (ref "SV95") (pin "10") (pinfunction "10_10") (pintype "passive"))
      (node (ref "SV95") (pin "2") (pinfunction "2_2") (pintype "passive"))
      (node (ref "SV95") (pin "4") (pinfunction "4_4") (pintype "passive"))
      (node (ref "SV95") (pin "6") (pinfunction "6_6") (pintype "passive"))
      (node (ref "SV95") (pin "8") (pinfunction "8_8") (pintype "passive"))
    )
    (net (code "680") (name "Net-(SV96-Pad1)") (class "Default")
      (node (ref "SV96") (pin "1") (pinfunction "1_1") (pintype "passive"))
      (node (ref "SV96") (pin "3") (pinfunction "3_3") (pintype "passive"))
      (node (ref "SV96") (pin "5") (pinfunction "5_5") (pintype "passive"))
      (node (ref "SV96") (pin "7") (pinfunction "7_7") (pintype "passive"))
      (node (ref "SV96") (pin "9") (pinfunction "9_9") (pintype "passive"))
    )
    (net (code "681") (name "Net-(SV96-Pad10)") (class "Default")
      (node (ref "SV96") (pin "10") (pinfunction "10_10") (pintype "passive"))
      (node (ref "SV96") (pin "2") (pinfunction "2_2") (pintype "passive"))
      (node (ref "SV96") (pin "4") (pinfunction "4_4") (pintype "passive"))
      (node (ref "SV96") (pin "6") (pinfunction "6_6") (pintype "passive"))
      (node (ref "SV96") (pin "8") (pinfunction "8_8") (pintype "passive"))
    )
    (net (code "682") (name "Net-(SV97-Pad1)") (class "Default")
      (node (ref "SV97") (pin "1") (pinfunction "1_1") (pintype "passive"))
      (node (ref "SV97") (pin "3") (pinfunction "3_3") (pintype "passive"))
      (node (ref "SV97") (pin "5") (pinfunction "5_5") (pintype "passive"))
      (node (ref "SV97") (pin "7") (pinfunction "7_7") (pintype "passive"))
      (node (ref "SV97") (pin "9") (pinfunction "9_9") (pintype "passive"))
    )
    (net (code "683") (name "Net-(SV97-Pad10)") (class "Default")
      (node (ref "SV97") (pin "10") (pinfunction "10_10") (pintype "passive"))
      (node (ref "SV97") (pin "2") (pinfunction "2_2") (pintype "passive"))
      (node (ref "SV97") (pin "4") (pinfunction "4_4") (pintype "passive"))
      (node (ref "SV97") (pin "6") (pinfunction "6_6") (pintype "passive"))
      (node (ref "SV97") (pin "8") (pinfunction "8_8") (pintype "passive"))
    )
    (net (code "684") (name "Net-(SV98-Pad1)") (class "Default")
      (node (ref "SV98") (pin "1") (pinfunction "1_1") (pintype "passive"))
      (node (ref "SV98") (pin "3") (pinfunction "3_3") (pintype "passive"))
      (node (ref "SV98") (pin "5") (pinfunction "5_5") (pintype "passive"))
      (node (ref "SV98") (pin "7") (pinfunction "7_7") (pintype "passive"))
      (node (ref "SV98") (pin "9") (pinfunction "9_9") (pintype "passive"))
    )
    (net (code "685") (name "Net-(SV98-Pad10)") (class "Default")
      (node (ref "SV98") (pin "10") (pinfunction "10_10") (pintype "passive"))
      (node (ref "SV98") (pin "2") (pinfunction "2_2") (pintype "passive"))
      (node (ref "SV98") (pin "4") (pinfunction "4_4") (pintype "passive"))
      (node (ref "SV98") (pin "6") (pinfunction "6_6") (pintype "passive"))
      (node (ref "SV98") (pin "8") (pinfunction "8_8") (pintype "passive"))
    )
    (net (code "686") (name "Net-(SV99-Pad1)") (class "Default")
      (node (ref "SV99") (pin "1") (pinfunction "1_1") (pintype "passive"))
      (node (ref "SV99") (pin "3") (pinfunction "3_3") (pintype "passive"))
      (node (ref "SV99") (pin "5") (pinfunction "5_5") (pintype "passive"))
      (node (ref "SV99") (pin "7") (pinfunction "7_7") (pintype "passive"))
      (node (ref "SV99") (pin "9") (pinfunction "9_9") (pintype "passive"))
    )
    (net (code "687") (name "Net-(SV99-Pad10)") (class "Default")
      (node (ref "SV99") (pin "10") (pinfunction "10_10") (pintype "passive"))
      (node (ref "SV99") (pin "2") (pinfunction "2_2") (pintype "passive"))
      (node (ref "SV99") (pin "4") (pinfunction "4_4") (pintype "passive"))
      (node (ref "SV99") (pin "6") (pinfunction "6_6") (pintype "passive"))
      (node (ref "SV99") (pin "8") (pinfunction "8_8") (pintype "passive"))
    )
    (net (code "688") (name "Net-(SV100-Pad1)") (class "Default")
      (node (ref "SV100") (pin "1") (pinfunction "1_1") (pintype "passive"))
      (node (ref "SV100") (pin "3") (pinfunction "3_3") (pintype "passive"))
      (node (ref "SV100") (pin "5") (pinfunction "5_5") (pintype "passive"))
      (node (ref "SV100") (pin "7") (pinfunction "7_7") (pintype "passive"))
      (node (ref "SV100") (pin "9") (pinfunction "9_9") (pintype "passive"))
    )
    (net (code "689") (name "Net-(SV100-Pad10)") (class "Default")
      (node (ref "SV100") (pin "10") (pinfunction "10_10") (pintype "passive"))
      (node (ref "SV100") (pin "2") (pinfunction "2_2") (pintype "passive"))
      (node (ref "SV100") (pin "4") (pinfunction "4_4") (pintype "passive"))
      (node (ref "SV100") (pin "6") (pinfunction "6_6") (pintype "passive"))
      (node (ref "SV100") (pin "8") (pinfunction "8_8") (pintype "passive"))
    )
    (net (code "690") (name "Net-(SV101-Pad1)") (class "Default")
      (node (ref "SV101") (pin "1") (pinfunction "1_1") (pintype "passive"))
      (node (ref "SV101") (pin "3") (pinfunction "3_3") (pintype "passive"))
      (node (ref "SV101") (pin "5") (pinfunction "5_5") (pintype "passive"))
      (node (ref "SV101") (pin "7") (pinfunction "7_7") (pintype "passive"))
      (node (ref "SV101") (pin "9") (pinfunction "9_9") (pintype "passive"))
    )
    (net (code "691") (name "Net-(SV101-Pad10)") (class "Default")
      (node (ref "SV101") (pin "10") (pinfunction "10_10") (pintype "passive"))
      (node (ref "SV101") (pin "2") (pinfunction "2_2") (pintype "passive"))
      (node (ref "SV101") (pin "4") (pinfunction "4_4") (pintype "passive"))
      (node (ref "SV101") (pin "6") (pinfunction "6_6") (pintype "passive"))
      (node (ref "SV101") (pin "8") (pinfunction "8_8") (pintype "passive"))
    )
    (net (code "692") (name "Net-(SV102-Pad1)") (class "Default")
      (node (ref "SV102") (pin "1") (pinfunction "1_1") (pintype "passive"))
      (node (ref "SV102") (pin "3") (pinfunction "3_3") (pintype "passive"))
      (node (ref "SV102") (pin "5") (pinfunction "5_5") (pintype "passive"))
      (node (ref "SV102") (pin "7") (pinfunction "7_7") (pintype "passive"))
      (node (ref "SV102") (pin "9") (pinfunction "9_9") (pintype "passive"))
    )
    (net (code "693") (name "Net-(SV102-Pad10)") (class "Default")
      (node (ref "SV102") (pin "10") (pinfunction "10_10") (pintype "passive"))
      (node (ref "SV102") (pin "2") (pinfunction "2_2") (pintype "passive"))
      (node (ref "SV102") (pin "4") (pinfunction "4_4") (pintype "passive"))
      (node (ref "SV102") (pin "6") (pinfunction "6_6") (pintype "passive"))
      (node (ref "SV102") (pin "8") (pinfunction "8_8") (pintype "passive"))
    )
    (net (code "694") (name "Net-(SV103-Pad1)") (class "Default")
      (node (ref "SV103") (pin "1") (pinfunction "1_1") (pintype "passive"))
      (node (ref "SV103") (pin "3") (pinfunction "3_3") (pintype "passive"))
      (node (ref "SV103") (pin "5") (pinfunction "5_5") (pintype "passive"))
      (node (ref "SV103") (pin "7") (pinfunction "7_7") (pintype "passive"))
      (node (ref "SV103") (pin "9") (pinfunction "9_9") (pintype "passive"))
    )
    (net (code "695") (name "Net-(SV103-Pad10)") (class "Default")
      (node (ref "SV103") (pin "10") (pinfunction "10_10") (pintype "passive"))
      (node (ref "SV103") (pin "2") (pinfunction "2_2") (pintype "passive"))
      (node (ref "SV103") (pin "4") (pinfunction "4_4") (pintype "passive"))
      (node (ref "SV103") (pin "6") (pinfunction "6_6") (pintype "passive"))
      (node (ref "SV103") (pin "8") (pinfunction "8_8") (pintype "passive"))
    )
    (net (code "696") (name "Net-(SV104-Pad1)") (class "Default")
      (node (ref "SV104") (pin "1") (pinfunction "1_1") (pintype "passive"))
      (node (ref "SV104") (pin "3") (pinfunction "3_3") (pintype "passive"))
      (node (ref "SV104") (pin "5") (pinfunction "5_5") (pintype "passive"))
      (node (ref "SV104") (pin "7") (pinfunction "7_7") (pintype "passive"))
      (node (ref "SV104") (pin "9") (pinfunction "9_9") (pintype "passive"))
    )
    (net (code "697") (name "Net-(SV104-Pad10)") (class "Default")
      (node (ref "SV104") (pin "10") (pinfunction "10_10") (pintype "passive"))
      (node (ref "SV104") (pin "2") (pinfunction "2_2") (pintype "passive"))
      (node (ref "SV104") (pin "4") (pinfunction "4_4") (pintype "passive"))
      (node (ref "SV104") (pin "6") (pinfunction "6_6") (pintype "passive"))
      (node (ref "SV104") (pin "8") (pinfunction "8_8") (pintype "passive"))
    )
    (net (code "698") (name "Net-(SV105-Pad1)") (class "Default")
      (node (ref "SV105") (pin "1") (pinfunction "1_1") (pintype "passive"))
      (node (ref "SV105") (pin "3") (pinfunction "3_3") (pintype "passive"))
      (node (ref "SV105") (pin "5") (pinfunction "5_5") (pintype "passive"))
      (node (ref "SV105") (pin "7") (pinfunction "7_7") (pintype "passive"))
      (node (ref "SV105") (pin "9") (pinfunction "9_9") (pintype "passive"))
    )
    (net (code "699") (name "Net-(SV105-Pad10)") (class "Default")
      (node (ref "SV105") (pin "10") (pinfunction "10_10") (pintype "passive"))
      (node (ref "SV105") (pin "2") (pinfunction "2_2") (pintype "passive"))
      (node (ref "SV105") (pin "4") (pinfunction "4_4") (pintype "passive"))
      (node (ref "SV105") (pin "6") (pinfunction "6_6") (pintype "passive"))
      (node (ref "SV105") (pin "8") (pinfunction "8_8") (pintype "passive"))
    )
    (net (code "700") (name "Net-(SV106-Pad1)") (class "Default")
      (node (ref "SV106") (pin "1") (pinfunction "1_1") (pintype "passive"))
      (node (ref "SV106") (pin "3") (pinfunction "3_3") (pintype "passive"))
      (node (ref "SV106") (pin "5") (pinfunction "5_5") (pintype "passive"))
      (node (ref "SV106") (pin "7") (pinfunction "7_7") (pintype "passive"))
      (node (ref "SV106") (pin "9") (pinfunction "9_9") (pintype "passive"))
    )
    (net (code "701") (name "Net-(SV106-Pad10)") (class "Default")
      (node (ref "SV106") (pin "10") (pinfunction "10_10") (pintype "passive"))
      (node (ref "SV106") (pin "2") (pinfunction "2_2") (pintype "passive"))
      (node (ref "SV106") (pin "4") (pinfunction "4_4") (pintype "passive"))
      (node (ref "SV106") (pin "6") (pinfunction "6_6") (pintype "passive"))
      (node (ref "SV106") (pin "8") (pinfunction "8_8") (pintype "passive"))
    )
    (net (code "702") (name "Net-(SV107-Pad1)") (class "Default")
      (node (ref "SV107") (pin "1") (pinfunction "1_1") (pintype "passive"))
      (node (ref "SV107") (pin "3") (pinfunction "3_3") (pintype "passive"))
      (node (ref "SV107") (pin "5") (pinfunction "5_5") (pintype "passive"))
      (node (ref "SV107") (pin "7") (pinfunction "7_7") (pintype "passive"))
      (node (ref "SV107") (pin "9") (pinfunction "9_9") (pintype "passive"))
    )
    (net (code "703") (name "Net-(SV107-Pad10)") (class "Default")
      (node (ref "SV107") (pin "10") (pinfunction "10_10") (pintype "passive"))
      (node (ref "SV107") (pin "2") (pinfunction "2_2") (pintype "passive"))
      (node (ref "SV107") (pin "4") (pinfunction "4_4") (pintype "passive"))
      (node (ref "SV107") (pin "6") (pinfunction "6_6") (pintype "passive"))
      (node (ref "SV107") (pin "8") (pinfunction "8_8") (pintype "passive"))
    )
    (net (code "704") (name "Net-(SV108-Pad1)") (class "Default")
      (node (ref "SV108") (pin "1") (pinfunction "1_1") (pintype "passive"))
      (node (ref "SV108") (pin "3") (pinfunction "3_3") (pintype "passive"))
      (node (ref "SV108") (pin "5") (pinfunction "5_5") (pintype "passive"))
      (node (ref "SV108") (pin "7") (pinfunction "7_7") (pintype "passive"))
      (node (ref "SV108") (pin "9") (pinfunction "9_9") (pintype "passive"))
    )
    (net (code "705") (name "Net-(SV108-Pad10)") (class "Default")
      (node (ref "SV108") (pin "10") (pinfunction "10_10") (pintype "passive"))
      (node (ref "SV108") (pin "2") (pinfunction "2_2") (pintype "passive"))
      (node (ref "SV108") (pin "4") (pinfunction "4_4") (pintype "passive"))
      (node (ref "SV108") (pin "6") (pinfunction "6_6") (pintype "passive"))
      (node (ref "SV108") (pin "8") (pinfunction "8_8") (pintype "passive"))
    )
    (net (code "706") (name "Net-(SV109-Pad1)") (class "Default")
      (node (ref "SV109") (pin "1") (pinfunction "1_1") (pintype "passive"))
      (node (ref "SV109") (pin "3") (pinfunction "3_3") (pintype "passive"))
      (node (ref "SV109") (pin "5") (pinfunction "5_5") (pintype "passive"))
      (node (ref "SV109") (pin "7") (pinfunction "7_7") (pintype "passive"))
      (node (ref "SV109") (pin "9") (pinfunction "9_9") (pintype "passive"))
    )
    (net (code "707") (name "Net-(SV109-Pad10)") (class "Default")
      (node (ref "SV109") (pin "10") (pinfunction "10_10") (pintype "passive"))
      (node (ref "SV109") (pin "2") (pinfunction "2_2") (pintype "passive"))
      (node (ref "SV109") (pin "4") (pinfunction "4_4") (pintype "passive"))
      (node (ref "SV109") (pin "6") (pinfunction "6_6") (pintype "passive"))
      (node (ref "SV109") (pin "8") (pinfunction "8_8") (pintype "passive"))
    )
    (net (code "708") (name "Net-(SV110-Pad1)") (class "Default")
      (node (ref "SV110") (pin "1") (pinfunction "1_1") (pintype "passive"))
      (node (ref "SV110") (pin "3") (pinfunction "3_3") (pintype "passive"))
      (node (ref "SV110") (pin "5") (pinfunction "5_5") (pintype "passive"))
      (node (ref "SV110") (pin "7") (pinfunction "7_7") (pintype "passive"))
      (node (ref "SV110") (pin "9") (pinfunction "9_9") (pintype "passive"))
    )
    (net (code "709") (name "Net-(SV110-Pad10)") (class "Default")
      (node (ref "SV110") (pin "10") (pinfunction "10_10") (pintype "passive"))
      (node (ref "SV110") (pin "2") (pinfunction "2_2") (pintype "passive"))
      (node (ref "SV110") (pin "4") (pinfunction "4_4") (pintype "passive"))
      (node (ref "SV110") (pin "6") (pinfunction "6_6") (pintype "passive"))
      (node (ref "SV110") (pin "8") (pinfunction "8_8") (pintype "passive"))
    )
    (net (code "710") (name "Net-(SV111-Pad1)") (class "Default")
      (node (ref "SV111") (pin "1") (pinfunction "1_1") (pintype "passive"))
      (node (ref "SV111") (pin "3") (pinfunction "3_3") (pintype "passive"))
      (node (ref "SV111") (pin "5") (pinfunction "5_5") (pintype "passive"))
      (node (ref "SV111") (pin "7") (pinfunction "7_7") (pintype "passive"))
      (node (ref "SV111") (pin "9") (pinfunction "9_9") (pintype "passive"))
    )
    (net (code "711") (name "Net-(SV111-Pad10)") (class "Default")
      (node (ref "SV111") (pin "10") (pinfunction "10_10") (pintype "passive"))
      (node (ref "SV111") (pin "2") (pinfunction "2_2") (pintype "passive"))
      (node (ref "SV111") (pin "4") (pinfunction "4_4") (pintype "passive"))
      (node (ref "SV111") (pin "6") (pinfunction "6_6") (pintype "passive"))
      (node (ref "SV111") (pin "8") (pinfunction "8_8") (pintype "passive"))
    )
    (net (code "712") (name "Net-(SV112-Pad1)") (class "Default")
      (node (ref "SV112") (pin "1") (pinfunction "1_1") (pintype "passive"))
      (node (ref "SV112") (pin "3") (pinfunction "3_3") (pintype "passive"))
      (node (ref "SV112") (pin "5") (pinfunction "5_5") (pintype "passive"))
      (node (ref "SV112") (pin "7") (pinfunction "7_7") (pintype "passive"))
      (node (ref "SV112") (pin "9") (pinfunction "9_9") (pintype "passive"))
    )
    (net (code "713") (name "Net-(SV112-Pad10)") (class "Default")
      (node (ref "SV112") (pin "10") (pinfunction "10_10") (pintype "passive"))
      (node (ref "SV112") (pin "2") (pinfunction "2_2") (pintype "passive"))
      (node (ref "SV112") (pin "4") (pinfunction "4_4") (pintype "passive"))
      (node (ref "SV112") (pin "6") (pinfunction "6_6") (pintype "passive"))
      (node (ref "SV112") (pin "8") (pinfunction "8_8") (pintype "passive"))
    )
    (net (code "714") (name "Net-(SV113-Pad1)") (class "Default")
      (node (ref "SV113") (pin "1") (pinfunction "1_1") (pintype "passive"))
      (node (ref "SV113") (pin "3") (pinfunction "3_3") (pintype "passive"))
      (node (ref "SV113") (pin "5") (pinfunction "5_5") (pintype "passive"))
      (node (ref "SV113") (pin "7") (pinfunction "7_7") (pintype "passive"))
      (node (ref "SV113") (pin "9") (pinfunction "9_9") (pintype "passive"))
    )
    (net (code "715") (name "Net-(SV113-Pad10)") (class "Default")
      (node (ref "SV113") (pin "10") (pinfunction "10_10") (pintype "passive"))
      (node (ref "SV113") (pin "2") (pinfunction "2_2") (pintype "passive"))
      (node (ref "SV113") (pin "4") (pinfunction "4_4") (pintype "passive"))
      (node (ref "SV113") (pin "6") (pinfunction "6_6") (pintype "passive"))
      (node (ref "SV113") (pin "8") (pinfunction "8_8") (pintype "passive"))
    )
    (net (code "716") (name "Net-(SV114-Pad1)") (class "Default")
      (node (ref "SV114") (pin "1") (pinfunction "1_1") (pintype "passive"))
      (node (ref "SV114") (pin "3") (pinfunction "3_3") (pintype "passive"))
      (node (ref "SV114") (pin "5") (pinfunction "5_5") (pintype "passive"))
      (node (ref "SV114") (pin "7") (pinfunction "7_7") (pintype "passive"))
      (node (ref "SV114") (pin "9") (pinfunction "9_9") (pintype "passive"))
    )
    (net (code "717") (name "Net-(SV114-Pad10)") (class "Default")
      (node (ref "SV114") (pin "10") (pinfunction "10_10") (pintype "passive"))
      (node (ref "SV114") (pin "2") (pinfunction "2_2") (pintype "passive"))
      (node (ref "SV114") (pin "4") (pinfunction "4_4") (pintype "passive"))
      (node (ref "SV114") (pin "6") (pinfunction "6_6") (pintype "passive"))
      (node (ref "SV114") (pin "8") (pinfunction "8_8") (pintype "passive"))
    )
    (net (code "718") (name "Net-(SV115-Pad1)") (class "Default")
      (node (ref "SV115") (pin "1") (pinfunction "1_1") (pintype "passive"))
      (node (ref "SV115") (pin "3") (pinfunction "3_3") (pintype "passive"))
      (node (ref "SV115") (pin "5") (pinfunction "5_5") (pintype "passive"))
      (node (ref "SV115") (pin "7") (pinfunction "7_7") (pintype "passive"))
      (node (ref "SV115") (pin "9") (pinfunction "9_9") (pintype "passive"))
    )
    (net (code "719") (name "Net-(SV115-Pad10)") (class "Default")
      (node (ref "SV115") (pin "10") (pinfunction "10_10") (pintype "passive"))
      (node (ref "SV115") (pin "2") (pinfunction "2_2") (pintype "passive"))
      (node (ref "SV115") (pin "4") (pinfunction "4_4") (pintype "passive"))
      (node (ref "SV115") (pin "6") (pinfunction "6_6") (pintype "passive"))
      (node (ref "SV115") (pin "8") (pinfunction "8_8") (pintype "passive"))
    )
    (net (code "720") (name "Net-(SV116-Pad1)") (class "Default")
      (node (ref "SV116") (pin "1") (pinfunction "1_1") (pintype "passive"))
      (node (ref "SV116") (pin "3") (pinfunction "3_3") (pintype "passive"))
      (node (ref "SV116") (pin "5") (pinfunction "5_5") (pintype "passive"))
      (node (ref "SV116") (pin "7") (pinfunction "7_7") (pintype "passive"))
      (node (ref "SV116") (pin "9") (pinfunction "9_9") (pintype "passive"))
    )
    (net (code "721") (name "Net-(SV116-Pad10)") (class "Default")
      (node (ref "SV116") (pin "10") (pinfunction "10_10") (pintype "passive"))
      (node (ref "SV116") (pin "2") (pinfunction "2_2") (pintype "passive"))
      (node (ref "SV116") (pin "4") (pinfunction "4_4") (pintype "passive"))
      (node (ref "SV116") (pin "6") (pinfunction "6_6") (pintype "passive"))
      (node (ref "SV116") (pin "8") (pinfunction "8_8") (pintype "passive"))
    )
    (net (code "722") (name "Net-(SV117-Pad1)") (class "Default")
      (node (ref "SV117") (pin "1") (pinfunction "1_1") (pintype "passive"))
      (node (ref "SV117") (pin "3") (pinfunction "3_3") (pintype "passive"))
      (node (ref "SV117") (pin "5") (pinfunction "5_5") (pintype "passive"))
      (node (ref "SV117") (pin "7") (pinfunction "7_7") (pintype "passive"))
      (node (ref "SV117") (pin "9") (pinfunction "9_9") (pintype "passive"))
    )
    (net (code "723") (name "Net-(SV117-Pad10)") (class "Default")
      (node (ref "SV117") (pin "10") (pinfunction "10_10") (pintype "passive"))
      (node (ref "SV117") (pin "2") (pinfunction "2_2") (pintype "passive"))
      (node (ref "SV117") (pin "4") (pinfunction "4_4") (pintype "passive"))
      (node (ref "SV117") (pin "6") (pinfunction "6_6") (pintype "passive"))
      (node (ref "SV117") (pin "8") (pinfunction "8_8") (pintype "passive"))
    )
    (net (code "724") (name "Net-(SV118-Pad1)") (class "Default")
      (node (ref "SV118") (pin "1") (pinfunction "1_1") (pintype "passive"))
      (node (ref "SV118") (pin "3") (pinfunction "3_3") (pintype "passive"))
      (node (ref "SV118") (pin "5") (pinfunction "5_5") (pintype "passive"))
      (node (ref "SV118") (pin "7") (pinfunction "7_7") (pintype "passive"))
      (node (ref "SV118") (pin "9") (pinfunction "9_9") (pintype "passive"))
    )
    (net (code "725") (name "Net-(SV118-Pad10)") (class "Default")
      (node (ref "SV118") (pin "10") (pinfunction "10_10") (pintype "passive"))
      (node (ref "SV118") (pin "2") (pinfunction "2_2") (pintype "passive"))
      (node (ref "SV118") (pin "4") (pinfunction "4_4") (pintype "passive"))
      (node (ref "SV118") (pin "6") (pinfunction "6_6") (pintype "passive"))
      (node (ref "SV118") (pin "8") (pinfunction "8_8") (pintype "passive"))
    )
    (net (code "726") (name "Net-(SV119-Pad1)") (class "Default")
      (node (ref "SV119") (pin "1") (pinfunction "1_1") (pintype "passive"))
      (node (ref "SV119") (pin "3") (pinfunction "3_3") (pintype "passive"))
      (node (ref "SV119") (pin "5") (pinfunction "5_5") (pintype "passive"))
      (node (ref "SV119") (pin "7") (pinfunction "7_7") (pintype "passive"))
      (node (ref "SV119") (pin "9") (pinfunction "9_9") (pintype "passive"))
    )
    (net (code "727") (name "Net-(SV119-Pad10)") (class "Default")
      (node (ref "SV119") (pin "10") (pinfunction "10_10") (pintype "passive"))
      (node (ref "SV119") (pin "2") (pinfunction "2_2") (pintype "passive"))
      (node (ref "SV119") (pin "4") (pinfunction "4_4") (pintype "passive"))
      (node (ref "SV119") (pin "6") (pinfunction "6_6") (pintype "passive"))
      (node (ref "SV119") (pin "8") (pinfunction "8_8") (pintype "passive"))
    )
    (net (code "728") (name "Net-(SV120-Pad1)") (class "Default")
      (node (ref "SV120") (pin "1") (pinfunction "1_1") (pintype "passive"))
      (node (ref "SV120") (pin "3") (pinfunction "3_3") (pintype "passive"))
      (node (ref "SV120") (pin "5") (pinfunction "5_5") (pintype "passive"))
      (node (ref "SV120") (pin "7") (pinfunction "7_7") (pintype "passive"))
      (node (ref "SV120") (pin "9") (pinfunction "9_9") (pintype "passive"))
    )
    (net (code "729") (name "Net-(SV120-Pad10)") (class "Default")
      (node (ref "SV120") (pin "10") (pinfunction "10_10") (pintype "passive"))
      (node (ref "SV120") (pin "2") (pinfunction "2_2") (pintype "passive"))
      (node (ref "SV120") (pin "4") (pinfunction "4_4") (pintype "passive"))
      (node (ref "SV120") (pin "6") (pinfunction "6_6") (pintype "passive"))
      (node (ref "SV120") (pin "8") (pinfunction "8_8") (pintype "passive"))
    )
    (net (code "730") (name "Net-(SV121-Pad1)") (class "Default")
      (node (ref "SV121") (pin "1") (pinfunction "1_1") (pintype "passive"))
      (node (ref "SV121") (pin "3") (pinfunction "3_3") (pintype "passive"))
      (node (ref "SV121") (pin "5") (pinfunction "5_5") (pintype "passive"))
      (node (ref "SV121") (pin "7") (pinfunction "7_7") (pintype "passive"))
      (node (ref "SV121") (pin "9") (pinfunction "9_9") (pintype "passive"))
    )
    (net (code "731") (name "Net-(SV121-Pad10)") (class "Default")
      (node (ref "SV121") (pin "10") (pinfunction "10_10") (pintype "passive"))
      (node (ref "SV121") (pin "2") (pinfunction "2_2") (pintype "passive"))
      (node (ref "SV121") (pin "4") (pinfunction "4_4") (pintype "passive"))
      (node (ref "SV121") (pin "6") (pinfunction "6_6") (pintype "passive"))
      (node (ref "SV121") (pin "8") (pinfunction "8_8") (pintype "passive"))
    )
    (net (code "732") (name "Net-(SV122-Pad1)") (class "Default")
      (node (ref "SV122") (pin "1") (pinfunction "1_1") (pintype "passive"))
      (node (ref "SV122") (pin "3") (pinfunction "3_3") (pintype "passive"))
      (node (ref "SV122") (pin "5") (pinfunction "5_5") (pintype "passive"))
      (node (ref "SV122") (pin "7") (pinfunction "7_7") (pintype "passive"))
      (node (ref "SV122") (pin "9") (pinfunction "9_9") (pintype "passive"))
    )
    (net (code "733") (name "Net-(SV122-Pad10)") (class "Default")
      (node (ref "SV122") (pin "10") (pinfunction "10_10") (pintype "passive"))
      (node (ref "SV122") (pin "2") (pinfunction "2_2") (pintype "passive"))
      (node (ref "SV122") (pin "4") (pinfunction "4_4") (pintype "passive"))
      (node (ref "SV122") (pin "6") (pinfunction "6_6") (pintype "passive"))
      (node (ref "SV122") (pin "8") (pinfunction "8_8") (pintype "passive"))
    )
    (net (code "734") (name "Net-(SV123-Pad1)") (class "Default")
      (node (ref "SV123") (pin "1") (pinfunction "1_1") (pintype "passive"))
      (node (ref "SV123") (pin "3") (pinfunction "3_3") (pintype "passive"))
      (node (ref "SV123") (pin "5") (pinfunction "5_5") (pintype "passive"))
      (node (ref "SV123") (pin "7") (pinfunction "7_7") (pintype "passive"))
      (node (ref "SV123") (pin "9") (pinfunction "9_9") (pintype "passive"))
    )
    (net (code "735") (name "Net-(SV123-Pad10)") (class "Default")
      (node (ref "SV123") (pin "10") (pinfunction "10_10") (pintype "passive"))
      (node (ref "SV123") (pin "2") (pinfunction "2_2") (pintype "passive"))
      (node (ref "SV123") (pin "4") (pinfunction "4_4") (pintype "passive"))
      (node (ref "SV123") (pin "6") (pinfunction "6_6") (pintype "passive"))
      (node (ref "SV123") (pin "8") (pinfunction "8_8") (pintype "passive"))
    )
    (net (code "736") (name "Net-(SV124-Pad1)") (class "Default")
      (node (ref "SV124") (pin "1") (pinfunction "1_1") (pintype "passive"))
      (node (ref "SV124") (pin "3") (pinfunction "3_3") (pintype "passive"))
      (node (ref "SV124") (pin "5") (pinfunction "5_5") (pintype "passive"))
      (node (ref "SV124") (pin "7") (pinfunction "7_7") (pintype "passive"))
      (node (ref "SV124") (pin "9") (pinfunction "9_9") (pintype "passive"))
    )
    (net (code "737") (name "Net-(SV124-Pad10)") (class "Default")
      (node (ref "SV124") (pin "10") (pinfunction "10_10") (pintype "passive"))
      (node (ref "SV124") (pin "2") (pinfunction "2_2") (pintype "passive"))
      (node (ref "SV124") (pin "4") (pinfunction "4_4") (pintype "passive"))
      (node (ref "SV124") (pin "6") (pinfunction "6_6") (pintype "passive"))
      (node (ref "SV124") (pin "8") (pinfunction "8_8") (pintype "passive"))
    )
    (net (code "738") (name "Net-(SV126-Pad1)") (class "Default")
      (node (ref "SV126") (pin "1") (pinfunction "1_1") (pintype "passive"))
      (node (ref "SV126") (pin "3") (pinfunction "3_3") (pintype "passive"))
      (node (ref "SV126") (pin "5") (pinfunction "5_5") (pintype "passive"))
      (node (ref "SV126") (pin "7") (pinfunction "7_7") (pintype "passive"))
      (node (ref "SV126") (pin "9") (pinfunction "9_9") (pintype "passive"))
    )
    (net (code "739") (name "Net-(SV126-Pad10)") (class "Default")
      (node (ref "SV126") (pin "10") (pinfunction "10_10") (pintype "passive"))
      (node (ref "SV126") (pin "2") (pinfunction "2_2") (pintype "passive"))
      (node (ref "SV126") (pin "4") (pinfunction "4_4") (pintype "passive"))
      (node (ref "SV126") (pin "6") (pinfunction "6_6") (pintype "passive"))
      (node (ref "SV126") (pin "8") (pinfunction "8_8") (pintype "passive"))
    )
    (net (code "740") (name "Net-(SV128-Pad1)") (class "Default")
      (node (ref "SV128") (pin "1") (pinfunction "1_1") (pintype "passive"))
      (node (ref "SV128") (pin "3") (pinfunction "3_3") (pintype "passive"))
      (node (ref "SV128") (pin "5") (pinfunction "5_5") (pintype "passive"))
      (node (ref "SV128") (pin "7") (pinfunction "7_7") (pintype "passive"))
      (node (ref "SV128") (pin "9") (pinfunction "9_9") (pintype "passive"))
    )
    (net (code "741") (name "Net-(SV128-Pad10)") (class "Default")
      (node (ref "SV128") (pin "10") (pinfunction "10_10") (pintype "passive"))
      (node (ref "SV128") (pin "2") (pinfunction "2_2") (pintype "passive"))
      (node (ref "SV128") (pin "4") (pinfunction "4_4") (pintype "passive"))
      (node (ref "SV128") (pin "6") (pinfunction "6_6") (pintype "passive"))
      (node (ref "SV128") (pin "8") (pinfunction "8_8") (pintype "passive"))
    )
    (net (code "742") (name "Net-(SV130-Pad1)") (class "Default")
      (node (ref "SV130") (pin "1") (pinfunction "1_1") (pintype "passive"))
      (node (ref "SV130") (pin "3") (pinfunction "3_3") (pintype "passive"))
      (node (ref "SV130") (pin "5") (pinfunction "5_5") (pintype "passive"))
      (node (ref "SV130") (pin "7") (pinfunction "7_7") (pintype "passive"))
      (node (ref "SV130") (pin "9") (pinfunction "9_9") (pintype "passive"))
    )
    (net (code "743") (name "Net-(SV130-Pad10)") (class "Default")
      (node (ref "SV130") (pin "10") (pinfunction "10_10") (pintype "passive"))
      (node (ref "SV130") (pin "2") (pinfunction "2_2") (pintype "passive"))
      (node (ref "SV130") (pin "4") (pinfunction "4_4") (pintype "passive"))
      (node (ref "SV130") (pin "6") (pinfunction "6_6") (pintype "passive"))
      (node (ref "SV130") (pin "8") (pinfunction "8_8") (pintype "passive"))
    )
    (net (code "744") (name "Net-(SV132-Pad1)") (class "Default")
      (node (ref "SV132") (pin "1") (pinfunction "1_1") (pintype "passive"))
      (node (ref "SV132") (pin "3") (pinfunction "3_3") (pintype "passive"))
      (node (ref "SV132") (pin "5") (pinfunction "5_5") (pintype "passive"))
      (node (ref "SV132") (pin "7") (pinfunction "7_7") (pintype "passive"))
      (node (ref "SV132") (pin "9") (pinfunction "9_9") (pintype "passive"))
    )
    (net (code "745") (name "Net-(SV132-Pad10)") (class "Default")
      (node (ref "SV132") (pin "10") (pinfunction "10_10") (pintype "passive"))
      (node (ref "SV132") (pin "2") (pinfunction "2_2") (pintype "passive"))
      (node (ref "SV132") (pin "4") (pinfunction "4_4") (pintype "passive"))
      (node (ref "SV132") (pin "6") (pinfunction "6_6") (pintype "passive"))
      (node (ref "SV132") (pin "8") (pinfunction "8_8") (pintype "passive"))
    )
    (net (code "746") (name "Net-(SV133-Pad1)") (class "Default")
      (node (ref "SV133") (pin "1") (pinfunction "1_1") (pintype "passive"))
      (node (ref "SV133") (pin "3") (pinfunction "3_3") (pintype "passive"))
      (node (ref "SV133") (pin "5") (pinfunction "5_5") (pintype "passive"))
      (node (ref "SV133") (pin "7") (pinfunction "7_7") (pintype "passive"))
      (node (ref "SV133") (pin "9") (pinfunction "9_9") (pintype "passive"))
    )
    (net (code "747") (name "Net-(SV133-Pad10)") (class "Default")
      (node (ref "SV133") (pin "10") (pinfunction "10_10") (pintype "passive"))
      (node (ref "SV133") (pin "2") (pinfunction "2_2") (pintype "passive"))
      (node (ref "SV133") (pin "4") (pinfunction "4_4") (pintype "passive"))
      (node (ref "SV133") (pin "6") (pinfunction "6_6") (pintype "passive"))
      (node (ref "SV133") (pin "8") (pinfunction "8_8") (pintype "passive"))
    )
    (net (code "748") (name "Net-(SV134-Pad1)") (class "Default")
      (node (ref "SV134") (pin "1") (pinfunction "1_1") (pintype "passive"))
      (node (ref "SV134") (pin "3") (pinfunction "3_3") (pintype "passive"))
      (node (ref "SV134") (pin "5") (pinfunction "5_5") (pintype "passive"))
      (node (ref "SV134") (pin "7") (pinfunction "7_7") (pintype "passive"))
      (node (ref "SV134") (pin "9") (pinfunction "9_9") (pintype "passive"))
    )
    (net (code "749") (name "Net-(SV134-Pad10)") (class "Default")
      (node (ref "SV134") (pin "10") (pinfunction "10_10") (pintype "passive"))
      (node (ref "SV134") (pin "2") (pinfunction "2_2") (pintype "passive"))
      (node (ref "SV134") (pin "4") (pinfunction "4_4") (pintype "passive"))
      (node (ref "SV134") (pin "6") (pinfunction "6_6") (pintype "passive"))
      (node (ref "SV134") (pin "8") (pinfunction "8_8") (pintype "passive"))
    )
    (net (code "750") (name "Net-(SV135-Pad1)") (class "Default")
      (node (ref "SV135") (pin "1") (pinfunction "1_1") (pintype "passive"))
      (node (ref "SV135") (pin "3") (pinfunction "3_3") (pintype "passive"))
      (node (ref "SV135") (pin "5") (pinfunction "5_5") (pintype "passive"))
      (node (ref "SV135") (pin "7") (pinfunction "7_7") (pintype "passive"))
      (node (ref "SV135") (pin "9") (pinfunction "9_9") (pintype "passive"))
    )
    (net (code "751") (name "Net-(SV135-Pad10)") (class "Default")
      (node (ref "SV135") (pin "10") (pinfunction "10_10") (pintype "passive"))
      (node (ref "SV135") (pin "2") (pinfunction "2_2") (pintype "passive"))
      (node (ref "SV135") (pin "4") (pinfunction "4_4") (pintype "passive"))
      (node (ref "SV135") (pin "6") (pinfunction "6_6") (pintype "passive"))
      (node (ref "SV135") (pin "8") (pinfunction "8_8") (pintype "passive"))
    )
    (net (code "752") (name "Net-(SV136-Pad1)") (class "Default")
      (node (ref "SV136") (pin "1") (pinfunction "1_1") (pintype "passive"))
      (node (ref "SV136") (pin "3") (pinfunction "3_3") (pintype "passive"))
      (node (ref "SV136") (pin "5") (pinfunction "5_5") (pintype "passive"))
      (node (ref "SV136") (pin "7") (pinfunction "7_7") (pintype "passive"))
      (node (ref "SV136") (pin "9") (pinfunction "9_9") (pintype "passive"))
    )
    (net (code "753") (name "Net-(SV136-Pad10)") (class "Default")
      (node (ref "SV136") (pin "10") (pinfunction "10_10") (pintype "passive"))
      (node (ref "SV136") (pin "2") (pinfunction "2_2") (pintype "passive"))
      (node (ref "SV136") (pin "4") (pinfunction "4_4") (pintype "passive"))
      (node (ref "SV136") (pin "6") (pinfunction "6_6") (pintype "passive"))
      (node (ref "SV136") (pin "8") (pinfunction "8_8") (pintype "passive"))
    )
    (net (code "754") (name "Net-(SV137-Pad1)") (class "Default")
      (node (ref "SV137") (pin "1") (pinfunction "1_1") (pintype "passive"))
      (node (ref "SV137") (pin "3") (pinfunction "3_3") (pintype "passive"))
      (node (ref "SV137") (pin "5") (pinfunction "5_5") (pintype "passive"))
      (node (ref "SV137") (pin "7") (pinfunction "7_7") (pintype "passive"))
      (node (ref "SV137") (pin "9") (pinfunction "9_9") (pintype "passive"))
    )
    (net (code "755") (name "Net-(SV137-Pad10)") (class "Default")
      (node (ref "SV137") (pin "10") (pinfunction "10_10") (pintype "passive"))
      (node (ref "SV137") (pin "2") (pinfunction "2_2") (pintype "passive"))
      (node (ref "SV137") (pin "4") (pinfunction "4_4") (pintype "passive"))
      (node (ref "SV137") (pin "6") (pinfunction "6_6") (pintype "passive"))
      (node (ref "SV137") (pin "8") (pinfunction "8_8") (pintype "passive"))
    )
    (net (code "756") (name "Net-(SV138-Pad1)") (class "Default")
      (node (ref "SV138") (pin "1") (pinfunction "1_1") (pintype "passive"))
      (node (ref "SV138") (pin "3") (pinfunction "3_3") (pintype "passive"))
      (node (ref "SV138") (pin "5") (pinfunction "5_5") (pintype "passive"))
      (node (ref "SV138") (pin "7") (pinfunction "7_7") (pintype "passive"))
      (node (ref "SV138") (pin "9") (pinfunction "9_9") (pintype "passive"))
    )
    (net (code "757") (name "Net-(SV138-Pad10)") (class "Default")
      (node (ref "SV138") (pin "10") (pinfunction "10_10") (pintype "passive"))
      (node (ref "SV138") (pin "2") (pinfunction "2_2") (pintype "passive"))
      (node (ref "SV138") (pin "4") (pinfunction "4_4") (pintype "passive"))
      (node (ref "SV138") (pin "6") (pinfunction "6_6") (pintype "passive"))
      (node (ref "SV138") (pin "8") (pinfunction "8_8") (pintype "passive"))
    )
    (net (code "758") (name "Net-(SV139-Pad1)") (class "Default")
      (node (ref "SV139") (pin "1") (pinfunction "1_1") (pintype "passive"))
      (node (ref "SV139") (pin "3") (pinfunction "3_3") (pintype "passive"))
      (node (ref "SV139") (pin "5") (pinfunction "5_5") (pintype "passive"))
      (node (ref "SV139") (pin "7") (pinfunction "7_7") (pintype "passive"))
      (node (ref "SV139") (pin "9") (pinfunction "9_9") (pintype "passive"))
    )
    (net (code "759") (name "Net-(SV139-Pad10)") (class "Default")
      (node (ref "SV139") (pin "10") (pinfunction "10_10") (pintype "passive"))
      (node (ref "SV139") (pin "2") (pinfunction "2_2") (pintype "passive"))
      (node (ref "SV139") (pin "4") (pinfunction "4_4") (pintype "passive"))
      (node (ref "SV139") (pin "6") (pinfunction "6_6") (pintype "passive"))
      (node (ref "SV139") (pin "8") (pinfunction "8_8") (pintype "passive"))
    )
    (net (code "760") (name "Net-(SV140-Pad1)") (class "Default")
      (node (ref "SV140") (pin "1") (pinfunction "1_1") (pintype "passive"))
      (node (ref "SV140") (pin "3") (pinfunction "3_3") (pintype "passive"))
      (node (ref "SV140") (pin "5") (pinfunction "5_5") (pintype "passive"))
      (node (ref "SV140") (pin "7") (pinfunction "7_7") (pintype "passive"))
      (node (ref "SV140") (pin "9") (pinfunction "9_9") (pintype "passive"))
    )
    (net (code "761") (name "Net-(SV140-Pad10)") (class "Default")
      (node (ref "SV140") (pin "10") (pinfunction "10_10") (pintype "passive"))
      (node (ref "SV140") (pin "2") (pinfunction "2_2") (pintype "passive"))
      (node (ref "SV140") (pin "4") (pinfunction "4_4") (pintype "passive"))
      (node (ref "SV140") (pin "6") (pinfunction "6_6") (pintype "passive"))
      (node (ref "SV140") (pin "8") (pinfunction "8_8") (pintype "passive"))
    )
    (net (code "762") (name "Net-(SV141-Pad1)") (class "Default")
      (node (ref "SV141") (pin "1") (pinfunction "1_1") (pintype "passive"))
      (node (ref "SV141") (pin "3") (pinfunction "3_3") (pintype "passive"))
      (node (ref "SV141") (pin "5") (pinfunction "5_5") (pintype "passive"))
      (node (ref "SV141") (pin "7") (pinfunction "7_7") (pintype "passive"))
      (node (ref "SV141") (pin "9") (pinfunction "9_9") (pintype "passive"))
    )
    (net (code "763") (name "Net-(SV141-Pad10)") (class "Default")
      (node (ref "SV141") (pin "10") (pinfunction "10_10") (pintype "passive"))
      (node (ref "SV141") (pin "2") (pinfunction "2_2") (pintype "passive"))
      (node (ref "SV141") (pin "4") (pinfunction "4_4") (pintype "passive"))
      (node (ref "SV141") (pin "6") (pinfunction "6_6") (pintype "passive"))
      (node (ref "SV141") (pin "8") (pinfunction "8_8") (pintype "passive"))
    )
    (net (code "764") (name "Net-(SV142-Pad1)") (class "Default")
      (node (ref "SV142") (pin "1") (pinfunction "1_1") (pintype "passive"))
      (node (ref "SV142") (pin "3") (pinfunction "3_3") (pintype "passive"))
      (node (ref "SV142") (pin "5") (pinfunction "5_5") (pintype "passive"))
      (node (ref "SV142") (pin "7") (pinfunction "7_7") (pintype "passive"))
      (node (ref "SV142") (pin "9") (pinfunction "9_9") (pintype "passive"))
    )
    (net (code "765") (name "Net-(SV142-Pad10)") (class "Default")
      (node (ref "SV142") (pin "10") (pinfunction "10_10") (pintype "passive"))
      (node (ref "SV142") (pin "2") (pinfunction "2_2") (pintype "passive"))
      (node (ref "SV142") (pin "4") (pinfunction "4_4") (pintype "passive"))
      (node (ref "SV142") (pin "6") (pinfunction "6_6") (pintype "passive"))
      (node (ref "SV142") (pin "8") (pinfunction "8_8") (pintype "passive"))
    )
    (net (code "766") (name "Net-(SV143-Pad1)") (class "Default")
      (node (ref "SV143") (pin "1") (pinfunction "1_1") (pintype "passive"))
      (node (ref "SV143") (pin "3") (pinfunction "3_3") (pintype "passive"))
      (node (ref "SV143") (pin "5") (pinfunction "5_5") (pintype "passive"))
      (node (ref "SV143") (pin "7") (pinfunction "7_7") (pintype "passive"))
      (node (ref "SV143") (pin "9") (pinfunction "9_9") (pintype "passive"))
    )
    (net (code "767") (name "Net-(SV143-Pad10)") (class "Default")
      (node (ref "SV143") (pin "10") (pinfunction "10_10") (pintype "passive"))
      (node (ref "SV143") (pin "2") (pinfunction "2_2") (pintype "passive"))
      (node (ref "SV143") (pin "4") (pinfunction "4_4") (pintype "passive"))
      (node (ref "SV143") (pin "6") (pinfunction "6_6") (pintype "passive"))
      (node (ref "SV143") (pin "8") (pinfunction "8_8") (pintype "passive"))
    )
    (net (code "768") (name "Net-(SV144-Pad1)") (class "Default")
      (node (ref "SV144") (pin "1") (pinfunction "1_1") (pintype "passive"))
      (node (ref "SV144") (pin "3") (pinfunction "3_3") (pintype "passive"))
      (node (ref "SV144") (pin "5") (pinfunction "5_5") (pintype "passive"))
      (node (ref "SV144") (pin "7") (pinfunction "7_7") (pintype "passive"))
      (node (ref "SV144") (pin "9") (pinfunction "9_9") (pintype "passive"))
    )
    (net (code "769") (name "Net-(SV144-Pad10)") (class "Default")
      (node (ref "SV144") (pin "10") (pinfunction "10_10") (pintype "passive"))
      (node (ref "SV144") (pin "2") (pinfunction "2_2") (pintype "passive"))
      (node (ref "SV144") (pin "4") (pinfunction "4_4") (pintype "passive"))
      (node (ref "SV144") (pin "6") (pinfunction "6_6") (pintype "passive"))
      (node (ref "SV144") (pin "8") (pinfunction "8_8") (pintype "passive"))
    )
    (net (code "770") (name "Net-(SV145-Pad1)") (class "Default")
      (node (ref "SV145") (pin "1") (pinfunction "1_1") (pintype "passive"))
      (node (ref "SV145") (pin "3") (pinfunction "3_3") (pintype "passive"))
      (node (ref "SV145") (pin "5") (pinfunction "5_5") (pintype "passive"))
      (node (ref "SV145") (pin "7") (pinfunction "7_7") (pintype "passive"))
      (node (ref "SV145") (pin "9") (pinfunction "9_9") (pintype "passive"))
    )
    (net (code "771") (name "Net-(SV145-Pad10)") (class "Default")
      (node (ref "SV145") (pin "10") (pinfunction "10_10") (pintype "passive"))
      (node (ref "SV145") (pin "2") (pinfunction "2_2") (pintype "passive"))
      (node (ref "SV145") (pin "4") (pinfunction "4_4") (pintype "passive"))
      (node (ref "SV145") (pin "6") (pinfunction "6_6") (pintype "passive"))
      (node (ref "SV145") (pin "8") (pinfunction "8_8") (pintype "passive"))
    )
    (net (code "772") (name "Net-(SV146-Pad1)") (class "Default")
      (node (ref "SV146") (pin "1") (pinfunction "1_1") (pintype "passive"))
      (node (ref "SV146") (pin "3") (pinfunction "3_3") (pintype "passive"))
      (node (ref "SV146") (pin "5") (pinfunction "5_5") (pintype "passive"))
      (node (ref "SV146") (pin "7") (pinfunction "7_7") (pintype "passive"))
      (node (ref "SV146") (pin "9") (pinfunction "9_9") (pintype "passive"))
    )
    (net (code "773") (name "Net-(SV146-Pad10)") (class "Default")
      (node (ref "SV146") (pin "10") (pinfunction "10_10") (pintype "passive"))
      (node (ref "SV146") (pin "2") (pinfunction "2_2") (pintype "passive"))
      (node (ref "SV146") (pin "4") (pinfunction "4_4") (pintype "passive"))
      (node (ref "SV146") (pin "6") (pinfunction "6_6") (pintype "passive"))
      (node (ref "SV146") (pin "8") (pinfunction "8_8") (pintype "passive"))
    )
    (net (code "774") (name "Net-(SV147-Pad1)") (class "Default")
      (node (ref "SV147") (pin "1") (pinfunction "1_1") (pintype "passive"))
      (node (ref "SV147") (pin "3") (pinfunction "3_3") (pintype "passive"))
      (node (ref "SV147") (pin "5") (pinfunction "5_5") (pintype "passive"))
      (node (ref "SV147") (pin "7") (pinfunction "7_7") (pintype "passive"))
      (node (ref "SV147") (pin "9") (pinfunction "9_9") (pintype "passive"))
    )
    (net (code "775") (name "Net-(SV147-Pad10)") (class "Default")
      (node (ref "SV147") (pin "10") (pinfunction "10_10") (pintype "passive"))
      (node (ref "SV147") (pin "2") (pinfunction "2_2") (pintype "passive"))
      (node (ref "SV147") (pin "4") (pinfunction "4_4") (pintype "passive"))
      (node (ref "SV147") (pin "6") (pinfunction "6_6") (pintype "passive"))
      (node (ref "SV147") (pin "8") (pinfunction "8_8") (pintype "passive"))
    )
    (net (code "776") (name "Net-(SV148-Pad1)") (class "Default")
      (node (ref "SV148") (pin "1") (pinfunction "1_1") (pintype "passive"))
      (node (ref "SV148") (pin "3") (pinfunction "3_3") (pintype "passive"))
      (node (ref "SV148") (pin "5") (pinfunction "5_5") (pintype "passive"))
      (node (ref "SV148") (pin "7") (pinfunction "7_7") (pintype "passive"))
      (node (ref "SV148") (pin "9") (pinfunction "9_9") (pintype "passive"))
    )
    (net (code "777") (name "Net-(SV148-Pad10)") (class "Default")
      (node (ref "SV148") (pin "10") (pinfunction "10_10") (pintype "passive"))
      (node (ref "SV148") (pin "2") (pinfunction "2_2") (pintype "passive"))
      (node (ref "SV148") (pin "4") (pinfunction "4_4") (pintype "passive"))
      (node (ref "SV148") (pin "6") (pinfunction "6_6") (pintype "passive"))
      (node (ref "SV148") (pin "8") (pinfunction "8_8") (pintype "passive"))
    )
    (net (code "778") (name "Net-(SV149-Pad1)") (class "Default")
      (node (ref "SV149") (pin "1") (pinfunction "1_1") (pintype "passive"))
      (node (ref "SV149") (pin "3") (pinfunction "3_3") (pintype "passive"))
      (node (ref "SV149") (pin "5") (pinfunction "5_5") (pintype "passive"))
      (node (ref "SV149") (pin "7") (pinfunction "7_7") (pintype "passive"))
      (node (ref "SV149") (pin "9") (pinfunction "9_9") (pintype "passive"))
    )
    (net (code "779") (name "Net-(SV149-Pad10)") (class "Default")
      (node (ref "SV149") (pin "10") (pinfunction "10_10") (pintype "passive"))
      (node (ref "SV149") (pin "2") (pinfunction "2_2") (pintype "passive"))
      (node (ref "SV149") (pin "4") (pinfunction "4_4") (pintype "passive"))
      (node (ref "SV149") (pin "6") (pinfunction "6_6") (pintype "passive"))
      (node (ref "SV149") (pin "8") (pinfunction "8_8") (pintype "passive"))
    )
    (net (code "780") (name "Net-(SV150-Pad1)") (class "Default")
      (node (ref "SV150") (pin "1") (pinfunction "1_1") (pintype "passive"))
      (node (ref "SV150") (pin "3") (pinfunction "3_3") (pintype "passive"))
      (node (ref "SV150") (pin "5") (pinfunction "5_5") (pintype "passive"))
      (node (ref "SV150") (pin "7") (pinfunction "7_7") (pintype "passive"))
      (node (ref "SV150") (pin "9") (pinfunction "9_9") (pintype "passive"))
    )
    (net (code "781") (name "Net-(SV150-Pad10)") (class "Default")
      (node (ref "SV150") (pin "10") (pinfunction "10_10") (pintype "passive"))
      (node (ref "SV150") (pin "2") (pinfunction "2_2") (pintype "passive"))
      (node (ref "SV150") (pin "4") (pinfunction "4_4") (pintype "passive"))
      (node (ref "SV150") (pin "6") (pinfunction "6_6") (pintype "passive"))
      (node (ref "SV150") (pin "8") (pinfunction "8_8") (pintype "passive"))
    )
    (net (code "782") (name "Net-(SV151-Pad1)") (class "Default")
      (node (ref "SV151") (pin "1") (pinfunction "1_1") (pintype "passive"))
      (node (ref "SV151") (pin "3") (pinfunction "3_3") (pintype "passive"))
      (node (ref "SV151") (pin "5") (pinfunction "5_5") (pintype "passive"))
      (node (ref "SV151") (pin "7") (pinfunction "7_7") (pintype "passive"))
      (node (ref "SV151") (pin "9") (pinfunction "9_9") (pintype "passive"))
    )
    (net (code "783") (name "Net-(SV151-Pad10)") (class "Default")
      (node (ref "SV151") (pin "10") (pinfunction "10_10") (pintype "passive"))
      (node (ref "SV151") (pin "2") (pinfunction "2_2") (pintype "passive"))
      (node (ref "SV151") (pin "4") (pinfunction "4_4") (pintype "passive"))
      (node (ref "SV151") (pin "6") (pinfunction "6_6") (pintype "passive"))
      (node (ref "SV151") (pin "8") (pinfunction "8_8") (pintype "passive"))
    )
    (net (code "784") (name "Net-(SV152-Pad1)") (class "Default")
      (node (ref "SV152") (pin "1") (pinfunction "1_1") (pintype "passive"))
      (node (ref "SV152") (pin "3") (pinfunction "3_3") (pintype "passive"))
      (node (ref "SV152") (pin "5") (pinfunction "5_5") (pintype "passive"))
      (node (ref "SV152") (pin "7") (pinfunction "7_7") (pintype "passive"))
      (node (ref "SV152") (pin "9") (pinfunction "9_9") (pintype "passive"))
    )
    (net (code "785") (name "Net-(SV152-Pad10)") (class "Default")
      (node (ref "SV152") (pin "10") (pinfunction "10_10") (pintype "passive"))
      (node (ref "SV152") (pin "2") (pinfunction "2_2") (pintype "passive"))
      (node (ref "SV152") (pin "4") (pinfunction "4_4") (pintype "passive"))
      (node (ref "SV152") (pin "6") (pinfunction "6_6") (pintype "passive"))
      (node (ref "SV152") (pin "8") (pinfunction "8_8") (pintype "passive"))
    )
    (net (code "786") (name "Net-(SV153-Pad1)") (class "Default")
      (node (ref "SV153") (pin "1") (pinfunction "1_1") (pintype "passive"))
      (node (ref "SV153") (pin "3") (pinfunction "3_3") (pintype "passive"))
      (node (ref "SV153") (pin "5") (pinfunction "5_5") (pintype "passive"))
      (node (ref "SV153") (pin "7") (pinfunction "7_7") (pintype "passive"))
      (node (ref "SV153") (pin "9") (pinfunction "9_9") (pintype "passive"))
    )
    (net (code "787") (name "Net-(SV153-Pad10)") (class "Default")
      (node (ref "SV153") (pin "10") (pinfunction "10_10") (pintype "passive"))
      (node (ref "SV153") (pin "2") (pinfunction "2_2") (pintype "passive"))
      (node (ref "SV153") (pin "4") (pinfunction "4_4") (pintype "passive"))
      (node (ref "SV153") (pin "6") (pinfunction "6_6") (pintype "passive"))
      (node (ref "SV153") (pin "8") (pinfunction "8_8") (pintype "passive"))
    )
    (net (code "788") (name "Net-(SV154-Pad1)") (class "Default")
      (node (ref "SV154") (pin "1") (pinfunction "1_1") (pintype "passive"))
      (node (ref "SV154") (pin "3") (pinfunction "3_3") (pintype "passive"))
      (node (ref "SV154") (pin "5") (pinfunction "5_5") (pintype "passive"))
      (node (ref "SV154") (pin "7") (pinfunction "7_7") (pintype "passive"))
      (node (ref "SV154") (pin "9") (pinfunction "9_9") (pintype "passive"))
    )
    (net (code "789") (name "Net-(SV154-Pad10)") (class "Default")
      (node (ref "SV154") (pin "10") (pinfunction "10_10") (pintype "passive"))
      (node (ref "SV154") (pin "2") (pinfunction "2_2") (pintype "passive"))
      (node (ref "SV154") (pin "4") (pinfunction "4_4") (pintype "passive"))
      (node (ref "SV154") (pin "6") (pinfunction "6_6") (pintype "passive"))
      (node (ref "SV154") (pin "8") (pinfunction "8_8") (pintype "passive"))
    )
    (net (code "790") (name "Net-(SV155-Pad1)") (class "Default")
      (node (ref "SV155") (pin "1") (pinfunction "1_1") (pintype "passive"))
      (node (ref "SV155") (pin "3") (pinfunction "3_3") (pintype "passive"))
      (node (ref "SV155") (pin "5") (pinfunction "5_5") (pintype "passive"))
      (node (ref "SV155") (pin "7") (pinfunction "7_7") (pintype "passive"))
      (node (ref "SV155") (pin "9") (pinfunction "9_9") (pintype "passive"))
    )
    (net (code "791") (name "Net-(SV155-Pad10)") (class "Default")
      (node (ref "SV155") (pin "10") (pinfunction "10_10") (pintype "passive"))
      (node (ref "SV155") (pin "2") (pinfunction "2_2") (pintype "passive"))
      (node (ref "SV155") (pin "4") (pinfunction "4_4") (pintype "passive"))
      (node (ref "SV155") (pin "6") (pinfunction "6_6") (pintype "passive"))
      (node (ref "SV155") (pin "8") (pinfunction "8_8") (pintype "passive"))
    )
    (net (code "792") (name "Net-(SV156-Pad1)") (class "Default")
      (node (ref "SV156") (pin "1") (pinfunction "1_1") (pintype "passive"))
      (node (ref "SV156") (pin "3") (pinfunction "3_3") (pintype "passive"))
      (node (ref "SV156") (pin "5") (pinfunction "5_5") (pintype "passive"))
      (node (ref "SV156") (pin "7") (pinfunction "7_7") (pintype "passive"))
      (node (ref "SV156") (pin "9") (pinfunction "9_9") (pintype "passive"))
    )
    (net (code "793") (name "Net-(SV156-Pad10)") (class "Default")
      (node (ref "SV156") (pin "10") (pinfunction "10_10") (pintype "passive"))
      (node (ref "SV156") (pin "2") (pinfunction "2_2") (pintype "passive"))
      (node (ref "SV156") (pin "4") (pinfunction "4_4") (pintype "passive"))
      (node (ref "SV156") (pin "6") (pinfunction "6_6") (pintype "passive"))
      (node (ref "SV156") (pin "8") (pinfunction "8_8") (pintype "passive"))
    )
    (net (code "794") (name "Net-(SV157-Pad1)") (class "Default")
      (node (ref "SV157") (pin "1") (pinfunction "1_1") (pintype "passive"))
      (node (ref "SV157") (pin "3") (pinfunction "3_3") (pintype "passive"))
      (node (ref "SV157") (pin "5") (pinfunction "5_5") (pintype "passive"))
      (node (ref "SV157") (pin "7") (pinfunction "7_7") (pintype "passive"))
      (node (ref "SV157") (pin "9") (pinfunction "9_9") (pintype "passive"))
    )
    (net (code "795") (name "Net-(SV157-Pad10)") (class "Default")
      (node (ref "SV157") (pin "10") (pinfunction "10_10") (pintype "passive"))
      (node (ref "SV157") (pin "2") (pinfunction "2_2") (pintype "passive"))
      (node (ref "SV157") (pin "4") (pinfunction "4_4") (pintype "passive"))
      (node (ref "SV157") (pin "6") (pinfunction "6_6") (pintype "passive"))
      (node (ref "SV157") (pin "8") (pinfunction "8_8") (pintype "passive"))
    )
    (net (code "796") (name "Net-(SV158-Pad1)") (class "Default")
      (node (ref "SV158") (pin "1") (pinfunction "1_1") (pintype "passive"))
      (node (ref "SV158") (pin "3") (pinfunction "3_3") (pintype "passive"))
      (node (ref "SV158") (pin "5") (pinfunction "5_5") (pintype "passive"))
      (node (ref "SV158") (pin "7") (pinfunction "7_7") (pintype "passive"))
      (node (ref "SV158") (pin "9") (pinfunction "9_9") (pintype "passive"))
    )
    (net (code "797") (name "Net-(SV158-Pad10)") (class "Default")
      (node (ref "SV158") (pin "10") (pinfunction "10_10") (pintype "passive"))
      (node (ref "SV158") (pin "2") (pinfunction "2_2") (pintype "passive"))
      (node (ref "SV158") (pin "4") (pinfunction "4_4") (pintype "passive"))
      (node (ref "SV158") (pin "6") (pinfunction "6_6") (pintype "passive"))
      (node (ref "SV158") (pin "8") (pinfunction "8_8") (pintype "passive"))
    )
    (net (code "798") (name "Net-(SV159-Pad1)") (class "Default")
      (node (ref "SV159") (pin "1") (pinfunction "1_1") (pintype "passive"))
      (node (ref "SV159") (pin "3") (pinfunction "3_3") (pintype "passive"))
      (node (ref "SV159") (pin "5") (pinfunction "5_5") (pintype "passive"))
      (node (ref "SV159") (pin "7") (pinfunction "7_7") (pintype "passive"))
      (node (ref "SV159") (pin "9") (pinfunction "9_9") (pintype "passive"))
    )
    (net (code "799") (name "Net-(SV159-Pad10)") (class "Default")
      (node (ref "SV159") (pin "10") (pinfunction "10_10") (pintype "passive"))
      (node (ref "SV159") (pin "2") (pinfunction "2_2") (pintype "passive"))
      (node (ref "SV159") (pin "4") (pinfunction "4_4") (pintype "passive"))
      (node (ref "SV159") (pin "6") (pinfunction "6_6") (pintype "passive"))
      (node (ref "SV159") (pin "8") (pinfunction "8_8") (pintype "passive"))
    )
    (net (code "800") (name "Net-(SV160-Pad1)") (class "Default")
      (node (ref "SV160") (pin "1") (pinfunction "1_1") (pintype "passive"))
      (node (ref "SV160") (pin "3") (pinfunction "3_3") (pintype "passive"))
      (node (ref "SV160") (pin "5") (pinfunction "5_5") (pintype "passive"))
      (node (ref "SV160") (pin "7") (pinfunction "7_7") (pintype "passive"))
      (node (ref "SV160") (pin "9") (pinfunction "9_9") (pintype "passive"))
    )
    (net (code "801") (name "Net-(SV160-Pad10)") (class "Default")
      (node (ref "SV160") (pin "10") (pinfunction "10_10") (pintype "passive"))
      (node (ref "SV160") (pin "2") (pinfunction "2_2") (pintype "passive"))
      (node (ref "SV160") (pin "4") (pinfunction "4_4") (pintype "passive"))
      (node (ref "SV160") (pin "6") (pinfunction "6_6") (pintype "passive"))
      (node (ref "SV160") (pin "8") (pinfunction "8_8") (pintype "passive"))
    )
    (net (code "802") (name "Net-(SV161-Pad1)") (class "Default")
      (node (ref "SV161") (pin "1") (pinfunction "1_1") (pintype "passive"))
      (node (ref "SV161") (pin "3") (pinfunction "3_3") (pintype "passive"))
      (node (ref "SV161") (pin "5") (pinfunction "5_5") (pintype "passive"))
      (node (ref "SV161") (pin "7") (pinfunction "7_7") (pintype "passive"))
      (node (ref "SV161") (pin "9") (pinfunction "9_9") (pintype "passive"))
    )
    (net (code "803") (name "Net-(SV161-Pad10)") (class "Default")
      (node (ref "SV161") (pin "10") (pinfunction "10_10") (pintype "passive"))
      (node (ref "SV161") (pin "2") (pinfunction "2_2") (pintype "passive"))
      (node (ref "SV161") (pin "4") (pinfunction "4_4") (pintype "passive"))
      (node (ref "SV161") (pin "6") (pinfunction "6_6") (pintype "passive"))
      (node (ref "SV161") (pin "8") (pinfunction "8_8") (pintype "passive"))
    )
    (net (code "804") (name "Net-(SV162-Pad1)") (class "Default")
      (node (ref "SV162") (pin "1") (pinfunction "1_1") (pintype "passive"))
      (node (ref "SV162") (pin "3") (pinfunction "3_3") (pintype "passive"))
      (node (ref "SV162") (pin "5") (pinfunction "5_5") (pintype "passive"))
      (node (ref "SV162") (pin "7") (pinfunction "7_7") (pintype "passive"))
      (node (ref "SV162") (pin "9") (pinfunction "9_9") (pintype "passive"))
    )
    (net (code "805") (name "Net-(SV162-Pad10)") (class "Default")
      (node (ref "SV162") (pin "10") (pinfunction "10_10") (pintype "passive"))
      (node (ref "SV162") (pin "2") (pinfunction "2_2") (pintype "passive"))
      (node (ref "SV162") (pin "4") (pinfunction "4_4") (pintype "passive"))
      (node (ref "SV162") (pin "6") (pinfunction "6_6") (pintype "passive"))
      (node (ref "SV162") (pin "8") (pinfunction "8_8") (pintype "passive"))
    )
    (net (code "806") (name "Net-(SV163-Pad1)") (class "Default")
      (node (ref "SV163") (pin "1") (pinfunction "1_1") (pintype "passive"))
      (node (ref "SV163") (pin "3") (pinfunction "3_3") (pintype "passive"))
      (node (ref "SV163") (pin "5") (pinfunction "5_5") (pintype "passive"))
      (node (ref "SV163") (pin "7") (pinfunction "7_7") (pintype "passive"))
      (node (ref "SV163") (pin "9") (pinfunction "9_9") (pintype "passive"))
    )
    (net (code "807") (name "Net-(SV163-Pad10)") (class "Default")
      (node (ref "SV163") (pin "10") (pinfunction "10_10") (pintype "passive"))
      (node (ref "SV163") (pin "2") (pinfunction "2_2") (pintype "passive"))
      (node (ref "SV163") (pin "4") (pinfunction "4_4") (pintype "passive"))
      (node (ref "SV163") (pin "6") (pinfunction "6_6") (pintype "passive"))
      (node (ref "SV163") (pin "8") (pinfunction "8_8") (pintype "passive"))
    )
    (net (code "808") (name "Net-(SV164-Pad1)") (class "Default")
      (node (ref "SV164") (pin "1") (pinfunction "1_1") (pintype "passive"))
      (node (ref "SV164") (pin "3") (pinfunction "3_3") (pintype "passive"))
      (node (ref "SV164") (pin "5") (pinfunction "5_5") (pintype "passive"))
      (node (ref "SV164") (pin "7") (pinfunction "7_7") (pintype "passive"))
      (node (ref "SV164") (pin "9") (pinfunction "9_9") (pintype "passive"))
    )
    (net (code "809") (name "Net-(SV164-Pad10)") (class "Default")
      (node (ref "SV164") (pin "10") (pinfunction "10_10") (pintype "passive"))
      (node (ref "SV164") (pin "2") (pinfunction "2_2") (pintype "passive"))
      (node (ref "SV164") (pin "4") (pinfunction "4_4") (pintype "passive"))
      (node (ref "SV164") (pin "6") (pinfunction "6_6") (pintype "passive"))
      (node (ref "SV164") (pin "8") (pinfunction "8_8") (pintype "passive"))
    )
    (net (code "810") (name "Net-(SV165-Pad1)") (class "Default")
      (node (ref "SV165") (pin "1") (pinfunction "1_1") (pintype "passive"))
      (node (ref "SV165") (pin "3") (pinfunction "3_3") (pintype "passive"))
      (node (ref "SV165") (pin "5") (pinfunction "5_5") (pintype "passive"))
      (node (ref "SV165") (pin "7") (pinfunction "7_7") (pintype "passive"))
      (node (ref "SV165") (pin "9") (pinfunction "9_9") (pintype "passive"))
    )
    (net (code "811") (name "Net-(SV165-Pad10)") (class "Default")
      (node (ref "SV165") (pin "10") (pinfunction "10_10") (pintype "passive"))
      (node (ref "SV165") (pin "2") (pinfunction "2_2") (pintype "passive"))
      (node (ref "SV165") (pin "4") (pinfunction "4_4") (pintype "passive"))
      (node (ref "SV165") (pin "6") (pinfunction "6_6") (pintype "passive"))
      (node (ref "SV165") (pin "8") (pinfunction "8_8") (pintype "passive"))
    )
    (net (code "812") (name "Net-(SV166-Pad1)") (class "Default")
      (node (ref "SV166") (pin "1") (pinfunction "1_1") (pintype "passive"))
      (node (ref "SV166") (pin "3") (pinfunction "3_3") (pintype "passive"))
      (node (ref "SV166") (pin "5") (pinfunction "5_5") (pintype "passive"))
      (node (ref "SV166") (pin "7") (pinfunction "7_7") (pintype "passive"))
      (node (ref "SV166") (pin "9") (pinfunction "9_9") (pintype "passive"))
    )
    (net (code "813") (name "Net-(SV166-Pad10)") (class "Default")
      (node (ref "SV166") (pin "10") (pinfunction "10_10") (pintype "passive"))
      (node (ref "SV166") (pin "2") (pinfunction "2_2") (pintype "passive"))
      (node (ref "SV166") (pin "4") (pinfunction "4_4") (pintype "passive"))
      (node (ref "SV166") (pin "6") (pinfunction "6_6") (pintype "passive"))
      (node (ref "SV166") (pin "8") (pinfunction "8_8") (pintype "passive"))
    )
    (net (code "814") (name "Net-(SV167-Pad1)") (class "Default")
      (node (ref "SV167") (pin "1") (pinfunction "1_1") (pintype "passive"))
      (node (ref "SV167") (pin "3") (pinfunction "3_3") (pintype "passive"))
      (node (ref "SV167") (pin "5") (pinfunction "5_5") (pintype "passive"))
      (node (ref "SV167") (pin "7") (pinfunction "7_7") (pintype "passive"))
      (node (ref "SV167") (pin "9") (pinfunction "9_9") (pintype "passive"))
    )
    (net (code "815") (name "Net-(SV167-Pad10)") (class "Default")
      (node (ref "SV167") (pin "10") (pinfunction "10_10") (pintype "passive"))
      (node (ref "SV167") (pin "2") (pinfunction "2_2") (pintype "passive"))
      (node (ref "SV167") (pin "4") (pinfunction "4_4") (pintype "passive"))
      (node (ref "SV167") (pin "6") (pinfunction "6_6") (pintype "passive"))
      (node (ref "SV167") (pin "8") (pinfunction "8_8") (pintype "passive"))
    )
    (net (code "816") (name "Net-(SV168-Pad1)") (class "Default")
      (node (ref "SV168") (pin "1") (pinfunction "1_1") (pintype "passive"))
      (node (ref "SV168") (pin "3") (pinfunction "3_3") (pintype "passive"))
      (node (ref "SV168") (pin "5") (pinfunction "5_5") (pintype "passive"))
      (node (ref "SV168") (pin "7") (pinfunction "7_7") (pintype "passive"))
      (node (ref "SV168") (pin "9") (pinfunction "9_9") (pintype "passive"))
    )
    (net (code "817") (name "Net-(SV168-Pad10)") (class "Default")
      (node (ref "SV168") (pin "10") (pinfunction "10_10") (pintype "passive"))
      (node (ref "SV168") (pin "2") (pinfunction "2_2") (pintype "passive"))
      (node (ref "SV168") (pin "4") (pinfunction "4_4") (pintype "passive"))
      (node (ref "SV168") (pin "6") (pinfunction "6_6") (pintype "passive"))
      (node (ref "SV168") (pin "8") (pinfunction "8_8") (pintype "passive"))
    )
    (net (code "818") (name "Net-(SV169-Pad1)") (class "Default")
      (node (ref "SV169") (pin "1") (pinfunction "1_1") (pintype "passive"))
      (node (ref "SV169") (pin "3") (pinfunction "3_3") (pintype "passive"))
      (node (ref "SV169") (pin "5") (pinfunction "5_5") (pintype "passive"))
      (node (ref "SV169") (pin "7") (pinfunction "7_7") (pintype "passive"))
      (node (ref "SV169") (pin "9") (pinfunction "9_9") (pintype "passive"))
    )
    (net (code "819") (name "Net-(SV169-Pad10)") (class "Default")
      (node (ref "SV169") (pin "10") (pinfunction "10_10") (pintype "passive"))
      (node (ref "SV169") (pin "2") (pinfunction "2_2") (pintype "passive"))
      (node (ref "SV169") (pin "4") (pinfunction "4_4") (pintype "passive"))
      (node (ref "SV169") (pin "6") (pinfunction "6_6") (pintype "passive"))
      (node (ref "SV169") (pin "8") (pinfunction "8_8") (pintype "passive"))
    )
    (net (code "820") (name "Net-(SV170-Pad1)") (class "Default")
      (node (ref "SV170") (pin "1") (pinfunction "1_1") (pintype "passive"))
      (node (ref "SV170") (pin "3") (pinfunction "3_3") (pintype "passive"))
      (node (ref "SV170") (pin "5") (pinfunction "5_5") (pintype "passive"))
      (node (ref "SV170") (pin "7") (pinfunction "7_7") (pintype "passive"))
      (node (ref "SV170") (pin "9") (pinfunction "9_9") (pintype "passive"))
    )
    (net (code "821") (name "Net-(SV170-Pad10)") (class "Default")
      (node (ref "SV170") (pin "10") (pinfunction "10_10") (pintype "passive"))
      (node (ref "SV170") (pin "2") (pinfunction "2_2") (pintype "passive"))
      (node (ref "SV170") (pin "4") (pinfunction "4_4") (pintype "passive"))
      (node (ref "SV170") (pin "6") (pinfunction "6_6") (pintype "passive"))
      (node (ref "SV170") (pin "8") (pinfunction "8_8") (pintype "passive"))
    )
    (net (code "822") (name "Net-(SV171-Pad1)") (class "Default")
      (node (ref "SV171") (pin "1") (pinfunction "1_1") (pintype "passive"))
      (node (ref "SV171") (pin "3") (pinfunction "3_3") (pintype "passive"))
      (node (ref "SV171") (pin "5") (pinfunction "5_5") (pintype "passive"))
      (node (ref "SV171") (pin "7") (pinfunction "7_7") (pintype "passive"))
      (node (ref "SV171") (pin "9") (pinfunction "9_9") (pintype "passive"))
    )
    (net (code "823") (name "Net-(SV171-Pad10)") (class "Default")
      (node (ref "SV171") (pin "10") (pinfunction "10_10") (pintype "passive"))
      (node (ref "SV171") (pin "2") (pinfunction "2_2") (pintype "passive"))
      (node (ref "SV171") (pin "4") (pinfunction "4_4") (pintype "passive"))
      (node (ref "SV171") (pin "6") (pinfunction "6_6") (pintype "passive"))
      (node (ref "SV171") (pin "8") (pinfunction "8_8") (pintype "passive"))
    )
    (net (code "824") (name "Net-(SV172-Pad1)") (class "Default")
      (node (ref "SV172") (pin "1") (pinfunction "1_1") (pintype "passive"))
      (node (ref "SV172") (pin "3") (pinfunction "3_3") (pintype "passive"))
      (node (ref "SV172") (pin "5") (pinfunction "5_5") (pintype "passive"))
      (node (ref "SV172") (pin "7") (pinfunction "7_7") (pintype "passive"))
      (node (ref "SV172") (pin "9") (pinfunction "9_9") (pintype "passive"))
    )
    (net (code "825") (name "Net-(SV172-Pad10)") (class "Default")
      (node (ref "SV172") (pin "10") (pinfunction "10_10") (pintype "passive"))
      (node (ref "SV172") (pin "2") (pinfunction "2_2") (pintype "passive"))
      (node (ref "SV172") (pin "4") (pinfunction "4_4") (pintype "passive"))
      (node (ref "SV172") (pin "6") (pinfunction "6_6") (pintype "passive"))
      (node (ref "SV172") (pin "8") (pinfunction "8_8") (pintype "passive"))
    )
    (net (code "826") (name "Net-(SV173-Pad1)") (class "Default")
      (node (ref "SV173") (pin "1") (pinfunction "1_1") (pintype "passive"))
      (node (ref "SV173") (pin "3") (pinfunction "3_3") (pintype "passive"))
      (node (ref "SV173") (pin "5") (pinfunction "5_5") (pintype "passive"))
      (node (ref "SV173") (pin "7") (pinfunction "7_7") (pintype "passive"))
      (node (ref "SV173") (pin "9") (pinfunction "9_9") (pintype "passive"))
    )
    (net (code "827") (name "Net-(SV173-Pad10)") (class "Default")
      (node (ref "SV173") (pin "10") (pinfunction "10_10") (pintype "passive"))
      (node (ref "SV173") (pin "2") (pinfunction "2_2") (pintype "passive"))
      (node (ref "SV173") (pin "4") (pinfunction "4_4") (pintype "passive"))
      (node (ref "SV173") (pin "6") (pinfunction "6_6") (pintype "passive"))
      (node (ref "SV173") (pin "8") (pinfunction "8_8") (pintype "passive"))
    )
    (net (code "828") (name "Net-(SV174-Pad1)") (class "Default")
      (node (ref "SV174") (pin "1") (pinfunction "1_1") (pintype "passive"))
      (node (ref "SV174") (pin "3") (pinfunction "3_3") (pintype "passive"))
      (node (ref "SV174") (pin "5") (pinfunction "5_5") (pintype "passive"))
      (node (ref "SV174") (pin "7") (pinfunction "7_7") (pintype "passive"))
      (node (ref "SV174") (pin "9") (pinfunction "9_9") (pintype "passive"))
    )
    (net (code "829") (name "Net-(SV174-Pad10)") (class "Default")
      (node (ref "SV174") (pin "10") (pinfunction "10_10") (pintype "passive"))
      (node (ref "SV174") (pin "2") (pinfunction "2_2") (pintype "passive"))
      (node (ref "SV174") (pin "4") (pinfunction "4_4") (pintype "passive"))
      (node (ref "SV174") (pin "6") (pinfunction "6_6") (pintype "passive"))
      (node (ref "SV174") (pin "8") (pinfunction "8_8") (pintype "passive"))
    )
    (net (code "830") (name "Net-(U$2A-1)") (class "Default")
      (node (ref "D9") (pin "1") (pinfunction "1_1") (pintype "passive"))
      (node (ref "U$2") (pin "AA1") (pinfunction "1_AA1") (pintype "bidirectional"))
    )
    (net (code "831") (name "Net-(U$2AK-1)") (class "Default")
      (node (ref "D7") (pin "1") (pinfunction "1_1") (pintype "passive"))
      (node (ref "U$2") (pin "BA1") (pinfunction "1_BA1") (pintype "bidirectional"))
    )
    (net (code "832") (name "Net-(U$2AM-1)") (class "Default")
      (node (ref "D7") (pin "2") (pinfunction "2_2") (pintype "passive"))
      (node (ref "U$2") (pin "BB1") (pinfunction "1_BB1") (pintype "bidirectional"))
    )
    (net (code "833") (name "Net-(U$2BN-1)") (class "Default")
      (node (ref "D8") (pin "15") (pinfunction "15_15") (pintype "passive"))
      (node (ref "U$2") (pin "BS2") (pinfunction "1_BS2") (pintype "bidirectional"))
    )
    (net (code "834") (name "Net-(U$2BU-1)") (class "Default")
      (node (ref "D11") (pin "1") (pinfunction "1_1") (pintype "passive"))
      (node (ref "U$2") (pin "CA1") (pinfunction "1_CA1") (pintype "bidirectional"))
    )
    (net (code "835") (name "Net-(U$2BW-1)") (class "Default")
      (node (ref "D11") (pin "2") (pinfunction "2_2") (pintype "passive"))
      (node (ref "U$2") (pin "CB1") (pinfunction "1_CB1") (pintype "bidirectional"))
    )
    (net (code "836") (name "Net-(U$2C-1)") (class "Default")
      (node (ref "D9") (pin "2") (pinfunction "2_2") (pintype "passive"))
      (node (ref "U$2") (pin "AB1") (pinfunction "1_AB1") (pintype "bidirectional"))
    )
    (net (code "837") (name "Net-(U$2DE-1)") (class "Default")
      (node (ref "D13") (pin "1") (pinfunction "1_1") (pintype "passive"))
      (node (ref "U$2") (pin "DA1") (pinfunction "1_DA1") (pintype "bidirectional"))
    )
    (net (code "838") (name "Net-(U$2DG-1)") (class "Default")
      (node (ref "D13") (pin "2") (pinfunction "2_2") (pintype "passive"))
      (node (ref "U$2") (pin "DB1") (pinfunction "1_DB1") (pintype "bidirectional"))
    )
    (net (code "839") (name "POWER_OK") (class "Default")
      (node (ref "D8") (pin "18") (pinfunction "18_18") (pintype "passive"))
      (node (ref "R6") (pin "1") (pinfunction "1_1") (pintype "passive"))
      (node (ref "U$2") (pin "BV2") (pinfunction "1_BV2") (pintype "bidirectional"))
    )
    (net (code "840") (name "PULSE_LA") (class "Default")
      (node (ref "D14") (pin "14") (pinfunction "14_14") (pintype "passive"))
      (node (ref "U$2") (pin "DR2") (pinfunction "1_DR2") (pintype "bidirectional"))
    )
    (net (code "841") (name "RETURN") (class "Default")
      (node (ref "D10") (pin "14") (pinfunction "14_14") (pintype "passive"))
      (node (ref "U$2") (pin "AR2") (pinfunction "1_AR2") (pintype "bidirectional"))
    )
    (net (code "842") (name "SOURCE") (class "Default")
      (node (ref "D10") (pin "10") (pinfunction "10_10") (pintype "passive"))
      (node (ref "IC37") (pin "3") (pinfunction "C_3") (pintype "input"))
      (node (ref "IC38") (pin "13") (pinfunction "B_13") (pintype "input"))
      (node (ref "IC8") (pin "6") (pinfunction "A5_6") (pintype "input"))
      (node (ref "U$2") (pin "AL2") (pinfunction "1_AL2") (pintype "bidirectional"))
    )
    (net (code "843") (name "STROBE") (class "Default")
      (node (ref "D10") (pin "11") (pinfunction "11_11") (pintype "passive"))
      (node (ref "U$2") (pin "AM2") (pinfunction "1_AM2") (pintype "bidirectional"))
    )
    (net (code "844") (name "SWITCH") (class "Default")
      (node (ref "D14") (pin "18") (pinfunction "18_18") (pintype "passive"))
      (node (ref "U$2") (pin "DV2") (pinfunction "1_DV2") (pintype "bidirectional"))
    )
    (net (code "845") (name "TP1") (class "Default")
      (node (ref "D12") (pin "4") (pinfunction "4_4") (pintype "passive"))
      (node (ref "IC42") (pin "11") (pinfunction "CLK_11") (pintype "input"))
      (node (ref "U$2") (pin "CD2") (pinfunction "1_CD2") (pintype "bidirectional"))
    )
    (net (code "846") (name "TP2") (class "Default")
      (node (ref "D12") (pin "5") (pinfunction "5_5") (pintype "passive"))
      (node (ref "U$2") (pin "CE2") (pinfunction "1_CE2") (pintype "bidirectional"))
    )
    (net (code "847") (name "TP3") (class "Default")
      (node (ref "D12") (pin "7") (pinfunction "7_7") (pintype "passive"))
      (node (ref "IC43") (pin "2") (pinfunction "I1_2") (pintype "input"))
      (node (ref "U$2") (pin "CH2") (pinfunction "1_CH2") (pintype "bidirectional"))
    )
    (net (code "848") (name "TP4") (class "Default")
      (node (ref "D12") (pin "8") (pinfunction "8_8") (pintype "passive"))
      (node (ref "U$2") (pin "CJ2") (pinfunction "1_CJ2") (pintype "bidirectional"))
    )
    (net (code "849") (name "V+") (class "Default")
      (node (ref "C1") (pin "1") (pinfunction "1_1") (pintype "passive"))
      (node (ref "C3") (pin "1") (pinfunction "1_1") (pintype "passive"))
      (node (ref "D1") (pin "C") (pinfunction "C_C") (pintype "passive"))
      (node (ref "D2") (pin "C") (pinfunction "C_C") (pintype "passive"))
      (node (ref "IC3") (pin "28") (pinfunction "VCC_28") (pintype "power_in"))
      (node (ref "IC4") (pin "28") (pinfunction "VCC_28") (pintype "power_in"))
      (node (ref "R7") (pin "2") (pinfunction "2_2") (pintype "passive"))
    )
    (net (code "850") (name "VCC") (class "Default")
      (node (ref "C10") (pin "+") (pinfunction "+_+") (pintype "passive"))
      (node (ref "C4") (pin "1") (pinfunction "1_1") (pintype "passive"))
      (node (ref "C5") (pin "1") (pinfunction "1_1") (pintype "passive"))
      (node (ref "C6") (pin "1") (pinfunction "1_1") (pintype "passive"))
      (node (ref "C7") (pin "1") (pinfunction "1_1") (pintype "passive"))
      (node (ref "C8") (pin "1") (pinfunction "1_1") (pintype "passive"))
      (node (ref "C9") (pin "1") (pinfunction "1_1") (pintype "passive"))
      (node (ref "D10") (pin "1") (pinfunction "1_1") (pintype "passive"))
      (node (ref "D12") (pin "1") (pinfunction "1_1") (pintype "passive"))
      (node (ref "D2") (pin "A") (pinfunction "A_A") (pintype "passive"))
      (node (ref "D8") (pin "1") (pinfunction "1_1") (pintype "passive"))
      (node (ref "IC37") (pin "6") (pinfunction "G1_6") (pintype "input"))
      (node (ref "IC40") (pin "6") (pinfunction "G1_6") (pintype "input"))
      (node (ref "IC42") (pin "10") (pinfunction "PRE_10") (pintype "input"))
      (node (ref "IC42") (pin "13") (pinfunction "CLR_13") (pintype "input"))
      (node (ref "IC42") (pin "2") (pinfunction "D_2") (pintype "input"))
      (node (ref "IC42") (pin "4") (pinfunction "PRE_4") (pintype "input"))
      (node (ref "IC7") (pin "1") (pinfunction "I0_1") (pintype "input"))
      (node (ref "IC7") (pin "12") (pinfunction "I2_12") (pintype "input"))
      (node (ref "IC7") (pin "13") (pinfunction "I3_13") (pintype "input"))
      (node (ref "R5") (pin "10") (pinfunction "2_10") (pintype "passive"))
      (node (ref "R5") (pin "11") (pinfunction "2_11") (pintype "passive"))
      (node (ref "R5") (pin "12") (pinfunction "2_12") (pintype "passive"))
      (node (ref "R5") (pin "13") (pinfunction "2_13") (pintype "passive"))
      (node (ref "R5") (pin "14") (pinfunction "2_14") (pintype "passive"))
      (node (ref "R5") (pin "15") (pinfunction "2_15") (pintype "passive"))
      (node (ref "R5") (pin "16") (pinfunction "2_16") (pintype "passive"))
      (node (ref "R5") (pin "9") (pinfunction "2_9") (pintype "passive"))
      (node (ref "SV11") (pin "1") (pinfunction "1_1") (pintype "passive"))
      (node (ref "SV11") (pin "10") (pinfunction "10_10") (pintype "passive"))
      (node (ref "SV11") (pin "2") (pinfunction "2_2") (pintype "passive"))
      (node (ref "SV11") (pin "3") (pinfunction "3_3") (pintype "passive"))
      (node (ref "SV11") (pin "4") (pinfunction "4_4") (pintype "passive"))
      (node (ref "SV11") (pin "5") (pinfunction "5_5") (pintype "passive"))
      (node (ref "SV11") (pin "6") (pinfunction "6_6") (pintype "passive"))
      (node (ref "SV11") (pin "7") (pinfunction "7_7") (pintype "passive"))
      (node (ref "SV11") (pin "8") (pinfunction "8_8") (pintype "passive"))
      (node (ref "SV11") (pin "9") (pinfunction "9_9") (pintype "passive"))
      (node (ref "SV125") (pin "1") (pinfunction "1_1") (pintype "passive"))
      (node (ref "SV125") (pin "10") (pinfunction "10_10") (pintype "passive"))
      (node (ref "SV125") (pin "11") (pinfunction "11_11") (pintype "passive"))
      (node (ref "SV125") (pin "12") (pinfunction "12_12") (pintype "passive"))
      (node (ref "SV125") (pin "13") (pinfunction "13_13") (pintype "passive"))
      (node (ref "SV125") (pin "14") (pinfunction "14_14") (pintype "passive"))
      (node (ref "SV125") (pin "15") (pinfunction "15_15") (pintype "passive"))
      (node (ref "SV125") (pin "16") (pinfunction "16_16") (pintype "passive"))
      (node (ref "SV125") (pin "17") (pinfunction "17_17") (pintype "passive"))
      (node (ref "SV125") (pin "18") (pinfunction "18_18") (pintype "passive"))
      (node (ref "SV125") (pin "19") (pinfunction "19_19") (pintype "passive"))
      (node (ref "SV125") (pin "2") (pinfunction "2_2") (pintype "passive"))
      (node (ref "SV125") (pin "20") (pinfunction "20_20") (pintype "passive"))
      (node (ref "SV125") (pin "3") (pinfunction "3_3") (pintype "passive"))
      (node (ref "SV125") (pin "4") (pinfunction "4_4") (pintype "passive"))
      (node (ref "SV125") (pin "5") (pinfunction "5_5") (pintype "passive"))
      (node (ref "SV125") (pin "6") (pinfunction "6_6") (pintype "passive"))
      (node (ref "SV125") (pin "7") (pinfunction "7_7") (pintype "passive"))
      (node (ref "SV125") (pin "8") (pinfunction "8_8") (pintype "passive"))
      (node (ref "SV125") (pin "9") (pinfunction "9_9") (pintype "passive"))
      (node (ref "SV127") (pin "1") (pinfunction "1_1") (pintype "passive"))
      (node (ref "SV127") (pin "2") (pinfunction "2_2") (pintype "passive"))
      (node (ref "SV127") (pin "3") (pinfunction "3_3") (pintype "passive"))
      (node (ref "SV127") (pin "4") (pinfunction "4_4") (pintype "passive"))
      (node (ref "SV127") (pin "5") (pinfunction "5_5") (pintype "passive"))
      (node (ref "SV127") (pin "6") (pinfunction "6_6") (pintype "passive"))
      (node (ref "SV127") (pin "7") (pinfunction "7_7") (pintype "passive"))
      (node (ref "SV127") (pin "8") (pinfunction "8_8") (pintype "passive"))
      (node (ref "SV129") (pin "1") (pinfunction "1_1") (pintype "passive"))
      (node (ref "SV129") (pin "10") (pinfunction "10_10") (pintype "passive"))
      (node (ref "SV129") (pin "2") (pinfunction "2_2") (pintype "passive"))
      (node (ref "SV129") (pin "3") (pinfunction "3_3") (pintype "passive"))
      (node (ref "SV129") (pin "4") (pinfunction "4_4") (pintype "passive"))
      (node (ref "SV129") (pin "5") (pinfunction "5_5") (pintype "passive"))
      (node (ref "SV129") (pin "6") (pinfunction "6_6") (pintype "passive"))
      (node (ref "SV129") (pin "7") (pinfunction "7_7") (pintype "passive"))
      (node (ref "SV129") (pin "8") (pinfunction "8_8") (pintype "passive"))
      (node (ref "SV129") (pin "9") (pinfunction "9_9") (pintype "passive"))
      (node (ref "SV131") (pin "1") (pinfunction "1_1") (pintype "passive"))
      (node (ref "SV131") (pin "10") (pinfunction "10_10") (pintype "passive"))
      (node (ref "SV131") (pin "11") (pinfunction "11_11") (pintype "passive"))
      (node (ref "SV131") (pin "12") (pinfunction "12_12") (pintype "passive"))
      (node (ref "SV131") (pin "13") (pinfunction "13_13") (pintype "passive"))
      (node (ref "SV131") (pin "14") (pinfunction "14_14") (pintype "passive"))
      (node (ref "SV131") (pin "15") (pinfunction "15_15") (pintype "passive"))
      (node (ref "SV131") (pin "16") (pinfunction "16_16") (pintype "passive"))
      (node (ref "SV131") (pin "17") (pinfunction "17_17") (pintype "passive"))
      (node (ref "SV131") (pin "18") (pinfunction "18_18") (pintype "passive"))
      (node (ref "SV131") (pin "19") (pinfunction "19_19") (pintype "passive"))
      (node (ref "SV131") (pin "2") (pinfunction "2_2") (pintype "passive"))
      (node (ref "SV131") (pin "20") (pinfunction "20_20") (pintype "passive"))
      (node (ref "SV131") (pin "3") (pinfunction "3_3") (pintype "passive"))
      (node (ref "SV131") (pin "4") (pinfunction "4_4") (pintype "passive"))
      (node (ref "SV131") (pin "5") (pinfunction "5_5") (pintype "passive"))
      (node (ref "SV131") (pin "6") (pinfunction "6_6") (pintype "passive"))
      (node (ref "SV131") (pin "7") (pinfunction "7_7") (pintype "passive"))
      (node (ref "SV131") (pin "8") (pinfunction "8_8") (pintype "passive"))
      (node (ref "SV131") (pin "9") (pinfunction "9_9") (pintype "passive"))
      (node (ref "SV175") (pin "1") (pinfunction "1_1") (pintype "passive"))
      (node (ref "SV175") (pin "10") (pinfunction "10_10") (pintype "passive"))
      (node (ref "SV175") (pin "11") (pinfunction "11_11") (pintype "passive"))
      (node (ref "SV175") (pin "12") (pinfunction "12_12") (pintype "passive"))
      (node (ref "SV175") (pin "13") (pinfunction "13_13") (pintype "passive"))
      (node (ref "SV175") (pin "14") (pinfunction "14_14") (pintype "passive"))
      (node (ref "SV175") (pin "15") (pinfunction "15_15") (pintype "passive"))
      (node (ref "SV175") (pin "16") (pinfunction "16_16") (pintype "passive"))
      (node (ref "SV175") (pin "17") (pinfunction "17_17") (pintype "passive"))
      (node (ref "SV175") (pin "18") (pinfunction "18_18") (pintype "passive"))
      (node (ref "SV175") (pin "19") (pinfunction "19_19") (pintype "passive"))
      (node (ref "SV175") (pin "2") (pinfunction "2_2") (pintype "passive"))
      (node (ref "SV175") (pin "20") (pinfunction "20_20") (pintype "passive"))
      (node (ref "SV175") (pin "3") (pinfunction "3_3") (pintype "passive"))
      (node (ref "SV175") (pin "4") (pinfunction "4_4") (pintype "passive"))
      (node (ref "SV175") (pin "5") (pinfunction "5_5") (pintype "passive"))
      (node (ref "SV175") (pin "6") (pinfunction "6_6") (pintype "passive"))
      (node (ref "SV175") (pin "7") (pinfunction "7_7") (pintype "passive"))
      (node (ref "SV175") (pin "8") (pinfunction "8_8") (pintype "passive"))
      (node (ref "SV175") (pin "9") (pinfunction "9_9") (pintype "passive"))
      (node (ref "SV177") (pin "1") (pinfunction "1_1") (pintype "passive"))
      (node (ref "SV177") (pin "2") (pinfunction "2_2") (pintype "passive"))
      (node (ref "SV177") (pin "3") (pinfunction "3_3") (pintype "passive"))
      (node (ref "SV177") (pin "4") (pinfunction "4_4") (pintype "passive"))
      (node (ref "SV177") (pin "5") (pinfunction "5_5") (pintype "passive"))
      (node (ref "SV177") (pin "6") (pinfunction "6_6") (pintype "passive"))
      (node (ref "SV177") (pin "7") (pinfunction "7_7") (pintype "passive"))
      (node (ref "SV177") (pin "8") (pinfunction "8_8") (pintype "passive"))
      (node (ref "SV178") (pin "1") (pinfunction "1_1") (pintype "passive"))
      (node (ref "SV178") (pin "2") (pinfunction "2_2") (pintype "passive"))
      (node (ref "SV178") (pin "3") (pinfunction "3_3") (pintype "passive"))
      (node (ref "SV178") (pin "4") (pinfunction "4_4") (pintype "passive"))
      (node (ref "SV178") (pin "5") (pinfunction "5_5") (pintype "passive"))
      (node (ref "SV178") (pin "6") (pinfunction "6_6") (pintype "passive"))
      (node (ref "SV178") (pin "7") (pinfunction "7_7") (pintype "passive"))
      (node (ref "SV178") (pin "8") (pinfunction "8_8") (pintype "passive"))
      (node (ref "SV179") (pin "1") (pinfunction "1_1") (pintype "passive"))
      (node (ref "SV179") (pin "10") (pinfunction "10_10") (pintype "passive"))
      (node (ref "SV179") (pin "2") (pinfunction "2_2") (pintype "passive"))
      (node (ref "SV179") (pin "3") (pinfunction "3_3") (pintype "passive"))
      (node (ref "SV179") (pin "4") (pinfunction "4_4") (pintype "passive"))
      (node (ref "SV179") (pin "5") (pinfunction "5_5") (pintype "passive"))
      (node (ref "SV179") (pin "6") (pinfunction "6_6") (pintype "passive"))
      (node (ref "SV179") (pin "7") (pinfunction "7_7") (pintype "passive"))
      (node (ref "SV179") (pin "8") (pinfunction "8_8") (pintype "passive"))
      (node (ref "SV179") (pin "9") (pinfunction "9_9") (pintype "passive"))
      (node (ref "SV3") (pin "1") (pinfunction "1_1") (pintype "passive"))
      (node (ref "SV3") (pin "10") (pinfunction "10_10") (pintype "passive"))
      (node (ref "SV3") (pin "11") (pinfunction "11_11") (pintype "passive"))
      (node (ref "SV3") (pin "12") (pinfunction "12_12") (pintype "passive"))
      (node (ref "SV3") (pin "13") (pinfunction "13_13") (pintype "passive"))
      (node (ref "SV3") (pin "14") (pinfunction "14_14") (pintype "passive"))
      (node (ref "SV3") (pin "15") (pinfunction "15_15") (pintype "passive"))
      (node (ref "SV3") (pin "16") (pinfunction "16_16") (pintype "passive"))
      (node (ref "SV3") (pin "17") (pinfunction "17_17") (pintype "passive"))
      (node (ref "SV3") (pin "18") (pinfunction "18_18") (pintype "passive"))
      (node (ref "SV3") (pin "19") (pinfunction "19_19") (pintype "passive"))
      (node (ref "SV3") (pin "2") (pinfunction "2_2") (pintype "passive"))
      (node (ref "SV3") (pin "20") (pinfunction "20_20") (pintype "passive"))
      (node (ref "SV3") (pin "3") (pinfunction "3_3") (pintype "passive"))
      (node (ref "SV3") (pin "4") (pinfunction "4_4") (pintype "passive"))
      (node (ref "SV3") (pin "5") (pinfunction "5_5") (pintype "passive"))
      (node (ref "SV3") (pin "6") (pinfunction "6_6") (pintype "passive"))
      (node (ref "SV3") (pin "7") (pinfunction "7_7") (pintype "passive"))
      (node (ref "SV3") (pin "8") (pinfunction "8_8") (pintype "passive"))
      (node (ref "SV3") (pin "9") (pinfunction "9_9") (pintype "passive"))
      (node (ref "SV5") (pin "1") (pinfunction "1_1") (pintype "passive"))
      (node (ref "SV5") (pin "10") (pinfunction "10_10") (pintype "passive"))
      (node (ref "SV5") (pin "11") (pinfunction "11_11") (pintype "passive"))
      (node (ref "SV5") (pin "12") (pinfunction "12_12") (pintype "passive"))
      (node (ref "SV5") (pin "13") (pinfunction "13_13") (pintype "passive"))
      (node (ref "SV5") (pin "14") (pinfunction "14_14") (pintype "passive"))
      (node (ref "SV5") (pin "15") (pinfunction "15_15") (pintype "passive"))
      (node (ref "SV5") (pin "16") (pinfunction "16_16") (pintype "passive"))
      (node (ref "SV5") (pin "17") (pinfunction "17_17") (pintype "passive"))
      (node (ref "SV5") (pin "18") (pinfunction "18_18") (pintype "passive"))
      (node (ref "SV5") (pin "19") (pinfunction "19_19") (pintype "passive"))
      (node (ref "SV5") (pin "2") (pinfunction "2_2") (pintype "passive"))
      (node (ref "SV5") (pin "20") (pinfunction "20_20") (pintype "passive"))
      (node (ref "SV5") (pin "3") (pinfunction "3_3") (pintype "passive"))
      (node (ref "SV5") (pin "4") (pinfunction "4_4") (pintype "passive"))
      (node (ref "SV5") (pin "5") (pinfunction "5_5") (pintype "passive"))
      (node (ref "SV5") (pin "6") (pinfunction "6_6") (pintype "passive"))
      (node (ref "SV5") (pin "7") (pinfunction "7_7") (pintype "passive"))
      (node (ref "SV5") (pin "8") (pinfunction "8_8") (pintype "passive"))
      (node (ref "SV5") (pin "9") (pinfunction "9_9") (pintype "passive"))
      (node (ref "SV9") (pin "1") (pinfunction "1_1") (pintype "passive"))
      (node (ref "SV9") (pin "2") (pinfunction "2_2") (pintype "passive"))
      (node (ref "SV9") (pin "3") (pinfunction "3_3") (pintype "passive"))
      (node (ref "SV9") (pin "4") (pinfunction "4_4") (pintype "passive"))
      (node (ref "SV9") (pin "5") (pinfunction "5_5") (pintype "passive"))
      (node (ref "SV9") (pin "6") (pinfunction "6_6") (pintype "passive"))
      (node (ref "SV9") (pin "7") (pinfunction "7_7") (pintype "passive"))
      (node (ref "SV9") (pin "8") (pinfunction "8_8") (pintype "passive"))
      (node (ref "U$2") (pin "AA2") (pinfunction "1_AA2") (pintype "bidirectional"))
      (node (ref "U$2") (pin "BA2") (pinfunction "1_BA2") (pintype "bidirectional"))
      (node (ref "U$2") (pin "CA2") (pinfunction "1_CA2") (pintype "bidirectional"))
      (node (ref "VCC1") (pin "1") (pinfunction "1_1") (pintype "passive"))
      (node (ref "VCC1") (pin "2") (pinfunction "2_2") (pintype "passive"))
      (node (ref "VCC10") (pin "1") (pinfunction "1_1") (pintype "passive"))
      (node (ref "VCC10") (pin "2") (pinfunction "2_2") (pintype "passive"))
      (node (ref "VCC11") (pin "1") (pinfunction "1_1") (pintype "passive"))
      (node (ref "VCC11") (pin "2") (pinfunction "2_2") (pintype "passive"))
      (node (ref "VCC12") (pin "1") (pinfunction "1_1") (pintype "passive"))
      (node (ref "VCC12") (pin "2") (pinfunction "2_2") (pintype "passive"))
      (node (ref "VCC13") (pin "1") (pinfunction "1_1") (pintype "passive"))
      (node (ref "VCC13") (pin "2") (pinfunction "2_2") (pintype "passive"))
      (node (ref "VCC14") (pin "1") (pinfunction "1_1") (pintype "passive"))
      (node (ref "VCC14") (pin "2") (pinfunction "2_2") (pintype "passive"))
      (node (ref "VCC15") (pin "1") (pinfunction "1_1") (pintype "passive"))
      (node (ref "VCC15") (pin "2") (pinfunction "2_2") (pintype "passive"))
      (node (ref "VCC16") (pin "1") (pinfunction "1_1") (pintype "passive"))
      (node (ref "VCC16") (pin "2") (pinfunction "2_2") (pintype "passive"))
      (node (ref "VCC17") (pin "1") (pinfunction "1_1") (pintype "passive"))
      (node (ref "VCC17") (pin "2") (pinfunction "2_2") (pintype "passive"))
      (node (ref "VCC18") (pin "1") (pinfunction "1_1") (pintype "passive"))
      (node (ref "VCC18") (pin "2") (pinfunction "2_2") (pintype "passive"))
      (node (ref "VCC19") (pin "1") (pinfunction "1_1") (pintype "passive"))
      (node (ref "VCC19") (pin "2") (pinfunction "2_2") (pintype "passive"))
      (node (ref "VCC2") (pin "1") (pinfunction "1_1") (pintype "passive"))
      (node (ref "VCC2") (pin "2") (pinfunction "2_2") (pintype "passive"))
      (node (ref "VCC20") (pin "1") (pinfunction "1_1") (pintype "passive"))
      (node (ref "VCC20") (pin "2") (pinfunction "2_2") (pintype "passive"))
      (node (ref "VCC21") (pin "1") (pinfunction "1_1") (pintype "passive"))
      (node (ref "VCC21") (pin "2") (pinfunction "2_2") (pintype "passive"))
      (node (ref "VCC22") (pin "1") (pinfunction "1_1") (pintype "passive"))
      (node (ref "VCC22") (pin "2") (pinfunction "2_2") (pintype "passive"))
      (node (ref "VCC23") (pin "1") (pinfunction "1_1") (pintype "passive"))
      (node (ref "VCC23") (pin "2") (pinfunction "2_2") (pintype "passive"))
      (node (ref "VCC24") (pin "1") (pinfunction "1_1") (pintype "passive"))
      (node (ref "VCC24") (pin "2") (pinfunction "2_2") (pintype "passive"))
      (node (ref "VCC25") (pin "1") (pinfunction "1_1") (pintype "passive"))
      (node (ref "VCC25") (pin "2") (pinfunction "2_2") (pintype "passive"))
      (node (ref "VCC26") (pin "1") (pinfunction "1_1") (pintype "passive"))
      (node (ref "VCC26") (pin "2") (pinfunction "2_2") (pintype "passive"))
      (node (ref "VCC27") (pin "1") (pinfunction "1_1") (pintype "passive"))
      (node (ref "VCC27") (pin "2") (pinfunction "2_2") (pintype "passive"))
      (node (ref "VCC28") (pin "1") (pinfunction "1_1") (pintype "passive"))
      (node (ref "VCC28") (pin "2") (pinfunction "2_2") (pintype "passive"))
      (node (ref "VCC29") (pin "1") (pinfunction "1_1") (pintype "passive"))
      (node (ref "VCC29") (pin "2") (pinfunction "2_2") (pintype "passive"))
      (node (ref "VCC3") (pin "1") (pinfunction "1_1") (pintype "passive"))
      (node (ref "VCC3") (pin "2") (pinfunction "2_2") (pintype "passive"))
      (node (ref "VCC30") (pin "1") (pinfunction "1_1") (pintype "passive"))
      (node (ref "VCC30") (pin "2") (pinfunction "2_2") (pintype "passive"))
      (node (ref "VCC31") (pin "1") (pinfunction "1_1") (pintype "passive"))
      (node (ref "VCC31") (pin "2") (pinfunction "2_2") (pintype "passive"))
      (node (ref "VCC32") (pin "1") (pinfunction "1_1") (pintype "passive"))
      (node (ref "VCC32") (pin "2") (pinfunction "2_2") (pintype "passive"))
      (node (ref "VCC33") (pin "1") (pinfunction "1_1") (pintype "passive"))
      (node (ref "VCC33") (pin "2") (pinfunction "2_2") (pintype "passive"))
      (node (ref "VCC34") (pin "1") (pinfunction "1_1") (pintype "passive"))
      (node (ref "VCC34") (pin "2") (pinfunction "2_2") (pintype "passive"))
      (node (ref "VCC35") (pin "1") (pinfunction "1_1") (pintype "passive"))
      (node (ref "VCC35") (pin "2") (pinfunction "2_2") (pintype "passive"))
      (node (ref "VCC36") (pin "1") (pinfunction "1_1") (pintype "passive"))
      (node (ref "VCC36") (pin "2") (pinfunction "2_2") (pintype "passive"))
      (node (ref "VCC37") (pin "1") (pinfunction "1_1") (pintype "passive"))
      (node (ref "VCC37") (pin "2") (pinfunction "2_2") (pintype "passive"))
      (node (ref "VCC38") (pin "1") (pinfunction "1_1") (pintype "passive"))
      (node (ref "VCC38") (pin "2") (pinfunction "2_2") (pintype "passive"))
      (node (ref "VCC39") (pin "1") (pinfunction "1_1") (pintype "passive"))
      (node (ref "VCC39") (pin "2") (pinfunction "2_2") (pintype "passive"))
      (node (ref "VCC4") (pin "1") (pinfunction "1_1") (pintype "passive"))
      (node (ref "VCC4") (pin "2") (pinfunction "2_2") (pintype "passive"))
      (node (ref "VCC40") (pin "1") (pinfunction "1_1") (pintype "passive"))
      (node (ref "VCC40") (pin "2") (pinfunction "2_2") (pintype "passive"))
      (node (ref "VCC41") (pin "1") (pinfunction "1_1") (pintype "passive"))
      (node (ref "VCC41") (pin "2") (pinfunction "2_2") (pintype "passive"))
      (node (ref "VCC42") (pin "1") (pinfunction "1_1") (pintype "passive"))
      (node (ref "VCC42") (pin "2") (pinfunction "2_2") (pintype "passive"))
      (node (ref "VCC43") (pin "1") (pinfunction "1_1") (pintype "passive"))
      (node (ref "VCC43") (pin "2") (pinfunction "2_2") (pintype "passive"))
      (node (ref "VCC44") (pin "1") (pinfunction "1_1") (pintype "passive"))
      (node (ref "VCC44") (pin "2") (pinfunction "2_2") (pintype "passive"))
      (node (ref "VCC5") (pin "1") (pinfunction "1_1") (pintype "passive"))
      (node (ref "VCC5") (pin "2") (pinfunction "2_2") (pintype "passive"))
      (node (ref "VCC6") (pin "1") (pinfunction "1_1") (pintype "passive"))
      (node (ref "VCC6") (pin "2") (pinfunction "2_2") (pintype "passive"))
      (node (ref "VCC7") (pin "1") (pinfunction "1_1") (pintype "passive"))
      (node (ref "VCC7") (pin "2") (pinfunction "2_2") (pintype "passive"))
      (node (ref "VCC8") (pin "1") (pinfunction "1_1") (pintype "passive"))
      (node (ref "VCC8") (pin "2") (pinfunction "2_2") (pintype "passive"))
      (node (ref "VCC9") (pin "1") (pinfunction "1_1") (pintype "passive"))
      (node (ref "VCC9") (pin "2") (pinfunction "2_2") (pintype "passive"))
    )
    (net (code "851") (name "WRITE") (class "Default")
      (node (ref "D10") (pin "15") (pinfunction "15_15") (pintype "passive"))
      (node (ref "IC8") (pin "4") (pinfunction "A3_4") (pintype "input"))
      (node (ref "U$2") (pin "AS2") (pinfunction "1_AS2") (pintype "bidirectional"))
    )
    (net (code "852") (name "unconnected-(IC8A-Y8-Pad11)") (class "Default")
      (node (ref "IC8") (pin "11") (pinfunction "Y8_11") (pintype "tri_state"))
    )
    (net (code "853") (name "unconnected-(IC37A-Y0-Pad15)") (class "Default")
      (node (ref "IC37") (pin "15") (pinfunction "Y0_15") (pintype "output"))
    )
    (net (code "854") (name "unconnected-(IC37A-Y1-Pad14)") (class "Default")
      (node (ref "IC37") (pin "14") (pinfunction "Y1_14") (pintype "output"))
    )
    (net (code "855") (name "unconnected-(IC37A-Y2-Pad13)") (class "Default")
      (node (ref "IC37") (pin "13") (pinfunction "Y2_13") (pintype "output"))
    )
    (net (code "856") (name "unconnected-(IC37A-Y3-Pad12)") (class "Default")
      (node (ref "IC37") (pin "12") (pinfunction "Y3_12") (pintype "output"))
    )
    (net (code "857") (name "unconnected-(IC37A-Y5-Pad10)") (class "Default")
      (node (ref "IC37") (pin "10") (pinfunction "Y5_10") (pintype "output"))
    )
    (net (code "858") (name "unconnected-(IC37A-Y6-Pad9)") (class "Default")
      (node (ref "IC37") (pin "9") (pinfunction "Y6_9") (pintype "output"))
    )
    (net (code "859") (name "unconnected-(IC38A-Y1-Pad5)") (class "Default")
      (node (ref "IC38") (pin "5") (pinfunction "Y1_5") (pintype "output"))
    )
    (net (code "860") (name "unconnected-(IC38A-Y2-Pad6)") (class "Default")
      (node (ref "IC38") (pin "6") (pinfunction "Y2_6") (pintype "output"))
    )
    (net (code "861") (name "unconnected-(IC38A-Y3-Pad7)") (class "Default")
      (node (ref "IC38") (pin "7") (pinfunction "Y3_7") (pintype "output"))
    )
    (net (code "862") (name "unconnected-(IC38B-Y0-Pad12)") (class "Default")
      (node (ref "IC38") (pin "12") (pinfunction "Y0_12") (pintype "output"))
    )
    (net (code "863") (name "unconnected-(IC38B-Y1-Pad11)") (class "Default")
      (node (ref "IC38") (pin "11") (pinfunction "Y1_11") (pintype "output"))
    )
    (net (code "864") (name "unconnected-(IC38B-Y2-Pad10)") (class "Default")
      (node (ref "IC38") (pin "10") (pinfunction "Y2_10") (pintype "output"))
    )
    (net (code "865") (name "unconnected-(IC39A-Y0-Pad15)") (class "Default")
      (node (ref "IC39") (pin "15") (pinfunction "Y0_15") (pintype "output"))
    )
    (net (code "866") (name "unconnected-(IC39A-Y1-Pad14)") (class "Default")
      (node (ref "IC39") (pin "14") (pinfunction "Y1_14") (pintype "output"))
    )
    (net (code "867") (name "unconnected-(IC39A-Y2-Pad13)") (class "Default")
      (node (ref "IC39") (pin "13") (pinfunction "Y2_13") (pintype "output"))
    )
    (net (code "868") (name "unconnected-(IC39A-Y3-Pad12)") (class "Default")
      (node (ref "IC39") (pin "12") (pinfunction "Y3_12") (pintype "output"))
    )
    (net (code "869") (name "unconnected-(IC39A-Y4-Pad11)") (class "Default")
      (node (ref "IC39") (pin "11") (pinfunction "Y4_11") (pintype "output"))
    )
    (net (code "870") (name "unconnected-(IC39A-Y5-Pad10)") (class "Default")
      (node (ref "IC39") (pin "10") (pinfunction "Y5_10") (pintype "output"))
    )
    (net (code "871") (name "unconnected-(IC39A-Y7-Pad7)") (class "Default")
      (node (ref "IC39") (pin "7") (pinfunction "Y7_7") (pintype "output"))
    )
    (net (code "872") (name "unconnected-(IC40A-Y0-Pad15)") (class "Default")
      (node (ref "IC40") (pin "15") (pinfunction "Y0_15") (pintype "output"))
    )
    (net (code "873") (name "unconnected-(IC40A-Y1-Pad14)") (class "Default")
      (node (ref "IC40") (pin "14") (pinfunction "Y1_14") (pintype "output"))
    )
    (net (code "874") (name "unconnected-(IC40A-Y2-Pad13)") (class "Default")
      (node (ref "IC40") (pin "13") (pinfunction "Y2_13") (pintype "output"))
    )
    (net (code "875") (name "unconnected-(IC40A-Y3-Pad12)") (class "Default")
      (node (ref "IC40") (pin "12") (pinfunction "Y3_12") (pintype "output"))
    )
    (net (code "876") (name "unconnected-(IC40A-Y7-Pad7)") (class "Default")
      (node (ref "IC40") (pin "7") (pinfunction "Y7_7") (pintype "output"))
    )
    (net (code "877") (name "unconnected-(IC41B-Q-Pad9)") (class "Default")
      (node (ref "IC41") (pin "9") (pinfunction "Q_9") (pintype "output"))
    )
    (net (code "878") (name "unconnected-(IC42A-~{Q}-Pad6)") (class "Default")
      (node (ref "IC42") (pin "6") (pinfunction "~{Q}_6") (pintype "output"))
    )
    (net (code "879") (name "~{6131}") (class "Default")
      (node (ref "IC40") (pin "9") (pinfunction "Y6_9") (pintype "output"))
      (node (ref "IC41") (pin "10") (pinfunction "PRE_10") (pintype "input"))
    )
    (net (code "880") (name "~{6132}") (class "Default")
      (node (ref "IC40") (pin "10") (pinfunction "Y5_10") (pintype "output"))
      (node (ref "IC41") (pin "13") (pinfunction "CLR_13") (pintype "input"))
    )
    (net (code "881") (name "~{6133}") (class "Default")
      (node (ref "IC40") (pin "11") (pinfunction "Y4_11") (pintype "output"))
      (node (ref "IC43") (pin "1") (pinfunction "I0_1") (pintype "input"))
      (node (ref "IC43") (pin "6") (pinfunction "I1_6") (pintype "input"))
    )
    (net (code "882") (name "~{BREAK_CYCLE}") (class "Default")
      (node (ref "D8") (pin "10") (pinfunction "10_10") (pintype "passive"))
      (node (ref "U$2") (pin "BL2") (pinfunction "1_BL2") (pintype "bidirectional"))
    )
    (net (code "883") (name "~{BRK_DATA_CONT}") (class "Default")
      (node (ref "D8") (pin "9") (pinfunction "9_9") (pintype "passive"))
      (node (ref "U$2") (pin "BK2") (pinfunction "1_BK2") (pintype "bidirectional"))
    )
    (net (code "884") (name "~{BRK_IN_PROG}") (class "Default")
      (node (ref "D8") (pin "5") (pinfunction "5_5") (pintype "passive"))
      (node (ref "U$2") (pin "BE2") (pinfunction "1_BE2") (pintype "bidirectional"))
    )
    (net (code "885") (name "~{BUS_STROBE}") (class "Default")
      (node (ref "D11") (pin "9") (pinfunction "9_9") (pintype "passive"))
      (node (ref "U$2") (pin "CK1") (pinfunction "1_CK1") (pintype "bidirectional"))
    )
    (net (code "886") (name "~{C0}") (class "Default")
      (node (ref "D11") (pin "5") (pinfunction "5_5") (pintype "passive"))
      (node (ref "U$2") (pin "CE1") (pinfunction "1_CE1") (pintype "bidirectional"))
    )
    (net (code "887") (name "~{C1}") (class "Default")
      (node (ref "D11") (pin "7") (pinfunction "7_7") (pintype "passive"))
      (node (ref "U$2") (pin "CH1") (pinfunction "1_CH1") (pintype "bidirectional"))
    )
    (net (code "888") (name "~{C2}") (class "Default")
      (node (ref "D11") (pin "8") (pinfunction "8_8") (pintype "passive"))
      (node (ref "U$2") (pin "CJ1") (pinfunction "1_CJ1") (pintype "bidirectional"))
    )
    (net (code "889") (name "~{CE}") (class "Default")
      (node (ref "C2") (pin "1") (pinfunction "1_1") (pintype "passive"))
      (node (ref "IC3") (pin "20") (pinfunction "~{CE}_20") (pintype "input"))
      (node (ref "IC4") (pin "20") (pinfunction "~{CE}_20") (pintype "input"))
      (node (ref "Q1") (pin "1") (pinfunction "C_1") (pintype "passive"))
      (node (ref "R7") (pin "1") (pinfunction "1_1") (pintype "passive"))
    )
    (net (code "890") (name "~{CPMA_DISABLE}") (class "Default")
      (node (ref "D11") (pin "17") (pinfunction "17_17") (pintype "passive"))
      (node (ref "U$2") (pin "CU1") (pinfunction "1_CU1") (pintype "bidirectional"))
    )
    (net (code "891") (name "~{DATA0}") (class "Default")
      (node (ref "D9") (pin "14") (pinfunction "14_14") (pintype "passive"))
      (node (ref "U$2") (pin "AR1") (pinfunction "1_AR1") (pintype "bidirectional"))
    )
    (net (code "892") (name "~{DATA1}") (class "Default")
      (node (ref "D9") (pin "15") (pinfunction "15_15") (pintype "passive"))
      (node (ref "U$2") (pin "AS1") (pinfunction "1_AS1") (pintype "bidirectional"))
    )
    (net (code "893") (name "~{DATA2}") (class "Default")
      (node (ref "D9") (pin "17") (pinfunction "17_17") (pintype "passive"))
      (node (ref "U$2") (pin "AU1") (pinfunction "1_AU1") (pintype "bidirectional"))
    )
    (net (code "894") (name "~{DATA3}") (class "Default")
      (node (ref "D9") (pin "18") (pinfunction "18_18") (pintype "passive"))
      (node (ref "U$2") (pin "AV1") (pinfunction "1_AV1") (pintype "bidirectional"))
    )
    (net (code "895") (name "~{DATA4}") (class "Default")
      (node (ref "D7") (pin "14") (pinfunction "14_14") (pintype "passive"))
      (node (ref "U$2") (pin "BR1") (pinfunction "1_BR1") (pintype "bidirectional"))
    )
    (net (code "896") (name "~{DATA5}") (class "Default")
      (node (ref "D7") (pin "15") (pinfunction "15_15") (pintype "passive"))
      (node (ref "U$2") (pin "BS1") (pinfunction "1_BS1") (pintype "bidirectional"))
    )
    (net (code "897") (name "~{DATA6}") (class "Default")
      (node (ref "D7") (pin "17") (pinfunction "17_17") (pintype "passive"))
      (node (ref "U$2") (pin "BU1") (pinfunction "1_BU1") (pintype "bidirectional"))
    )
    (net (code "898") (name "~{DATA7}") (class "Default")
      (node (ref "D7") (pin "18") (pinfunction "18_18") (pintype "passive"))
      (node (ref "U$2") (pin "BV1") (pinfunction "1_BV1") (pintype "bidirectional"))
    )
    (net (code "899") (name "~{DATA8}") (class "Default")
      (node (ref "D13") (pin "14") (pinfunction "14_14") (pintype "passive"))
      (node (ref "U$2") (pin "DR1") (pinfunction "1_DR1") (pintype "bidirectional"))
    )
    (net (code "900") (name "~{DATA9}") (class "Default")
      (node (ref "D13") (pin "15") (pinfunction "15_15") (pintype "passive"))
      (node (ref "U$2") (pin "DS1") (pinfunction "1_DS1") (pintype "bidirectional"))
    )
    (net (code "901") (name "~{DATA10}") (class "Default")
      (node (ref "D13") (pin "17") (pinfunction "17_17") (pintype "passive"))
      (node (ref "U$2") (pin "DU1") (pinfunction "1_DU1") (pintype "bidirectional"))
    )
    (net (code "902") (name "~{DATA11}") (class "Default")
      (node (ref "D13") (pin "18") (pinfunction "18_18") (pintype "passive"))
      (node (ref "U$2") (pin "DV1") (pinfunction "1_DV1") (pintype "bidirectional"))
    )
    (net (code "903") (name "~{D}") (class "Default")
      (node (ref "D14") (pin "9") (pinfunction "9_9") (pintype "passive"))
      (node (ref "U$2") (pin "DK2") (pinfunction "1_DK2") (pintype "bidirectional"))
    )
    (net (code "904") (name "~{EMA0}") (class "Default")
      (node (ref "D10") (pin "4") (pinfunction "4_4") (pintype "passive"))
      (node (ref "IC3") (pin "8") (pinfunction "A2_8") (pintype "input"))
      (node (ref "IC4") (pin "8") (pinfunction "A2_8") (pintype "input"))
      (node (ref "IC5") (pin "3") (pinfunction "C_3") (pintype "input"))
      (node (ref "U$2") (pin "AD2") (pinfunction "1_AD2") (pintype "bidirectional"))
    )
    (net (code "905") (name "~{EMA1}") (class "Default")
      (node (ref "D10") (pin "5") (pinfunction "5_5") (pintype "passive"))
      (node (ref "IC3") (pin "9") (pinfunction "A1_9") (pintype "input"))
      (node (ref "IC4") (pin "9") (pinfunction "A1_9") (pintype "input"))
      (node (ref "IC5") (pin "2") (pinfunction "B_2") (pintype "input"))
      (node (ref "U$2") (pin "AE2") (pinfunction "1_AE2") (pintype "bidirectional"))
    )
    (net (code "906") (name "~{EMA2}") (class "Default")
      (node (ref "D10") (pin "7") (pinfunction "7_7") (pintype "passive"))
      (node (ref "IC3") (pin "10") (pinfunction "A0_10") (pintype "input"))
      (node (ref "IC4") (pin "10") (pinfunction "A0_10") (pintype "input"))
      (node (ref "IC5") (pin "1") (pinfunction "A_1") (pintype "input"))
      (node (ref "U$2") (pin "AH2") (pinfunction "1_AH2") (pintype "bidirectional"))
    )
    (net (code "907") (name "~{E}") (class "Default")
      (node (ref "D14") (pin "10") (pinfunction "10_10") (pintype "passive"))
      (node (ref "U$2") (pin "DL2") (pinfunction "1_DL2") (pintype "bidirectional"))
    )
    (net (code "908") (name "~{FSET}") (class "Default")
      (node (ref "D14") (pin "13") (pinfunction "13_13") (pintype "passive"))
      (node (ref "U$2") (pin "DP2") (pinfunction "1_DP2") (pintype "bidirectional"))
    )
    (net (code "909") (name "~{F}") (class "Default")
      (node (ref "D14") (pin "8") (pinfunction "8_8") (pintype "passive"))
      (node (ref "U$2") (pin "DJ2") (pinfunction "1_DJ2") (pintype "bidirectional"))
    )
    (net (code "910") (name "~{HHLHLX}") (class "Default")
      (node (ref "IC39") (pin "9") (pinfunction "Y6_9") (pintype "output"))
      (node (ref "IC40") (pin "4") (pinfunction "G2A_4") (pintype "input"))
      (node (ref "IC45") (pin "1") (pinfunction "I0_1") (pintype "input"))
    )
    (net (code "911") (name "~{IND1}") (class "Default")
      (node (ref "D12") (pin "17") (pinfunction "17_17") (pintype "passive"))
      (node (ref "U$2") (pin "CU2") (pinfunction "1_CU2") (pintype "bidirectional"))
    )
    (net (code "912") (name "~{IND2}") (class "Default")
      (node (ref "D12") (pin "18") (pinfunction "18_18") (pintype "passive"))
      (node (ref "U$2") (pin "CV2") (pinfunction "1_CV2") (pintype "bidirectional"))
    )
    (net (code "913") (name "~{INTERNAL_IO}") (class "Default")
      (node (ref "D11") (pin "10") (pinfunction "10_10") (pintype "passive"))
      (node (ref "IC45") (pin "3") (pinfunction "O_3") (pintype "output"))
      (node (ref "U$2") (pin "CL1") (pinfunction "1_CL1") (pintype "bidirectional"))
    )
    (net (code "914") (name "~{INT_RQST}") (class "Default")
      (node (ref "D11") (pin "13") (pinfunction "13_13") (pintype "passive"))
      (node (ref "IC45") (pin "5") (pinfunction "O_5") (pintype "output"))
      (node (ref "U$2") (pin "CP1") (pinfunction "1_CP1") (pintype "bidirectional"))
    )
    (net (code "915") (name "~{IO_PAUSE}") (class "Default")
      (node (ref "D11") (pin "4") (pinfunction "4_4") (pintype "passive"))
      (node (ref "IC39") (pin "5") (pinfunction "G2B_5") (pintype "input"))
      (node (ref "U$2") (pin "CD1") (pinfunction "1_CD1") (pintype "bidirectional"))
    )
    (net (code "916") (name "~{IR0}") (class "Default")
      (node (ref "D14") (pin "4") (pinfunction "4_4") (pintype "passive"))
      (node (ref "U$2") (pin "DD2") (pinfunction "1_DD2") (pintype "bidirectional"))
    )
    (net (code "917") (name "~{IR1}") (class "Default")
      (node (ref "D14") (pin "5") (pinfunction "5_5") (pintype "passive"))
      (node (ref "U$2") (pin "DE2") (pinfunction "1_DE2") (pintype "bidirectional"))
    )
    (net (code "918") (name "~{IR2}") (class "Default")
      (node (ref "D14") (pin "7") (pinfunction "7_7") (pintype "passive"))
      (node (ref "U$2") (pin "DH2") (pinfunction "1_DH2") (pintype "bidirectional"))
    )
    (net (code "919") (name "~{IRQ_ENABLE}") (class "Default")
      (node (ref "IC41") (pin "8") (pinfunction "~{Q}_8") (pintype "output"))
      (node (ref "IC45") (pin "7") (pinfunction "I0_7") (pintype "input"))
    )
    (net (code "920") (name "~{KEY_CONT}") (class "Default")
      (node (ref "D14") (pin "17") (pinfunction "17_17") (pintype "passive"))
      (node (ref "U$2") (pin "DU2") (pinfunction "1_DU2") (pintype "bidirectional"))
    )
    (net (code "921") (name "~{LA_ENABLE}") (class "Default")
      (node (ref "D8") (pin "11") (pinfunction "11_11") (pintype "passive"))
      (node (ref "U$2") (pin "BM2") (pinfunction "1_BM2") (pintype "bidirectional"))
    )
    (net (code "922") (name "~{LINK_DATA}") (class "Default")
      (node (ref "D12") (pin "14") (pinfunction "14_14") (pintype "passive"))
      (node (ref "U$2") (pin "CR2") (pinfunction "1_CR2") (pintype "bidirectional"))
    )
    (net (code "923") (name "~{LINK_LOAD}") (class "Default")
      (node (ref "D12") (pin "15") (pinfunction "15_15") (pintype "passive"))
      (node (ref "U$2") (pin "CS2") (pinfunction "1_CS2") (pintype "bidirectional"))
    )
    (net (code "924") (name "~{LINK}") (class "Default")
      (node (ref "D10") (pin "18") (pinfunction "18_18") (pintype "passive"))
      (node (ref "U$2") (pin "AV2") (pinfunction "1_AV2") (pintype "bidirectional"))
    )
    (net (code "925") (name "~{LOAD_CONT}") (class "Default")
      (node (ref "D8") (pin "7") (pinfunction "7_7") (pintype "passive"))
      (node (ref "U$2") (pin "BH2") (pinfunction "1_BH2") (pintype "bidirectional"))
    )
    (net (code "926") (name "~{MA00}") (class "Default")
      (node (ref "D9") (pin "4") (pinfunction "4_4") (pintype "passive"))
      (node (ref "IC3") (pin "21") (pinfunction "A10_21") (pintype "input"))
      (node (ref "IC4") (pin "21") (pinfunction "A10_21") (pintype "input"))
      (node (ref "U$2") (pin "AD1") (pinfunction "1_AD1") (pintype "bidirectional"))
    )
    (net (code "927") (name "~{MA01}") (class "Default")
      (node (ref "D9") (pin "5") (pinfunction "5_5") (pintype "passive"))
      (node (ref "IC3") (pin "23") (pinfunction "A11_23") (pintype "input"))
      (node (ref "IC4") (pin "23") (pinfunction "A11_23") (pintype "input"))
      (node (ref "U$2") (pin "AE1") (pinfunction "1_AE1") (pintype "bidirectional"))
    )
    (net (code "928") (name "~{MA02}") (class "Default")
      (node (ref "D9") (pin "7") (pinfunction "7_7") (pintype "passive"))
      (node (ref "IC3") (pin "24") (pinfunction "A9_24") (pintype "input"))
      (node (ref "IC4") (pin "24") (pinfunction "A9_24") (pintype "input"))
      (node (ref "U$2") (pin "AH1") (pinfunction "1_AH1") (pintype "bidirectional"))
    )
    (net (code "929") (name "~{MA03}") (class "Default")
      (node (ref "D9") (pin "8") (pinfunction "8_8") (pintype "passive"))
      (node (ref "IC3") (pin "25") (pinfunction "A8_25") (pintype "input"))
      (node (ref "IC4") (pin "25") (pinfunction "A8_25") (pintype "input"))
      (node (ref "U$2") (pin "AJ1") (pinfunction "1_AJ1") (pintype "bidirectional"))
    )
    (net (code "930") (name "~{MA04}") (class "Default")
      (node (ref "D7") (pin "4") (pinfunction "4_4") (pintype "passive"))
      (node (ref "IC3") (pin "26") (pinfunction "A13_26") (pintype "input"))
      (node (ref "IC4") (pin "26") (pinfunction "A13_26") (pintype "input"))
      (node (ref "U$2") (pin "BD1") (pinfunction "1_BD1") (pintype "bidirectional"))
    )
    (net (code "931") (name "~{MA05}") (class "Default")
      (node (ref "D7") (pin "5") (pinfunction "5_5") (pintype "passive"))
      (node (ref "IC3") (pin "1") (pinfunction "A14_1") (pintype "input"))
      (node (ref "IC4") (pin "1") (pinfunction "A14_1") (pintype "input"))
      (node (ref "U$2") (pin "BE1") (pinfunction "1_BE1") (pintype "bidirectional"))
    )
    (net (code "932") (name "~{MA06}") (class "Default")
      (node (ref "D7") (pin "7") (pinfunction "7_7") (pintype "passive"))
      (node (ref "IC3") (pin "2") (pinfunction "A12_2") (pintype "input"))
      (node (ref "IC4") (pin "2") (pinfunction "A12_2") (pintype "input"))
      (node (ref "U$2") (pin "BH1") (pinfunction "1_BH1") (pintype "bidirectional"))
    )
    (net (code "933") (name "~{MA07}") (class "Default")
      (node (ref "D7") (pin "8") (pinfunction "8_8") (pintype "passive"))
      (node (ref "IC3") (pin "3") (pinfunction "A7_3") (pintype "input"))
      (node (ref "IC4") (pin "3") (pinfunction "A7_3") (pintype "input"))
      (node (ref "U$2") (pin "BJ1") (pinfunction "1_BJ1") (pintype "bidirectional"))
    )
    (net (code "934") (name "~{MA08}") (class "Default")
      (node (ref "D13") (pin "4") (pinfunction "4_4") (pintype "passive"))
      (node (ref "IC3") (pin "4") (pinfunction "A6_4") (pintype "input"))
      (node (ref "IC4") (pin "4") (pinfunction "A6_4") (pintype "input"))
      (node (ref "U$2") (pin "DD1") (pinfunction "1_DD1") (pintype "bidirectional"))
    )
    (net (code "935") (name "~{MA09}") (class "Default")
      (node (ref "D13") (pin "5") (pinfunction "5_5") (pintype "passive"))
      (node (ref "IC3") (pin "5") (pinfunction "A5_5") (pintype "input"))
      (node (ref "IC4") (pin "5") (pinfunction "A5_5") (pintype "input"))
      (node (ref "U$2") (pin "DE1") (pinfunction "1_DE1") (pintype "bidirectional"))
    )
    (net (code "936") (name "~{MA10}") (class "Default")
      (node (ref "D13") (pin "7") (pinfunction "7_7") (pintype "passive"))
      (node (ref "IC3") (pin "6") (pinfunction "A4_6") (pintype "input"))
      (node (ref "IC4") (pin "6") (pinfunction "A4_6") (pintype "input"))
      (node (ref "U$2") (pin "DH1") (pinfunction "1_DH1") (pintype "bidirectional"))
    )
    (net (code "937") (name "~{MA11}") (class "Default")
      (node (ref "D13") (pin "8") (pinfunction "8_8") (pintype "passive"))
      (node (ref "IC3") (pin "7") (pinfunction "A3_7") (pintype "input"))
      (node (ref "IC4") (pin "7") (pinfunction "A3_7") (pintype "input"))
      (node (ref "U$2") (pin "DJ1") (pinfunction "1_DJ1") (pintype "bidirectional"))
    )
    (net (code "938") (name "~{MD00}") (class "Default")
      (node (ref "D9") (pin "9") (pinfunction "9_9") (pintype "passive"))
      (node (ref "IC1") (pin "2") (pinfunction "A1_2") (pintype "bidirectional"))
      (node (ref "U$2") (pin "AK1") (pinfunction "1_AK1") (pintype "bidirectional"))
    )
    (net (code "939") (name "~{MD01}") (class "Default")
      (node (ref "D9") (pin "10") (pinfunction "10_10") (pintype "passive"))
      (node (ref "IC1") (pin "3") (pinfunction "A2_3") (pintype "bidirectional"))
      (node (ref "U$2") (pin "AL1") (pinfunction "1_AL1") (pintype "bidirectional"))
    )
    (net (code "940") (name "~{MD02}") (class "Default")
      (node (ref "D9") (pin "11") (pinfunction "11_11") (pintype "passive"))
      (node (ref "IC1") (pin "4") (pinfunction "A3_4") (pintype "bidirectional"))
      (node (ref "U$2") (pin "AM1") (pinfunction "1_AM1") (pintype "bidirectional"))
    )
    (net (code "941") (name "~{MD03}") (class "Default")
      (node (ref "D9") (pin "13") (pinfunction "13_13") (pintype "passive"))
      (node (ref "IC1") (pin "5") (pinfunction "A4_5") (pintype "bidirectional"))
      (node (ref "IC39") (pin "3") (pinfunction "C_3") (pintype "input"))
      (node (ref "U$2") (pin "AP1") (pinfunction "1_AP1") (pintype "bidirectional"))
    )
    (net (code "942") (name "~{MD04}") (class "Default")
      (node (ref "D7") (pin "9") (pinfunction "9_9") (pintype "passive"))
      (node (ref "IC1") (pin "6") (pinfunction "A5_6") (pintype "bidirectional"))
      (node (ref "IC39") (pin "6") (pinfunction "G1_6") (pintype "input"))
      (node (ref "U$2") (pin "BK1") (pinfunction "1_BK1") (pintype "bidirectional"))
    )
    (net (code "943") (name "~{MD05}") (class "Default")
      (node (ref "D7") (pin "10") (pinfunction "10_10") (pintype "passive"))
      (node (ref "IC1") (pin "7") (pinfunction "A6_7") (pintype "bidirectional"))
      (node (ref "IC39") (pin "4") (pinfunction "G2A_4") (pintype "input"))
      (node (ref "U$2") (pin "BL1") (pinfunction "1_BL1") (pintype "bidirectional"))
    )
    (net (code "944") (name "~{MD06}") (class "Default")
      (node (ref "D7") (pin "11") (pinfunction "11_11") (pintype "passive"))
      (node (ref "IC1") (pin "8") (pinfunction "A7_8") (pintype "bidirectional"))
      (node (ref "IC39") (pin "2") (pinfunction "B_2") (pintype "input"))
      (node (ref "U$2") (pin "BM1") (pinfunction "1_BM1") (pintype "bidirectional"))
    )
    (net (code "945") (name "~{MD07}") (class "Default")
      (node (ref "D7") (pin "13") (pinfunction "13_13") (pintype "passive"))
      (node (ref "IC1") (pin "9") (pinfunction "A8_9") (pintype "bidirectional"))
      (node (ref "IC39") (pin "1") (pinfunction "A_1") (pintype "input"))
      (node (ref "U$2") (pin "BP1") (pinfunction "1_BP1") (pintype "bidirectional"))
    )
    (net (code "946") (name "~{MD08}") (class "Default")
      (node (ref "D13") (pin "9") (pinfunction "9_9") (pintype "passive"))
      (node (ref "IC2") (pin "2") (pinfunction "A1_2") (pintype "bidirectional"))
      (node (ref "IC40") (pin "5") (pinfunction "G2B_5") (pintype "input"))
      (node (ref "IC45") (pin "2") (pinfunction "I1_2") (pintype "input"))
      (node (ref "U$2") (pin "DK1") (pinfunction "1_DK1") (pintype "bidirectional"))
    )
    (net (code "947") (name "~{MD09}") (class "Default")
      (node (ref "D13") (pin "10") (pinfunction "10_10") (pintype "passive"))
      (node (ref "IC2") (pin "3") (pinfunction "A2_3") (pintype "bidirectional"))
      (node (ref "IC40") (pin "3") (pinfunction "C_3") (pintype "input"))
      (node (ref "U$2") (pin "DL1") (pinfunction "1_DL1") (pintype "bidirectional"))
    )
    (net (code "948") (name "~{MD10}") (class "Default")
      (node (ref "D13") (pin "11") (pinfunction "11_11") (pintype "passive"))
      (node (ref "IC2") (pin "4") (pinfunction "A3_4") (pintype "bidirectional"))
      (node (ref "IC40") (pin "2") (pinfunction "B_2") (pintype "input"))
      (node (ref "U$2") (pin "DM1") (pinfunction "1_DM1") (pintype "bidirectional"))
    )
    (net (code "949") (name "~{MD11}") (class "Default")
      (node (ref "D13") (pin "13") (pinfunction "13_13") (pintype "passive"))
      (node (ref "IC2") (pin "5") (pinfunction "A4_5") (pintype "bidirectional"))
      (node (ref "IC40") (pin "1") (pinfunction "A_1") (pintype "input"))
      (node (ref "U$2") (pin "DP1") (pinfunction "1_DP1") (pintype "bidirectional"))
    )
    (net (code "950") (name "~{MD_DIR}") (class "Default")
      (node (ref "C11") (pin "1") (pinfunction "1_1") (pintype "passive"))
      (node (ref "D10") (pin "9") (pinfunction "9_9") (pintype "passive"))
      (node (ref "IC37") (pin "1") (pinfunction "A_1") (pintype "input"))
      (node (ref "IC37") (pin "2") (pinfunction "B_2") (pintype "input"))
      (node (ref "IC38") (pin "14") (pinfunction "A_14") (pintype "input"))
      (node (ref "IC38") (pin "2") (pinfunction "A_2") (pintype "input"))
      (node (ref "IC38") (pin "3") (pinfunction "B_3") (pintype "input"))
      (node (ref "IC8") (pin "2") (pinfunction "A1_2") (pintype "input"))
      (node (ref "U$2") (pin "AK2") (pinfunction "1_AK2") (pintype "bidirectional"))
    )
    (net (code "951") (name "~{MEM_START}") (class "Default")
      (node (ref "D10") (pin "8") (pinfunction "8_8") (pintype "passive"))
      (node (ref "U$2") (pin "AJ2") (pinfunction "1_AJ2") (pintype "bidirectional"))
    )
    (net (code "952") (name "~{MS_DISABLE}") (class "Default")
      (node (ref "D11") (pin "18") (pinfunction "18_18") (pintype "passive"))
      (node (ref "U$2") (pin "CV1") (pinfunction "1_CV1") (pintype "bidirectional"))
    )
    (net (code "953") (name "~{NOT_LAST_TR}") (class "Default")
      (node (ref "D11") (pin "11") (pinfunction "11_11") (pintype "passive"))
      (node (ref "U$2") (pin "CM1") (pinfunction "1_CM1") (pintype "bidirectional"))
    )
    (net (code "954") (name "~{NTS_STALL}") (class "Default")
      (node (ref "D8") (pin "14") (pinfunction "14_14") (pintype "passive"))
      (node (ref "U$2") (pin "BR2") (pinfunction "1_BR2") (pintype "bidirectional"))
    )
    (net (code "955") (name "~{OVERFLOW}") (class "Default")
      (node (ref "D8") (pin "8") (pinfunction "8_8") (pintype "passive"))
      (node (ref "U$2") (pin "BJ2") (pinfunction "1_BJ2") (pintype "bidirectional"))
    )
    (net (code "956") (name "~{READ_EN}") (class "Default")
      (node (ref "IC1") (pin "1") (pinfunction "DIR_1") (pintype "input"))
      (node (ref "IC2") (pin "1") (pinfunction "DIR_1") (pintype "input"))
      (node (ref "IC3") (pin "22") (pinfunction "~{OE}_22") (pintype "input"))
      (node (ref "IC37") (pin "11") (pinfunction "Y4_11") (pintype "output"))
      (node (ref "IC38") (pin "4") (pinfunction "Y0_4") (pintype "output"))
      (node (ref "IC4") (pin "22") (pinfunction "~{OE}_22") (pintype "input"))
      (node (ref "IC7") (pin "8") (pinfunction "O_8") (pintype "output"))
    )
    (net (code "957") (name "~{ROM_ADDR}") (class "Default")
      (node (ref "D10") (pin "17") (pinfunction "17_17") (pintype "passive"))
      (node (ref "IC5") (pin "6") (pinfunction "G1_6") (pintype "input"))
      (node (ref "U$2") (pin "AU2") (pinfunction "1_AU2") (pintype "bidirectional"))
    )
    (net (code "958") (name "~{RUN}") (class "Default")
      (node (ref "D8") (pin "17") (pinfunction "17_17") (pintype "passive"))
      (node (ref "U$2") (pin "BU2") (pinfunction "1_BU2") (pintype "bidirectional"))
    )
    (net (code "959") (name "~{SKIP}") (class "Default")
      (node (ref "D11") (pin "15") (pinfunction "15_15") (pintype "passive"))
      (node (ref "IC43") (pin "5") (pinfunction "O_5") (pintype "output"))
      (node (ref "U$2") (pin "CS1") (pinfunction "1_CS1") (pintype "bidirectional"))
    )
    (net (code "960") (name "~{SOURCE}") (class "Default")
      (node (ref "IC8") (pin "14") (pinfunction "Y5_14") (pintype "tri_state"))
      (node (ref "IC8") (pin "7") (pinfunction "A6_7") (pintype "input"))
    )
    (net (code "961") (name "~{STOP}") (class "Default")
      (node (ref "D14") (pin "15") (pinfunction "15_15") (pintype "passive"))
      (node (ref "U$2") (pin "DS2") (pinfunction "1_DS2") (pintype "bidirectional"))
    )
    (net (code "962") (name "~{TS1}") (class "Default")
      (node (ref "D12") (pin "9") (pinfunction "9_9") (pintype "passive"))
      (node (ref "U$2") (pin "CK2") (pinfunction "1_CK2") (pintype "bidirectional"))
    )
    (net (code "963") (name "~{TS2}") (class "Default")
      (node (ref "D12") (pin "10") (pinfunction "10_10") (pintype "passive"))
      (node (ref "U$2") (pin "CL2") (pinfunction "1_CL2") (pintype "bidirectional"))
    )
    (net (code "964") (name "~{TS3}") (class "Default")
      (node (ref "D12") (pin "11") (pinfunction "11_11") (pintype "passive"))
      (node (ref "U$2") (pin "CM2") (pinfunction "1_CM2") (pintype "bidirectional"))
    )
    (net (code "965") (name "~{TS4}") (class "Default")
      (node (ref "D12") (pin "13") (pinfunction "13_13") (pintype "passive"))
      (node (ref "U$2") (pin "CP2") (pinfunction "1_CP2") (pintype "bidirectional"))
    )
    (net (code "966") (name "~{USER_MODE}") (class "Default")
      (node (ref "D14") (pin "11") (pinfunction "11_11") (pintype "passive"))
      (node (ref "U$2") (pin "DM2") (pinfunction "1_DM2") (pintype "bidirectional"))
    )
    (net (code "967") (name "~{WRITE_EN}") (class "Default")
      (node (ref "IC3") (pin "27") (pinfunction "~{WE}_27") (pintype "input"))
      (node (ref "IC37") (pin "7") (pinfunction "Y7_7") (pintype "output"))
      (node (ref "IC38") (pin "9") (pinfunction "Y3_9") (pintype "output"))
      (node (ref "IC4") (pin "27") (pinfunction "~{WE}_27") (pintype "input"))
      (node (ref "IC7") (pin "6") (pinfunction "O_6") (pintype "output"))
    )
  )
)
